# NeuraCore-Final.net
KiCad netlist of a schematic drawn in EasyEDA Pro
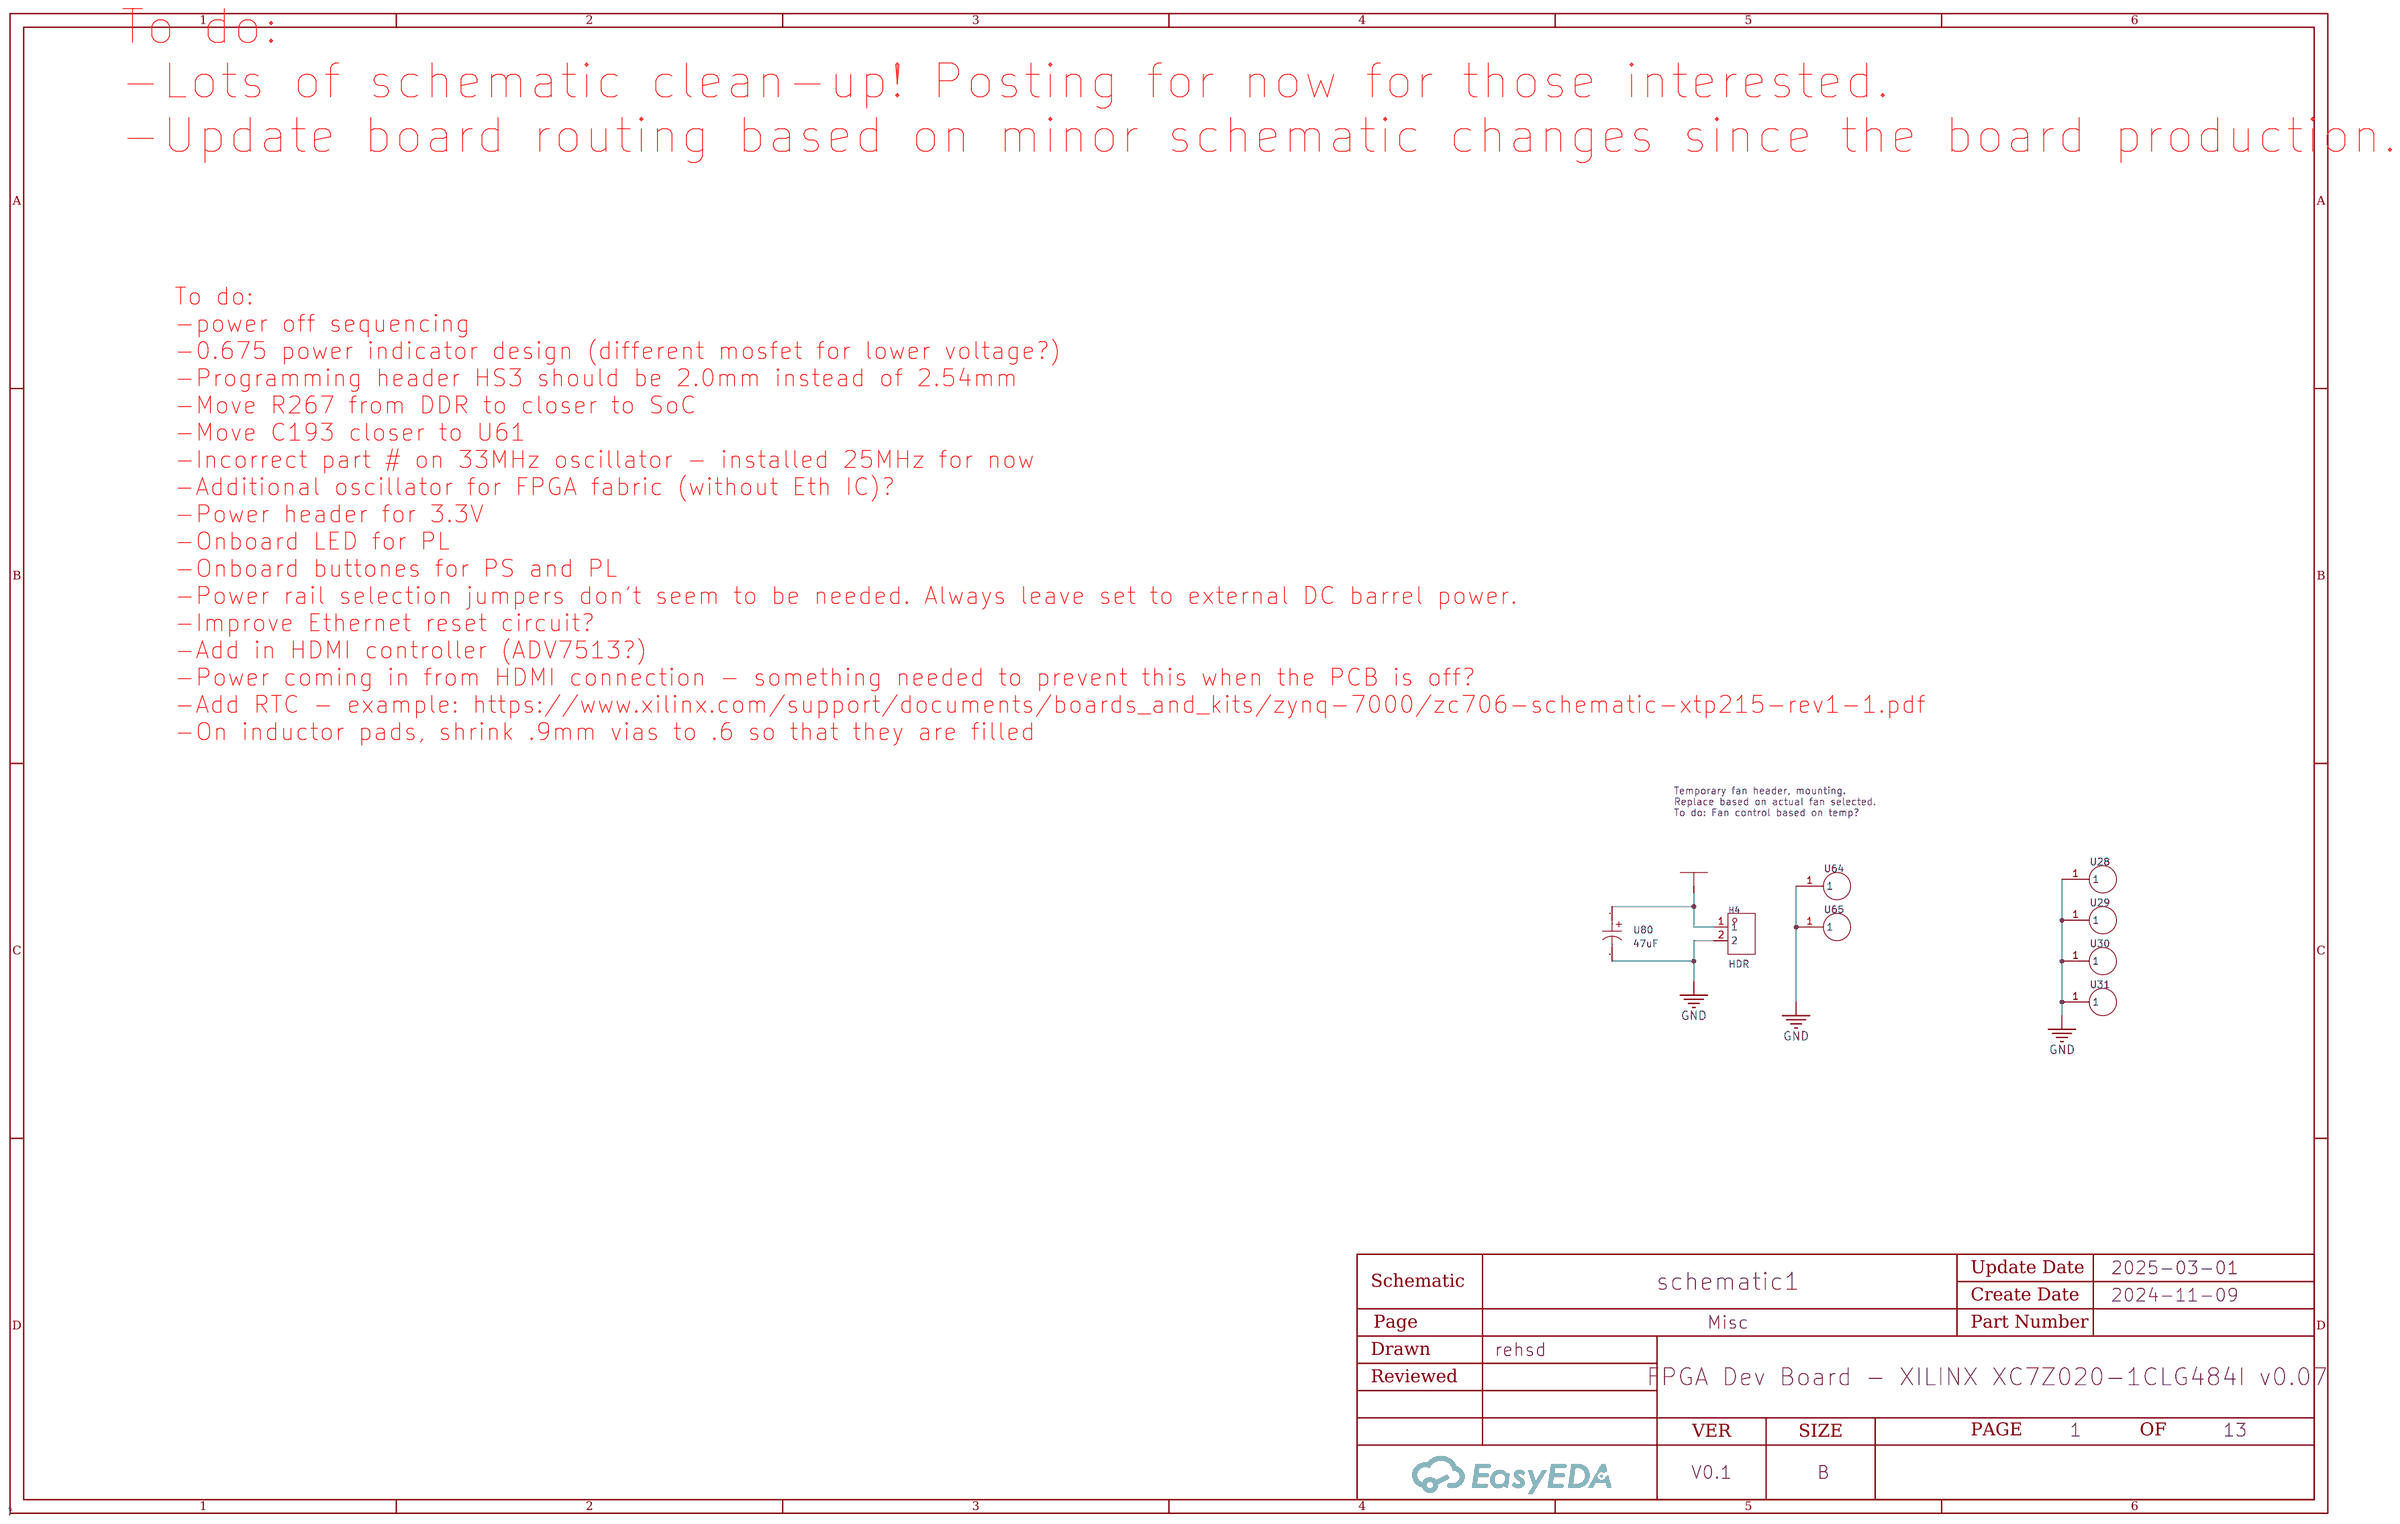
[diagram p0: Misc]
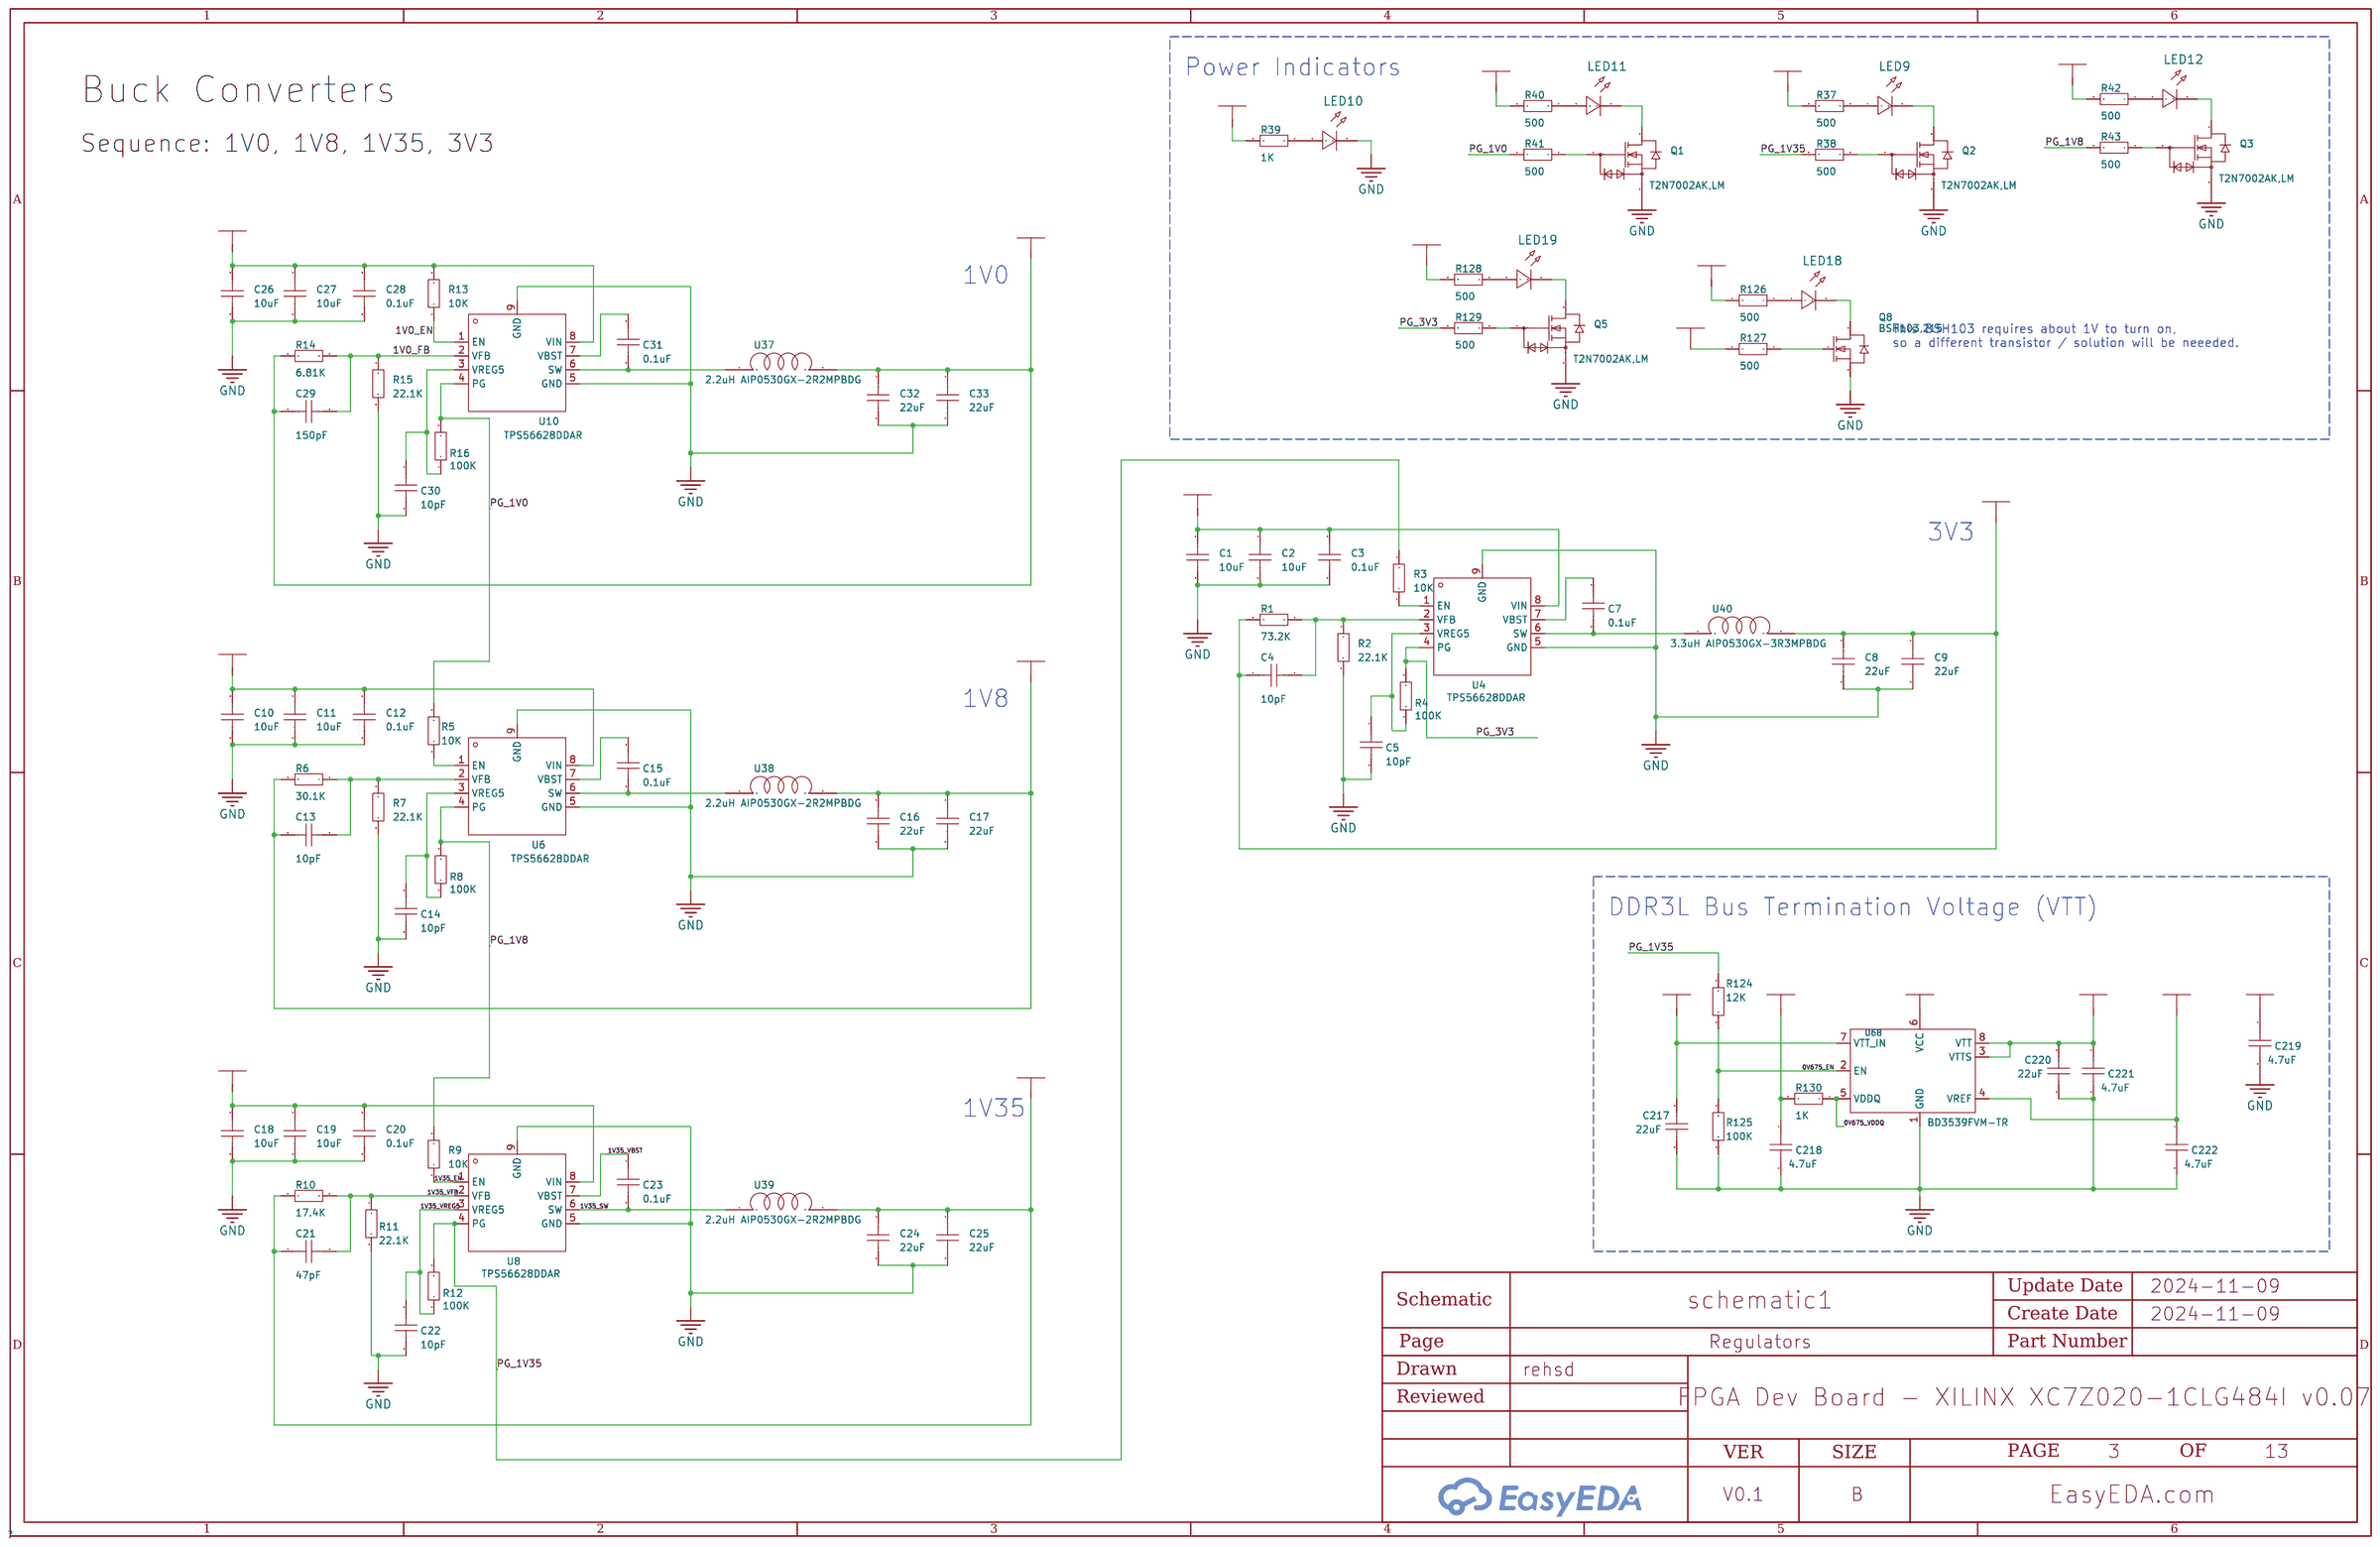
[diagram p1: Regulators]
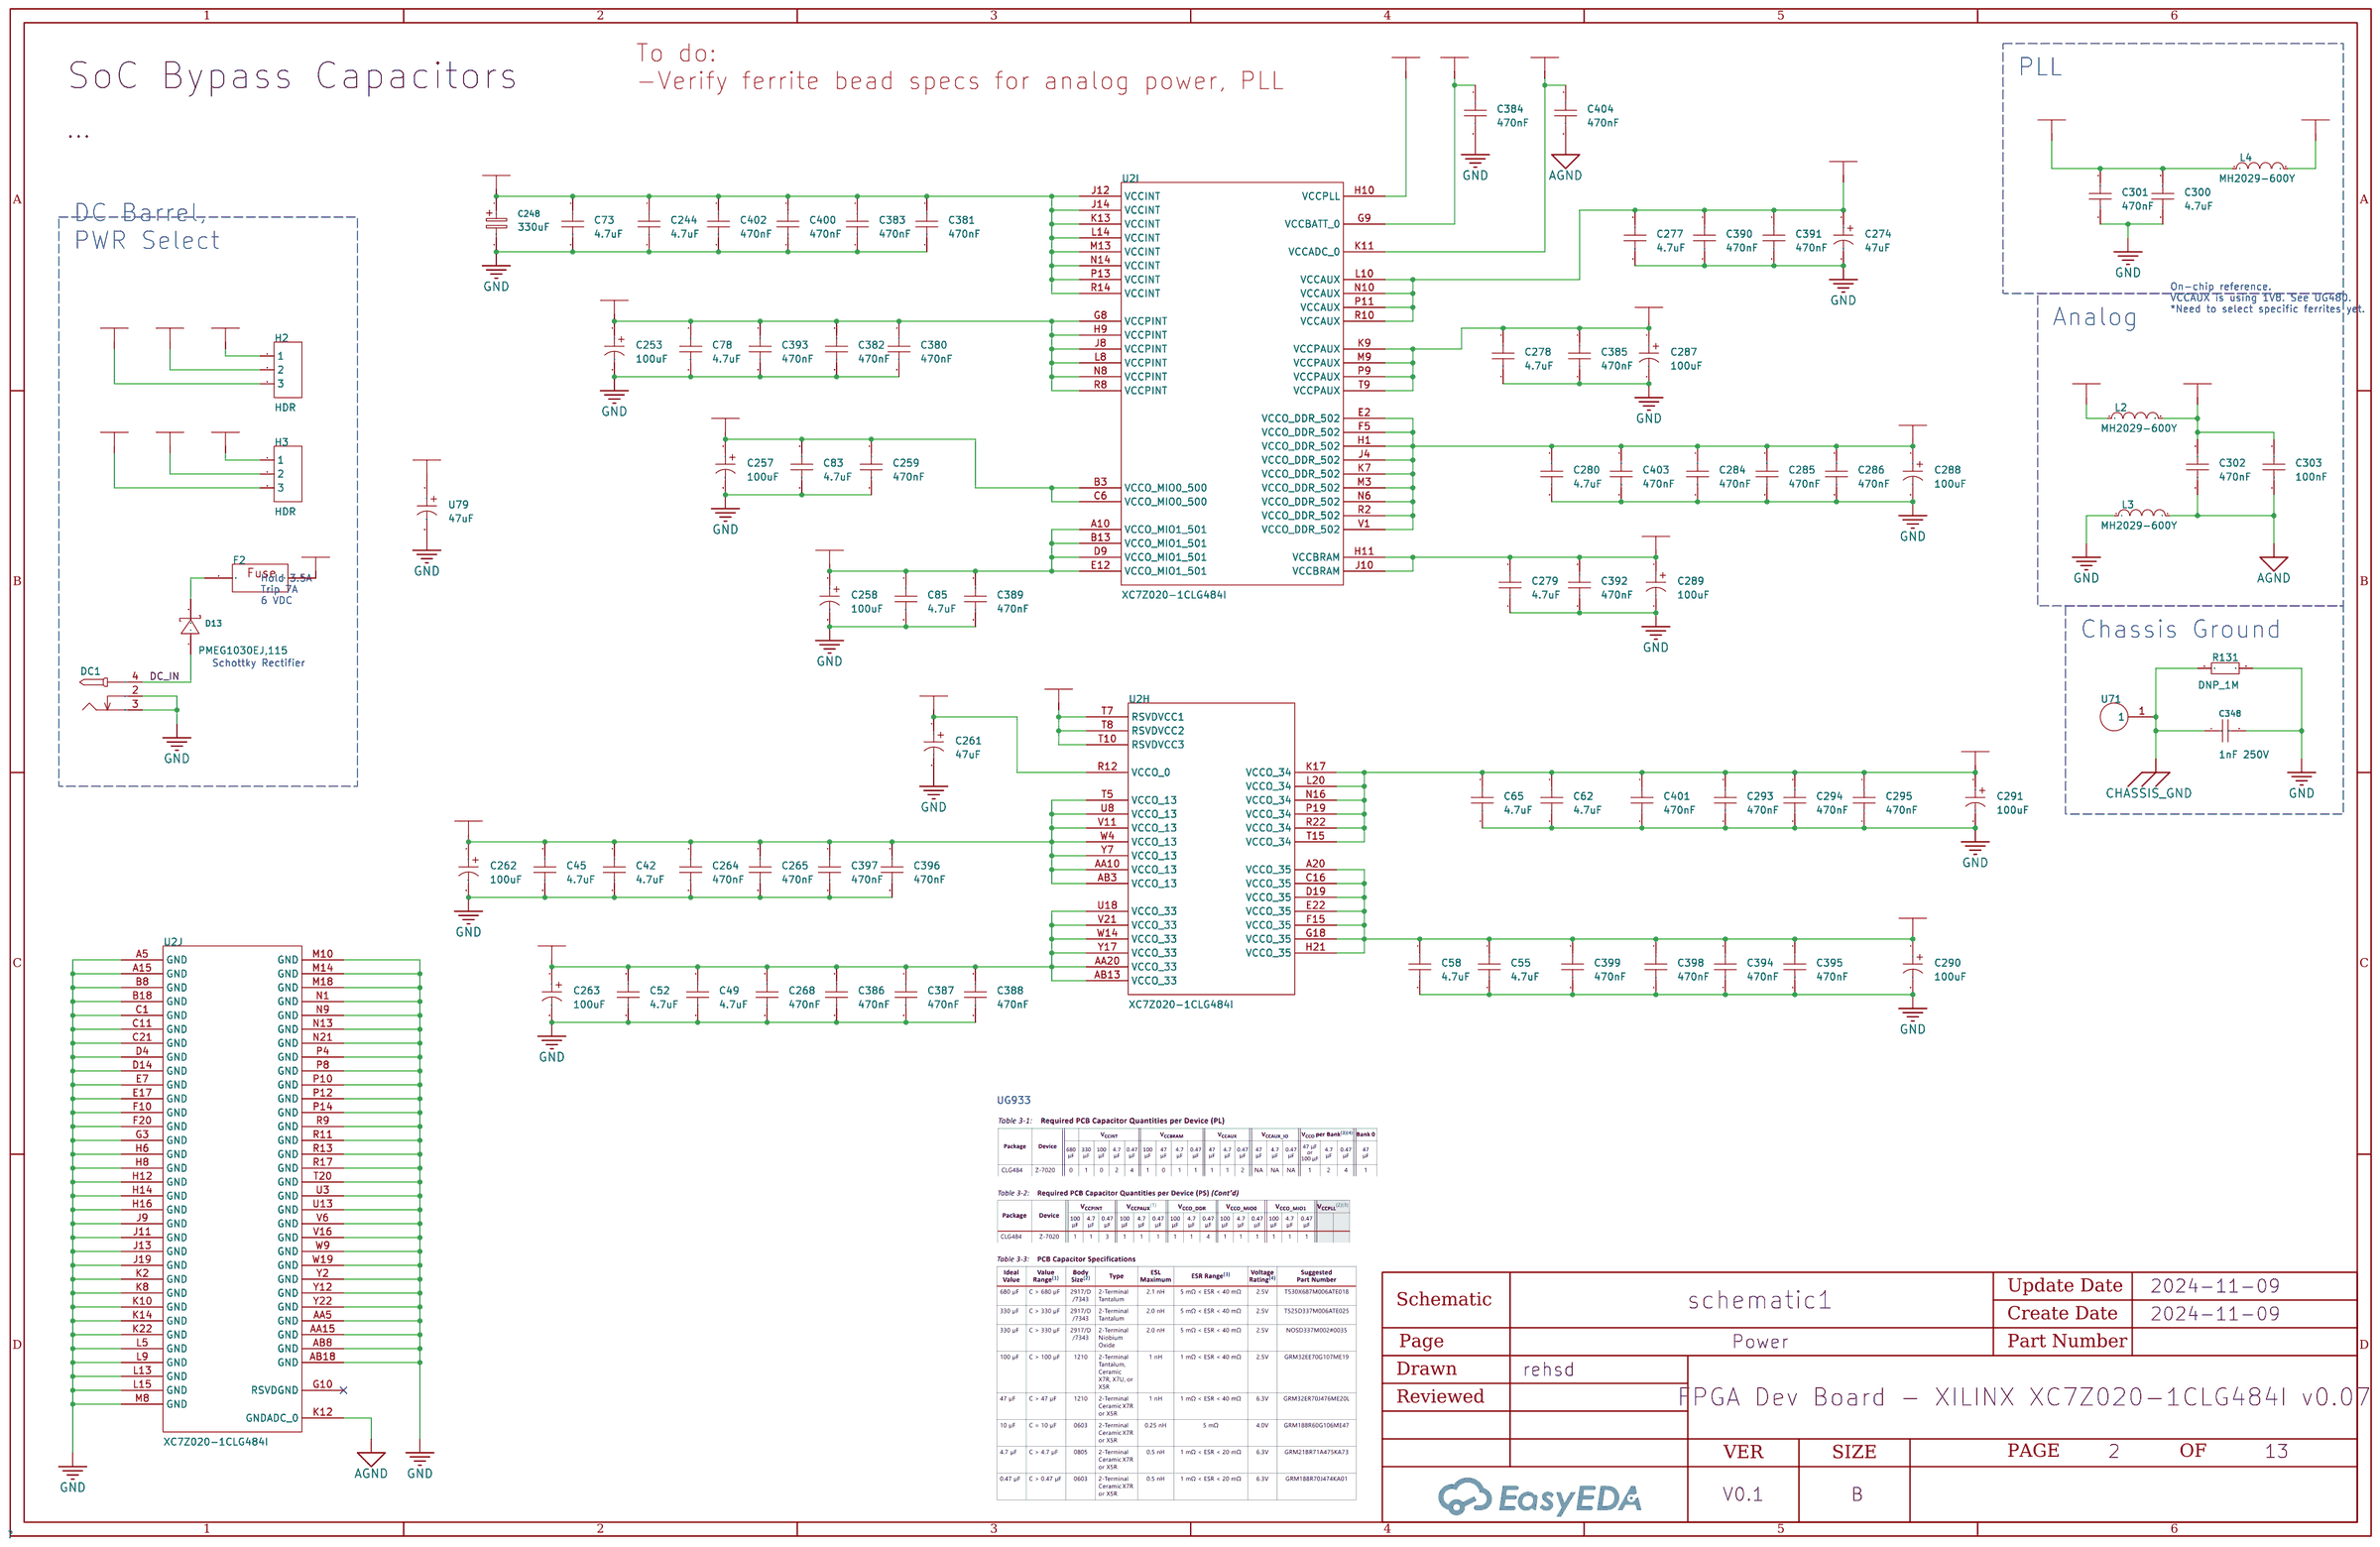
[diagram p2: Power]
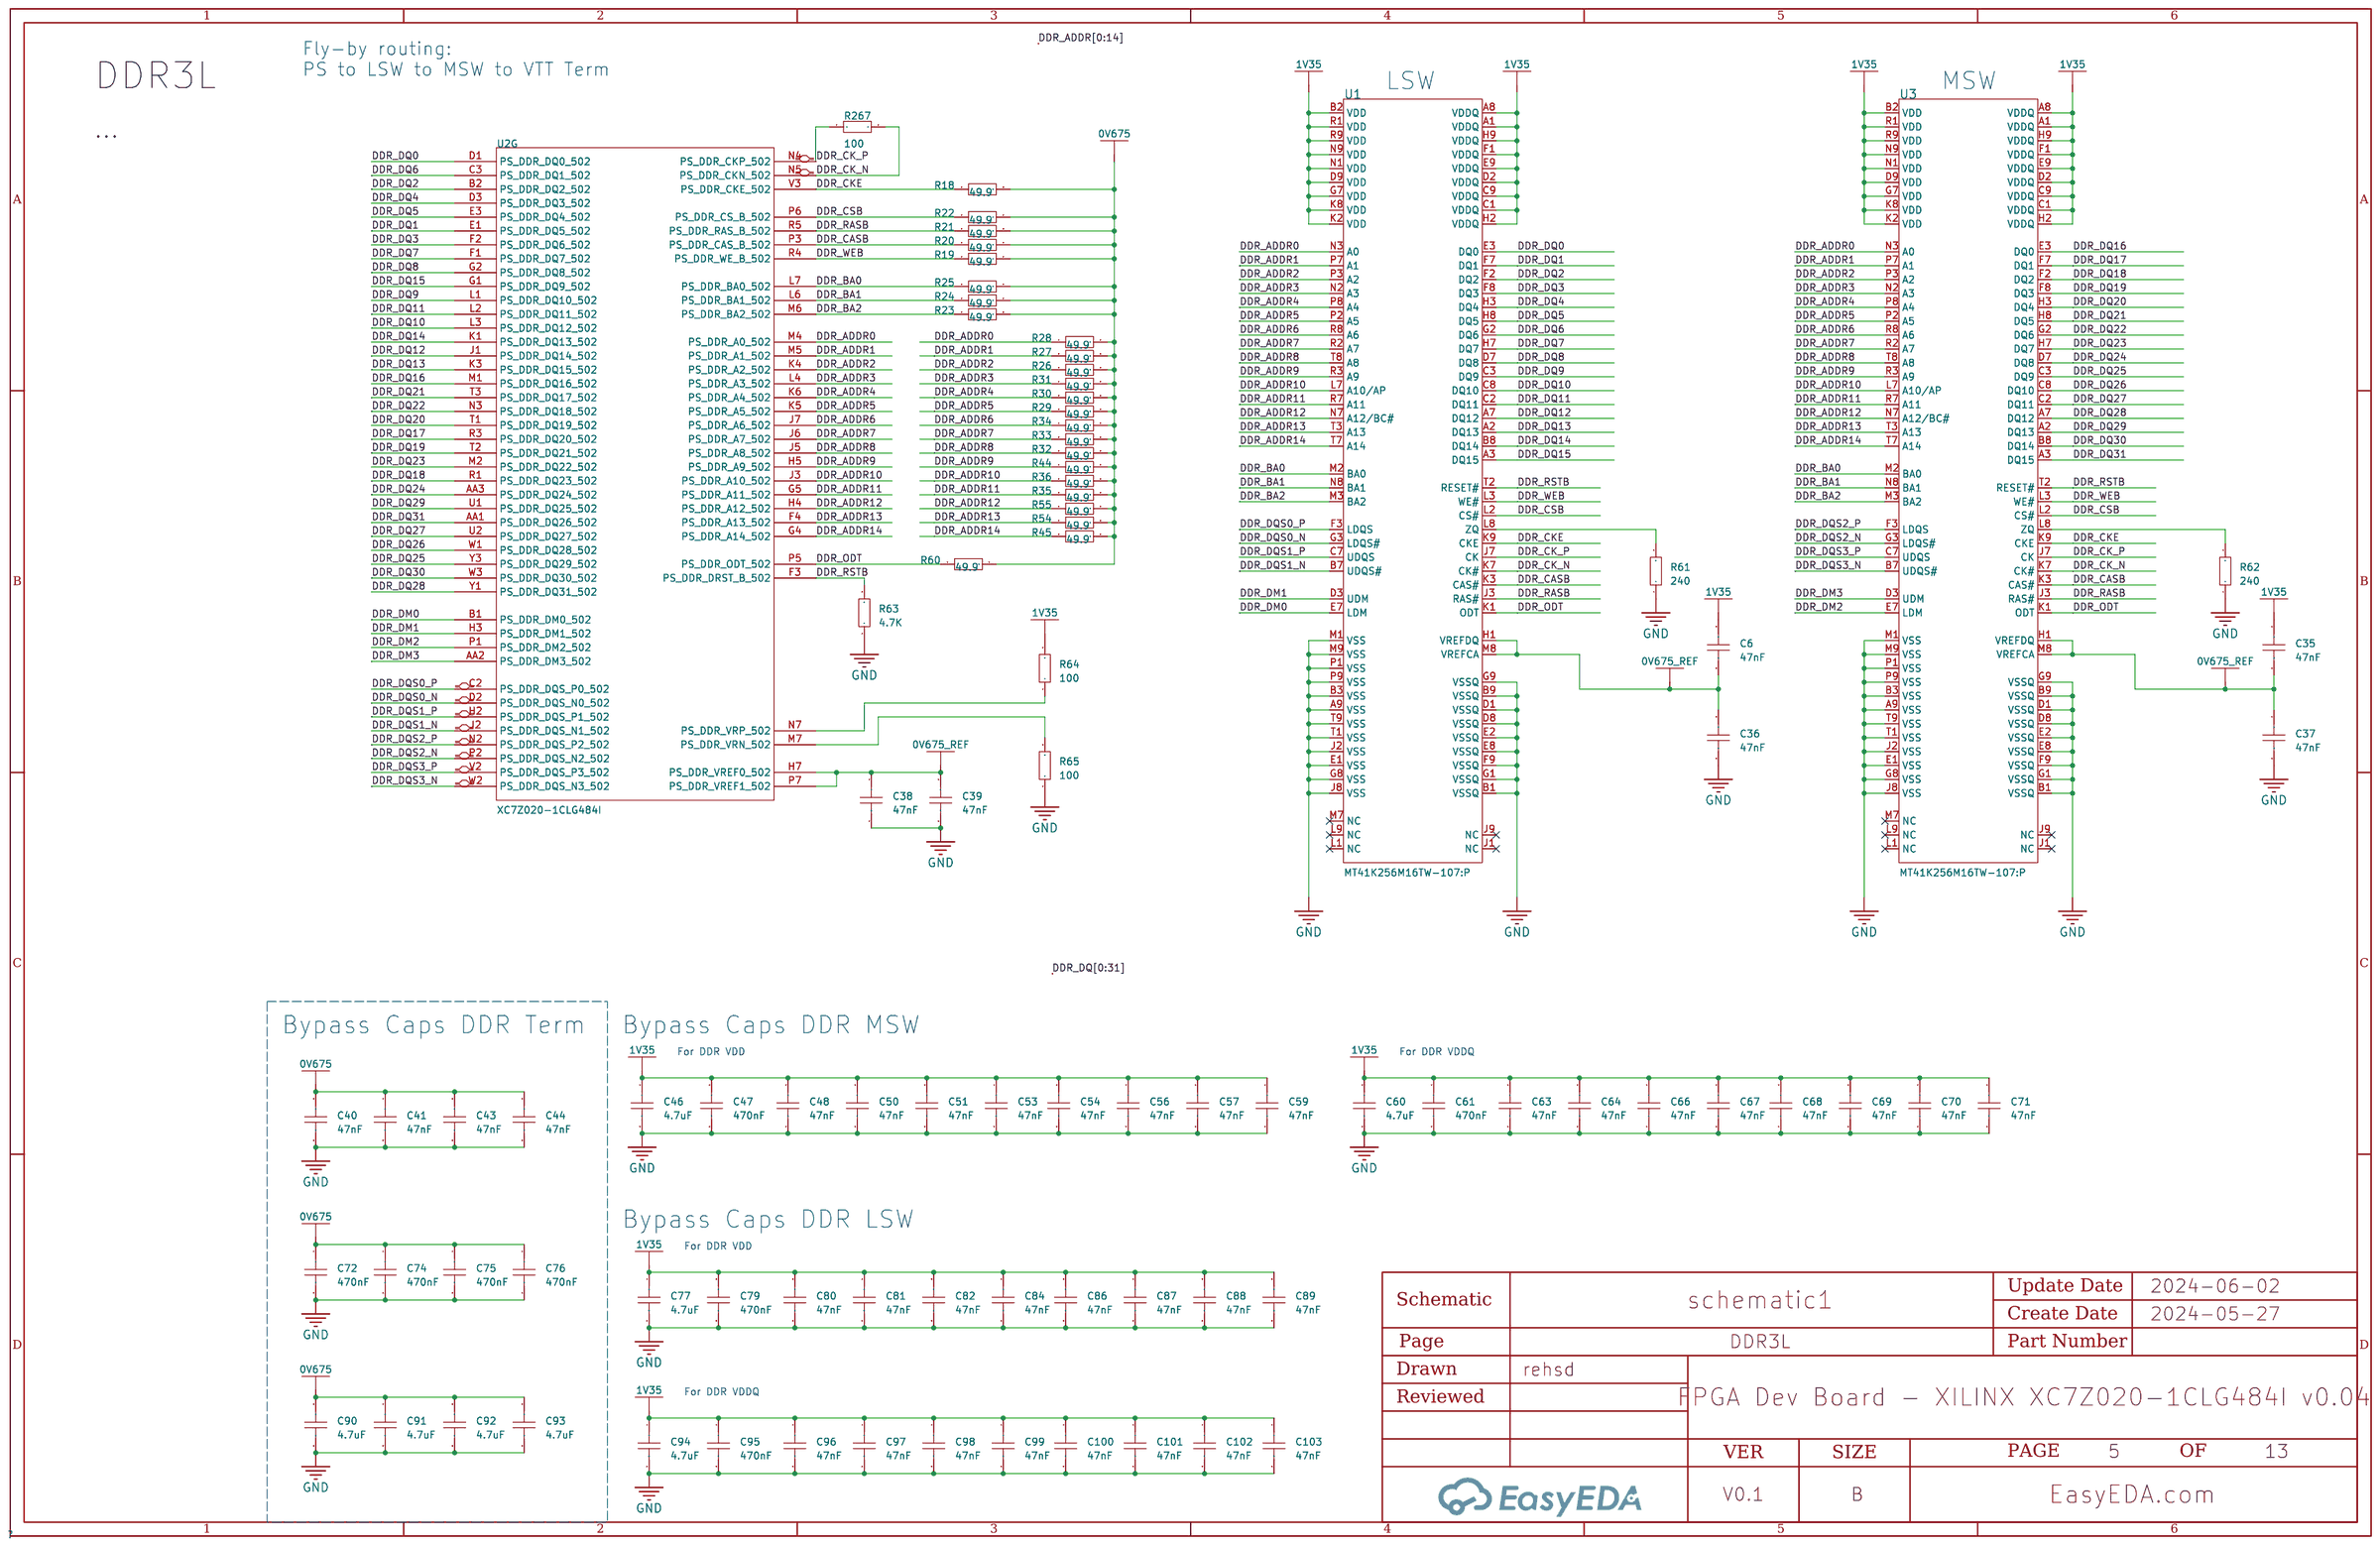
[diagram p3: DDR3L]
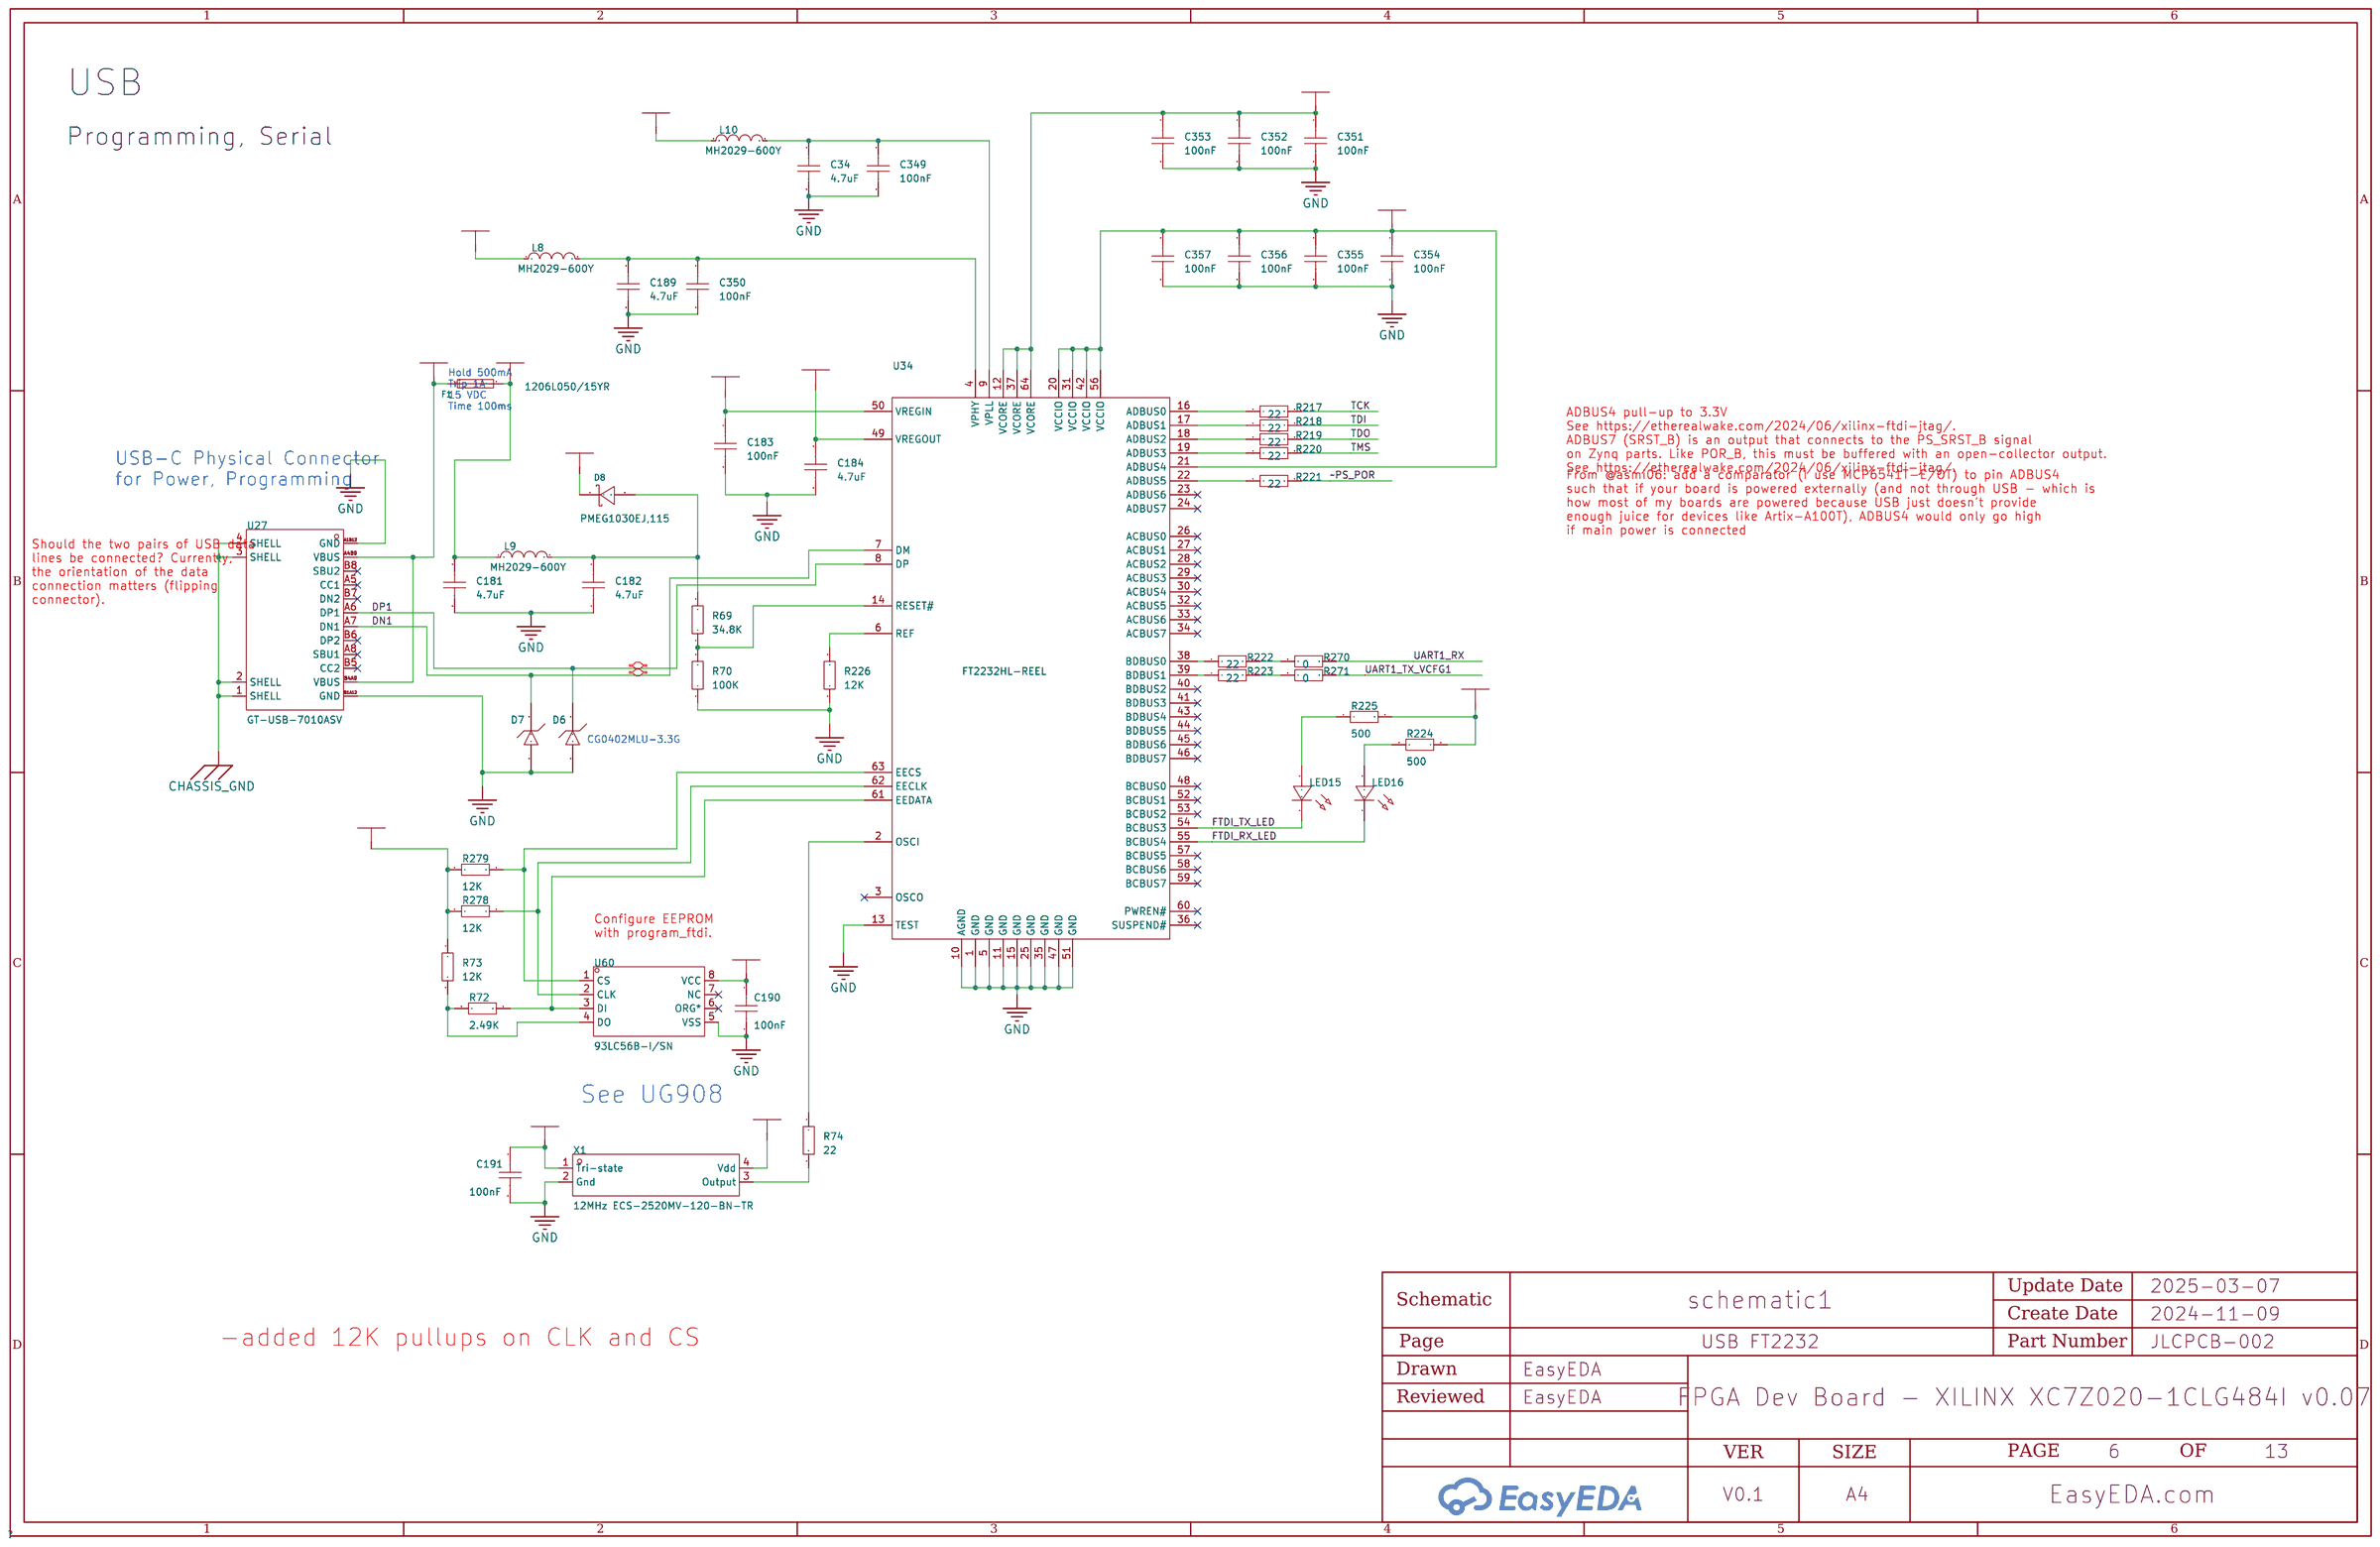
[diagram p4: USB FT2232]
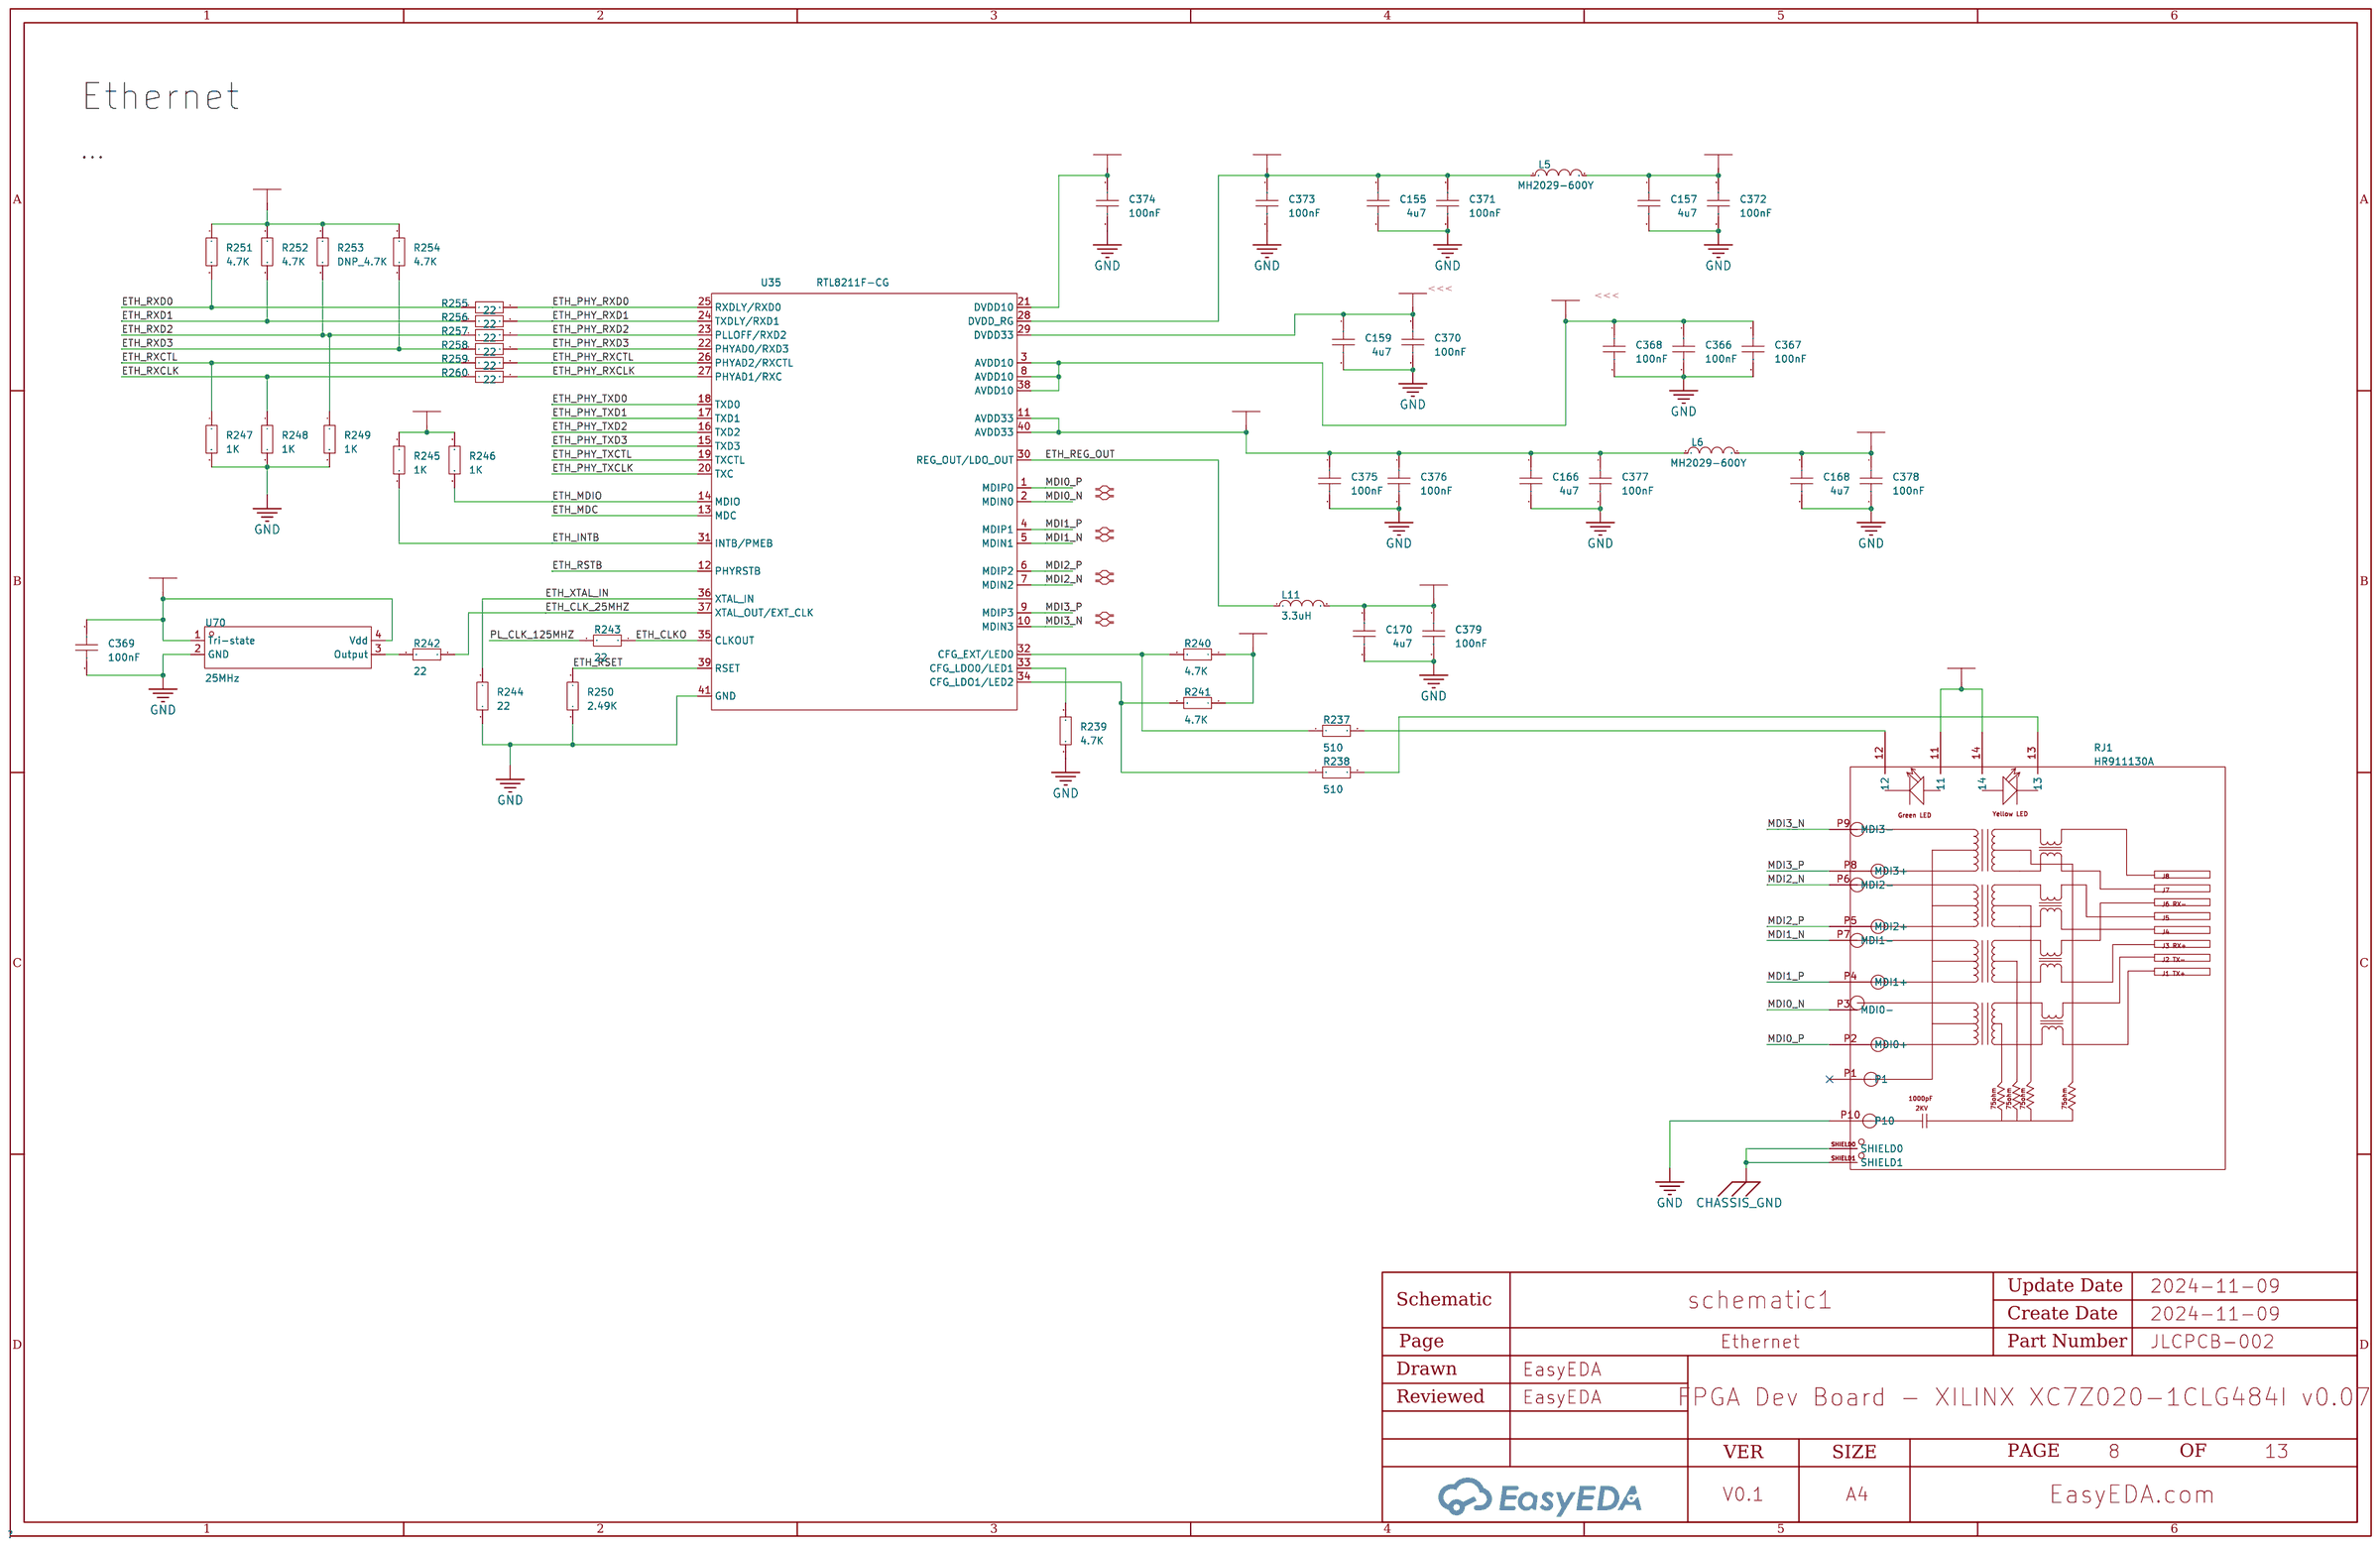
[diagram p5: Ethernet]
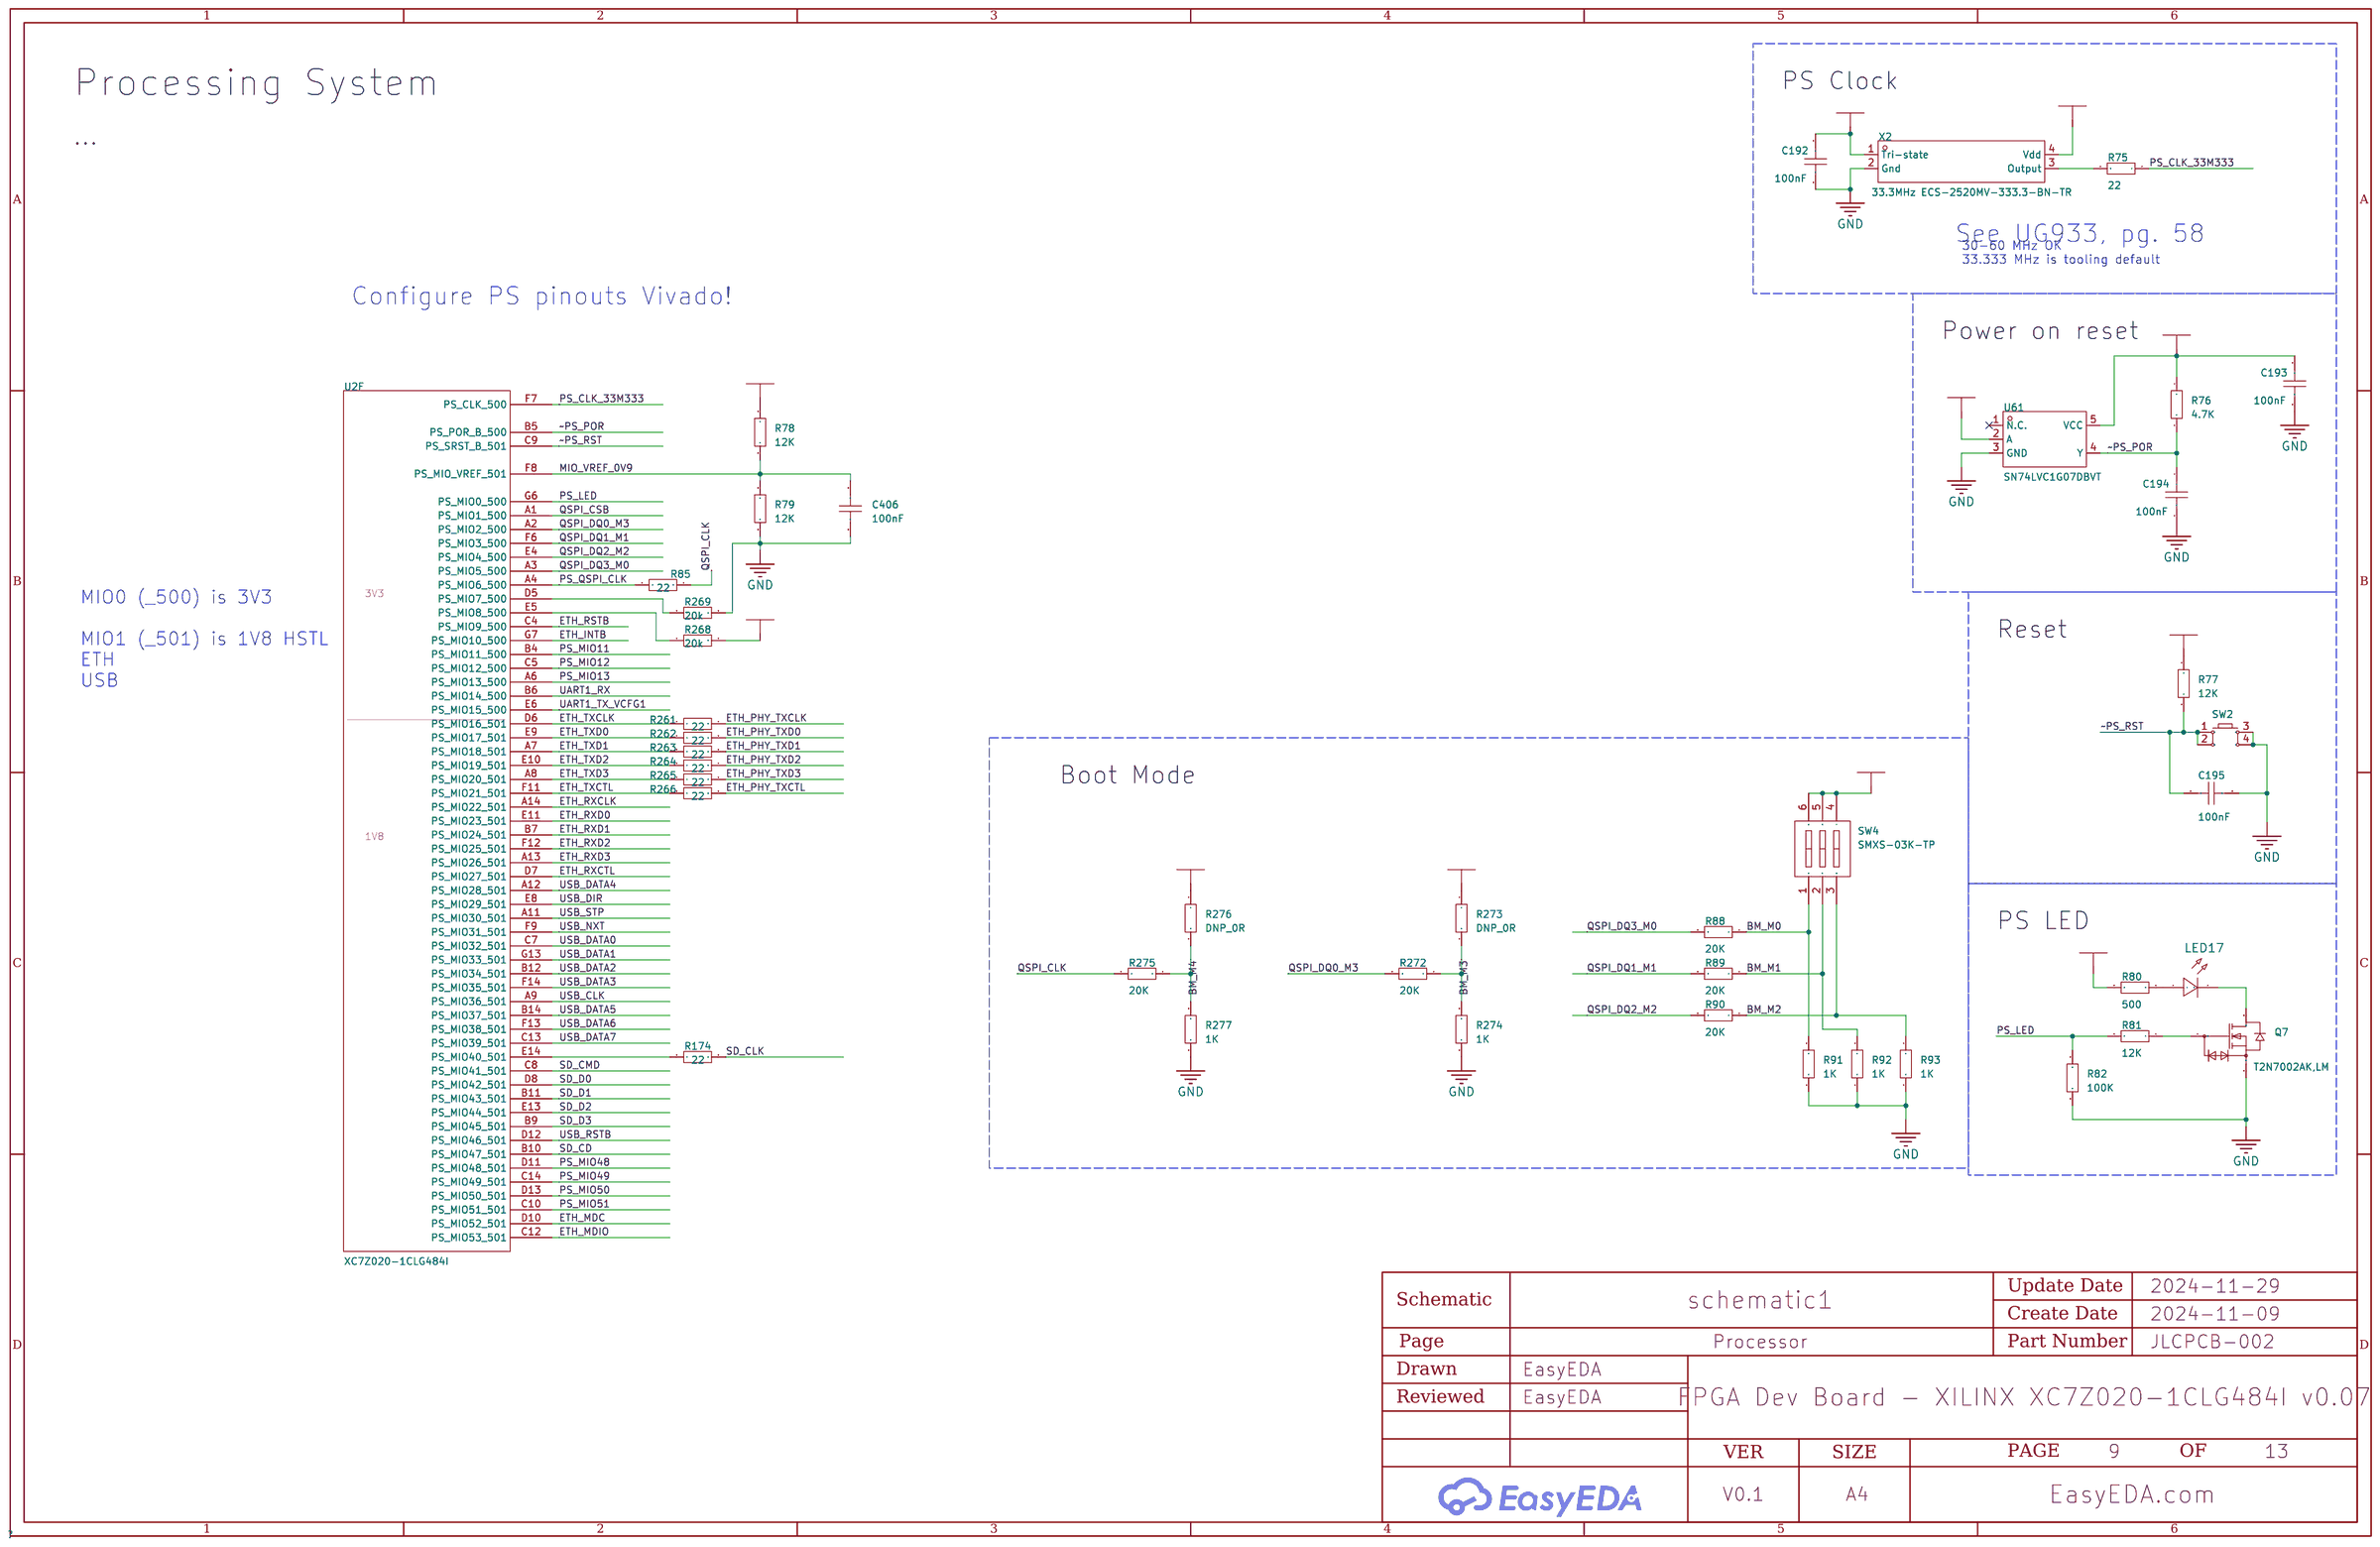
[diagram p6: Processor]
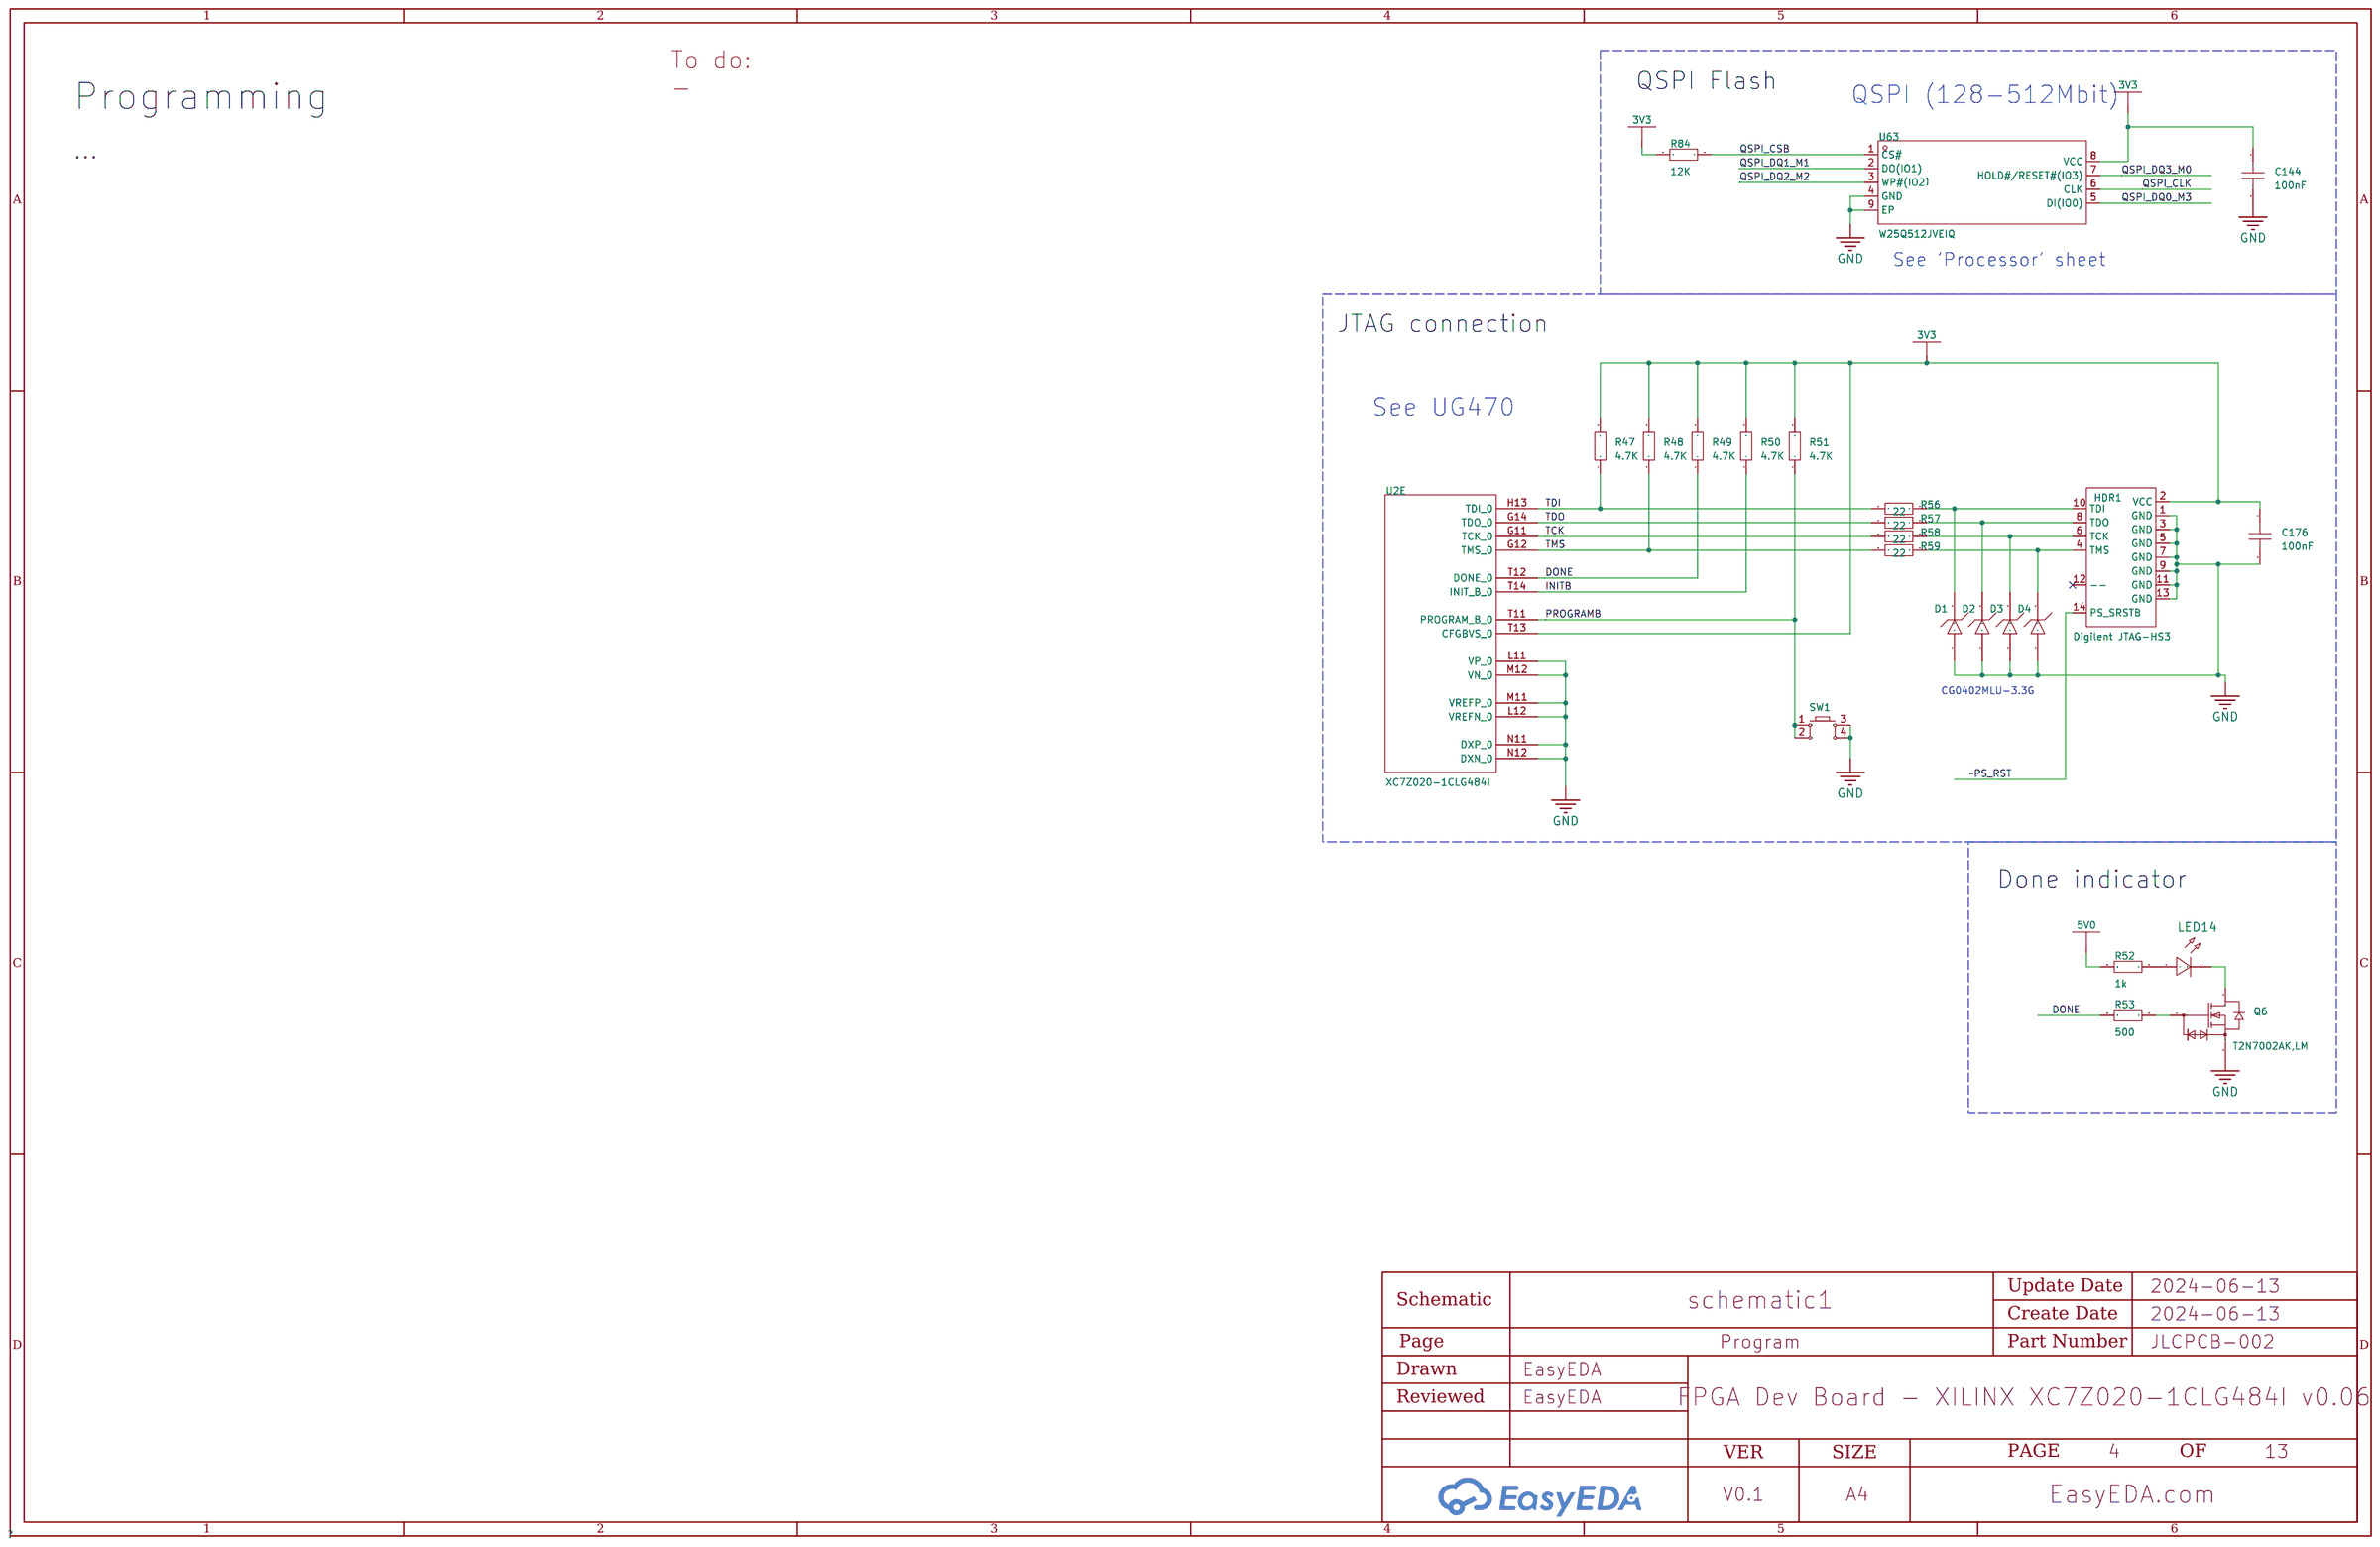
[diagram p7: Program]
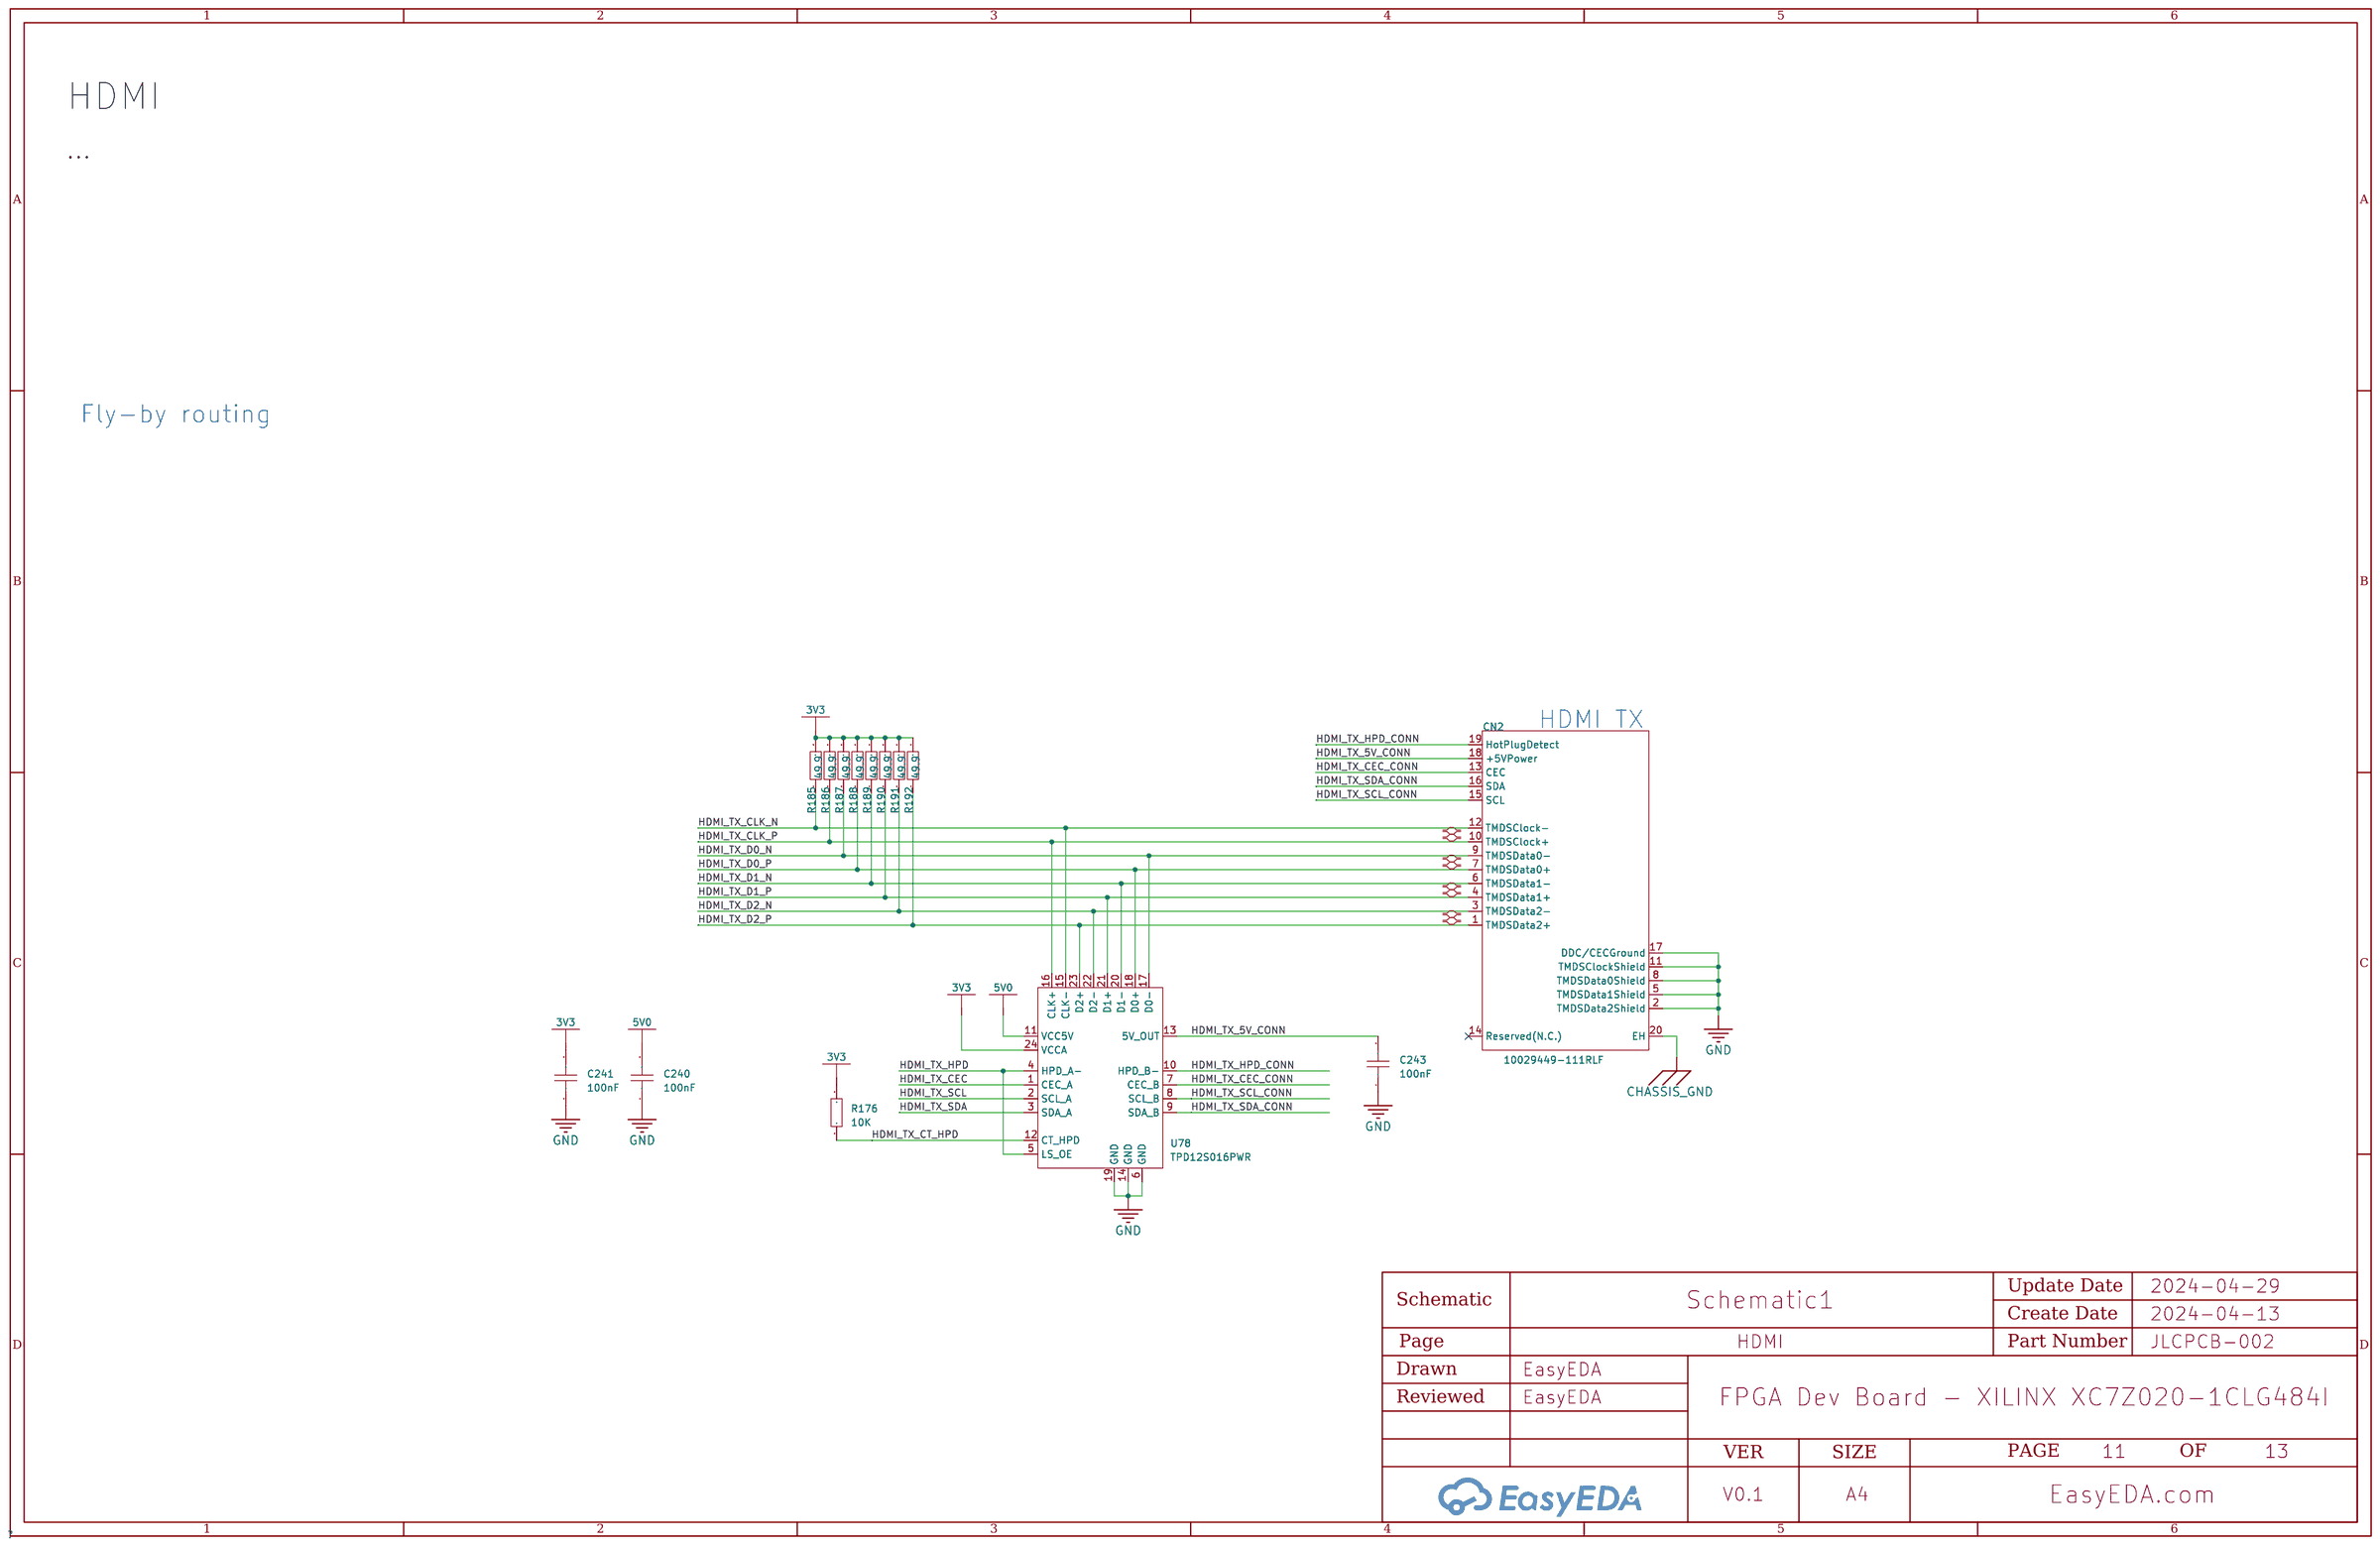
[diagram p8: HDMI]
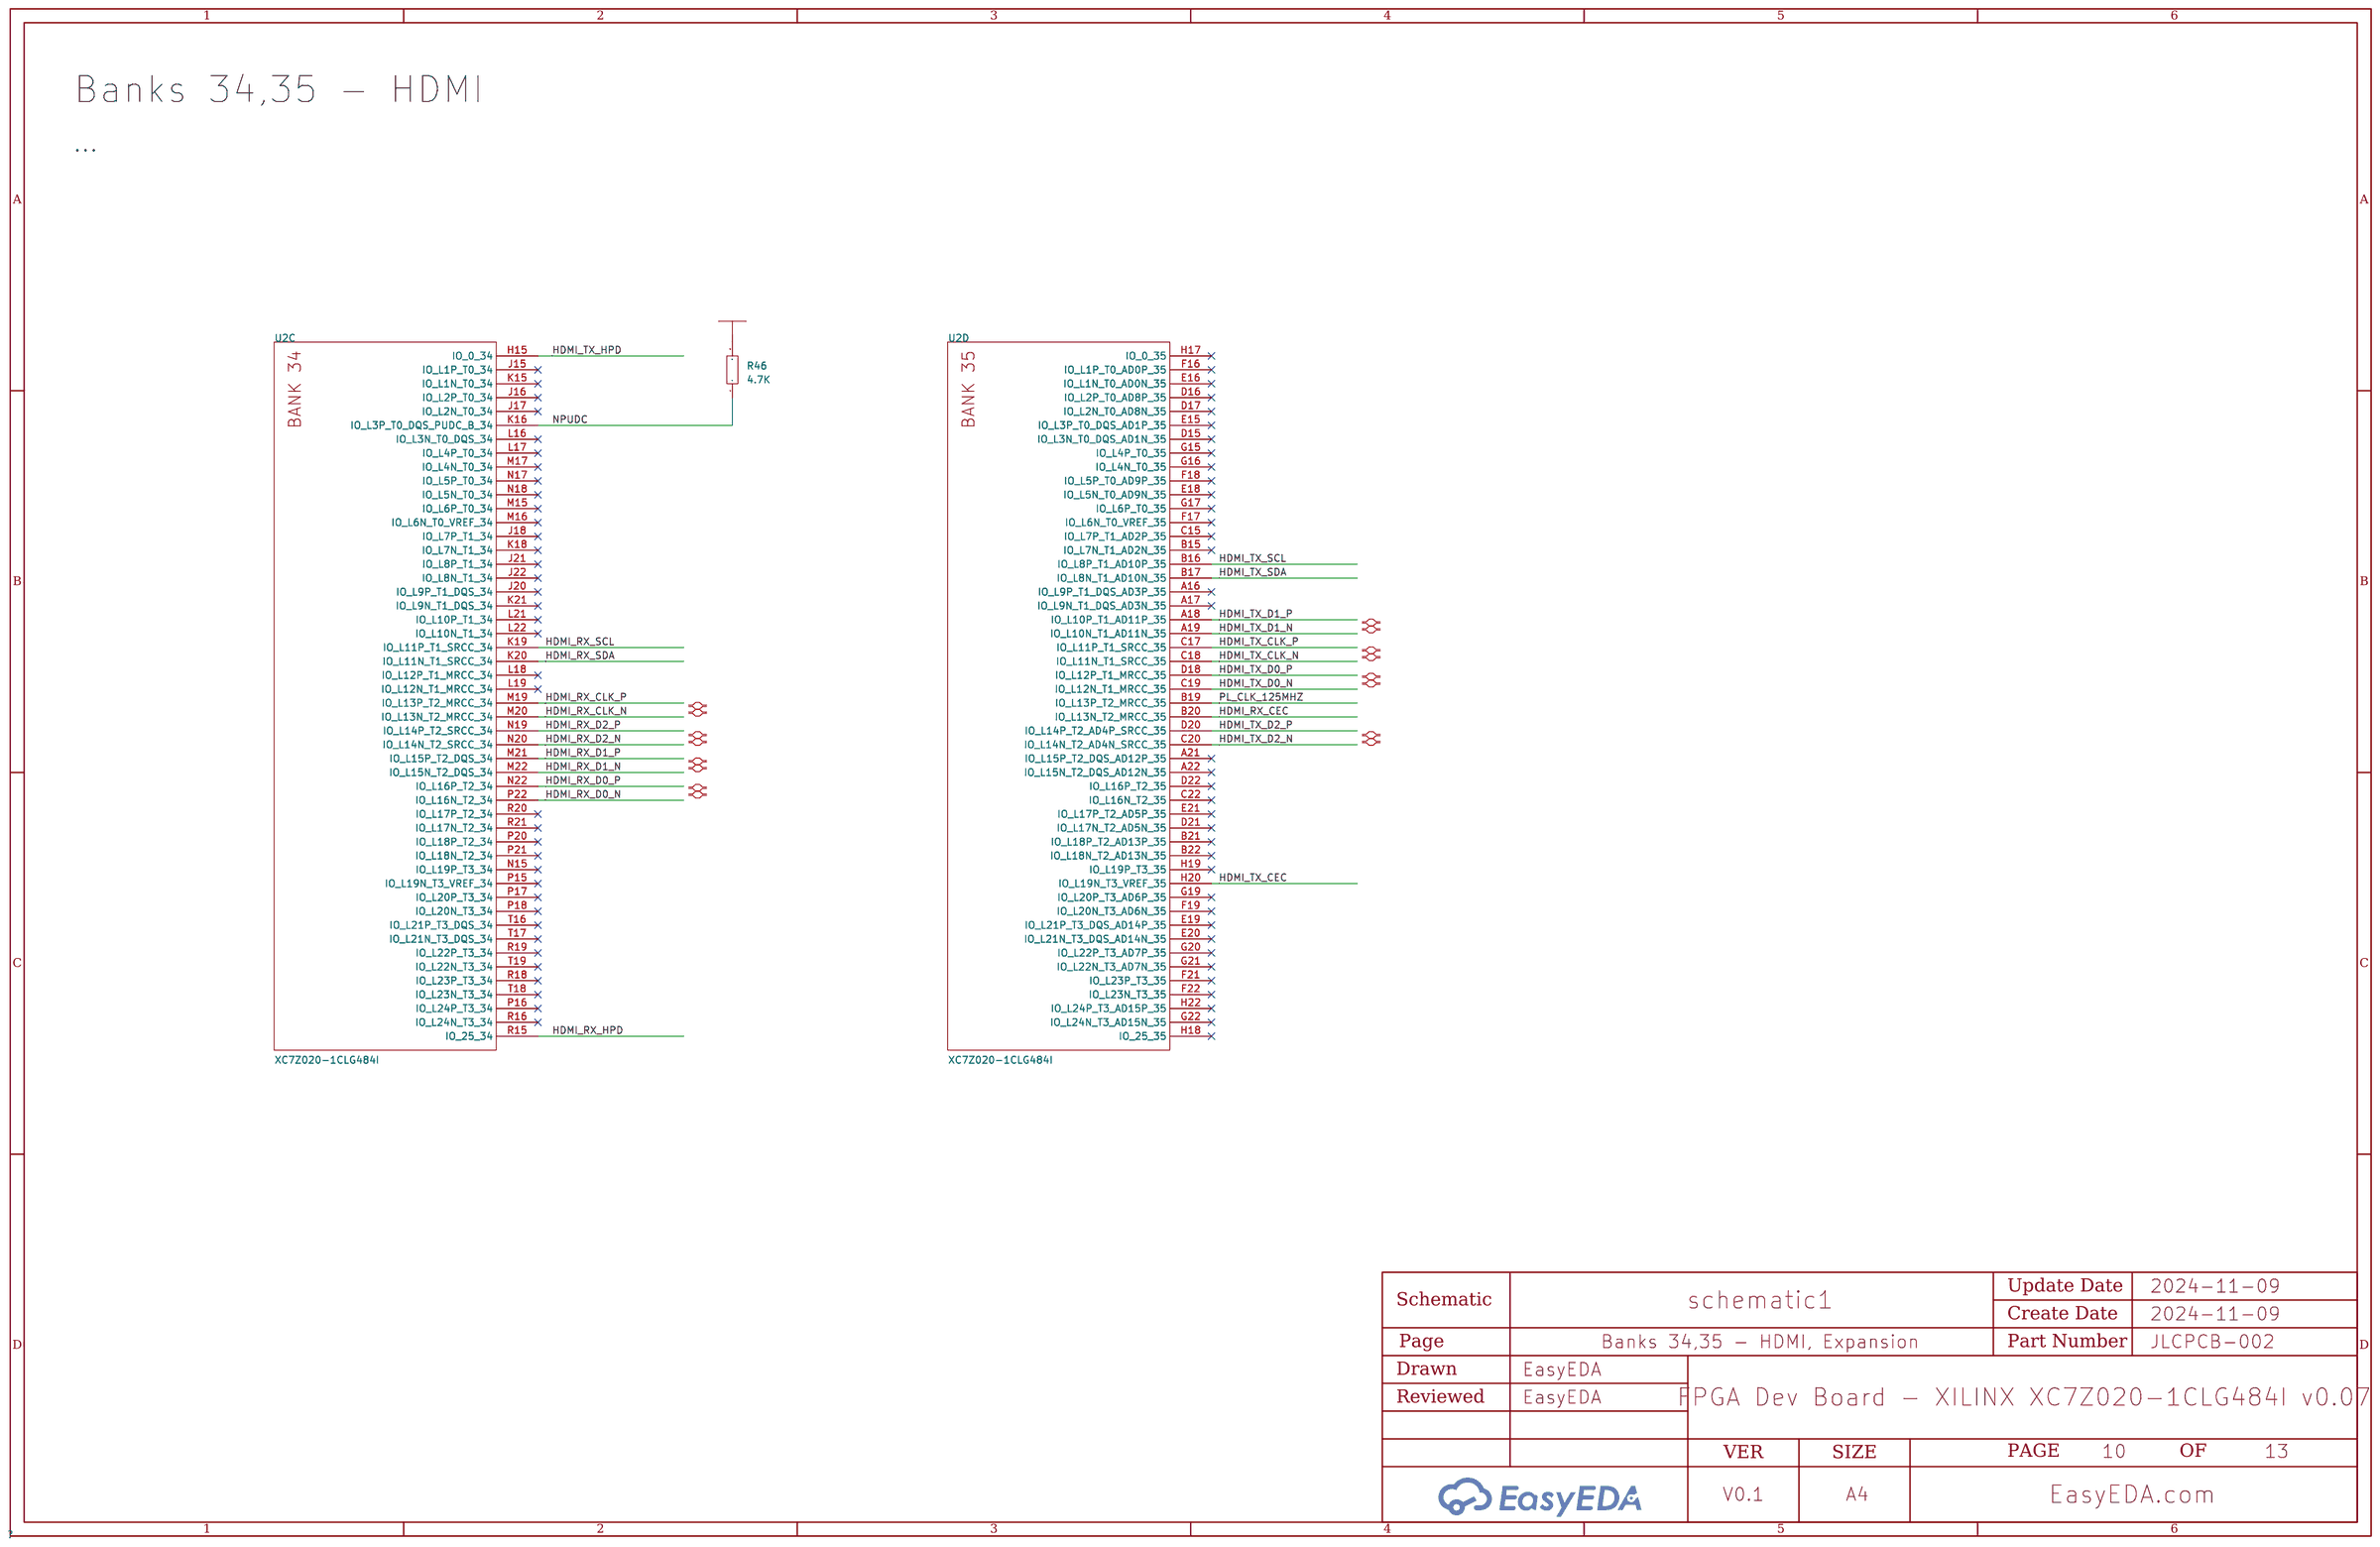
[diagram p9: Banks 34,35 - HDMI, unused]
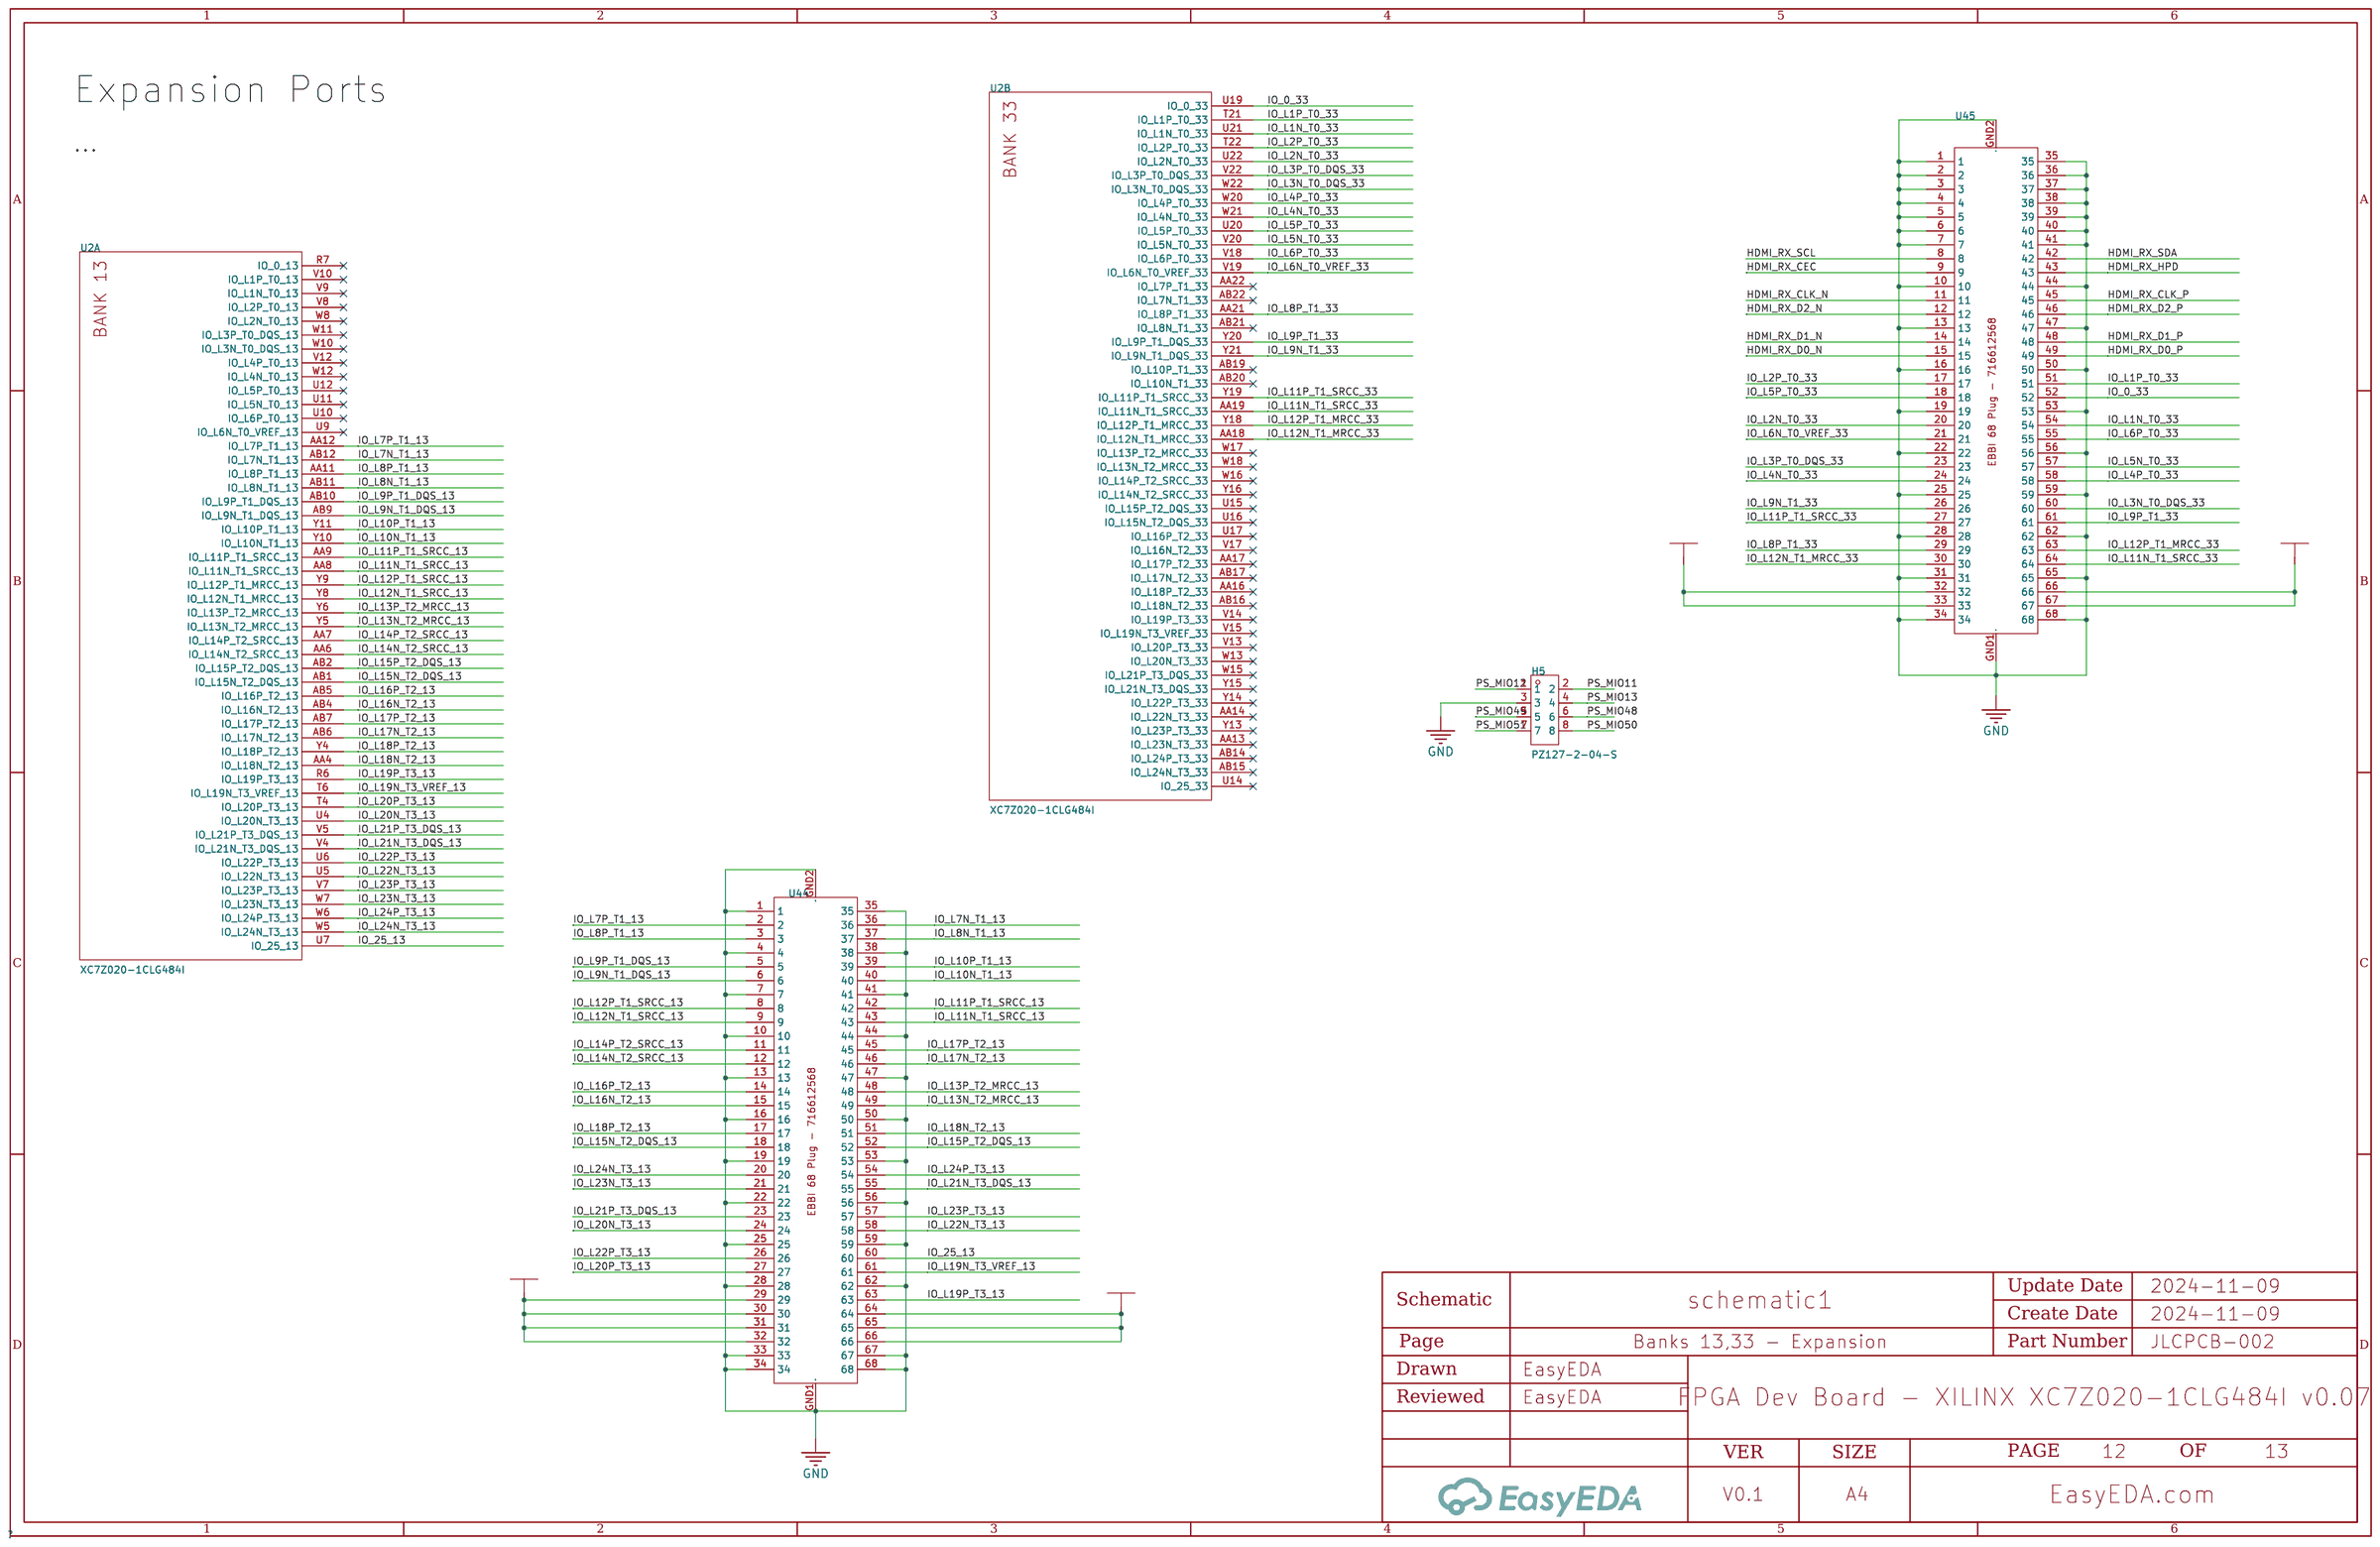
[diagram p10: Banks 13,33 - Expansion]
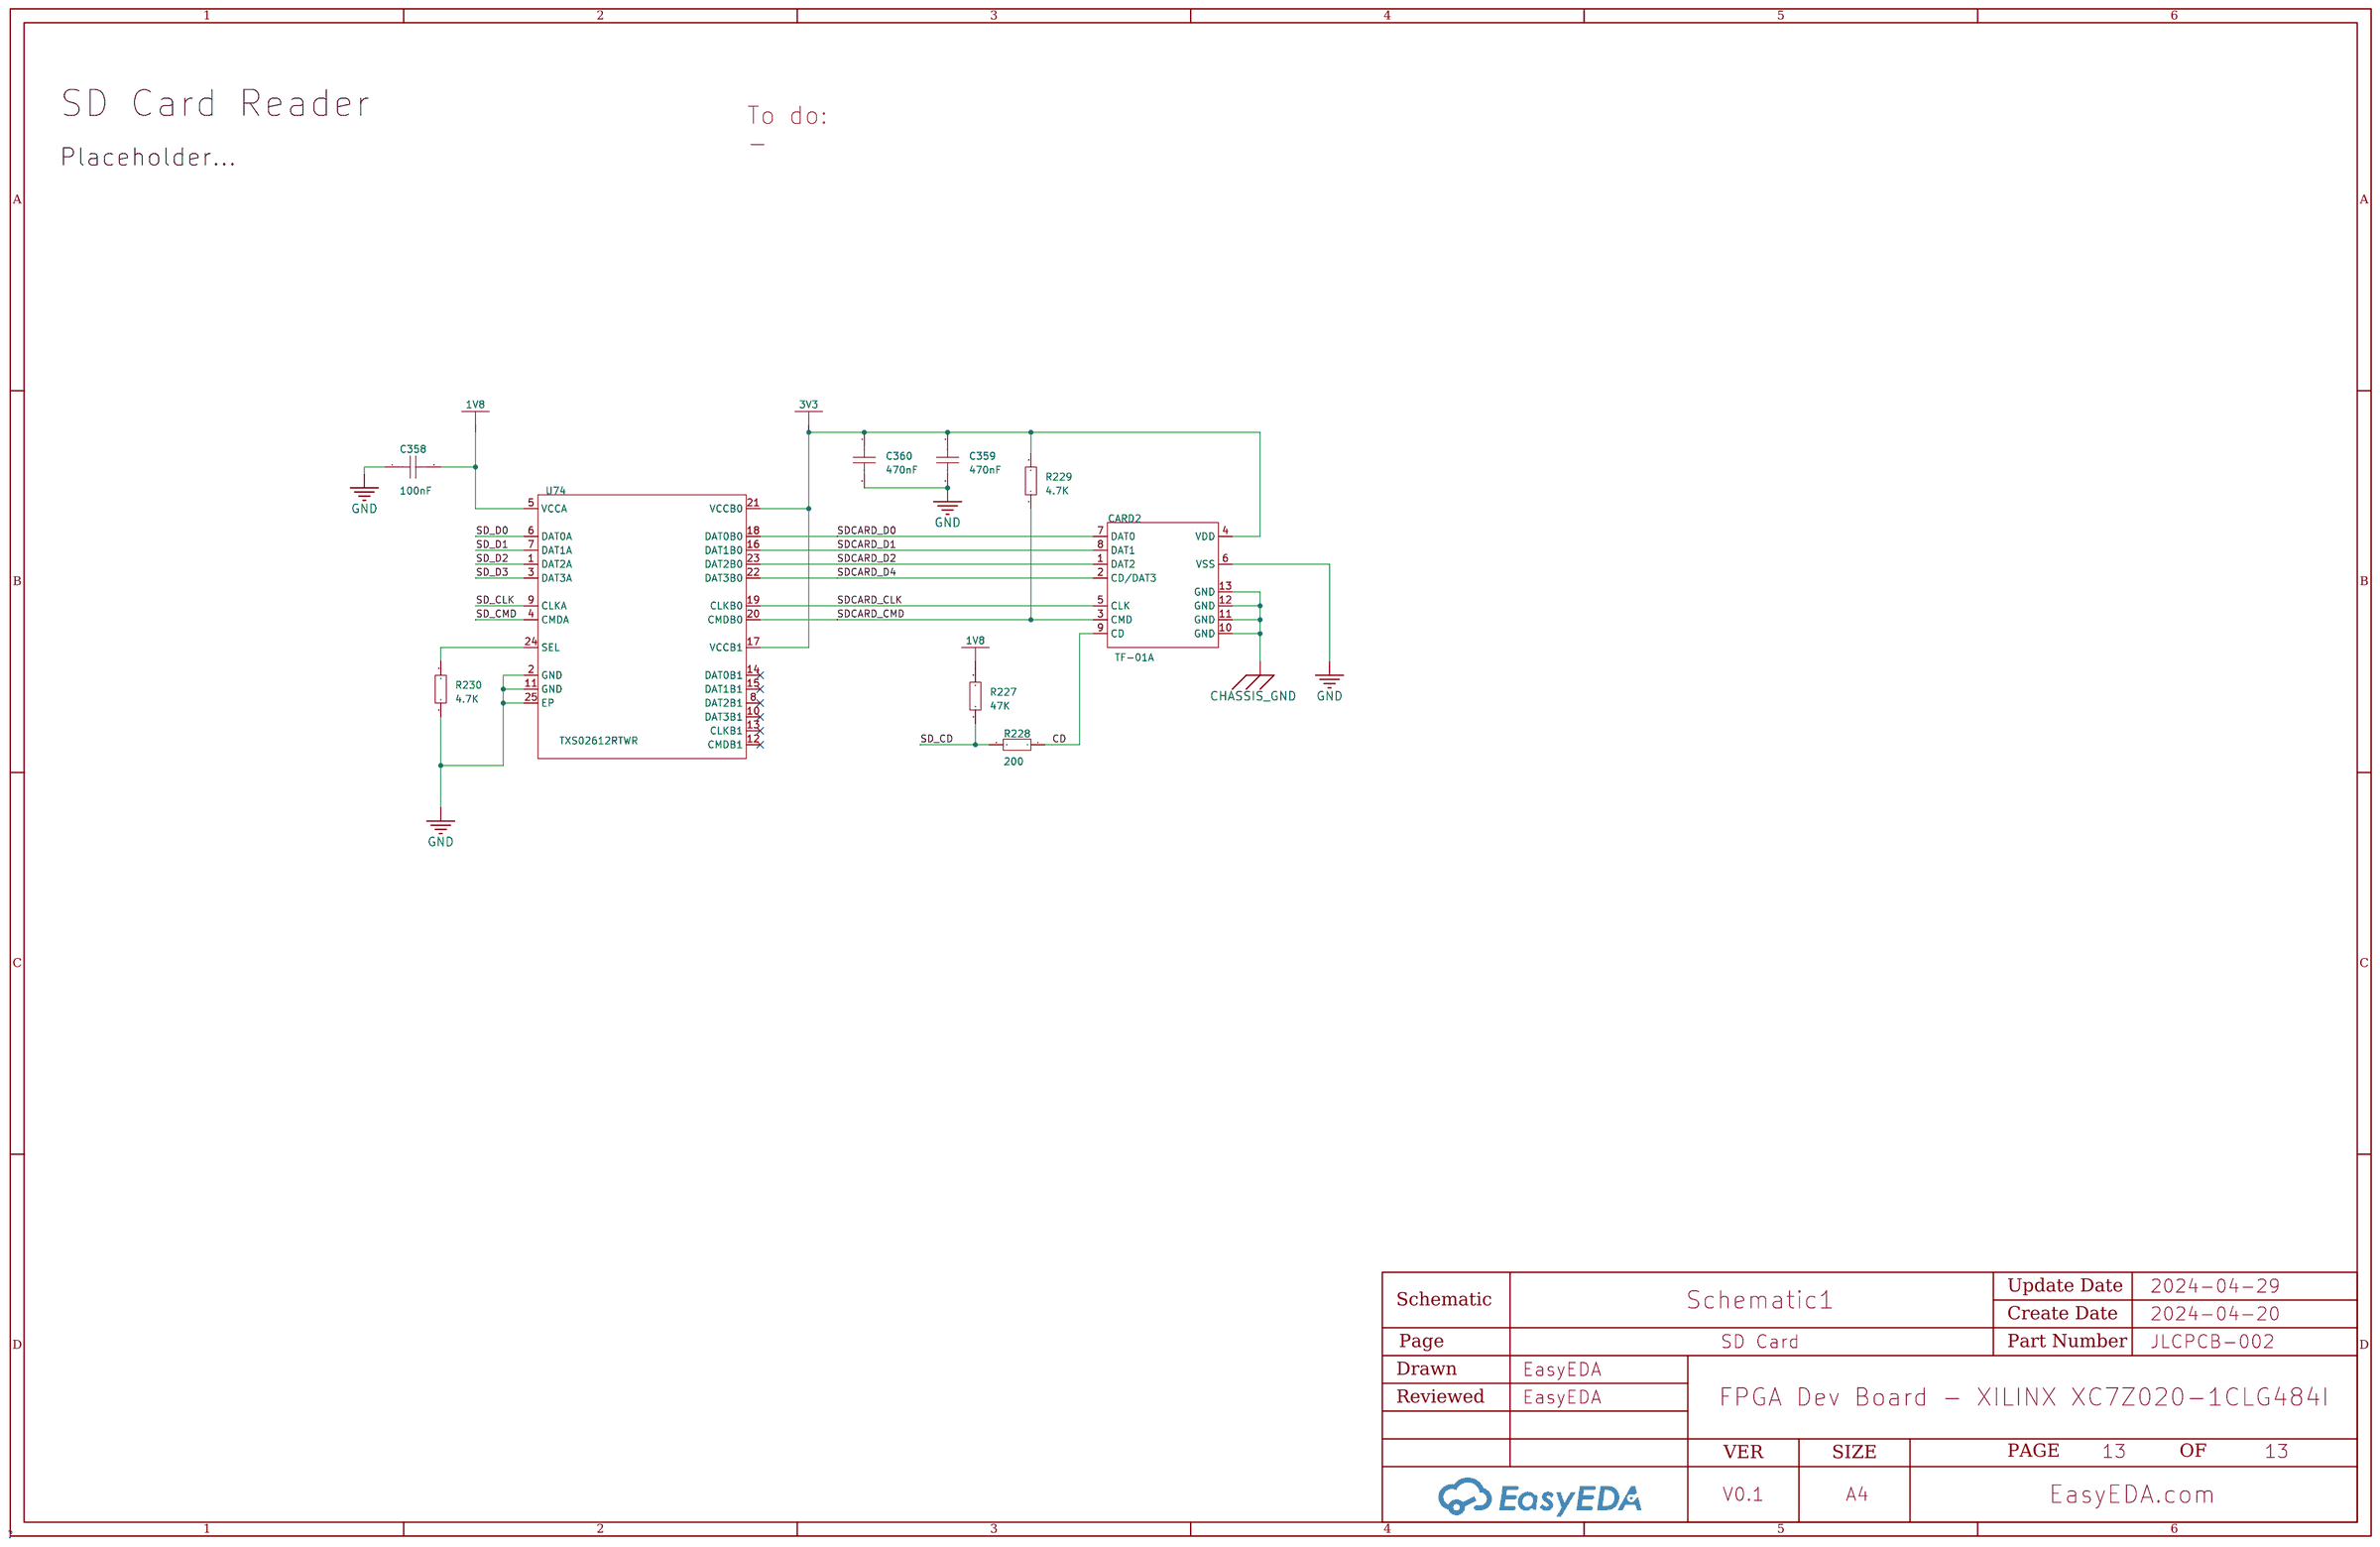
[diagram p11: SD Card]
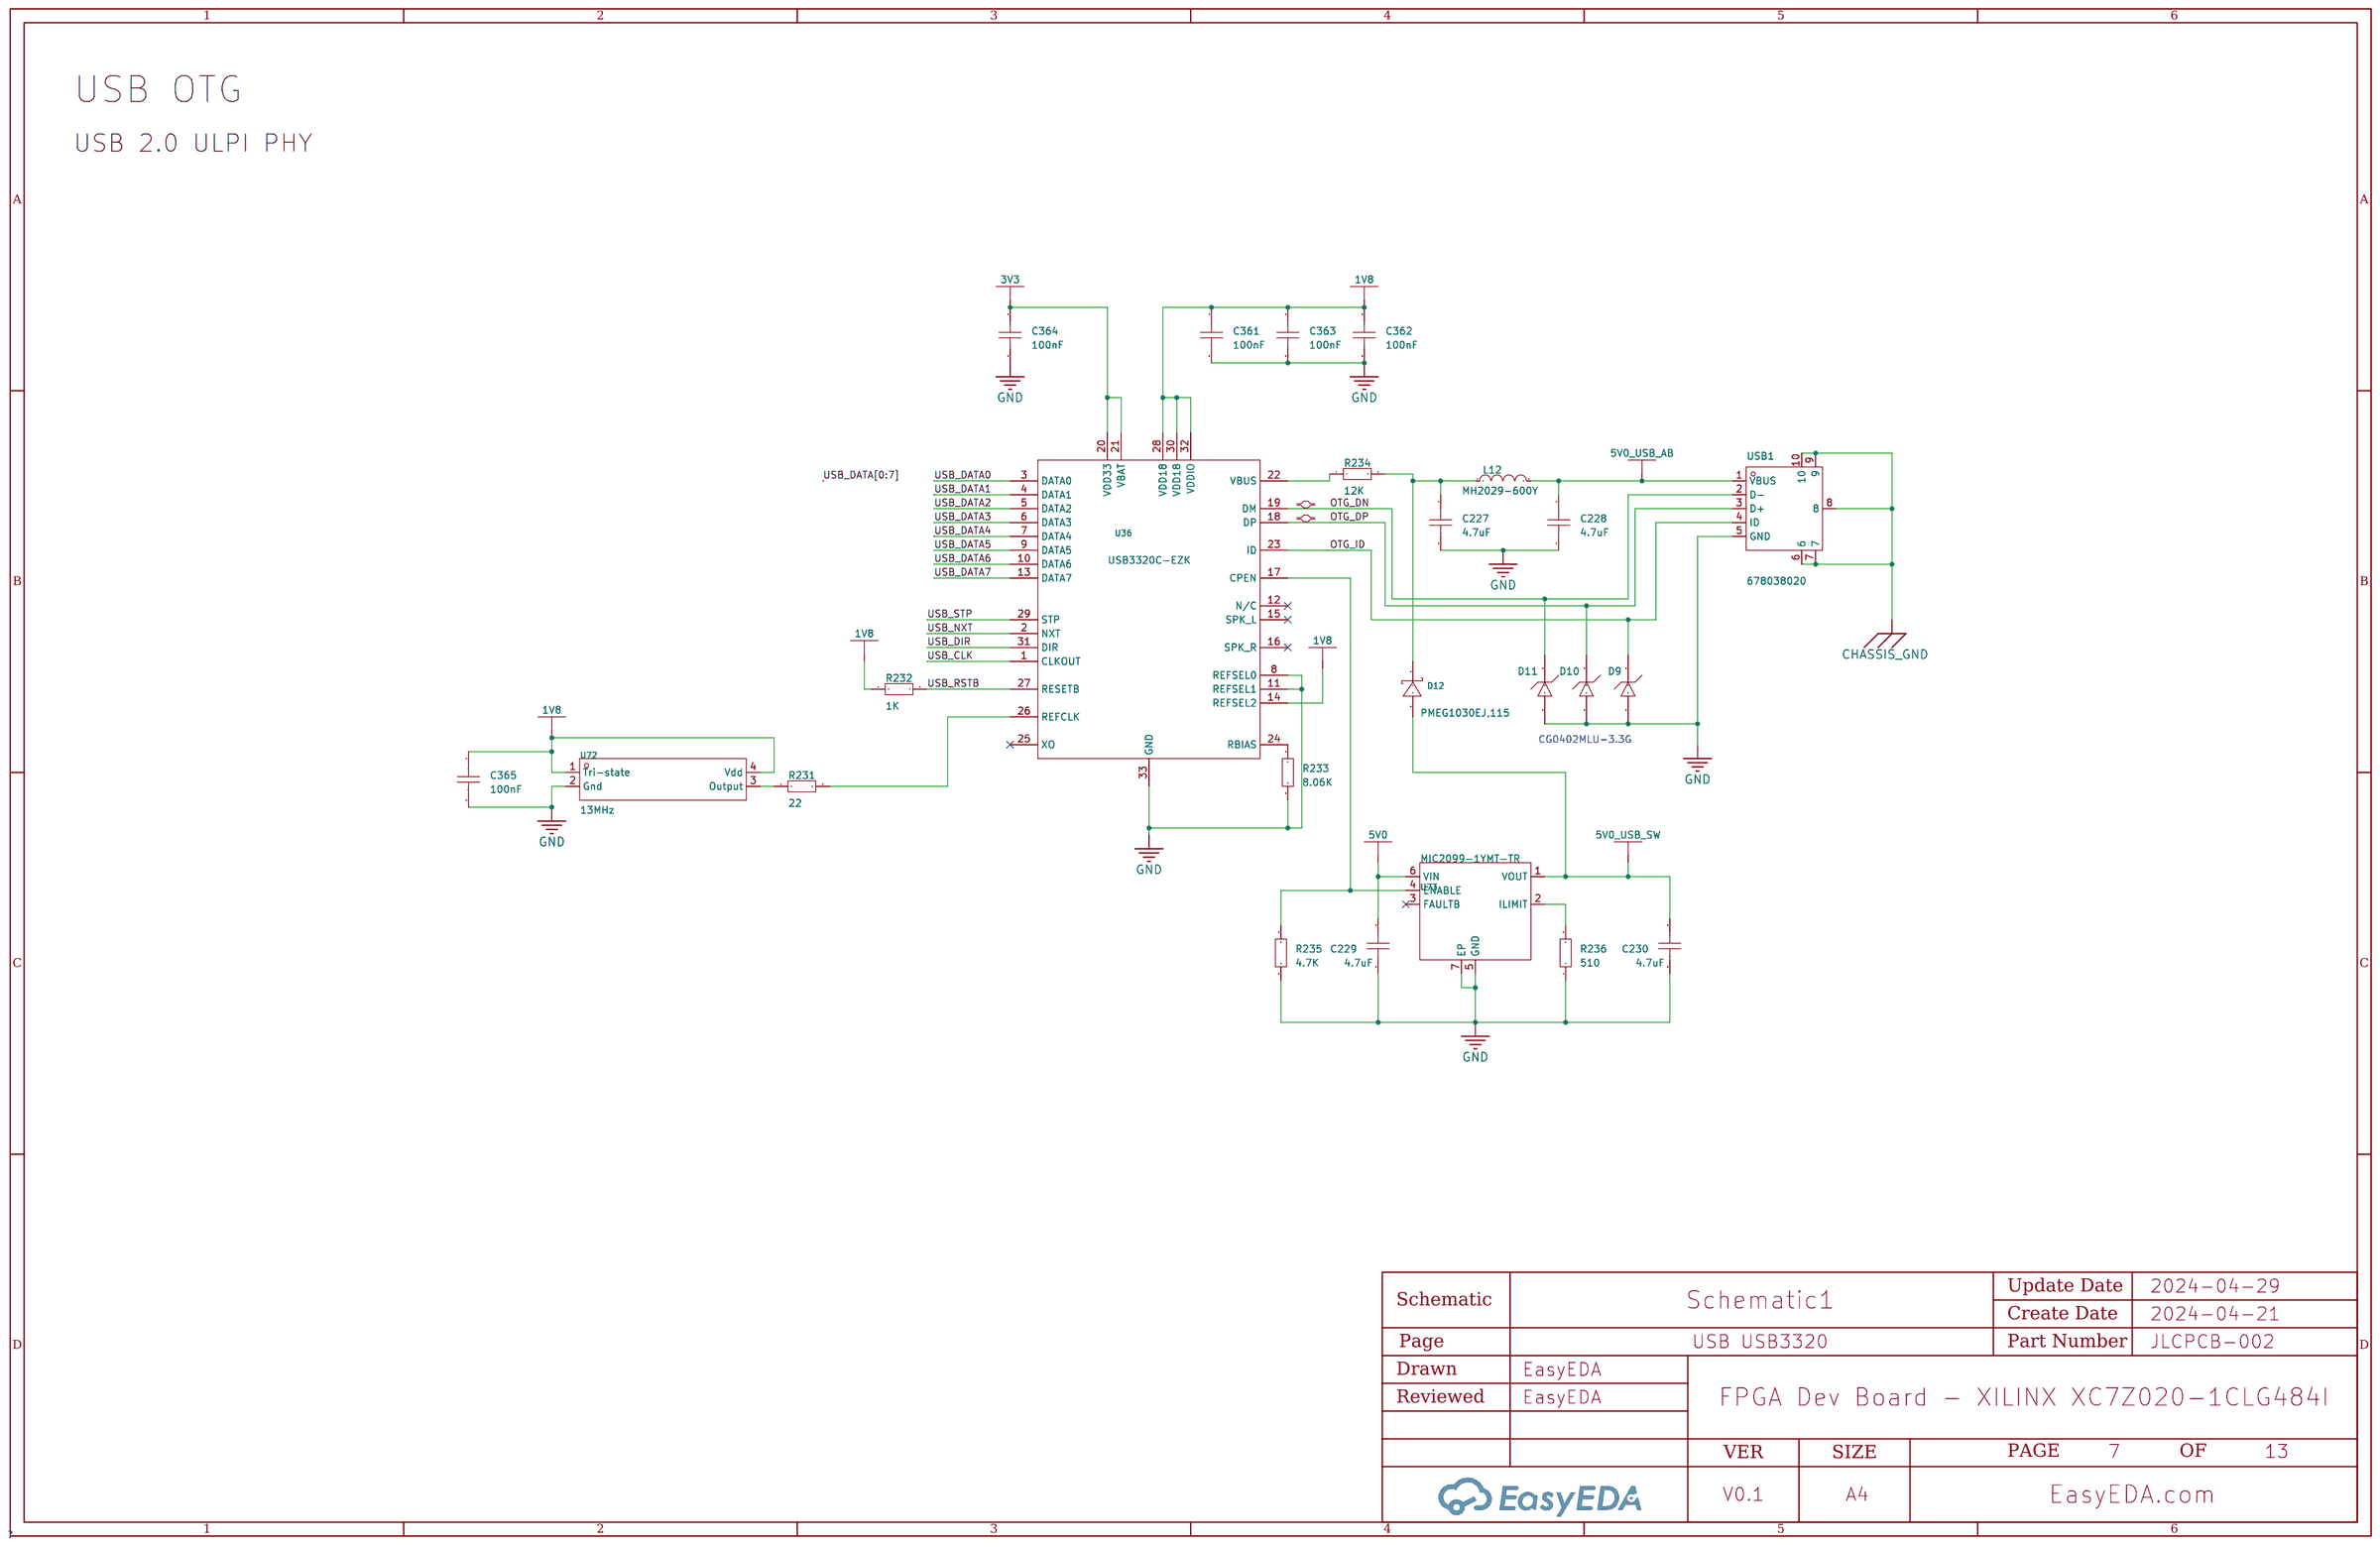
[diagram p12: USB USB3320]

(export (version "E")
  (design (tool "Eeschema 10.0.6"))
  (components
    (comp (ref "H4")
      (value "HDR")
      (footprint "easyedapro:HDR-TH_2P-P2.54-V-M")
      (fields (field (name "Manufacturer") "XFCN(兴飞)"))
      (libsource (lib "easyedapro") (part "PZ254V-11-02P"))
    )
    (comp (ref "U28")
      (value "~")
      (footprint "easyedapro:Standoff 3.0mm")
      (libsource (lib "easyedapro") (part "Standoff 3.0mm"))
    )
    (comp (ref "U29")
      (value "~")
      (footprint "easyedapro:Standoff 3.0mm")
      (libsource (lib "easyedapro") (part "Standoff 3.0mm"))
    )
    (comp (ref "U30")
      (value "~")
      (footprint "easyedapro:Standoff 3.0mm")
      (libsource (lib "easyedapro") (part "Standoff 3.0mm"))
    )
    (comp (ref "U31")
      (value "~")
      (footprint "easyedapro:Standoff 3.0mm")
      (libsource (lib "easyedapro") (part "Standoff 3.0mm"))
    )
    (comp (ref "U64")
      (value "~")
      (footprint "easyedapro:Standoff 2.0mm")
      (libsource (lib "easyedapro") (part "Standoff 2.0mm"))
    )
    (comp (ref "U65")
      (value "~")
      (footprint "easyedapro:Standoff 2.0mm")
      (libsource (lib "easyedapro") (part "Standoff 2.0mm"))
    )
    (comp (ref "U80")
      (value "47uF")
      (footprint "easyedapro:CAP-SMD_L7.3-W4.3-RD")
      (fields (field (name "Manufacturer Part") "T494D476M025AT") (field (name "Manufacturer") "KEMET(基美)"))
      (libsource (lib "easyedapro") (part "T494D476M025AT"))
    )
    (comp (ref "C1")
      (value "10uF")
      (footprint "easyedapro:C0603")
      (libsource (lib "easyedapro") (part "CAP"))
    )
    (comp (ref "C2")
      (value "10uF")
      (footprint "easyedapro:C0603")
      (libsource (lib "easyedapro") (part "CAP"))
    )
    (comp (ref "C3")
      (value "0.1uF")
      (footprint "easyedapro:C0603")
      (libsource (lib "easyedapro") (part "CAP"))
    )
    (comp (ref "C4")
      (value "10pF")
      (footprint "easyedapro:C0603")
      (libsource (lib "easyedapro") (part "CAP"))
    )
    (comp (ref "C5")
      (value "10pF")
      (footprint "easyedapro:C0603")
      (libsource (lib "easyedapro") (part "CAP"))
    )
    (comp (ref "C7")
      (value "0.1uF")
      (footprint "easyedapro:C0603")
      (libsource (lib "easyedapro") (part "CAP"))
    )
    (comp (ref "C8")
      (value "22uF")
      (footprint "easyedapro:C0603")
      (libsource (lib "easyedapro") (part "CAP"))
    )
    (comp (ref "C9")
      (value "22uF")
      (footprint "easyedapro:C0603")
      (libsource (lib "easyedapro") (part "CAP"))
    )
    (comp (ref "C10")
      (value "10uF")
      (footprint "easyedapro:C0603")
      (libsource (lib "easyedapro") (part "CAP"))
    )
    (comp (ref "C11")
      (value "10uF")
      (footprint "easyedapro:C0603")
      (libsource (lib "easyedapro") (part "CAP"))
    )
    (comp (ref "C12")
      (value "0.1uF")
      (footprint "easyedapro:C0603")
      (libsource (lib "easyedapro") (part "CAP"))
    )
    (comp (ref "C13")
      (value "10pF")
      (footprint "easyedapro:C0603")
      (libsource (lib "easyedapro") (part "CAP"))
    )
    (comp (ref "C14")
      (value "10pF")
      (footprint "easyedapro:C0603")
      (libsource (lib "easyedapro") (part "CAP"))
    )
    (comp (ref "C15")
      (value "0.1uF")
      (footprint "easyedapro:C0603")
      (libsource (lib "easyedapro") (part "CAP"))
    )
    (comp (ref "C16")
      (value "22uF")
      (footprint "easyedapro:C0603")
      (libsource (lib "easyedapro") (part "CAP"))
    )
    (comp (ref "C17")
      (value "22uF")
      (footprint "easyedapro:C0603")
      (libsource (lib "easyedapro") (part "CAP"))
    )
    (comp (ref "C18")
      (value "10uF")
      (footprint "easyedapro:C0603")
      (libsource (lib "easyedapro") (part "CAP"))
    )
    (comp (ref "C19")
      (value "10uF")
      (footprint "easyedapro:C0603")
      (libsource (lib "easyedapro") (part "CAP"))
    )
    (comp (ref "C20")
      (value "0.1uF")
      (footprint "easyedapro:C0603")
      (libsource (lib "easyedapro") (part "CAP"))
    )
    (comp (ref "C21")
      (value "47pF")
      (footprint "easyedapro:C0603")
      (libsource (lib "easyedapro") (part "CAP"))
    )
    (comp (ref "C22")
      (value "10pF")
      (footprint "easyedapro:C0603")
      (libsource (lib "easyedapro") (part "CAP"))
    )
    (comp (ref "C23")
      (value "0.1uF")
      (footprint "easyedapro:C0603")
      (libsource (lib "easyedapro") (part "CAP"))
    )
    (comp (ref "C24")
      (value "22uF")
      (footprint "easyedapro:C0603")
      (libsource (lib "easyedapro") (part "CAP"))
    )
    (comp (ref "C25")
      (value "22uF")
      (footprint "easyedapro:C0603")
      (libsource (lib "easyedapro") (part "CAP"))
    )
    (comp (ref "C26")
      (value "10uF")
      (footprint "easyedapro:C0603")
      (libsource (lib "easyedapro") (part "CAP"))
    )
    (comp (ref "C27")
      (value "10uF")
      (footprint "easyedapro:C0603")
      (libsource (lib "easyedapro") (part "CAP"))
    )
    (comp (ref "C28")
      (value "0.1uF")
      (footprint "easyedapro:C0603")
      (libsource (lib "easyedapro") (part "CAP"))
    )
    (comp (ref "C29")
      (value "150pF")
      (footprint "easyedapro:C0603")
      (libsource (lib "easyedapro") (part "CAP"))
    )
    (comp (ref "C30")
      (value "10pF")
      (footprint "easyedapro:C0603")
      (libsource (lib "easyedapro") (part "CAP"))
    )
    (comp (ref "C31")
      (value "0.1uF")
      (footprint "easyedapro:C0603")
      (libsource (lib "easyedapro") (part "CAP"))
    )
    (comp (ref "C32")
      (value "22uF")
      (footprint "easyedapro:C0603")
      (libsource (lib "easyedapro") (part "CAP"))
    )
    (comp (ref "C33")
      (value "22uF")
      (footprint "easyedapro:C0603")
      (libsource (lib "easyedapro") (part "CAP"))
    )
    (comp (ref "C217")
      (value "22uF")
      (footprint "easyedapro:C0603")
      (libsource (lib "easyedapro") (part "CAP"))
    )
    (comp (ref "C218")
      (value "4.7uF")
      (footprint "easyedapro:C0603")
      (libsource (lib "easyedapro") (part "CAP"))
    )
    (comp (ref "C219")
      (value "4.7uF")
      (footprint "easyedapro:C0603")
      (libsource (lib "easyedapro") (part "CAP"))
    )
    (comp (ref "C220")
      (value "22uF")
      (footprint "easyedapro:C0603")
      (libsource (lib "easyedapro") (part "CAP"))
    )
    (comp (ref "C221")
      (value "4.7uF")
      (footprint "easyedapro:C0603")
      (libsource (lib "easyedapro") (part "CAP"))
    )
    (comp (ref "C222")
      (value "4.7uF")
      (footprint "easyedapro:C0603")
      (libsource (lib "easyedapro") (part "CAP"))
    )
    (comp (ref "LED9")
      (value "~")
      (footprint "easyedapro:LED0603-R-RD")
      (libsource (lib "easyedapro") (part "LED_R"))
    )
    (comp (ref "LED10")
      (value "~")
      (footprint "easyedapro:LED0603-R-RD")
      (libsource (lib "easyedapro") (part "LED_R"))
    )
    (comp (ref "LED11")
      (value "~")
      (footprint "easyedapro:LED0603-R-RD")
      (libsource (lib "easyedapro") (part "LED_R"))
    )
    (comp (ref "LED12")
      (value "~")
      (footprint "easyedapro:LED0603-R-RD")
      (libsource (lib "easyedapro") (part "LED_R"))
    )
    (comp (ref "LED18")
      (value "~")
      (footprint "easyedapro:LED0603-R-RD")
      (libsource (lib "easyedapro") (part "LED_R"))
    )
    (comp (ref "LED19")
      (value "~")
      (footprint "easyedapro:LED0603-R-RD")
      (libsource (lib "easyedapro") (part "LED_R"))
    )
    (comp (ref "Q1")
      (value "T2N7002AK,LM")
      (footprint "easyedapro:SOT-23-3_L2.9-W1.3-P1.90-LS2.4-BR")
      (fields (field (name "Manufacturer") "TOSHIBA(东芝)"))
      (libsource (lib "easyedapro") (part "T2N7002AK,LM"))
    )
    (comp (ref "Q2")
      (value "T2N7002AK,LM")
      (footprint "easyedapro:SOT-23-3_L2.9-W1.3-P1.90-LS2.4-BR")
      (fields (field (name "Manufacturer") "TOSHIBA(东芝)"))
      (libsource (lib "easyedapro") (part "T2N7002AK,LM"))
    )
    (comp (ref "Q3")
      (value "T2N7002AK,LM")
      (footprint "easyedapro:SOT-23-3_L2.9-W1.3-P1.90-LS2.4-BR")
      (fields (field (name "Manufacturer") "TOSHIBA(东芝)"))
      (libsource (lib "easyedapro") (part "T2N7002AK,LM"))
    )
    (comp (ref "Q5")
      (value "T2N7002AK,LM")
      (footprint "easyedapro:SOT-23-3_L2.9-W1.3-P1.90-LS2.4-BR")
      (fields (field (name "Manufacturer") "TOSHIBA(东芝)"))
      (libsource (lib "easyedapro") (part "T2N7002AK,LM"))
    )
    (comp (ref "Q8")
      (value "BSH103,215")
      (footprint "easyedapro:TO-236AB_L2.9-W1.3-P0.95-LS2.3-BR")
      (fields (field (name "Manufacturer") "Nexperia(安世)"))
      (libsource (lib "easyedapro") (part "BSH103,215"))
    )
    (comp (ref "R1")
      (value "73.2K")
      (footprint "easyedapro:R0603")
      (libsource (lib "easyedapro") (part "Res"))
    )
    (comp (ref "R2")
      (value "22.1K")
      (footprint "easyedapro:R0603")
      (libsource (lib "easyedapro") (part "Res"))
    )
    (comp (ref "R3") (value "10K") (footprint "easyedapro:R0603") (libsource (lib "easyedapro") (part "Res")))
    (comp (ref "R4")
      (value "100K")
      (footprint "easyedapro:R0603")
      (libsource (lib "easyedapro") (part "Res"))
    )
    (comp (ref "R5") (value "10K") (footprint "easyedapro:R0603") (libsource (lib "easyedapro") (part "Res")))
    (comp (ref "R6")
      (value "30.1K")
      (footprint "easyedapro:R0603")
      (libsource (lib "easyedapro") (part "Res"))
    )
    (comp (ref "R7")
      (value "22.1K")
      (footprint "easyedapro:R0603")
      (libsource (lib "easyedapro") (part "Res"))
    )
    (comp (ref "R8")
      (value "100K")
      (footprint "easyedapro:R0603")
      (libsource (lib "easyedapro") (part "Res"))
    )
    (comp (ref "R9") (value "10K") (footprint "easyedapro:R0603") (libsource (lib "easyedapro") (part "Res")))
    (comp (ref "R10")
      (value "17.4K")
      (footprint "easyedapro:R0603")
      (libsource (lib "easyedapro") (part "Res"))
    )
    (comp (ref "R11")
      (value "22.1K")
      (footprint "easyedapro:R0603")
      (libsource (lib "easyedapro") (part "Res"))
    )
    (comp (ref "R12")
      (value "100K")
      (footprint "easyedapro:R0603")
      (libsource (lib "easyedapro") (part "Res"))
    )
    (comp (ref "R13")
      (value "10K")
      (footprint "easyedapro:R0603")
      (libsource (lib "easyedapro") (part "Res"))
    )
    (comp (ref "R14")
      (value "6.81K")
      (footprint "easyedapro:R0603")
      (libsource (lib "easyedapro") (part "Res"))
    )
    (comp (ref "R15")
      (value "22.1K")
      (footprint "easyedapro:R0603")
      (libsource (lib "easyedapro") (part "Res"))
    )
    (comp (ref "R16")
      (value "100K")
      (footprint "easyedapro:R0603")
      (libsource (lib "easyedapro") (part "Res"))
    )
    (comp (ref "R37")
      (value "500")
      (footprint "easyedapro:R0603")
      (libsource (lib "easyedapro") (part "Res"))
    )
    (comp (ref "R38")
      (value "500")
      (footprint "easyedapro:R0603")
      (libsource (lib "easyedapro") (part "Res"))
    )
    (comp (ref "R39") (value "1K") (footprint "easyedapro:R0603") (libsource (lib "easyedapro") (part "Res")))
    (comp (ref "R40")
      (value "500")
      (footprint "easyedapro:R0603")
      (libsource (lib "easyedapro") (part "Res"))
    )
    (comp (ref "R41")
      (value "500")
      (footprint "easyedapro:R0603")
      (libsource (lib "easyedapro") (part "Res"))
    )
    (comp (ref "R42")
      (value "500")
      (footprint "easyedapro:R0603")
      (libsource (lib "easyedapro") (part "Res"))
    )
    (comp (ref "R43")
      (value "500")
      (footprint "easyedapro:R0603")
      (libsource (lib "easyedapro") (part "Res"))
    )
    (comp (ref "R124")
      (value "12K")
      (footprint "easyedapro:R0603")
      (libsource (lib "easyedapro") (part "Res"))
    )
    (comp (ref "R125")
      (value "100K")
      (footprint "easyedapro:R0603")
      (libsource (lib "easyedapro") (part "Res"))
    )
    (comp (ref "R126")
      (value "500")
      (footprint "easyedapro:R0603")
      (libsource (lib "easyedapro") (part "Res"))
    )
    (comp (ref "R127")
      (value "500")
      (footprint "easyedapro:R0603")
      (libsource (lib "easyedapro") (part "Res"))
    )
    (comp (ref "R128")
      (value "500")
      (footprint "easyedapro:R0603")
      (libsource (lib "easyedapro") (part "Res"))
    )
    (comp (ref "R129")
      (value "500")
      (footprint "easyedapro:R0603")
      (libsource (lib "easyedapro") (part "Res"))
    )
    (comp (ref "R130")
      (value "1K")
      (footprint "easyedapro:R0603")
      (libsource (lib "easyedapro") (part "Res"))
    )
    (comp (ref "U4")
      (value "TPS56628DDAR")
      (footprint "easyedapro:SOIC-8_L4.9-W3.9-P1.27-LS6.0-BL-EP")
      (fields (field (name "Manufacturer") "TI(德州仪器)"))
      (libsource (lib "easyedapro") (part "TPS56628DDAR"))
    )
    (comp (ref "U6")
      (value "TPS56628DDAR")
      (footprint "easyedapro:SOIC-8_L4.9-W3.9-P1.27-LS6.0-BL-EP")
      (fields (field (name "Manufacturer") "TI(德州仪器)"))
      (libsource (lib "easyedapro") (part "TPS56628DDAR"))
    )
    (comp (ref "U8")
      (value "TPS56628DDAR")
      (footprint "easyedapro:SOIC-8_L4.9-W3.9-P1.27-LS6.0-BL-EP")
      (fields (field (name "Manufacturer") "TI(德州仪器)"))
      (libsource (lib "easyedapro") (part "TPS56628DDAR"))
    )
    (comp (ref "U10")
      (value "TPS56628DDAR")
      (footprint "easyedapro:SOIC-8_L4.9-W3.9-P1.27-LS6.0-BL-EP")
      (fields (field (name "Manufacturer") "TI(德州仪器)"))
      (libsource (lib "easyedapro") (part "TPS56628DDAR"))
    )
    (comp (ref "U37")
      (value "2.2uH AIP0530GX-2R2MPBDG")
      (footprint "easyedapro:Inductor 5.7mm X 5.4mm")
      (libsource (lib "easyedapro") (part "INPAQ AIP0530GX Series"))
    )
    (comp (ref "U38")
      (value "2.2uH AIP0530GX-2R2MPBDG")
      (footprint "easyedapro:Inductor 5.7mm X 5.4mm")
      (libsource (lib "easyedapro") (part "INPAQ AIP0530GX Series"))
    )
    (comp (ref "U39")
      (value "2.2uH AIP0530GX-2R2MPBDG")
      (footprint "easyedapro:Inductor 5.7mm X 5.4mm")
      (libsource (lib "easyedapro") (part "INPAQ AIP0530GX Series"))
    )
    (comp (ref "U40")
      (value "3.3uH AIP0530GX-3R3MPBDG")
      (footprint "easyedapro:Inductor 5.7mm X 5.4mm")
      (libsource (lib "easyedapro") (part "INPAQ AIP0530GX Series"))
    )
    (comp (ref "U68")
      (value "BD3539FVM-TR")
      (footprint "easyedapro:MSOP-8_L2.9-W2.8-P0.65-LS4.0-BL")
      (fields (field (name "Manufacturer") "ROHM(罗姆)"))
      (libsource (lib "easyedapro") (part "BD3539FVM-TR"))
    )
    (comp (ref "C42")
      (value "4.7uF")
      (footprint "easyedapro:C0603")
      (libsource (lib "easyedapro") (part "CAP"))
    )
    (comp (ref "C45")
      (value "4.7uF")
      (footprint "easyedapro:C0603")
      (libsource (lib "easyedapro") (part "CAP"))
    )
    (comp (ref "C49")
      (value "4.7uF")
      (footprint "easyedapro:C0603")
      (libsource (lib "easyedapro") (part "CAP"))
    )
    (comp (ref "C52")
      (value "4.7uF")
      (footprint "easyedapro:C0603")
      (libsource (lib "easyedapro") (part "CAP"))
    )
    (comp (ref "C55")
      (value "4.7uF")
      (footprint "easyedapro:C0603")
      (libsource (lib "easyedapro") (part "CAP"))
    )
    (comp (ref "C58")
      (value "4.7uF")
      (footprint "easyedapro:C0603")
      (libsource (lib "easyedapro") (part "CAP"))
    )
    (comp (ref "C62")
      (value "4.7uF")
      (footprint "easyedapro:C0603")
      (libsource (lib "easyedapro") (part "CAP"))
    )
    (comp (ref "C65")
      (value "4.7uF")
      (footprint "easyedapro:C0603")
      (libsource (lib "easyedapro") (part "CAP"))
    )
    (comp (ref "C73")
      (value "4.7uF")
      (footprint "easyedapro:C0603")
      (libsource (lib "easyedapro") (part "CAP"))
    )
    (comp (ref "C78")
      (value "4.7uF")
      (footprint "easyedapro:C0603")
      (libsource (lib "easyedapro") (part "CAP"))
    )
    (comp (ref "C83")
      (value "4.7uF")
      (footprint "easyedapro:C0603")
      (libsource (lib "easyedapro") (part "CAP"))
    )
    (comp (ref "C85")
      (value "4.7uF")
      (footprint "easyedapro:C0603")
      (libsource (lib "easyedapro") (part "CAP"))
    )
    (comp (ref "C244")
      (value "4.7uF")
      (footprint "easyedapro:C0603")
      (libsource (lib "easyedapro") (part "CAP"))
    )
    (comp (ref "C248")
      (value "330uF")
      (footprint "easyedapro:CAP-SMD_L7.3-W4.3-L-FD")
      (fields (field (name "Manufacturer Part") "10TPB330M") (field (name "Manufacturer") "PANASONIC(松下)"))
      (libsource (lib "easyedapro") (part "10TPB330M"))
    )
    (comp (ref "C253")
      (value "100uF")
      (footprint "easyedapro:CAP-SMD_L3.5-W2.8-FD")
      (fields (field (name "Manufacturer") "湘怡中元/湘江"))
      (libsource (lib "easyedapro") (part "CA45-B016K156T"))
    )
    (comp (ref "C257")
      (value "100uF")
      (footprint "easyedapro:CAP-SMD_L3.5-W2.8-FD")
      (fields (field (name "Manufacturer") "湘怡中元/湘江"))
      (libsource (lib "easyedapro") (part "CA45-B016K156T"))
    )
    (comp (ref "C258")
      (value "100uF")
      (footprint "easyedapro:CAP-SMD_L3.5-W2.8-FD")
      (fields (field (name "Manufacturer") "湘怡中元/湘江"))
      (libsource (lib "easyedapro") (part "CA45-B016K156T"))
    )
    (comp (ref "C259")
      (value "470nF")
      (footprint "easyedapro:C0603")
      (libsource (lib "easyedapro") (part "CAP"))
    )
    (comp (ref "C261")
      (value "47uF")
      (footprint "easyedapro:CAP-SMD_L3.5-W2.8-FD")
      (fields (field (name "Manufacturer") "湘怡中元/湘江"))
      (libsource (lib "easyedapro") (part "CA45-B016K156T"))
    )
    (comp (ref "C262")
      (value "100uF")
      (footprint "easyedapro:CAP-SMD_L3.5-W2.8-FD")
      (fields (field (name "Manufacturer") "湘怡中元/湘江"))
      (libsource (lib "easyedapro") (part "CA45-B016K156T"))
    )
    (comp (ref "C263")
      (value "100uF")
      (footprint "easyedapro:CAP-SMD_L3.5-W2.8-FD")
      (fields (field (name "Manufacturer") "湘怡中元/湘江"))
      (libsource (lib "easyedapro") (part "CA45-B016K156T"))
    )
    (comp (ref "C264")
      (value "470nF")
      (footprint "easyedapro:C0603")
      (libsource (lib "easyedapro") (part "CAP"))
    )
    (comp (ref "C265")
      (value "470nF")
      (footprint "easyedapro:C0603")
      (libsource (lib "easyedapro") (part "CAP"))
    )
    (comp (ref "C268")
      (value "470nF")
      (footprint "easyedapro:C0603")
      (libsource (lib "easyedapro") (part "CAP"))
    )
    (comp (ref "C274")
      (value "47uF")
      (footprint "easyedapro:CAP-SMD_L3.5-W2.8-FD")
      (fields (field (name "Manufacturer") "湘怡中元/湘江"))
      (libsource (lib "easyedapro") (part "CA45-B016K156T"))
    )
    (comp (ref "C277")
      (value "4.7uF")
      (footprint "easyedapro:C0603")
      (libsource (lib "easyedapro") (part "CAP"))
    )
    (comp (ref "C278")
      (value "4.7uF")
      (footprint "easyedapro:C0603")
      (libsource (lib "easyedapro") (part "CAP"))
    )
    (comp (ref "C279")
      (value "4.7uF")
      (footprint "easyedapro:C0603")
      (libsource (lib "easyedapro") (part "CAP"))
    )
    (comp (ref "C280")
      (value "4.7uF")
      (footprint "easyedapro:C0603")
      (libsource (lib "easyedapro") (part "CAP"))
    )
    (comp (ref "C284")
      (value "470nF")
      (footprint "easyedapro:C0603")
      (libsource (lib "easyedapro") (part "CAP"))
    )
    (comp (ref "C285")
      (value "470nF")
      (footprint "easyedapro:C0603")
      (libsource (lib "easyedapro") (part "CAP"))
    )
    (comp (ref "C286")
      (value "470nF")
      (footprint "easyedapro:C0603")
      (libsource (lib "easyedapro") (part "CAP"))
    )
    (comp (ref "C287")
      (value "100uF")
      (footprint "easyedapro:CAP-SMD_L3.5-W2.8-FD")
      (fields (field (name "Manufacturer") "湘怡中元/湘江"))
      (libsource (lib "easyedapro") (part "CA45-B016K156T"))
    )
    (comp (ref "C288")
      (value "100uF")
      (footprint "easyedapro:CAP-SMD_L3.5-W2.8-FD")
      (fields (field (name "Manufacturer") "湘怡中元/湘江"))
      (libsource (lib "easyedapro") (part "CA45-B016K156T"))
    )
    (comp (ref "C289")
      (value "100uF")
      (footprint "easyedapro:CAP-SMD_L3.5-W2.8-FD")
      (fields (field (name "Manufacturer") "湘怡中元/湘江"))
      (libsource (lib "easyedapro") (part "CA45-B016K156T"))
    )
    (comp (ref "C290")
      (value "100uF")
      (footprint "easyedapro:CAP-SMD_L3.5-W2.8-FD")
      (fields (field (name "Manufacturer") "湘怡中元/湘江"))
      (libsource (lib "easyedapro") (part "CA45-B016K156T"))
    )
    (comp (ref "C291")
      (value "100uF")
      (footprint "easyedapro:CAP-SMD_L3.5-W2.8-FD")
      (fields (field (name "Manufacturer") "湘怡中元/湘江"))
      (libsource (lib "easyedapro") (part "CA45-B016K156T"))
    )
    (comp (ref "C293")
      (value "470nF")
      (footprint "easyedapro:C0603")
      (libsource (lib "easyedapro") (part "CAP"))
    )
    (comp (ref "C294")
      (value "470nF")
      (footprint "easyedapro:C0603")
      (libsource (lib "easyedapro") (part "CAP"))
    )
    (comp (ref "C295")
      (value "470nF")
      (footprint "easyedapro:C0603")
      (libsource (lib "easyedapro") (part "CAP"))
    )
    (comp (ref "C300")
      (value "4.7uF")
      (footprint "easyedapro:C0603")
      (libsource (lib "easyedapro") (part "CAP"))
    )
    (comp (ref "C301")
      (value "470nF")
      (footprint "easyedapro:C0603")
      (libsource (lib "easyedapro") (part "CAP"))
    )
    (comp (ref "C302")
      (value "470nF")
      (footprint "easyedapro:C0603")
      (libsource (lib "easyedapro") (part "CAP"))
    )
    (comp (ref "C303")
      (value "100nF")
      (footprint "easyedapro:C0603")
      (libsource (lib "easyedapro") (part "CAP"))
    )
    (comp (ref "C348")
      (value "1nF 250V")
      (footprint "easyedapro:C1206")
      (fields
        (field (name "Manufacturer Part") "CC1206KRX7RYBB102")
        (field (name "Manufacturer") "YAGEO(国巨)")
      )
      (libsource (lib "easyedapro") (part "CC1206KRX7RYBB102"))
    )
    (comp (ref "C380")
      (value "470nF")
      (footprint "easyedapro:C0603")
      (libsource (lib "easyedapro") (part "CAP"))
    )
    (comp (ref "C381")
      (value "470nF")
      (footprint "easyedapro:C0603")
      (libsource (lib "easyedapro") (part "CAP"))
    )
    (comp (ref "C382")
      (value "470nF")
      (footprint "easyedapro:C0603")
      (libsource (lib "easyedapro") (part "CAP"))
    )
    (comp (ref "C383")
      (value "470nF")
      (footprint "easyedapro:C0603")
      (libsource (lib "easyedapro") (part "CAP"))
    )
    (comp (ref "C384")
      (value "470nF")
      (footprint "easyedapro:C0603")
      (libsource (lib "easyedapro") (part "CAP"))
    )
    (comp (ref "C385")
      (value "470nF")
      (footprint "easyedapro:C0603")
      (libsource (lib "easyedapro") (part "CAP"))
    )
    (comp (ref "C386")
      (value "470nF")
      (footprint "easyedapro:C0603")
      (libsource (lib "easyedapro") (part "CAP"))
    )
    (comp (ref "C387")
      (value "470nF")
      (footprint "easyedapro:C0603")
      (libsource (lib "easyedapro") (part "CAP"))
    )
    (comp (ref "C388")
      (value "470nF")
      (footprint "easyedapro:C0603")
      (libsource (lib "easyedapro") (part "CAP"))
    )
    (comp (ref "C389")
      (value "470nF")
      (footprint "easyedapro:C0603")
      (libsource (lib "easyedapro") (part "CAP"))
    )
    (comp (ref "C390")
      (value "470nF")
      (footprint "easyedapro:C0603")
      (libsource (lib "easyedapro") (part "CAP"))
    )
    (comp (ref "C391")
      (value "470nF")
      (footprint "easyedapro:C0603")
      (libsource (lib "easyedapro") (part "CAP"))
    )
    (comp (ref "C392")
      (value "470nF")
      (footprint "easyedapro:C0603")
      (libsource (lib "easyedapro") (part "CAP"))
    )
    (comp (ref "C393")
      (value "470nF")
      (footprint "easyedapro:C0603")
      (libsource (lib "easyedapro") (part "CAP"))
    )
    (comp (ref "C394")
      (value "470nF")
      (footprint "easyedapro:C0603")
      (libsource (lib "easyedapro") (part "CAP"))
    )
    (comp (ref "C395")
      (value "470nF")
      (footprint "easyedapro:C0603")
      (libsource (lib "easyedapro") (part "CAP"))
    )
    (comp (ref "C396")
      (value "470nF")
      (footprint "easyedapro:C0603")
      (libsource (lib "easyedapro") (part "CAP"))
    )
    (comp (ref "C397")
      (value "470nF")
      (footprint "easyedapro:C0603")
      (libsource (lib "easyedapro") (part "CAP"))
    )
    (comp (ref "C398")
      (value "470nF")
      (footprint "easyedapro:C0603")
      (libsource (lib "easyedapro") (part "CAP"))
    )
    (comp (ref "C399")
      (value "470nF")
      (footprint "easyedapro:C0603")
      (libsource (lib "easyedapro") (part "CAP"))
    )
    (comp (ref "C400")
      (value "470nF")
      (footprint "easyedapro:C0603")
      (libsource (lib "easyedapro") (part "CAP"))
    )
    (comp (ref "C401")
      (value "470nF")
      (footprint "easyedapro:C0603")
      (libsource (lib "easyedapro") (part "CAP"))
    )
    (comp (ref "C402")
      (value "470nF")
      (footprint "easyedapro:C0603")
      (libsource (lib "easyedapro") (part "CAP"))
    )
    (comp (ref "C403")
      (value "470nF")
      (footprint "easyedapro:C0603")
      (libsource (lib "easyedapro") (part "CAP"))
    )
    (comp (ref "C404")
      (value "470nF")
      (footprint "easyedapro:C0603")
      (libsource (lib "easyedapro") (part "CAP"))
    )
    (comp (ref "D13")
      (value "PMEG1030EJ,115")
      (footprint "easyedapro:SOD-323_L1.8-W1.3-LS2.5-RD")
      (fields (field (name "Manufacturer") "Nexperia(安世)"))
      (libsource (lib "easyedapro") (part "PMEG1030EJ,115"))
    )
    (comp (ref "DC1")
      (value "~")
      (footprint "easyedapro:DC-IN-TH_DC-5520-1")
      (libsource (lib "easyedapro") (part "DC电源接口"))
    )
    (comp (ref "F2")
      (value "~")
      (footprint "easyedapro:F1210")
      (libsource (lib "easyedapro") (part "PTSLR12106V350"))
    )
    (comp (ref "H2")
      (value "HDR")
      (footprint "easyedapro:HDR-TH_3P-P2.54-V-M-1")
      (fields (field (name "Manufacturer") "BOOMELE(博穆精密)"))
      (libsource (lib "easyedapro") (part "Header-Male-2.54_1x3"))
    )
    (comp (ref "H3")
      (value "HDR")
      (footprint "easyedapro:HDR-TH_3P-P2.54-V-M-1")
      (fields (field (name "Manufacturer") "BOOMELE(博穆精密)"))
      (libsource (lib "easyedapro") (part "Header-Male-2.54_1x3"))
    )
    (comp (ref "L2")
      (value "MH2029-600Y")
      (footprint "easyedapro:L0805")
      (fields (field (name "Manufacturer") "BOURNS"))
      (libsource (lib "easyedapro") (part "MH2029-600Y"))
    )
    (comp (ref "L3")
      (value "MH2029-600Y")
      (footprint "easyedapro:L0805")
      (fields (field (name "Manufacturer") "BOURNS"))
      (libsource (lib "easyedapro") (part "MH2029-600Y"))
    )
    (comp (ref "L4")
      (value "MH2029-600Y")
      (footprint "easyedapro:L0805")
      (fields (field (name "Manufacturer") "BOURNS"))
      (libsource (lib "easyedapro") (part "MH2029-600Y"))
    )
    (comp (ref "R131")
      (value "DNP_1M")
      (footprint "easyedapro:R0603")
      (libsource (lib "easyedapro") (part "Res"))
    )
    (comp (ref "U2")
      (value "XC7Z020-1CLG484I")
      (footprint "easyedapro:FBGA-484_L19.0-W19.0-R22-C22-P0.80-TL")
      (fields (field (name "Manufacturer") "XILINX(赛灵思)"))
      (libsource (lib "easyedapro") (part "XC7Z020-1CLG484I"))
    )
    (comp (ref "U71")
      (value "~")
      (footprint "easyedapro:Standoff 3.0mm")
      (libsource (lib "easyedapro") (part "Standoff 3.0mm"))
    )
    (comp (ref "U79")
      (value "47uF")
      (footprint "easyedapro:CAP-SMD_L7.3-W4.3-RD")
      (fields (field (name "Manufacturer Part") "T494D476M025AT") (field (name "Manufacturer") "KEMET(基美)"))
      (libsource (lib "easyedapro") (part "T494D476M025AT"))
    )
    (comp (ref "C6")
      (value "47nF")
      (footprint "easyedapro:C0603")
      (libsource (lib "easyedapro") (part "CAP"))
    )
    (comp (ref "C35")
      (value "47nF")
      (footprint "easyedapro:C0603")
      (libsource (lib "easyedapro") (part "CAP"))
    )
    (comp (ref "C36")
      (value "47nF")
      (footprint "easyedapro:C0603")
      (libsource (lib "easyedapro") (part "CAP"))
    )
    (comp (ref "C37")
      (value "47nF")
      (footprint "easyedapro:C0603")
      (libsource (lib "easyedapro") (part "CAP"))
    )
    (comp (ref "C38")
      (value "47nF")
      (footprint "easyedapro:C0603")
      (libsource (lib "easyedapro") (part "CAP"))
    )
    (comp (ref "C39")
      (value "47nF")
      (footprint "easyedapro:C0603")
      (libsource (lib "easyedapro") (part "CAP"))
    )
    (comp (ref "C40")
      (value "47nF")
      (footprint "easyedapro:C0603")
      (libsource (lib "easyedapro") (part "CAP"))
    )
    (comp (ref "C41")
      (value "47nF")
      (footprint "easyedapro:C0603")
      (libsource (lib "easyedapro") (part "CAP"))
    )
    (comp (ref "C43")
      (value "47nF")
      (footprint "easyedapro:C0603")
      (libsource (lib "easyedapro") (part "CAP"))
    )
    (comp (ref "C44")
      (value "47nF")
      (footprint "easyedapro:C0603")
      (libsource (lib "easyedapro") (part "CAP"))
    )
    (comp (ref "C46")
      (value "4.7uF")
      (footprint "easyedapro:C0603")
      (libsource (lib "easyedapro") (part "CAP"))
    )
    (comp (ref "C47")
      (value "470nF")
      (footprint "easyedapro:C0603")
      (libsource (lib "easyedapro") (part "CAP"))
    )
    (comp (ref "C48")
      (value "47nF")
      (footprint "easyedapro:C0603")
      (libsource (lib "easyedapro") (part "CAP"))
    )
    (comp (ref "C50")
      (value "47nF")
      (footprint "easyedapro:C0603")
      (libsource (lib "easyedapro") (part "CAP"))
    )
    (comp (ref "C51")
      (value "47nF")
      (footprint "easyedapro:C0603")
      (libsource (lib "easyedapro") (part "CAP"))
    )
    (comp (ref "C53")
      (value "47nF")
      (footprint "easyedapro:C0603")
      (libsource (lib "easyedapro") (part "CAP"))
    )
    (comp (ref "C54")
      (value "47nF")
      (footprint "easyedapro:C0603")
      (libsource (lib "easyedapro") (part "CAP"))
    )
    (comp (ref "C56")
      (value "47nF")
      (footprint "easyedapro:C0603")
      (libsource (lib "easyedapro") (part "CAP"))
    )
    (comp (ref "C57")
      (value "47nF")
      (footprint "easyedapro:C0603")
      (libsource (lib "easyedapro") (part "CAP"))
    )
    (comp (ref "C59")
      (value "47nF")
      (footprint "easyedapro:C0603")
      (libsource (lib "easyedapro") (part "CAP"))
    )
    (comp (ref "C60")
      (value "4.7uF")
      (footprint "easyedapro:C0603")
      (libsource (lib "easyedapro") (part "CAP"))
    )
    (comp (ref "C61")
      (value "470nF")
      (footprint "easyedapro:C0603")
      (libsource (lib "easyedapro") (part "CAP"))
    )
    (comp (ref "C63")
      (value "47nF")
      (footprint "easyedapro:C0603")
      (libsource (lib "easyedapro") (part "CAP"))
    )
    (comp (ref "C64")
      (value "47nF")
      (footprint "easyedapro:C0603")
      (libsource (lib "easyedapro") (part "CAP"))
    )
    (comp (ref "C66")
      (value "47nF")
      (footprint "easyedapro:C0603")
      (libsource (lib "easyedapro") (part "CAP"))
    )
    (comp (ref "C67")
      (value "47nF")
      (footprint "easyedapro:C0603")
      (libsource (lib "easyedapro") (part "CAP"))
    )
    (comp (ref "C68")
      (value "47nF")
      (footprint "easyedapro:C0603")
      (libsource (lib "easyedapro") (part "CAP"))
    )
    (comp (ref "C69")
      (value "47nF")
      (footprint "easyedapro:C0603")
      (libsource (lib "easyedapro") (part "CAP"))
    )
    (comp (ref "C70")
      (value "47nF")
      (footprint "easyedapro:C0603")
      (libsource (lib "easyedapro") (part "CAP"))
    )
    (comp (ref "C71")
      (value "47nF")
      (footprint "easyedapro:C0603")
      (libsource (lib "easyedapro") (part "CAP"))
    )
    (comp (ref "C72")
      (value "470nF")
      (footprint "easyedapro:C0603")
      (libsource (lib "easyedapro") (part "CAP"))
    )
    (comp (ref "C74")
      (value "470nF")
      (footprint "easyedapro:C0603")
      (libsource (lib "easyedapro") (part "CAP"))
    )
    (comp (ref "C75")
      (value "470nF")
      (footprint "easyedapro:C0603")
      (libsource (lib "easyedapro") (part "CAP"))
    )
    (comp (ref "C76")
      (value "470nF")
      (footprint "easyedapro:C0603")
      (libsource (lib "easyedapro") (part "CAP"))
    )
    (comp (ref "C77")
      (value "4.7uF")
      (footprint "easyedapro:C0603")
      (libsource (lib "easyedapro") (part "CAP"))
    )
    (comp (ref "C79")
      (value "470nF")
      (footprint "easyedapro:C0603")
      (libsource (lib "easyedapro") (part "CAP"))
    )
    (comp (ref "C80")
      (value "47nF")
      (footprint "easyedapro:C0603")
      (libsource (lib "easyedapro") (part "CAP"))
    )
    (comp (ref "C81")
      (value "47nF")
      (footprint "easyedapro:C0603")
      (libsource (lib "easyedapro") (part "CAP"))
    )
    (comp (ref "C82")
      (value "47nF")
      (footprint "easyedapro:C0603")
      (libsource (lib "easyedapro") (part "CAP"))
    )
    (comp (ref "C84")
      (value "47nF")
      (footprint "easyedapro:C0603")
      (libsource (lib "easyedapro") (part "CAP"))
    )
    (comp (ref "C86")
      (value "47nF")
      (footprint "easyedapro:C0603")
      (libsource (lib "easyedapro") (part "CAP"))
    )
    (comp (ref "C87")
      (value "47nF")
      (footprint "easyedapro:C0603")
      (libsource (lib "easyedapro") (part "CAP"))
    )
    (comp (ref "C88")
      (value "47nF")
      (footprint "easyedapro:C0603")
      (libsource (lib "easyedapro") (part "CAP"))
    )
    (comp (ref "C89")
      (value "47nF")
      (footprint "easyedapro:C0603")
      (libsource (lib "easyedapro") (part "CAP"))
    )
    (comp (ref "C90")
      (value "4.7uF")
      (footprint "easyedapro:C0603")
      (libsource (lib "easyedapro") (part "CAP"))
    )
    (comp (ref "C91")
      (value "4.7uF")
      (footprint "easyedapro:C0603")
      (libsource (lib "easyedapro") (part "CAP"))
    )
    (comp (ref "C92")
      (value "4.7uF")
      (footprint "easyedapro:C0603")
      (libsource (lib "easyedapro") (part "CAP"))
    )
    (comp (ref "C93")
      (value "4.7uF")
      (footprint "easyedapro:C0603")
      (libsource (lib "easyedapro") (part "CAP"))
    )
    (comp (ref "C94")
      (value "4.7uF")
      (footprint "easyedapro:C0603")
      (libsource (lib "easyedapro") (part "CAP"))
    )
    (comp (ref "C95")
      (value "470nF")
      (footprint "easyedapro:C0603")
      (libsource (lib "easyedapro") (part "CAP"))
    )
    (comp (ref "C96")
      (value "47nF")
      (footprint "easyedapro:C0603")
      (libsource (lib "easyedapro") (part "CAP"))
    )
    (comp (ref "C97")
      (value "47nF")
      (footprint "easyedapro:C0603")
      (libsource (lib "easyedapro") (part "CAP"))
    )
    (comp (ref "C98")
      (value "47nF")
      (footprint "easyedapro:C0603")
      (libsource (lib "easyedapro") (part "CAP"))
    )
    (comp (ref "C99")
      (value "47nF")
      (footprint "easyedapro:C0603")
      (libsource (lib "easyedapro") (part "CAP"))
    )
    (comp (ref "C100")
      (value "47nF")
      (footprint "easyedapro:C0603")
      (libsource (lib "easyedapro") (part "CAP"))
    )
    (comp (ref "C101")
      (value "47nF")
      (footprint "easyedapro:C0603")
      (libsource (lib "easyedapro") (part "CAP"))
    )
    (comp (ref "C102")
      (value "47nF")
      (footprint "easyedapro:C0603")
      (libsource (lib "easyedapro") (part "CAP"))
    )
    (comp (ref "C103")
      (value "47nF")
      (footprint "easyedapro:C0603")
      (libsource (lib "easyedapro") (part "CAP"))
    )
    (comp (ref "R18")
      (value "49.9")
      (footprint "easyedapro:R0603")
      (libsource (lib "easyedapro") (part "Res"))
    )
    (comp (ref "R19")
      (value "49.9")
      (footprint "easyedapro:R0603")
      (libsource (lib "easyedapro") (part "Res"))
    )
    (comp (ref "R20")
      (value "49.9")
      (footprint "easyedapro:R0603")
      (libsource (lib "easyedapro") (part "Res"))
    )
    (comp (ref "R21")
      (value "49.9")
      (footprint "easyedapro:R0603")
      (libsource (lib "easyedapro") (part "Res"))
    )
    (comp (ref "R22")
      (value "49.9")
      (footprint "easyedapro:R0603")
      (libsource (lib "easyedapro") (part "Res"))
    )
    (comp (ref "R23")
      (value "49.9")
      (footprint "easyedapro:R0603")
      (libsource (lib "easyedapro") (part "Res"))
    )
    (comp (ref "R24")
      (value "49.9")
      (footprint "easyedapro:R0603")
      (libsource (lib "easyedapro") (part "Res"))
    )
    (comp (ref "R25")
      (value "49.9")
      (footprint "easyedapro:R0603")
      (libsource (lib "easyedapro") (part "Res"))
    )
    (comp (ref "R26")
      (value "49.9")
      (footprint "easyedapro:R0603")
      (libsource (lib "easyedapro") (part "Res"))
    )
    (comp (ref "R27")
      (value "49.9")
      (footprint "easyedapro:R0603")
      (libsource (lib "easyedapro") (part "Res"))
    )
    (comp (ref "R28")
      (value "49.9")
      (footprint "easyedapro:R0603")
      (libsource (lib "easyedapro") (part "Res"))
    )
    (comp (ref "R29")
      (value "49.9")
      (footprint "easyedapro:R0603")
      (libsource (lib "easyedapro") (part "Res"))
    )
    (comp (ref "R30")
      (value "49.9")
      (footprint "easyedapro:R0603")
      (libsource (lib "easyedapro") (part "Res"))
    )
    (comp (ref "R31")
      (value "49.9")
      (footprint "easyedapro:R0603")
      (libsource (lib "easyedapro") (part "Res"))
    )
    (comp (ref "R32")
      (value "49.9")
      (footprint "easyedapro:R0603")
      (libsource (lib "easyedapro") (part "Res"))
    )
    (comp (ref "R33")
      (value "49.9")
      (footprint "easyedapro:R0603")
      (libsource (lib "easyedapro") (part "Res"))
    )
    (comp (ref "R34")
      (value "49.9")
      (footprint "easyedapro:R0603")
      (libsource (lib "easyedapro") (part "Res"))
    )
    (comp (ref "R35")
      (value "49.9")
      (footprint "easyedapro:R0603")
      (libsource (lib "easyedapro") (part "Res"))
    )
    (comp (ref "R36")
      (value "49.9")
      (footprint "easyedapro:R0603")
      (libsource (lib "easyedapro") (part "Res"))
    )
    (comp (ref "R44")
      (value "49.9")
      (footprint "easyedapro:R0603")
      (libsource (lib "easyedapro") (part "Res"))
    )
    (comp (ref "R45")
      (value "49.9")
      (footprint "easyedapro:R0603")
      (libsource (lib "easyedapro") (part "Res"))
    )
    (comp (ref "R54")
      (value "49.9")
      (footprint "easyedapro:R0603")
      (libsource (lib "easyedapro") (part "Res"))
    )
    (comp (ref "R55")
      (value "49.9")
      (footprint "easyedapro:R0603")
      (libsource (lib "easyedapro") (part "Res"))
    )
    (comp (ref "R60")
      (value "49.9")
      (footprint "easyedapro:R0603")
      (libsource (lib "easyedapro") (part "Res"))
    )
    (comp (ref "R61")
      (value "240")
      (footprint "easyedapro:R0603")
      (libsource (lib "easyedapro") (part "Res"))
    )
    (comp (ref "R62")
      (value "240")
      (footprint "easyedapro:R0603")
      (libsource (lib "easyedapro") (part "Res"))
    )
    (comp (ref "R63")
      (value "4.7K")
      (footprint "easyedapro:R0603")
      (libsource (lib "easyedapro") (part "Res"))
    )
    (comp (ref "R64")
      (value "100")
      (footprint "easyedapro:R0603")
      (libsource (lib "easyedapro") (part "Res"))
    )
    (comp (ref "R65")
      (value "100")
      (footprint "easyedapro:R0603")
      (libsource (lib "easyedapro") (part "Res"))
    )
    (comp (ref "R267")
      (value "100")
      (footprint "easyedapro:R0603")
      (libsource (lib "easyedapro") (part "Res"))
    )
    (comp (ref "U1")
      (value "MT41K256M16TW-107:P")
      (footprint "easyedapro:FBGA-96_L14.0-W8.0-R16-C6-P0.80-TL")
      (fields (field (name "Manufacturer") "micron(镁光)"))
      (libsource (lib "easyedapro") (part "MT41K256M16TW-107{colon}P"))
    )
    (comp (ref "U3")
      (value "MT41K256M16TW-107:P")
      (footprint "easyedapro:FBGA-96_L14.0-W8.0-R16-C6-P0.80-TL")
      (fields (field (name "Manufacturer") "micron(镁光)"))
      (libsource (lib "easyedapro") (part "MT41K256M16TW-107{colon}P"))
    )
    (comp (ref "C34")
      (value "4.7uF")
      (footprint "easyedapro:C0603")
      (libsource (lib "easyedapro") (part "CAP"))
    )
    (comp (ref "C181")
      (value "4.7uF")
      (footprint "easyedapro:C0603")
      (libsource (lib "easyedapro") (part "CAP"))
    )
    (comp (ref "C182")
      (value "4.7uF")
      (footprint "easyedapro:C0603")
      (libsource (lib "easyedapro") (part "CAP"))
    )
    (comp (ref "C183")
      (value "100nF")
      (footprint "easyedapro:C0603")
      (libsource (lib "easyedapro") (part "CAP"))
    )
    (comp (ref "C184")
      (value "4.7uF")
      (footprint "easyedapro:C0603")
      (libsource (lib "easyedapro") (part "CAP"))
    )
    (comp (ref "C189")
      (value "4.7uF")
      (footprint "easyedapro:C0603")
      (libsource (lib "easyedapro") (part "CAP"))
    )
    (comp (ref "C190")
      (value "100nF")
      (footprint "easyedapro:C0603")
      (libsource (lib "easyedapro") (part "CAP"))
    )
    (comp (ref "C191")
      (value "100nF")
      (footprint "easyedapro:C0603")
      (libsource (lib "easyedapro") (part "CAP"))
    )
    (comp (ref "C349")
      (value "100nF")
      (footprint "easyedapro:C0603")
      (libsource (lib "easyedapro") (part "CAP"))
    )
    (comp (ref "C350")
      (value "100nF")
      (footprint "easyedapro:C0603")
      (libsource (lib "easyedapro") (part "CAP"))
    )
    (comp (ref "C351")
      (value "100nF")
      (footprint "easyedapro:C0603")
      (libsource (lib "easyedapro") (part "CAP"))
    )
    (comp (ref "C352")
      (value "100nF")
      (footprint "easyedapro:C0603")
      (libsource (lib "easyedapro") (part "CAP"))
    )
    (comp (ref "C353")
      (value "100nF")
      (footprint "easyedapro:C0603")
      (libsource (lib "easyedapro") (part "CAP"))
    )
    (comp (ref "C354")
      (value "100nF")
      (footprint "easyedapro:C0603")
      (libsource (lib "easyedapro") (part "CAP"))
    )
    (comp (ref "C355")
      (value "100nF")
      (footprint "easyedapro:C0603")
      (libsource (lib "easyedapro") (part "CAP"))
    )
    (comp (ref "C356")
      (value "100nF")
      (footprint "easyedapro:C0603")
      (libsource (lib "easyedapro") (part "CAP"))
    )
    (comp (ref "C357")
      (value "100nF")
      (footprint "easyedapro:C0603")
      (libsource (lib "easyedapro") (part "CAP"))
    )
    (comp (ref "D6")
      (value "~")
      (footprint "easyedapro:D0402")
      (libsource (lib "easyedapro") (part "Zener Diode"))
    )
    (comp (ref "D7")
      (value "~")
      (footprint "easyedapro:D0402")
      (libsource (lib "easyedapro") (part "Zener Diode"))
    )
    (comp (ref "D8")
      (value "PMEG1030EJ,115")
      (footprint "easyedapro:SOD-323_L1.8-W1.3-LS2.5-RD")
      (fields (field (name "Manufacturer") "Nexperia(安世)"))
      (libsource (lib "easyedapro") (part "PMEG1030EJ,115"))
    )
    (comp (ref "F1")
      (value "1206L050/15YR")
      (footprint "easyedapro:F1206")
      (fields (field (name "Manufacturer") "Littelfuse(美国力特)"))
      (libsource (lib "easyedapro") (part "1206L050/15YR"))
    )
    (comp (ref "L8")
      (value "MH2029-600Y")
      (footprint "easyedapro:L0805")
      (fields (field (name "Manufacturer") "BOURNS"))
      (libsource (lib "easyedapro") (part "MH2029-600Y"))
    )
    (comp (ref "L9")
      (value "MH2029-600Y")
      (footprint "easyedapro:L0805")
      (fields (field (name "Manufacturer") "BOURNS"))
      (libsource (lib "easyedapro") (part "MH2029-600Y"))
    )
    (comp (ref "L10")
      (value "MH2029-600Y")
      (footprint "easyedapro:L0805")
      (fields (field (name "Manufacturer") "BOURNS"))
      (libsource (lib "easyedapro") (part "MH2029-600Y"))
    )
    (comp (ref "LED15")
      (value "~")
      (footprint "easyedapro:LED0603-RD_GREEN")
      (libsource (lib "easyedapro") (part "LED_G"))
    )
    (comp (ref "LED16")
      (value "~")
      (footprint "easyedapro:LED0603-RD_GREEN")
      (libsource (lib "easyedapro") (part "LED_G"))
    )
    (comp (ref "R69")
      (value "34.8K")
      (footprint "easyedapro:R0603")
      (libsource (lib "easyedapro") (part "Res"))
    )
    (comp (ref "R70")
      (value "100K")
      (footprint "easyedapro:R0603")
      (libsource (lib "easyedapro") (part "Res"))
    )
    (comp (ref "R72")
      (value "2.49K")
      (footprint "easyedapro:R0603")
      (libsource (lib "easyedapro") (part "Res"))
    )
    (comp (ref "R73")
      (value "12K")
      (footprint "easyedapro:R0603")
      (libsource (lib "easyedapro") (part "Res"))
    )
    (comp (ref "R74") (value "22") (footprint "easyedapro:R0603") (libsource (lib "easyedapro") (part "Res")))
    (comp (ref "R217")
      (value "22")
      (footprint "easyedapro:R0603")
      (libsource (lib "easyedapro") (part "Res"))
    )
    (comp (ref "R218")
      (value "22")
      (footprint "easyedapro:R0603")
      (libsource (lib "easyedapro") (part "Res"))
    )
    (comp (ref "R219")
      (value "22")
      (footprint "easyedapro:R0603")
      (libsource (lib "easyedapro") (part "Res"))
    )
    (comp (ref "R220")
      (value "22")
      (footprint "easyedapro:R0603")
      (libsource (lib "easyedapro") (part "Res"))
    )
    (comp (ref "R221")
      (value "22")
      (footprint "easyedapro:R0603")
      (libsource (lib "easyedapro") (part "Res"))
    )
    (comp (ref "R222")
      (value "22")
      (footprint "easyedapro:R0603")
      (libsource (lib "easyedapro") (part "Res"))
    )
    (comp (ref "R223")
      (value "22")
      (footprint "easyedapro:R0603")
      (libsource (lib "easyedapro") (part "Res"))
    )
    (comp (ref "R224")
      (value "500")
      (footprint "easyedapro:R0603")
      (libsource (lib "easyedapro") (part "Res"))
    )
    (comp (ref "R225")
      (value "500")
      (footprint "easyedapro:R0603")
      (libsource (lib "easyedapro") (part "Res"))
    )
    (comp (ref "R226")
      (value "12K")
      (footprint "easyedapro:R0603")
      (libsource (lib "easyedapro") (part "Res"))
    )
    (comp (ref "R270") (value "0") (footprint "easyedapro:R0603") (libsource (lib "easyedapro") (part "Res")))
    (comp (ref "R271") (value "0") (footprint "easyedapro:R0603") (libsource (lib "easyedapro") (part "Res")))
    (comp (ref "R278")
      (value "12K")
      (footprint "easyedapro:R0603")
      (libsource (lib "easyedapro") (part "Res"))
    )
    (comp (ref "R279")
      (value "12K")
      (footprint "easyedapro:R0603")
      (libsource (lib "easyedapro") (part "Res"))
    )
    (comp (ref "U27")
      (value "GT-USB-7010ASV")
      (footprint "easyedapro:USB-C-SMD_G-SWITCH_GT-USB-7010ASV")
      (fields (field (name "Manufacturer") "G-Switch(品赞)"))
      (libsource (lib "easyedapro") (part "GT-USB-7010ASV"))
    )
    (comp (ref "U34")
      (value "FT2232HL-REEL")
      (footprint "easyedapro:LQFP-64_L10.0-W10.0-P0.50-LS12.0-TL")
      (fields (field (name "Manufacturer") "FTDI(飞特帝亚)"))
      (libsource (lib "easyedapro") (part "FT2232HL"))
    )
    (comp (ref "U60")
      (value "93LC56B-I/SN")
      (footprint "easyedapro:SOIC-8_L5.0-W4.0-P1.27-LS6.0-BL")
      (fields (field (name "Manufacturer") "MICROCHIP(美国微芯)"))
      (libsource (lib "easyedapro") (part "93LC56B-I/SN"))
    )
    (comp (ref "X1")
      (value "12MHz ECS-2520MV-120-BN-TR")
      (footprint "easyedapro:OSC-SMD_4P-L2.5-W2.0-BL")
      (fields (field (name "Manufacturer Part") "ECS-2520MV-120-BN-TR") (field (name "Manufacturer") "ECS"))
      (libsource (lib "easyedapro") (part "ECS-2520MV-120-BN-TR"))
    )
    (comp (ref "C155")
      (value "4u7")
      (footprint "easyedapro:C0603")
      (libsource (lib "easyedapro") (part "CAP"))
    )
    (comp (ref "C157")
      (value "4u7")
      (footprint "easyedapro:C0603")
      (libsource (lib "easyedapro") (part "CAP"))
    )
    (comp (ref "C159")
      (value "4u7")
      (footprint "easyedapro:C0603")
      (libsource (lib "easyedapro") (part "CAP"))
    )
    (comp (ref "C166")
      (value "4u7")
      (footprint "easyedapro:C0603")
      (libsource (lib "easyedapro") (part "CAP"))
    )
    (comp (ref "C168")
      (value "4u7")
      (footprint "easyedapro:C0603")
      (libsource (lib "easyedapro") (part "CAP"))
    )
    (comp (ref "C170")
      (value "4u7")
      (footprint "easyedapro:C0603")
      (libsource (lib "easyedapro") (part "CAP"))
    )
    (comp (ref "C366")
      (value "100nF")
      (footprint "easyedapro:C0603")
      (libsource (lib "easyedapro") (part "CAP"))
    )
    (comp (ref "C367")
      (value "100nF")
      (footprint "easyedapro:C0603")
      (libsource (lib "easyedapro") (part "CAP"))
    )
    (comp (ref "C368")
      (value "100nF")
      (footprint "easyedapro:C0603")
      (libsource (lib "easyedapro") (part "CAP"))
    )
    (comp (ref "C369")
      (value "100nF")
      (footprint "easyedapro:C0603")
      (libsource (lib "easyedapro") (part "CAP"))
    )
    (comp (ref "C370")
      (value "100nF")
      (footprint "easyedapro:C0603")
      (libsource (lib "easyedapro") (part "CAP"))
    )
    (comp (ref "C371")
      (value "100nF")
      (footprint "easyedapro:C0603")
      (libsource (lib "easyedapro") (part "CAP"))
    )
    (comp (ref "C372")
      (value "100nF")
      (footprint "easyedapro:C0603")
      (libsource (lib "easyedapro") (part "CAP"))
    )
    (comp (ref "C373")
      (value "100nF")
      (footprint "easyedapro:C0603")
      (libsource (lib "easyedapro") (part "CAP"))
    )
    (comp (ref "C374")
      (value "100nF")
      (footprint "easyedapro:C0603")
      (libsource (lib "easyedapro") (part "CAP"))
    )
    (comp (ref "C375")
      (value "100nF")
      (footprint "easyedapro:C0603")
      (libsource (lib "easyedapro") (part "CAP"))
    )
    (comp (ref "C376")
      (value "100nF")
      (footprint "easyedapro:C0603")
      (libsource (lib "easyedapro") (part "CAP"))
    )
    (comp (ref "C377")
      (value "100nF")
      (footprint "easyedapro:C0603")
      (libsource (lib "easyedapro") (part "CAP"))
    )
    (comp (ref "C378")
      (value "100nF")
      (footprint "easyedapro:C0603")
      (libsource (lib "easyedapro") (part "CAP"))
    )
    (comp (ref "C379")
      (value "100nF")
      (footprint "easyedapro:C0603")
      (libsource (lib "easyedapro") (part "CAP"))
    )
    (comp (ref "L5")
      (value "MH2029-600Y")
      (footprint "easyedapro:L0805")
      (fields (field (name "Manufacturer") "BOURNS"))
      (libsource (lib "easyedapro") (part "MH2029-600Y"))
    )
    (comp (ref "L6")
      (value "MH2029-600Y")
      (footprint "easyedapro:L0805")
      (fields (field (name "Manufacturer") "BOURNS"))
      (libsource (lib "easyedapro") (part "MH2029-600Y"))
    )
    (comp (ref "L11")
      (value "3.3uH")
      (footprint "easyedapro:L0603")
      (fields (field (name "Manufacturer Part") "LQM18PN3R3MGHD") (field (name "Manufacturer") "muRata(村田)"))
      (libsource (lib "easyedapro") (part "LQM18PN3R3MGHD"))
    )
    (comp (ref "R237")
      (value "510")
      (footprint "easyedapro:R0603")
      (libsource (lib "easyedapro") (part "Res"))
    )
    (comp (ref "R238")
      (value "510")
      (footprint "easyedapro:R0603")
      (libsource (lib "easyedapro") (part "Res"))
    )
    (comp (ref "R239")
      (value "4.7K")
      (footprint "easyedapro:R0603")
      (libsource (lib "easyedapro") (part "Res"))
    )
    (comp (ref "R240")
      (value "4.7K")
      (footprint "easyedapro:R0603")
      (libsource (lib "easyedapro") (part "Res"))
    )
    (comp (ref "R241")
      (value "4.7K")
      (footprint "easyedapro:R0603")
      (libsource (lib "easyedapro") (part "Res"))
    )
    (comp (ref "R242")
      (value "22")
      (footprint "easyedapro:R0603")
      (libsource (lib "easyedapro") (part "Res"))
    )
    (comp (ref "R243")
      (value "22")
      (footprint "easyedapro:R0603")
      (libsource (lib "easyedapro") (part "Res"))
    )
    (comp (ref "R244")
      (value "22")
      (footprint "easyedapro:R0603")
      (libsource (lib "easyedapro") (part "Res"))
    )
    (comp (ref "R245")
      (value "1K")
      (footprint "easyedapro:R0603")
      (libsource (lib "easyedapro") (part "Res"))
    )
    (comp (ref "R246")
      (value "1K")
      (footprint "easyedapro:R0603")
      (libsource (lib "easyedapro") (part "Res"))
    )
    (comp (ref "R247")
      (value "1K")
      (footprint "easyedapro:R0603")
      (libsource (lib "easyedapro") (part "Res"))
    )
    (comp (ref "R248")
      (value "1K")
      (footprint "easyedapro:R0603")
      (libsource (lib "easyedapro") (part "Res"))
    )
    (comp (ref "R249")
      (value "1K")
      (footprint "easyedapro:R0603")
      (libsource (lib "easyedapro") (part "Res"))
    )
    (comp (ref "R250")
      (value "2.49K")
      (footprint "easyedapro:R0603")
      (libsource (lib "easyedapro") (part "Res"))
    )
    (comp (ref "R251")
      (value "4.7K")
      (footprint "easyedapro:R0603")
      (libsource (lib "easyedapro") (part "Res"))
    )
    (comp (ref "R252")
      (value "4.7K")
      (footprint "easyedapro:R0603")
      (libsource (lib "easyedapro") (part "Res"))
    )
    (comp (ref "R253")
      (value "DNP_4.7K")
      (footprint "easyedapro:R0603")
      (libsource (lib "easyedapro") (part "Res"))
    )
    (comp (ref "R254")
      (value "4.7K")
      (footprint "easyedapro:R0603")
      (libsource (lib "easyedapro") (part "Res"))
    )
    (comp (ref "R255")
      (value "22")
      (footprint "easyedapro:R0603")
      (libsource (lib "easyedapro") (part "Res"))
    )
    (comp (ref "R256")
      (value "22")
      (footprint "easyedapro:R0603")
      (libsource (lib "easyedapro") (part "Res"))
    )
    (comp (ref "R257")
      (value "22")
      (footprint "easyedapro:R0603")
      (libsource (lib "easyedapro") (part "Res"))
    )
    (comp (ref "R258")
      (value "22")
      (footprint "easyedapro:R0603")
      (libsource (lib "easyedapro") (part "Res"))
    )
    (comp (ref "R259")
      (value "22")
      (footprint "easyedapro:R0603")
      (libsource (lib "easyedapro") (part "Res"))
    )
    (comp (ref "R260")
      (value "22")
      (footprint "easyedapro:R0603")
      (libsource (lib "easyedapro") (part "Res"))
    )
    (comp (ref "RJ1")
      (value "HR911130A")
      (footprint "easyedapro:RJ45-TH_HR911130A")
      (description "Connector Type:RJ45Receptacle Number of Ports:1 Shielding:- LED:WithLED Ratings:-")
      (fields (field (name "Manufacturer") "HANRUN(汉仁)"))
      (libsource (lib "easyedapro") (part "HR911130A"))
    )
    (comp (ref "U35")
      (value "RTL8211F-CG")
      (footprint "easyedapro:WQFN-40_L5.0-W5.0-P0.4-BL-EP")
      (fields (field (name "Manufacturer") "REALTEK(瑞昱)"))
      (libsource (lib "easyedapro") (part "RTL8211F-CG"))
    )
    (comp (ref "U70")
      (value "25MHz")
      (footprint "easyedapro:OSC-SMD_4P-L2.5-W2.0-BL-1")
      (fields (field (name "Manufacturer Part") "ECS-2520MVQ-250-CN-TR") (field (name "Manufacturer") "ECS"))
      (libsource (lib "easyedapro") (part "ECS-2520MVQ-250-CN-TR"))
    )
    (comp (ref "C192")
      (value "100nF")
      (footprint "easyedapro:C0603")
      (libsource (lib "easyedapro") (part "CAP"))
    )
    (comp (ref "C193")
      (value "100nF")
      (footprint "easyedapro:C0603")
      (libsource (lib "easyedapro") (part "CAP"))
    )
    (comp (ref "C194")
      (value "100nF")
      (footprint "easyedapro:C0603")
      (libsource (lib "easyedapro") (part "CAP"))
    )
    (comp (ref "C195")
      (value "100nF")
      (footprint "easyedapro:C0603")
      (libsource (lib "easyedapro") (part "CAP"))
    )
    (comp (ref "C406")
      (value "100nF")
      (footprint "easyedapro:C0603")
      (libsource (lib "easyedapro") (part "CAP"))
    )
    (comp (ref "LED17")
      (value "~")
      (footprint "easyedapro:LED0603-R-RD")
      (libsource (lib "easyedapro") (part "LED_R"))
    )
    (comp (ref "Q7")
      (value "T2N7002AK,LM")
      (footprint "easyedapro:SOT-23-3_L2.9-W1.3-P1.90-LS2.4-BR")
      (fields (field (name "Manufacturer") "TOSHIBA(东芝)"))
      (libsource (lib "easyedapro") (part "T2N7002AK,LM"))
    )
    (comp (ref "R75") (value "22") (footprint "easyedapro:R0603") (libsource (lib "easyedapro") (part "Res")))
    (comp (ref "R76")
      (value "4.7K")
      (footprint "easyedapro:R0603")
      (libsource (lib "easyedapro") (part "Res"))
    )
    (comp (ref "R77")
      (value "12K")
      (footprint "easyedapro:R0603")
      (libsource (lib "easyedapro") (part "Res"))
    )
    (comp (ref "R78")
      (value "12K")
      (footprint "easyedapro:R0603")
      (libsource (lib "easyedapro") (part "Res"))
    )
    (comp (ref "R79")
      (value "12K")
      (footprint "easyedapro:R0603")
      (libsource (lib "easyedapro") (part "Res"))
    )
    (comp (ref "R80")
      (value "500")
      (footprint "easyedapro:R0603")
      (libsource (lib "easyedapro") (part "Res"))
    )
    (comp (ref "R81")
      (value "12K")
      (footprint "easyedapro:R0603")
      (libsource (lib "easyedapro") (part "Res"))
    )
    (comp (ref "R82")
      (value "100K")
      (footprint "easyedapro:R0603")
      (libsource (lib "easyedapro") (part "Res"))
    )
    (comp (ref "R85") (value "22") (footprint "easyedapro:R0603") (libsource (lib "easyedapro") (part "Res")))
    (comp (ref "R88")
      (value "20K")
      (footprint "easyedapro:R0603")
      (libsource (lib "easyedapro") (part "Res"))
    )
    (comp (ref "R89")
      (value "20K")
      (footprint "easyedapro:R0603")
      (libsource (lib "easyedapro") (part "Res"))
    )
    (comp (ref "R90")
      (value "20K")
      (footprint "easyedapro:R0603")
      (libsource (lib "easyedapro") (part "Res"))
    )
    (comp (ref "R91") (value "1K") (footprint "easyedapro:R0603") (libsource (lib "easyedapro") (part "Res")))
    (comp (ref "R92") (value "1K") (footprint "easyedapro:R0603") (libsource (lib "easyedapro") (part "Res")))
    (comp (ref "R93") (value "1K") (footprint "easyedapro:R0603") (libsource (lib "easyedapro") (part "Res")))
    (comp (ref "R174")
      (value "22")
      (footprint "easyedapro:R0603")
      (libsource (lib "easyedapro") (part "Res"))
    )
    (comp (ref "R261")
      (value "22")
      (footprint "easyedapro:R0603")
      (libsource (lib "easyedapro") (part "Res"))
    )
    (comp (ref "R262")
      (value "22")
      (footprint "easyedapro:R0603")
      (libsource (lib "easyedapro") (part "Res"))
    )
    (comp (ref "R263")
      (value "22")
      (footprint "easyedapro:R0603")
      (libsource (lib "easyedapro") (part "Res"))
    )
    (comp (ref "R264")
      (value "22")
      (footprint "easyedapro:R0603")
      (libsource (lib "easyedapro") (part "Res"))
    )
    (comp (ref "R265")
      (value "22")
      (footprint "easyedapro:R0603")
      (libsource (lib "easyedapro") (part "Res"))
    )
    (comp (ref "R266")
      (value "22")
      (footprint "easyedapro:R0603")
      (libsource (lib "easyedapro") (part "Res"))
    )
    (comp (ref "R268")
      (value "20k")
      (footprint "easyedapro:R0603")
      (libsource (lib "easyedapro") (part "Res"))
    )
    (comp (ref "R269")
      (value "20k")
      (footprint "easyedapro:R0603")
      (libsource (lib "easyedapro") (part "Res"))
    )
    (comp (ref "R272")
      (value "20K")
      (footprint "easyedapro:R0603")
      (libsource (lib "easyedapro") (part "Res"))
    )
    (comp (ref "R273")
      (value "DNP_0R")
      (footprint "easyedapro:R0603")
      (libsource (lib "easyedapro") (part "Res"))
    )
    (comp (ref "R274")
      (value "1K")
      (footprint "easyedapro:R0603")
      (libsource (lib "easyedapro") (part "Res"))
    )
    (comp (ref "R275")
      (value "20K")
      (footprint "easyedapro:R0603")
      (libsource (lib "easyedapro") (part "Res"))
    )
    (comp (ref "R276")
      (value "DNP_0R")
      (footprint "easyedapro:R0603")
      (libsource (lib "easyedapro") (part "Res"))
    )
    (comp (ref "R277")
      (value "1K")
      (footprint "easyedapro:R0603")
      (libsource (lib "easyedapro") (part "Res"))
    )
    (comp (ref "SW2")
      (value "~")
      (footprint "easyedapro:SW-SMD_4P-L6.0-W6.0-P4.50-LS9.0-2")
      (libsource (lib "easyedapro") (part "轻触按键"))
    )
    (comp (ref "SW4")
      (value "SMXS-03K-TP")
      (footprint "easyedapro:SW-SMD_SMXS-03K-TP")
      (fields (field (name "Manufacturer") "SM Switch"))
      (libsource (lib "easyedapro") (part "SMXS-03K-TP"))
    )
    (comp (ref "U61")
      (value "SN74LVC1G07DBVT")
      (footprint "easyedapro:SOT-23-5_L2.9-W1.6-P0.95-LS2.8-BR")
      (fields (field (name "Manufacturer") "TI(德州仪器)"))
      (libsource (lib "easyedapro") (part "SN74LVC1G07DBVT"))
    )
    (comp (ref "X2")
      (value "33.3MHz ECS-2520MV-333.3-BN-TR")
      (footprint "easyedapro:OSC-SMD_4P-L2.5-W2.0-BL")
      (fields (field (name "Manufacturer Part") "ECS-2520MV-120-BN-TR") (field (name "Manufacturer") "ECS"))
      (libsource (lib "easyedapro") (part "ECS-2520MV-120-BN-TR"))
    )
    (comp (ref "C144")
      (value "100nF")
      (footprint "easyedapro:C0603")
      (libsource (lib "easyedapro") (part "CAP"))
    )
    (comp (ref "C176")
      (value "100nF")
      (footprint "easyedapro:C0603")
      (libsource (lib "easyedapro") (part "CAP"))
    )
    (comp (ref "D1")
      (value "~")
      (footprint "easyedapro:D0402")
      (libsource (lib "easyedapro") (part "Zener Diode"))
    )
    (comp (ref "D2")
      (value "~")
      (footprint "easyedapro:D0402")
      (libsource (lib "easyedapro") (part "Zener Diode"))
    )
    (comp (ref "D3")
      (value "~")
      (footprint "easyedapro:D0402")
      (libsource (lib "easyedapro") (part "Zener Diode"))
    )
    (comp (ref "D4")
      (value "~")
      (footprint "easyedapro:D0402")
      (libsource (lib "easyedapro") (part "Zener Diode"))
    )
    (comp (ref "HDR1")
      (value "Digilent JTAG-HS3")
      (footprint "easyedapro:HDR-SMD_14P-P2.54-V-M-R2-C7-LS7.4")
      (fields (field (name "Manufacturer") "HCTL(华灿天禄)"))
      (libsource (lib "easyedapro") (part "PZ254-2-07-S"))
    )
    (comp (ref "LED14")
      (value "~")
      (footprint "easyedapro:LED0603-R-RD")
      (libsource (lib "easyedapro") (part "LED_R"))
    )
    (comp (ref "Q6")
      (value "T2N7002AK,LM")
      (footprint "easyedapro:SOT-23-3_L2.9-W1.3-P1.90-LS2.4-BR")
      (fields (field (name "Manufacturer") "TOSHIBA(东芝)"))
      (libsource (lib "easyedapro") (part "T2N7002AK,LM"))
    )
    (comp (ref "R47")
      (value "4.7K")
      (footprint "easyedapro:R0603")
      (libsource (lib "easyedapro") (part "Res"))
    )
    (comp (ref "R48")
      (value "4.7K")
      (footprint "easyedapro:R0603")
      (libsource (lib "easyedapro") (part "Res"))
    )
    (comp (ref "R49")
      (value "4.7K")
      (footprint "easyedapro:R0603")
      (libsource (lib "easyedapro") (part "Res"))
    )
    (comp (ref "R50")
      (value "4.7K")
      (footprint "easyedapro:R0603")
      (libsource (lib "easyedapro") (part "Res"))
    )
    (comp (ref "R51")
      (value "4.7K")
      (footprint "easyedapro:R0603")
      (libsource (lib "easyedapro") (part "Res"))
    )
    (comp (ref "R52") (value "1k") (footprint "easyedapro:R0603") (libsource (lib "easyedapro") (part "Res")))
    (comp (ref "R53")
      (value "500")
      (footprint "easyedapro:R0603")
      (libsource (lib "easyedapro") (part "Res"))
    )
    (comp (ref "R56") (value "22") (footprint "easyedapro:R0603") (libsource (lib "easyedapro") (part "Res")))
    (comp (ref "R57") (value "22") (footprint "easyedapro:R0603") (libsource (lib "easyedapro") (part "Res")))
    (comp (ref "R58") (value "22") (footprint "easyedapro:R0603") (libsource (lib "easyedapro") (part "Res")))
    (comp (ref "R59") (value "22") (footprint "easyedapro:R0603") (libsource (lib "easyedapro") (part "Res")))
    (comp (ref "R84")
      (value "12K")
      (footprint "easyedapro:R0603")
      (libsource (lib "easyedapro") (part "Res"))
    )
    (comp (ref "SW1")
      (value "~")
      (footprint "easyedapro:SW-SMD_4P-L6.0-W6.0-P4.50-LS9.0-2")
      (libsource (lib "easyedapro") (part "轻触按键"))
    )
    (comp (ref "U63")
      (value "W25Q512JVEIQ")
      (footprint "easyedapro:WSON-8_L8.0-W6.0-P1.27-TL-EP")
      (fields (field (name "Manufacturer") "WINBOND(华邦)"))
      (libsource (lib "easyedapro") (part "W25Q512JVEIQ_C3034691"))
    )
    (comp (ref "C240")
      (value "100nF")
      (footprint "easyedapro:C0603")
      (libsource (lib "easyedapro") (part "CAP"))
    )
    (comp (ref "C241")
      (value "100nF")
      (footprint "easyedapro:C0603")
      (libsource (lib "easyedapro") (part "CAP"))
    )
    (comp (ref "C243")
      (value "100nF")
      (footprint "easyedapro:C0603")
      (libsource (lib "easyedapro") (part "CAP"))
    )
    (comp (ref "CN2")
      (value "10029449-111RLF")
      (footprint "easyedapro:HDMI-SMD_10029449-001RLF")
      (fields (field (name "Manufacturer") "Amphenol"))
      (libsource (lib "easyedapro") (part "10029449-111RLF"))
    )
    (comp (ref "R176")
      (value "10K")
      (footprint "easyedapro:R0603")
      (libsource (lib "easyedapro") (part "Res"))
    )
    (comp (ref "R185")
      (value "49.9")
      (footprint "easyedapro:R0603")
      (libsource (lib "easyedapro") (part "Res"))
    )
    (comp (ref "R186")
      (value "49.9")
      (footprint "easyedapro:R0603")
      (libsource (lib "easyedapro") (part "Res"))
    )
    (comp (ref "R187")
      (value "49.9")
      (footprint "easyedapro:R0603")
      (libsource (lib "easyedapro") (part "Res"))
    )
    (comp (ref "R188")
      (value "49.9")
      (footprint "easyedapro:R0603")
      (libsource (lib "easyedapro") (part "Res"))
    )
    (comp (ref "R189")
      (value "49.9")
      (footprint "easyedapro:R0603")
      (libsource (lib "easyedapro") (part "Res"))
    )
    (comp (ref "R190")
      (value "49.9")
      (footprint "easyedapro:R0603")
      (libsource (lib "easyedapro") (part "Res"))
    )
    (comp (ref "R191")
      (value "49.9")
      (footprint "easyedapro:R0603")
      (libsource (lib "easyedapro") (part "Res"))
    )
    (comp (ref "R192")
      (value "49.9")
      (footprint "easyedapro:R0603")
      (libsource (lib "easyedapro") (part "Res"))
    )
    (comp (ref "U78")
      (value "TPD12S016PWR")
      (footprint "easyedapro:TSSOP-24_L7.8-W4.4-P0.65-LS6.4-BL")
      (description "Supply Voltage:4.5V~5.5V Supply Voltage:4.5V~5.5V")
      (fields (field (name "Manufacturer") "TI(德州仪器)"))
      (libsource (lib "easyedapro") (part "TPD12S016PWR"))
    )
    (comp (ref "R46")
      (value "4.7K")
      (footprint "easyedapro:R0603")
      (libsource (lib "easyedapro") (part "Res"))
    )
    (comp (ref "H5")
      (value "PZ127-2-04-S")
      (footprint "easyedapro:HDR-SMD_8P-P1.27-V-M-C2-C4-LS5.3")
      (fields (field (name "Manufacturer") "HCTL(华灿天禄)"))
      (libsource (lib "easyedapro") (part "PZ127-2-04-S"))
    )
    (comp (ref "U44")
      (value "~")
      (footprint "easyedapro:EBBI 68 Plug - 716612568")
      (libsource (lib "easyedapro") (part "EBBI 68 Plug - 716612568"))
    )
    (comp (ref "U45")
      (value "~")
      (footprint "easyedapro:EBBI 68 Plug - 716612568")
      (libsource (lib "easyedapro") (part "EBBI 68 Plug - 716612568"))
    )
    (comp (ref "C358")
      (value "100nF")
      (footprint "easyedapro:C0603")
      (libsource (lib "easyedapro") (part "CAP"))
    )
    (comp (ref "C359")
      (value "470nF")
      (footprint "easyedapro:C0603")
      (libsource (lib "easyedapro") (part "CAP"))
    )
    (comp (ref "C360")
      (value "470nF")
      (footprint "easyedapro:C0603")
      (libsource (lib "easyedapro") (part "CAP"))
    )
    (comp (ref "CARD2")
      (value "TF-01A")
      (footprint "easyedapro:TF-SMD_TF-02")
      (fields (field (name "Manufacturer") "Yuandi(元迪)"))
      (libsource (lib "easyedapro") (part "TF-01A_C2889258"))
    )
    (comp (ref "R227")
      (value "47K")
      (footprint "easyedapro:R0603")
      (libsource (lib "easyedapro") (part "Res"))
    )
    (comp (ref "R228")
      (value "200")
      (footprint "easyedapro:R0603")
      (libsource (lib "easyedapro") (part "Res"))
    )
    (comp (ref "R229")
      (value "4.7K")
      (footprint "easyedapro:R0603")
      (libsource (lib "easyedapro") (part "Res"))
    )
    (comp (ref "R230")
      (value "4.7K")
      (footprint "easyedapro:R0603")
      (libsource (lib "easyedapro") (part "Res"))
    )
    (comp (ref "U74")
      (value "TXS02612RTWR")
      (footprint "easyedapro:WQFN-24_L4.0-W4.0-P0.50-TL-EP2.5")
      (fields (field (name "Manufacturer") "TI(德州仪器)"))
      (libsource (lib "easyedapro") (part "TXS02612RTWR"))
    )
    (comp (ref "C227")
      (value "4.7uF")
      (footprint "easyedapro:C0603")
      (libsource (lib "easyedapro") (part "CAP"))
    )
    (comp (ref "C228")
      (value "4.7uF")
      (footprint "easyedapro:C0603")
      (libsource (lib "easyedapro") (part "CAP"))
    )
    (comp (ref "C229")
      (value "4.7uF")
      (footprint "easyedapro:C0603")
      (libsource (lib "easyedapro") (part "CAP"))
    )
    (comp (ref "C230")
      (value "4.7uF")
      (footprint "easyedapro:C0603")
      (libsource (lib "easyedapro") (part "CAP"))
    )
    (comp (ref "C361")
      (value "100nF")
      (footprint "easyedapro:C0603")
      (libsource (lib "easyedapro") (part "CAP"))
    )
    (comp (ref "C362")
      (value "100nF")
      (footprint "easyedapro:C0603")
      (libsource (lib "easyedapro") (part "CAP"))
    )
    (comp (ref "C363")
      (value "100nF")
      (footprint "easyedapro:C0603")
      (libsource (lib "easyedapro") (part "CAP"))
    )
    (comp (ref "C364")
      (value "100nF")
      (footprint "easyedapro:C0603")
      (libsource (lib "easyedapro") (part "CAP"))
    )
    (comp (ref "C365")
      (value "100nF")
      (footprint "easyedapro:C0603")
      (libsource (lib "easyedapro") (part "CAP"))
    )
    (comp (ref "D9")
      (value "~")
      (footprint "easyedapro:D0402")
      (libsource (lib "easyedapro") (part "Zener Diode"))
    )
    (comp (ref "D10")
      (value "~")
      (footprint "easyedapro:D0402")
      (libsource (lib "easyedapro") (part "Zener Diode"))
    )
    (comp (ref "D11")
      (value "~")
      (footprint "easyedapro:D0402")
      (libsource (lib "easyedapro") (part "Zener Diode"))
    )
    (comp (ref "D12")
      (value "PMEG1030EJ,115")
      (footprint "easyedapro:SOD-323_L1.8-W1.3-LS2.5-RD")
      (fields (field (name "Manufacturer") "Nexperia(安世)"))
      (libsource (lib "easyedapro") (part "PMEG1030EJ,115"))
    )
    (comp (ref "L12")
      (value "MH2029-600Y")
      (footprint "easyedapro:L0805")
      (fields (field (name "Manufacturer") "BOURNS"))
      (libsource (lib "easyedapro") (part "MH2029-600Y"))
    )
    (comp (ref "R231")
      (value "22")
      (footprint "easyedapro:R0603")
      (libsource (lib "easyedapro") (part "Res"))
    )
    (comp (ref "R232")
      (value "1K")
      (footprint "easyedapro:R0603")
      (libsource (lib "easyedapro") (part "Res"))
    )
    (comp (ref "R233")
      (value "8.06K")
      (footprint "easyedapro:R0603")
      (libsource (lib "easyedapro") (part "Res"))
    )
    (comp (ref "R234")
      (value "12K")
      (footprint "easyedapro:R0603")
      (libsource (lib "easyedapro") (part "Res"))
    )
    (comp (ref "R235")
      (value "4.7K")
      (footprint "easyedapro:R0603")
      (libsource (lib "easyedapro") (part "Res"))
    )
    (comp (ref "R236")
      (value "510")
      (footprint "easyedapro:R0603")
      (libsource (lib "easyedapro") (part "Res"))
    )
    (comp (ref "U36")
      (value "USB3320C-EZK")
      (footprint "easyedapro:QFN-32_L5.0-W5.0-P0.50-BL-EP3.4")
      (fields (field (name "Manufacturer") "MICROCHIP(美国微芯)"))
      (libsource (lib "easyedapro") (part "USB3320C-EZK"))
    )
    (comp (ref "U72")
      (value "13MHz")
      (footprint "easyedapro:OSC-SMD_4P-L2.5-W2.0-BL")
      (fields (field (name "Manufacturer Part") "ECS-2520MV-130-BN-TR") (field (name "Manufacturer") "ECS"))
      (libsource (lib "easyedapro") (part "ECS-2520MV-130-BN-TR"))
    )
    (comp (ref "U73")
      (value "MIC2099-1YMT-TR")
      (footprint "easyedapro:UDFN-6_L1.6-W1.6-P0.50-BL-EP1.2")
      (fields (field (name "Manufacturer") "MICROCHIP(美国微芯)"))
      (libsource (lib "easyedapro") (part "MIC2099-1YMT-TR"))
    )
    (comp (ref "USB1")
      (value "678038020")
      (footprint "easyedapro:MICRO-USB-SMD_MOLEX_678038020")
      (fields (field (name "Manufacturer") "MOLEX"))
      (libsource (lib "easyedapro") (part "678038020"))
    )
  )
  (nets
    (net (code "1") (name "0V675") (class "Default")
      (node (ref "C220") (pin "1") (pinfunction "1_1") (pintype "input"))
      (node (ref "C221") (pin "1") (pinfunction "1_1") (pintype "input"))
      (node (ref "C40") (pin "1") (pinfunction "1_1") (pintype "input"))
      (node (ref "C41") (pin "1") (pinfunction "1_1") (pintype "input"))
      (node (ref "C43") (pin "1") (pinfunction "1_1") (pintype "input"))
      (node (ref "C44") (pin "1") (pinfunction "1_1") (pintype "input"))
      (node (ref "C72") (pin "1") (pinfunction "1_1") (pintype "input"))
      (node (ref "C74") (pin "1") (pinfunction "1_1") (pintype "input"))
      (node (ref "C75") (pin "1") (pinfunction "1_1") (pintype "input"))
      (node (ref "C76") (pin "1") (pinfunction "1_1") (pintype "input"))
      (node (ref "C90") (pin "1") (pinfunction "1_1") (pintype "input"))
      (node (ref "C91") (pin "1") (pinfunction "1_1") (pintype "input"))
      (node (ref "C92") (pin "1") (pinfunction "1_1") (pintype "input"))
      (node (ref "C93") (pin "1") (pinfunction "1_1") (pintype "input"))
      (node (ref "R127") (pin "2") (pinfunction "2_2") (pintype "input"))
      (node (ref "R18") (pin "2") (pinfunction "2_2") (pintype "input"))
      (node (ref "R19") (pin "2") (pinfunction "2_2") (pintype "input"))
      (node (ref "R20") (pin "2") (pinfunction "2_2") (pintype "input"))
      (node (ref "R21") (pin "2") (pinfunction "2_2") (pintype "input"))
      (node (ref "R22") (pin "2") (pinfunction "2_2") (pintype "input"))
      (node (ref "R23") (pin "2") (pinfunction "2_2") (pintype "input"))
      (node (ref "R24") (pin "2") (pinfunction "2_2") (pintype "input"))
      (node (ref "R25") (pin "2") (pinfunction "2_2") (pintype "input"))
      (node (ref "R26") (pin "2") (pinfunction "2_2") (pintype "input"))
      (node (ref "R27") (pin "2") (pinfunction "2_2") (pintype "input"))
      (node (ref "R28") (pin "2") (pinfunction "2_2") (pintype "input"))
      (node (ref "R29") (pin "2") (pinfunction "2_2") (pintype "input"))
      (node (ref "R30") (pin "2") (pinfunction "2_2") (pintype "input"))
      (node (ref "R31") (pin "2") (pinfunction "2_2") (pintype "input"))
      (node (ref "R32") (pin "2") (pinfunction "2_2") (pintype "input"))
      (node (ref "R33") (pin "2") (pinfunction "2_2") (pintype "input"))
      (node (ref "R34") (pin "2") (pinfunction "2_2") (pintype "input"))
      (node (ref "R35") (pin "2") (pinfunction "2_2") (pintype "input"))
      (node (ref "R36") (pin "2") (pinfunction "2_2") (pintype "input"))
      (node (ref "R44") (pin "2") (pinfunction "2_2") (pintype "input"))
      (node (ref "R45") (pin "2") (pinfunction "2_2") (pintype "input"))
      (node (ref "R54") (pin "2") (pinfunction "2_2") (pintype "input"))
      (node (ref "R55") (pin "2") (pinfunction "2_2") (pintype "input"))
      (node (ref "R60") (pin "2") (pinfunction "2_2") (pintype "input"))
      (node (ref "U68") (pin "3") (pinfunction "VTTS_3") (pintype "input"))
      (node (ref "U68") (pin "8") (pinfunction "VTT_8") (pintype "input"))
    )
    (net (code "2") (name "0V675_EN") (class "Default")
      (node (ref "R124") (pin "1") (pinfunction "1_1") (pintype "input"))
      (node (ref "R125") (pin "2") (pinfunction "2_2") (pintype "input"))
      (node (ref "U68") (pin "2") (pinfunction "EN_2") (pintype "input"))
    )
    (net (code "3") (name "0V675_REF") (class "Default")
      (node (ref "C222") (pin "1") (pinfunction "1_1") (pintype "input"))
      (node (ref "C35") (pin "2") (pinfunction "2_2") (pintype "input"))
      (node (ref "C36") (pin "1") (pinfunction "1_1") (pintype "input"))
      (node (ref "C37") (pin "1") (pinfunction "1_1") (pintype "input"))
      (node (ref "C38") (pin "1") (pinfunction "1_1") (pintype "input"))
      (node (ref "C39") (pin "1") (pinfunction "1_1") (pintype "input"))
      (node (ref "C6") (pin "2") (pinfunction "2_2") (pintype "input"))
      (node (ref "U1") (pin "H1") (pinfunction "VREFDQ_H1") (pintype "input"))
      (node (ref "U1") (pin "M8") (pinfunction "VREFCA_M8") (pintype "input"))
      (node (ref "U2") (pin "H7") (pinfunction "PS_DDR_VREF0_502_H7") (pintype "input"))
      (node (ref "U2") (pin "P7") (pinfunction "PS_DDR_VREF1_502_P7") (pintype "input"))
      (node (ref "U3") (pin "H1") (pinfunction "VREFDQ_H1") (pintype "input"))
      (node (ref "U3") (pin "M8") (pinfunction "VREFCA_M8") (pintype "input"))
      (node (ref "U68") (pin "4") (pinfunction "VREF_4") (pintype "input"))
    )
    (net (code "4") (name "0V675_VDDQ") (class "Default")
      (node (ref "R130") (pin "1") (pinfunction "1_1") (pintype "input"))
      (node (ref "U68") (pin "5") (pinfunction "VDDQ_5") (pintype "input"))
    )
    (net (code "5") (name "1V0") (class "Default")
      (node (ref "C244") (pin "1") (pinfunction "1_1") (pintype "input"))
      (node (ref "C248") (pin "1") (pinfunction "1_1") (pintype "input"))
      (node (ref "C253") (pin "1") (pinfunction "1_1") (pintype "input"))
      (node (ref "C279") (pin "1") (pinfunction "1_1") (pintype "input"))
      (node (ref "C289") (pin "1") (pinfunction "1_1") (pintype "input"))
      (node (ref "C29") (pin "2") (pinfunction "2_2") (pintype "input"))
      (node (ref "C32") (pin "1") (pinfunction "1_1") (pintype "input"))
      (node (ref "C33") (pin "1") (pinfunction "1_1") (pintype "input"))
      (node (ref "C380") (pin "1") (pinfunction "1_1") (pintype "input"))
      (node (ref "C381") (pin "1") (pinfunction "1_1") (pintype "input"))
      (node (ref "C382") (pin "1") (pinfunction "1_1") (pintype "input"))
      (node (ref "C383") (pin "1") (pinfunction "1_1") (pintype "input"))
      (node (ref "C392") (pin "1") (pinfunction "1_1") (pintype "input"))
      (node (ref "C393") (pin "1") (pinfunction "1_1") (pintype "input"))
      (node (ref "C400") (pin "1") (pinfunction "1_1") (pintype "input"))
      (node (ref "C402") (pin "1") (pinfunction "1_1") (pintype "input"))
      (node (ref "C73") (pin "1") (pinfunction "1_1") (pintype "input"))
      (node (ref "C78") (pin "1") (pinfunction "1_1") (pintype "input"))
      (node (ref "R14") (pin "2") (pinfunction "2_2") (pintype "input"))
      (node (ref "U2") (pin "G8") (pinfunction "VCCPINT_G8") (pintype "unspecified"))
      (node (ref "U2") (pin "H11") (pinfunction "VCCBRAM_H11") (pintype "unspecified"))
      (node (ref "U2") (pin "H9") (pinfunction "VCCPINT_H9") (pintype "unspecified"))
      (node (ref "U2") (pin "J10") (pinfunction "VCCBRAM_J10") (pintype "unspecified"))
      (node (ref "U2") (pin "J12") (pinfunction "VCCINT_J12") (pintype "unspecified"))
      (node (ref "U2") (pin "J14") (pinfunction "VCCINT_J14") (pintype "unspecified"))
      (node (ref "U2") (pin "J8") (pinfunction "VCCPINT_J8") (pintype "unspecified"))
      (node (ref "U2") (pin "K13") (pinfunction "VCCINT_K13") (pintype "unspecified"))
      (node (ref "U2") (pin "L14") (pinfunction "VCCINT_L14") (pintype "unspecified"))
      (node (ref "U2") (pin "L8") (pinfunction "VCCPINT_L8") (pintype "unspecified"))
      (node (ref "U2") (pin "M13") (pinfunction "VCCINT_M13") (pintype "unspecified"))
      (node (ref "U2") (pin "N14") (pinfunction "VCCINT_N14") (pintype "unspecified"))
      (node (ref "U2") (pin "N8") (pinfunction "VCCPINT_N8") (pintype "unspecified"))
      (node (ref "U2") (pin "P13") (pinfunction "VCCINT_P13") (pintype "unspecified"))
      (node (ref "U2") (pin "R14") (pinfunction "VCCINT_R14") (pintype "unspecified"))
      (node (ref "U2") (pin "R8") (pinfunction "VCCPINT_R8") (pintype "unspecified"))
      (node (ref "U37") (pin "2") (pinfunction "2_2") (pintype "input"))
    )
    (net (code "6") (name "1V0_EN") (class "Default")
      (node (ref "R13") (pin "1") (pinfunction "1_1") (pintype "input"))
      (node (ref "U10") (pin "1") (pinfunction "EN_1") (pintype "input"))
    )
    (net (code "7") (name "1V0_ETH") (class "Default")
      (node (ref "C170") (pin "1") (pinfunction "1_1") (pintype "input"))
      (node (ref "C366") (pin "1") (pinfunction "1_1") (pintype "input"))
      (node (ref "C367") (pin "1") (pinfunction "1_1") (pintype "input"))
      (node (ref "C368") (pin "1") (pinfunction "1_1") (pintype "input"))
      (node (ref "C374") (pin "1") (pinfunction "1_1") (pintype "input"))
      (node (ref "C379") (pin "1") (pinfunction "1_1") (pintype "input"))
      (node (ref "L11") (pin "2") (pinfunction "2_2") (pintype "input"))
      (node (ref "U35") (pin "21") (pinfunction "DVDD10_21") (pintype "unspecified"))
      (node (ref "U35") (pin "3") (pinfunction "AVDD10_3") (pintype "unspecified"))
      (node (ref "U35") (pin "38") (pinfunction "AVDD10_38") (pintype "unspecified"))
      (node (ref "U35") (pin "8") (pinfunction "AVDD10_8") (pintype "unspecified"))
    )
    (net (code "8") (name "1V0_FB") (class "Default")
      (node (ref "C29") (pin "1") (pinfunction "1_1") (pintype "input"))
      (node (ref "R14") (pin "1") (pinfunction "1_1") (pintype "input"))
      (node (ref "R15") (pin "1") (pinfunction "1_1") (pintype "input"))
      (node (ref "U10") (pin "2") (pinfunction "VFB_2") (pintype "input"))
    )
    (net (code "9") (name "1V8") (class "Default")
      (node (ref "C13") (pin "2") (pinfunction "2_2") (pintype "input"))
      (node (ref "C157") (pin "1") (pinfunction "1_1") (pintype "input"))
      (node (ref "C16") (pin "1") (pinfunction "1_1") (pintype "input"))
      (node (ref "C17") (pin "1") (pinfunction "1_1") (pintype "input"))
      (node (ref "C258") (pin "1") (pinfunction "1_1") (pintype "input"))
      (node (ref "C274") (pin "1") (pinfunction "1_1") (pintype "input"))
      (node (ref "C277") (pin "1") (pinfunction "1_1") (pintype "input"))
      (node (ref "C278") (pin "1") (pinfunction "1_1") (pintype "input"))
      (node (ref "C287") (pin "1") (pinfunction "1_1") (pintype "input"))
      (node (ref "C358") (pin "2") (pinfunction "2_2") (pintype "input"))
      (node (ref "C361") (pin "1") (pinfunction "1_1") (pintype "input"))
      (node (ref "C362") (pin "1") (pinfunction "1_1") (pintype "input"))
      (node (ref "C363") (pin "1") (pinfunction "1_1") (pintype "input"))
      (node (ref "C365") (pin "1") (pinfunction "1_1") (pintype "input"))
      (node (ref "C372") (pin "1") (pinfunction "1_1") (pintype "input"))
      (node (ref "C384") (pin "1") (pinfunction "1_1") (pintype "input"))
      (node (ref "C385") (pin "1") (pinfunction "1_1") (pintype "input"))
      (node (ref "C389") (pin "1") (pinfunction "1_1") (pintype "input"))
      (node (ref "C390") (pin "1") (pinfunction "1_1") (pintype "input"))
      (node (ref "C391") (pin "1") (pinfunction "1_1") (pintype "input"))
      (node (ref "C85") (pin "1") (pinfunction "1_1") (pintype "input"))
      (node (ref "L2") (pin "1") (pinfunction "1_1") (pintype "input"))
      (node (ref "L4") (pin "2") (pinfunction "2_2") (pintype "input"))
      (node (ref "L5") (pin "2") (pinfunction "2_2") (pintype "input"))
      (node (ref "R227") (pin "2") (pinfunction "2_2") (pintype "input"))
      (node (ref "R232") (pin "1") (pinfunction "1_1") (pintype "input"))
      (node (ref "R6") (pin "2") (pinfunction "2_2") (pintype "input"))
      (node (ref "R77") (pin "1") (pinfunction "1_1") (pintype "input"))
      (node (ref "R78") (pin "1") (pinfunction "1_1") (pintype "input"))
      (node (ref "U2") (pin "A10") (pinfunction "VCCO_MIO1_501_A10") (pintype "unspecified"))
      (node (ref "U2") (pin "B13") (pinfunction "VCCO_MIO1_501_B13") (pintype "unspecified"))
      (node (ref "U2") (pin "D9") (pinfunction "VCCO_MIO1_501_D9") (pintype "unspecified"))
      (node (ref "U2") (pin "E12") (pinfunction "VCCO_MIO1_501_E12") (pintype "unspecified"))
      (node (ref "U2") (pin "G9") (pinfunction "VCCBATT_0_G9") (pintype "unspecified"))
      (node (ref "U2") (pin "K9") (pinfunction "VCCPAUX_K9") (pintype "unspecified"))
      (node (ref "U2") (pin "L10") (pinfunction "VCCAUX_L10") (pintype "unspecified"))
      (node (ref "U2") (pin "M9") (pinfunction "VCCPAUX_M9") (pintype "unspecified"))
      (node (ref "U2") (pin "N10") (pinfunction "VCCAUX_N10") (pintype "unspecified"))
      (node (ref "U2") (pin "P11") (pinfunction "VCCAUX_P11") (pintype "unspecified"))
      (node (ref "U2") (pin "P9") (pinfunction "VCCPAUX_P9") (pintype "unspecified"))
      (node (ref "U2") (pin "R10") (pinfunction "VCCAUX_R10") (pintype "unspecified"))
      (node (ref "U2") (pin "T9") (pinfunction "VCCPAUX_T9") (pintype "unspecified"))
      (node (ref "U36") (pin "14") (pinfunction "REFSEL2_14") (pintype "input"))
      (node (ref "U36") (pin "28") (pinfunction "VDD18_28") (pintype "input"))
      (node (ref "U36") (pin "30") (pinfunction "VDD18_30") (pintype "input"))
      (node (ref "U36") (pin "32") (pinfunction "VDDIO_32") (pintype "input"))
      (node (ref "U38") (pin "2") (pinfunction "2_2") (pintype "input"))
      (node (ref "U72") (pin "1") (pinfunction "Tri-state_1") (pintype "input"))
      (node (ref "U72") (pin "4") (pinfunction "Vdd_4") (pintype "input"))
      (node (ref "U74") (pin "5") (pinfunction "VCCA_5") (pintype "unspecified"))
    )
    (net (code "10") (name "1V8ADC") (class "Default")
      (node (ref "C302") (pin "1") (pinfunction "1_1") (pintype "input"))
      (node (ref "C303") (pin "1") (pinfunction "1_1") (pintype "input"))
      (node (ref "C404") (pin "1") (pinfunction "1_1") (pintype "input"))
      (node (ref "L2") (pin "2") (pinfunction "2_2") (pintype "input"))
      (node (ref "U2") (pin "K11") (pinfunction "VCCADC_0_K11") (pintype "unspecified"))
    )
    (net (code "11") (name "1V8_ETH") (class "Default")
      (node (ref "C155") (pin "1") (pinfunction "1_1") (pintype "input"))
      (node (ref "C369") (pin "1") (pinfunction "1_1") (pintype "input"))
      (node (ref "C371") (pin "1") (pinfunction "1_1") (pintype "input"))
      (node (ref "C373") (pin "1") (pinfunction "1_1") (pintype "input"))
      (node (ref "L5") (pin "1") (pinfunction "1_1") (pintype "input"))
      (node (ref "R245") (pin "1") (pinfunction "1_1") (pintype "input"))
      (node (ref "R246") (pin "1") (pinfunction "1_1") (pintype "input"))
      (node (ref "R251") (pin "1") (pinfunction "1_1") (pintype "input"))
      (node (ref "R252") (pin "1") (pinfunction "1_1") (pintype "input"))
      (node (ref "R253") (pin "1") (pinfunction "1_1") (pintype "input"))
      (node (ref "R254") (pin "1") (pinfunction "1_1") (pintype "input"))
      (node (ref "U35") (pin "28") (pinfunction "DVDD_RG_28") (pintype "unspecified"))
      (node (ref "U70") (pin "1") (pinfunction "Tri-state_1") (pintype "unspecified"))
      (node (ref "U70") (pin "4") (pinfunction "Vdd_4") (pintype "unspecified"))
    )
    (net (code "12") (name "1V8_FTDI") (class "Default")
      (node (ref "C184") (pin "1") (pinfunction "1_1") (pintype "input"))
      (node (ref "C351") (pin "1") (pinfunction "1_1") (pintype "input"))
      (node (ref "C352") (pin "1") (pinfunction "1_1") (pintype "input"))
      (node (ref "C353") (pin "1") (pinfunction "1_1") (pintype "input"))
      (node (ref "U34") (pin "12") (pinfunction "VCORE_12") (pintype "input"))
      (node (ref "U34") (pin "37") (pinfunction "VCORE_37") (pintype "input"))
      (node (ref "U34") (pin "49") (pinfunction "VREGOUT_49") (pintype "input"))
      (node (ref "U34") (pin "64") (pinfunction "VCORE_64") (pintype "input"))
    )
    (net (code "13") (name "1V35") (class "Default")
      (node (ref "C100") (pin "1") (pinfunction "1_1") (pintype "input"))
      (node (ref "C101") (pin "1") (pinfunction "1_1") (pintype "input"))
      (node (ref "C102") (pin "1") (pinfunction "1_1") (pintype "input"))
      (node (ref "C103") (pin "1") (pinfunction "1_1") (pintype "input"))
      (node (ref "C21") (pin "2") (pinfunction "2_2") (pintype "input"))
      (node (ref "C218") (pin "1") (pinfunction "1_1") (pintype "input"))
      (node (ref "C24") (pin "1") (pinfunction "1_1") (pintype "input"))
      (node (ref "C25") (pin "1") (pinfunction "1_1") (pintype "input"))
      (node (ref "C280") (pin "1") (pinfunction "1_1") (pintype "input"))
      (node (ref "C284") (pin "1") (pinfunction "1_1") (pintype "input"))
      (node (ref "C285") (pin "1") (pinfunction "1_1") (pintype "input"))
      (node (ref "C286") (pin "1") (pinfunction "1_1") (pintype "input"))
      (node (ref "C288") (pin "1") (pinfunction "1_1") (pintype "input"))
      (node (ref "C35") (pin "1") (pinfunction "1_1") (pintype "input"))
      (node (ref "C403") (pin "1") (pinfunction "1_1") (pintype "input"))
      (node (ref "C46") (pin "1") (pinfunction "1_1") (pintype "input"))
      (node (ref "C47") (pin "1") (pinfunction "1_1") (pintype "input"))
      (node (ref "C48") (pin "1") (pinfunction "1_1") (pintype "input"))
      (node (ref "C50") (pin "1") (pinfunction "1_1") (pintype "input"))
      (node (ref "C51") (pin "1") (pinfunction "1_1") (pintype "input"))
      (node (ref "C53") (pin "1") (pinfunction "1_1") (pintype "input"))
      (node (ref "C54") (pin "1") (pinfunction "1_1") (pintype "input"))
      (node (ref "C56") (pin "1") (pinfunction "1_1") (pintype "input"))
      (node (ref "C57") (pin "1") (pinfunction "1_1") (pintype "input"))
      (node (ref "C59") (pin "1") (pinfunction "1_1") (pintype "input"))
      (node (ref "C6") (pin "1") (pinfunction "1_1") (pintype "input"))
      (node (ref "C60") (pin "1") (pinfunction "1_1") (pintype "input"))
      (node (ref "C61") (pin "1") (pinfunction "1_1") (pintype "input"))
      (node (ref "C63") (pin "1") (pinfunction "1_1") (pintype "input"))
      (node (ref "C64") (pin "1") (pinfunction "1_1") (pintype "input"))
      (node (ref "C66") (pin "1") (pinfunction "1_1") (pintype "input"))
      (node (ref "C67") (pin "1") (pinfunction "1_1") (pintype "input"))
      (node (ref "C68") (pin "1") (pinfunction "1_1") (pintype "input"))
      (node (ref "C69") (pin "1") (pinfunction "1_1") (pintype "input"))
      (node (ref "C70") (pin "1") (pinfunction "1_1") (pintype "input"))
      (node (ref "C71") (pin "1") (pinfunction "1_1") (pintype "input"))
      (node (ref "C77") (pin "1") (pinfunction "1_1") (pintype "input"))
      (node (ref "C79") (pin "1") (pinfunction "1_1") (pintype "input"))
      (node (ref "C80") (pin "1") (pinfunction "1_1") (pintype "input"))
      (node (ref "C81") (pin "1") (pinfunction "1_1") (pintype "input"))
      (node (ref "C82") (pin "1") (pinfunction "1_1") (pintype "input"))
      (node (ref "C84") (pin "1") (pinfunction "1_1") (pintype "input"))
      (node (ref "C86") (pin "1") (pinfunction "1_1") (pintype "input"))
      (node (ref "C87") (pin "1") (pinfunction "1_1") (pintype "input"))
      (node (ref "C88") (pin "1") (pinfunction "1_1") (pintype "input"))
      (node (ref "C89") (pin "1") (pinfunction "1_1") (pintype "input"))
      (node (ref "C94") (pin "1") (pinfunction "1_1") (pintype "input"))
      (node (ref "C95") (pin "1") (pinfunction "1_1") (pintype "input"))
      (node (ref "C96") (pin "1") (pinfunction "1_1") (pintype "input"))
      (node (ref "C97") (pin "1") (pinfunction "1_1") (pintype "input"))
      (node (ref "C98") (pin "1") (pinfunction "1_1") (pintype "input"))
      (node (ref "C99") (pin "1") (pinfunction "1_1") (pintype "input"))
      (node (ref "R10") (pin "2") (pinfunction "2_2") (pintype "input"))
      (node (ref "R130") (pin "2") (pinfunction "2_2") (pintype "input"))
      (node (ref "R64") (pin "2") (pinfunction "2_2") (pintype "input"))
      (node (ref "U1") (pin "A1") (pinfunction "VDDQ_A1") (pintype "input"))
      (node (ref "U1") (pin "A8") (pinfunction "VDDQ_A8") (pintype "input"))
      (node (ref "U1") (pin "B2") (pinfunction "VDD_B2") (pintype "input"))
      (node (ref "U1") (pin "C1") (pinfunction "VDDQ_C1") (pintype "input"))
      (node (ref "U1") (pin "C9") (pinfunction "VDDQ_C9") (pintype "input"))
      (node (ref "U1") (pin "D2") (pinfunction "VDDQ_D2") (pintype "input"))
      (node (ref "U1") (pin "D9") (pinfunction "VDD_D9") (pintype "input"))
      (node (ref "U1") (pin "E9") (pinfunction "VDDQ_E9") (pintype "input"))
      (node (ref "U1") (pin "F1") (pinfunction "VDDQ_F1") (pintype "input"))
      (node (ref "U1") (pin "G7") (pinfunction "VDD_G7") (pintype "input"))
      (node (ref "U1") (pin "H2") (pinfunction "VDDQ_H2") (pintype "input"))
      (node (ref "U1") (pin "H9") (pinfunction "VDDQ_H9") (pintype "input"))
      (node (ref "U1") (pin "K2") (pinfunction "VDD_K2") (pintype "input"))
      (node (ref "U1") (pin "K8") (pinfunction "VDD_K8") (pintype "input"))
      (node (ref "U1") (pin "N1") (pinfunction "VDD_N1") (pintype "input"))
      (node (ref "U1") (pin "N9") (pinfunction "VDD_N9") (pintype "input"))
      (node (ref "U1") (pin "R1") (pinfunction "VDD_R1") (pintype "input"))
      (node (ref "U1") (pin "R9") (pinfunction "VDD_R9") (pintype "input"))
      (node (ref "U2") (pin "E2") (pinfunction "VCCO_DDR_502_E2") (pintype "unspecified"))
      (node (ref "U2") (pin "F5") (pinfunction "VCCO_DDR_502_F5") (pintype "unspecified"))
      (node (ref "U2") (pin "H1") (pinfunction "VCCO_DDR_502_H1") (pintype "unspecified"))
      (node (ref "U2") (pin "J4") (pinfunction "VCCO_DDR_502_J4") (pintype "unspecified"))
      (node (ref "U2") (pin "K7") (pinfunction "VCCO_DDR_502_K7") (pintype "unspecified"))
      (node (ref "U2") (pin "M3") (pinfunction "VCCO_DDR_502_M3") (pintype "unspecified"))
      (node (ref "U2") (pin "N6") (pinfunction "VCCO_DDR_502_N6") (pintype "unspecified"))
      (node (ref "U2") (pin "R2") (pinfunction "VCCO_DDR_502_R2") (pintype "unspecified"))
      (node (ref "U2") (pin "V1") (pinfunction "VCCO_DDR_502_V1") (pintype "unspecified"))
      (node (ref "U3") (pin "A1") (pinfunction "VDDQ_A1") (pintype "input"))
      (node (ref "U3") (pin "A8") (pinfunction "VDDQ_A8") (pintype "input"))
      (node (ref "U3") (pin "B2") (pinfunction "VDD_B2") (pintype "input"))
      (node (ref "U3") (pin "C1") (pinfunction "VDDQ_C1") (pintype "input"))
      (node (ref "U3") (pin "C9") (pinfunction "VDDQ_C9") (pintype "input"))
      (node (ref "U3") (pin "D2") (pinfunction "VDDQ_D2") (pintype "input"))
      (node (ref "U3") (pin "D9") (pinfunction "VDD_D9") (pintype "input"))
      (node (ref "U3") (pin "E9") (pinfunction "VDDQ_E9") (pintype "input"))
      (node (ref "U3") (pin "F1") (pinfunction "VDDQ_F1") (pintype "input"))
      (node (ref "U3") (pin "G7") (pinfunction "VDD_G7") (pintype "input"))
      (node (ref "U3") (pin "H2") (pinfunction "VDDQ_H2") (pintype "input"))
      (node (ref "U3") (pin "H9") (pinfunction "VDDQ_H9") (pintype "input"))
      (node (ref "U3") (pin "K2") (pinfunction "VDD_K2") (pintype "input"))
      (node (ref "U3") (pin "K8") (pinfunction "VDD_K8") (pintype "input"))
      (node (ref "U3") (pin "N1") (pinfunction "VDD_N1") (pintype "input"))
      (node (ref "U3") (pin "N9") (pinfunction "VDD_N9") (pintype "input"))
      (node (ref "U3") (pin "R1") (pinfunction "VDD_R1") (pintype "input"))
      (node (ref "U3") (pin "R9") (pinfunction "VDD_R9") (pintype "input"))
      (node (ref "U39") (pin "2") (pinfunction "2_2") (pintype "input"))
    )
    (net (code "14") (name "1V35_EN") (class "Default")
      (node (ref "R9") (pin "1") (pinfunction "1_1") (pintype "input"))
      (node (ref "U8") (pin "1") (pinfunction "EN_1") (pintype "input"))
    )
    (net (code "15") (name "1V35_SW") (class "Default")
      (node (ref "C23") (pin "2") (pinfunction "2_2") (pintype "input"))
      (node (ref "U39") (pin "1") (pinfunction "1_1") (pintype "input"))
      (node (ref "U8") (pin "6") (pinfunction "SW_6") (pintype "input"))
    )
    (net (code "16") (name "1V35_VBST") (class "Default")
      (node (ref "C23") (pin "1") (pinfunction "1_1") (pintype "input"))
      (node (ref "U8") (pin "7") (pinfunction "VBST_7") (pintype "input"))
    )
    (net (code "17") (name "1V35_VFB") (class "Default")
      (node (ref "C21") (pin "1") (pinfunction "1_1") (pintype "input"))
      (node (ref "R10") (pin "1") (pinfunction "1_1") (pintype "input"))
      (node (ref "R11") (pin "1") (pinfunction "1_1") (pintype "input"))
      (node (ref "U8") (pin "2") (pinfunction "VFB_2") (pintype "input"))
    )
    (net (code "18") (name "1V35_VREG5") (class "Default")
      (node (ref "C22") (pin "1") (pinfunction "1_1") (pintype "input"))
      (node (ref "R12") (pin "1") (pinfunction "1_1") (pintype "input"))
      (node (ref "U8") (pin "3") (pinfunction "VREG5_3") (pintype "input"))
    )
    (net (code "19") (name "3V3") (class "Default")
      (node (ref "C144") (pin "1") (pinfunction "1_1") (pintype "input"))
      (node (ref "C159") (pin "1") (pinfunction "1_1") (pintype "input"))
      (node (ref "C168") (pin "1") (pinfunction "1_1") (pintype "input"))
      (node (ref "C176") (pin "1") (pinfunction "1_1") (pintype "input"))
      (node (ref "C183") (pin "1") (pinfunction "1_1") (pintype "input"))
      (node (ref "C190") (pin "1") (pinfunction "1_1") (pintype "input"))
      (node (ref "C191") (pin "1") (pinfunction "1_1") (pintype "input"))
      (node (ref "C192") (pin "1") (pinfunction "1_1") (pintype "input"))
      (node (ref "C193") (pin "1") (pinfunction "1_1") (pintype "input"))
      (node (ref "C241") (pin "2") (pinfunction "2_2") (pintype "input"))
      (node (ref "C257") (pin "1") (pinfunction "1_1") (pintype "input"))
      (node (ref "C259") (pin "1") (pinfunction "1_1") (pintype "input"))
      (node (ref "C261") (pin "1") (pinfunction "1_1") (pintype "input"))
      (node (ref "C262") (pin "1") (pinfunction "1_1") (pintype "input"))
      (node (ref "C263") (pin "1") (pinfunction "1_1") (pintype "input"))
      (node (ref "C264") (pin "1") (pinfunction "1_1") (pintype "input"))
      (node (ref "C265") (pin "1") (pinfunction "1_1") (pintype "input"))
      (node (ref "C268") (pin "1") (pinfunction "1_1") (pintype "input"))
      (node (ref "C290") (pin "1") (pinfunction "1_1") (pintype "input"))
      (node (ref "C291") (pin "1") (pinfunction "1_1") (pintype "input"))
      (node (ref "C293") (pin "1") (pinfunction "1_1") (pintype "input"))
      (node (ref "C294") (pin "1") (pinfunction "1_1") (pintype "input"))
      (node (ref "C295") (pin "1") (pinfunction "1_1") (pintype "input"))
      (node (ref "C354") (pin "1") (pinfunction "1_1") (pintype "input"))
      (node (ref "C355") (pin "1") (pinfunction "1_1") (pintype "input"))
      (node (ref "C356") (pin "1") (pinfunction "1_1") (pintype "input"))
      (node (ref "C357") (pin "1") (pinfunction "1_1") (pintype "input"))
      (node (ref "C359") (pin "1") (pinfunction "1_1") (pintype "input"))
      (node (ref "C360") (pin "1") (pinfunction "1_1") (pintype "input"))
      (node (ref "C364") (pin "1") (pinfunction "1_1") (pintype "input"))
      (node (ref "C370") (pin "1") (pinfunction "1_1") (pintype "input"))
      (node (ref "C378") (pin "1") (pinfunction "1_1") (pintype "input"))
      (node (ref "C386") (pin "1") (pinfunction "1_1") (pintype "input"))
      (node (ref "C387") (pin "1") (pinfunction "1_1") (pintype "input"))
      (node (ref "C388") (pin "1") (pinfunction "1_1") (pintype "input"))
      (node (ref "C394") (pin "1") (pinfunction "1_1") (pintype "input"))
      (node (ref "C395") (pin "1") (pinfunction "1_1") (pintype "input"))
      (node (ref "C396") (pin "1") (pinfunction "1_1") (pintype "input"))
      (node (ref "C397") (pin "1") (pinfunction "1_1") (pintype "input"))
      (node (ref "C398") (pin "1") (pinfunction "1_1") (pintype "input"))
      (node (ref "C399") (pin "1") (pinfunction "1_1") (pintype "input"))
      (node (ref "C4") (pin "2") (pinfunction "2_2") (pintype "input"))
      (node (ref "C401") (pin "1") (pinfunction "1_1") (pintype "input"))
      (node (ref "C42") (pin "1") (pinfunction "1_1") (pintype "input"))
      (node (ref "C45") (pin "1") (pinfunction "1_1") (pintype "input"))
      (node (ref "C49") (pin "1") (pinfunction "1_1") (pintype "input"))
      (node (ref "C52") (pin "1") (pinfunction "1_1") (pintype "input"))
      (node (ref "C55") (pin "1") (pinfunction "1_1") (pintype "input"))
      (node (ref "C58") (pin "1") (pinfunction "1_1") (pintype "input"))
      (node (ref "C62") (pin "1") (pinfunction "1_1") (pintype "input"))
      (node (ref "C65") (pin "1") (pinfunction "1_1") (pintype "input"))
      (node (ref "C8") (pin "1") (pinfunction "1_1") (pintype "input"))
      (node (ref "C83") (pin "1") (pinfunction "1_1") (pintype "input"))
      (node (ref "C9") (pin "1") (pinfunction "1_1") (pintype "input"))
      (node (ref "CARD2") (pin "4") (pinfunction "VDD_4") (pintype "unspecified"))
      (node (ref "HDR1") (pin "2") (pinfunction "VCC_2") (pintype "input"))
      (node (ref "L10") (pin "1") (pinfunction "1_1") (pintype "input"))
      (node (ref "L6") (pin "2") (pinfunction "2_2") (pintype "input"))
      (node (ref "L8") (pin "1") (pinfunction "1_1") (pintype "input"))
      (node (ref "R1") (pin "2") (pinfunction "2_2") (pintype "input"))
      (node (ref "R176") (pin "2") (pinfunction "2_2") (pintype "input"))
      (node (ref "R185") (pin "2") (pinfunction "2_2") (pintype "input"))
      (node (ref "R186") (pin "2") (pinfunction "2_2") (pintype "input"))
      (node (ref "R187") (pin "2") (pinfunction "2_2") (pintype "input"))
      (node (ref "R188") (pin "2") (pinfunction "2_2") (pintype "input"))
      (node (ref "R189") (pin "2") (pinfunction "2_2") (pintype "input"))
      (node (ref "R190") (pin "2") (pinfunction "2_2") (pintype "input"))
      (node (ref "R191") (pin "2") (pinfunction "2_2") (pintype "input"))
      (node (ref "R192") (pin "2") (pinfunction "2_2") (pintype "input"))
      (node (ref "R224") (pin "2") (pinfunction "2_2") (pintype "input"))
      (node (ref "R225") (pin "2") (pinfunction "2_2") (pintype "input"))
      (node (ref "R229") (pin "2") (pinfunction "2_2") (pintype "input"))
      (node (ref "R240") (pin "1") (pinfunction "1_1") (pintype "input"))
      (node (ref "R241") (pin "1") (pinfunction "1_1") (pintype "input"))
      (node (ref "R268") (pin "2") (pinfunction "2_2") (pintype "input"))
      (node (ref "R273") (pin "1") (pinfunction "1_1") (pintype "input"))
      (node (ref "R276") (pin "1") (pinfunction "1_1") (pintype "input"))
      (node (ref "R278") (pin "1") (pinfunction "1_1") (pintype "input"))
      (node (ref "R279") (pin "1") (pinfunction "1_1") (pintype "input"))
      (node (ref "R46") (pin "2") (pinfunction "2_2") (pintype "input"))
      (node (ref "R47") (pin "2") (pinfunction "2_2") (pintype "input"))
      (node (ref "R48") (pin "2") (pinfunction "2_2") (pintype "input"))
      (node (ref "R49") (pin "2") (pinfunction "2_2") (pintype "input"))
      (node (ref "R50") (pin "2") (pinfunction "2_2") (pintype "input"))
      (node (ref "R51") (pin "2") (pinfunction "2_2") (pintype "input"))
      (node (ref "R73") (pin "1") (pinfunction "1_1") (pintype "input"))
      (node (ref "R76") (pin "1") (pinfunction "1_1") (pintype "input"))
      (node (ref "R84") (pin "1") (pinfunction "1_1") (pintype "input"))
      (node (ref "RJ1") (pin "11") (pinfunction "11_11") (pintype "unspecified"))
      (node (ref "RJ1") (pin "14") (pinfunction "14_14") (pintype "unspecified"))
      (node (ref "SW4") (pin "4") (pinfunction "4_4") (pintype "input"))
      (node (ref "SW4") (pin "5") (pinfunction "5_5") (pintype "input"))
      (node (ref "SW4") (pin "6") (pinfunction "6_6") (pintype "input"))
      (node (ref "U2") (pin "A20") (pinfunction "VCCO_35_A20") (pintype "unspecified"))
      (node (ref "U2") (pin "AA10") (pinfunction "VCCO_13_AA10") (pintype "unspecified"))
      (node (ref "U2") (pin "AA20") (pinfunction "VCCO_33_AA20") (pintype "unspecified"))
      (node (ref "U2") (pin "AB13") (pinfunction "VCCO_33_AB13") (pintype "unspecified"))
      (node (ref "U2") (pin "AB3") (pinfunction "VCCO_13_AB3") (pintype "unspecified"))
      (node (ref "U2") (pin "B3") (pinfunction "VCCO_MIO0_500_B3") (pintype "unspecified"))
      (node (ref "U2") (pin "C16") (pinfunction "VCCO_35_C16") (pintype "unspecified"))
      (node (ref "U2") (pin "C6") (pinfunction "VCCO_MIO0_500_C6") (pintype "unspecified"))
      (node (ref "U2") (pin "D19") (pinfunction "VCCO_35_D19") (pintype "unspecified"))
      (node (ref "U2") (pin "E22") (pinfunction "VCCO_35_E22") (pintype "unspecified"))
      (node (ref "U2") (pin "F15") (pinfunction "VCCO_35_F15") (pintype "unspecified"))
      (node (ref "U2") (pin "G18") (pinfunction "VCCO_35_G18") (pintype "unspecified"))
      (node (ref "U2") (pin "H21") (pinfunction "VCCO_35_H21") (pintype "unspecified"))
      (node (ref "U2") (pin "K17") (pinfunction "VCCO_34_K17") (pintype "unspecified"))
      (node (ref "U2") (pin "L20") (pinfunction "VCCO_34_L20") (pintype "unspecified"))
      (node (ref "U2") (pin "N16") (pinfunction "VCCO_34_N16") (pintype "unspecified"))
      (node (ref "U2") (pin "P19") (pinfunction "VCCO_34_P19") (pintype "unspecified"))
      (node (ref "U2") (pin "R12") (pinfunction "VCCO_0_R12") (pintype "unspecified"))
      (node (ref "U2") (pin "R22") (pinfunction "VCCO_34_R22") (pintype "unspecified"))
      (node (ref "U2") (pin "T10") (pinfunction "RSVDVCC3_T10") (pintype "unspecified"))
      (node (ref "U2") (pin "T13") (pinfunction "CFGBVS_0_T13") (pintype "input"))
      (node (ref "U2") (pin "T15") (pinfunction "VCCO_34_T15") (pintype "unspecified"))
      (node (ref "U2") (pin "T5") (pinfunction "VCCO_13_T5") (pintype "unspecified"))
      (node (ref "U2") (pin "T7") (pinfunction "RSVDVCC1_T7") (pintype "unspecified"))
      (node (ref "U2") (pin "T8") (pinfunction "RSVDVCC2_T8") (pintype "unspecified"))
      (node (ref "U2") (pin "U18") (pinfunction "VCCO_33_U18") (pintype "unspecified"))
      (node (ref "U2") (pin "U8") (pinfunction "VCCO_13_U8") (pintype "unspecified"))
      (node (ref "U2") (pin "V11") (pinfunction "VCCO_13_V11") (pintype "unspecified"))
      (node (ref "U2") (pin "V21") (pinfunction "VCCO_33_V21") (pintype "unspecified"))
      (node (ref "U2") (pin "W14") (pinfunction "VCCO_33_W14") (pintype "unspecified"))
      (node (ref "U2") (pin "W4") (pinfunction "VCCO_13_W4") (pintype "unspecified"))
      (node (ref "U2") (pin "Y17") (pinfunction "VCCO_33_Y17") (pintype "unspecified"))
      (node (ref "U2") (pin "Y7") (pinfunction "VCCO_13_Y7") (pintype "unspecified"))
      (node (ref "U34") (pin "20") (pinfunction "VCCIO_20") (pintype "input"))
      (node (ref "U34") (pin "21") (pinfunction "ADBUS4_21") (pintype "bidirectional"))
      (node (ref "U34") (pin "31") (pinfunction "VCCIO_31") (pintype "input"))
      (node (ref "U34") (pin "42") (pinfunction "VCCIO_42") (pintype "input"))
      (node (ref "U34") (pin "50") (pinfunction "VREGIN_50") (pintype "input"))
      (node (ref "U34") (pin "56") (pinfunction "VCCIO_56") (pintype "input"))
      (node (ref "U35") (pin "29") (pinfunction "DVDD33_29") (pintype "unspecified"))
      (node (ref "U36") (pin "20") (pinfunction "VDD33_20") (pintype "input"))
      (node (ref "U36") (pin "21") (pinfunction "VBAT_21") (pintype "input"))
      (node (ref "U40") (pin "2") (pinfunction "2_2") (pintype "input"))
      (node (ref "U44") (pin "29") (pinfunction "29_29") (pintype "input"))
      (node (ref "U44") (pin "30") (pinfunction "30_30") (pintype "input"))
      (node (ref "U44") (pin "31") (pinfunction "31_31") (pintype "input"))
      (node (ref "U44") (pin "32") (pinfunction "32_32") (pintype "input"))
      (node (ref "U44") (pin "64") (pinfunction "64_64") (pintype "input"))
      (node (ref "U44") (pin "65") (pinfunction "65_65") (pintype "input"))
      (node (ref "U44") (pin "66") (pinfunction "66_66") (pintype "input"))
      (node (ref "U45") (pin "32") (pinfunction "32_32") (pintype "input"))
      (node (ref "U45") (pin "33") (pinfunction "33_33") (pintype "input"))
      (node (ref "U45") (pin "66") (pinfunction "66_66") (pintype "input"))
      (node (ref "U45") (pin "67") (pinfunction "67_67") (pintype "input"))
      (node (ref "U60") (pin "8") (pinfunction "VCC_8") (pintype "input"))
      (node (ref "U61") (pin "5") (pinfunction "VCC_5") (pintype "input"))
      (node (ref "U63") (pin "8") (pinfunction "VCC_8") (pintype "unspecified"))
      (node (ref "U74") (pin "17") (pinfunction "VCCB1_17") (pintype "unspecified"))
      (node (ref "U74") (pin "21") (pinfunction "VCCB0_21") (pintype "unspecified"))
      (node (ref "U78") (pin "24") (pinfunction "VCCA_24") (pintype "unspecified"))
      (node (ref "X1") (pin "1") (pinfunction "Tri-state_1") (pintype "input"))
      (node (ref "X1") (pin "4") (pinfunction "Vdd_4") (pintype "input"))
      (node (ref "X2") (pin "1") (pinfunction "Tri-state_1") (pintype "input"))
      (node (ref "X2") (pin "4") (pinfunction "Vdd_4") (pintype "input"))
    )
    (net (code "20") (name "3V3_ETH") (class "Default")
      (node (ref "C166") (pin "1") (pinfunction "1_1") (pintype "input"))
      (node (ref "C375") (pin "1") (pinfunction "1_1") (pintype "input"))
      (node (ref "C376") (pin "1") (pinfunction "1_1") (pintype "input"))
      (node (ref "C377") (pin "1") (pinfunction "1_1") (pintype "input"))
      (node (ref "L6") (pin "1") (pinfunction "1_1") (pintype "input"))
      (node (ref "U35") (pin "11") (pinfunction "AVDD33_11") (pintype "unspecified"))
      (node (ref "U35") (pin "40") (pinfunction "AVDD33_40") (pintype "unspecified"))
    )
    (net (code "21") (name "5V0") (class "Default")
      (node (ref "C1") (pin "1") (pinfunction "1_1") (pintype "input"))
      (node (ref "C10") (pin "1") (pinfunction "1_1") (pintype "input"))
      (node (ref "C11") (pin "1") (pinfunction "1_1") (pintype "input"))
      (node (ref "C12") (pin "1") (pinfunction "1_1") (pintype "input"))
      (node (ref "C18") (pin "1") (pinfunction "1_1") (pintype "input"))
      (node (ref "C19") (pin "1") (pinfunction "1_1") (pintype "input"))
      (node (ref "C2") (pin "1") (pinfunction "1_1") (pintype "input"))
      (node (ref "C20") (pin "1") (pinfunction "1_1") (pintype "input"))
      (node (ref "C217") (pin "1") (pinfunction "1_1") (pintype "input"))
      (node (ref "C219") (pin "1") (pinfunction "1_1") (pintype "input"))
      (node (ref "C229") (pin "1") (pinfunction "1_1") (pintype "input"))
      (node (ref "C240") (pin "2") (pinfunction "2_2") (pintype "input"))
      (node (ref "C26") (pin "1") (pinfunction "1_1") (pintype "input"))
      (node (ref "C27") (pin "1") (pinfunction "1_1") (pintype "input"))
      (node (ref "C28") (pin "1") (pinfunction "1_1") (pintype "input"))
      (node (ref "C3") (pin "1") (pinfunction "1_1") (pintype "input"))
      (node (ref "D8") (pin "1") (pinfunction "K_1") (pintype "input"))
      (node (ref "H2") (pin "2") (pinfunction "2_2") (pintype "input"))
      (node (ref "H3") (pin "2") (pinfunction "2_2") (pintype "input"))
      (node (ref "H4") (pin "1") (pinfunction "1_1") (pintype "input"))
      (node (ref "R126") (pin "2") (pinfunction "2_2") (pintype "input"))
      (node (ref "R128") (pin "2") (pinfunction "2_2") (pintype "input"))
      (node (ref "R13") (pin "2") (pinfunction "2_2") (pintype "input"))
      (node (ref "R37") (pin "2") (pinfunction "2_2") (pintype "input"))
      (node (ref "R39") (pin "2") (pinfunction "2_2") (pintype "input"))
      (node (ref "R40") (pin "2") (pinfunction "2_2") (pintype "input"))
      (node (ref "R42") (pin "2") (pinfunction "2_2") (pintype "input"))
      (node (ref "R52") (pin "2") (pinfunction "2_2") (pintype "input"))
      (node (ref "R80") (pin "2") (pinfunction "2_2") (pintype "input"))
      (node (ref "U10") (pin "8") (pinfunction "VIN_8") (pintype "input"))
      (node (ref "U4") (pin "8") (pinfunction "VIN_8") (pintype "input"))
      (node (ref "U6") (pin "8") (pinfunction "VIN_8") (pintype "input"))
      (node (ref "U68") (pin "6") (pinfunction "VCC_6") (pintype "input"))
      (node (ref "U68") (pin "7") (pinfunction "VTT_IN_7") (pintype "input"))
      (node (ref "U73") (pin "6") (pinfunction "VIN_6") (pintype "input"))
      (node (ref "U78") (pin "11") (pinfunction "VCC5V_11") (pintype "unspecified"))
      (node (ref "U79") (pin "1") (pinfunction "1_1") (pintype "input"))
      (node (ref "U8") (pin "8") (pinfunction "VIN_8") (pintype "input"))
      (node (ref "U80") (pin "1") (pinfunction "1_1") (pintype "input"))
    )
    (net (code "22") (name "5V0EXT") (class "Default")
      (node (ref "F2") (pin "2") (pinfunction "2_2") (pintype "input"))
      (node (ref "H2") (pin "1") (pinfunction "1_1") (pintype "input"))
      (node (ref "H3") (pin "1") (pinfunction "1_1") (pintype "input"))
    )
    (net (code "23") (name "5V0_USB_AB") (class "Default")
      (node (ref "C228") (pin "1") (pinfunction "1_1") (pintype "input"))
      (node (ref "L12") (pin "2") (pinfunction "2_2") (pintype "input"))
      (node (ref "USB1") (pin "1") (pinfunction "VBUS_1") (pintype "unspecified"))
    )
    (net (code "24") (name "5V0_USB_SW") (class "Default")
      (node (ref "C230") (pin "1") (pinfunction "1_1") (pintype "input"))
      (node (ref "D12") (pin "2") (pinfunction "A_2") (pintype "input"))
      (node (ref "U73") (pin "1") (pinfunction "VOUT_1") (pintype "input"))
    )
    (net (code "25") (name "AGND") (class "Default")
      (node (ref "C302") (pin "2") (pinfunction "2_2") (pintype "input"))
      (node (ref "C303") (pin "2") (pinfunction "2_2") (pintype "input"))
      (node (ref "C404") (pin "2") (pinfunction "2_2") (pintype "input"))
      (node (ref "L3") (pin "2") (pinfunction "2_2") (pintype "input"))
      (node (ref "U2") (pin "K12") (pinfunction "GNDADC_0_K12") (pintype "unspecified"))
    )
    (net (code "26") (name "BM_M0") (class "Default")
      (node (ref "R88") (pin "1") (pinfunction "1_1") (pintype "input"))
      (node (ref "R91") (pin "1") (pinfunction "1_1") (pintype "input"))
      (node (ref "SW4") (pin "1") (pinfunction "1_1") (pintype "input"))
    )
    (net (code "27") (name "BM_M1") (class "Default")
      (node (ref "R89") (pin "1") (pinfunction "1_1") (pintype "input"))
      (node (ref "R92") (pin "1") (pinfunction "1_1") (pintype "input"))
      (node (ref "SW4") (pin "2") (pinfunction "2_2") (pintype "input"))
    )
    (net (code "28") (name "BM_M2") (class "Default")
      (node (ref "R90") (pin "1") (pinfunction "1_1") (pintype "input"))
      (node (ref "R93") (pin "1") (pinfunction "1_1") (pintype "input"))
      (node (ref "SW4") (pin "3") (pinfunction "3_3") (pintype "input"))
    )
    (net (code "29") (name "BM_M3") (class "Default")
      (node (ref "R272") (pin "1") (pinfunction "1_1") (pintype "input"))
      (node (ref "R273") (pin "2") (pinfunction "2_2") (pintype "input"))
      (node (ref "R274") (pin "1") (pinfunction "1_1") (pintype "input"))
    )
    (net (code "30") (name "BM_M4") (class "Default")
      (node (ref "R275") (pin "1") (pinfunction "1_1") (pintype "input"))
      (node (ref "R276") (pin "2") (pinfunction "2_2") (pintype "input"))
      (node (ref "R277") (pin "1") (pinfunction "1_1") (pintype "input"))
    )
    (net (code "31") (name "CD") (class "Default")
      (node (ref "CARD2") (pin "9") (pinfunction "CD_9") (pintype "unspecified"))
      (node (ref "R228") (pin "1") (pinfunction "1_1") (pintype "input"))
    )
    (net (code "32") (name "CHASSIS_GND") (class "Default")
      (node (ref "C348") (pin "1") (pinfunction "1_1") (pintype "input"))
      (node (ref "CARD2") (pin "10") (pinfunction "GND_10") (pintype "unspecified"))
      (node (ref "CARD2") (pin "11") (pinfunction "GND_11") (pintype "unspecified"))
      (node (ref "CARD2") (pin "12") (pinfunction "GND_12") (pintype "unspecified"))
      (node (ref "CARD2") (pin "13") (pinfunction "GND_13") (pintype "unspecified"))
      (node (ref "CN2") (pin "20") (pinfunction "EH_20") (pintype "unspecified"))
      (node (ref "R131") (pin "1") (pinfunction "1_1") (pintype "input"))
      (node (ref "RJ1") (pin "SHIELD0") (pinfunction "SHIELD0_SHIELD0") (pintype "unspecified"))
      (node (ref "RJ1") (pin "SHIELD1") (pinfunction "SHIELD1_SHIELD1") (pintype "unspecified"))
      (node (ref "U27") (pin "1") (pinfunction "SHELL_1") (pintype "unspecified"))
      (node (ref "U27") (pin "2") (pinfunction "SHELL_2") (pintype "unspecified"))
      (node (ref "U27") (pin "3") (pinfunction "SHELL_3") (pintype "unspecified"))
      (node (ref "U27") (pin "4") (pinfunction "SHELL_4") (pintype "unspecified"))
      (node (ref "U71") (pin "1") (pinfunction "1_1") (pintype "input"))
      (node (ref "USB1") (pin "10") (pinfunction "10_10") (pintype "unspecified"))
      (node (ref "USB1") (pin "6") (pinfunction "6_6") (pintype "unspecified"))
      (node (ref "USB1") (pin "7") (pinfunction "7_7") (pintype "unspecified"))
      (node (ref "USB1") (pin "8") (pinfunction "8_8") (pintype "unspecified"))
      (node (ref "USB1") (pin "9") (pinfunction "9_9") (pintype "unspecified"))
    )
    (net (code "33") (name "DC_IN") (class "Default")
      (node (ref "D13") (pin "2") (pinfunction "A_2") (pintype "input"))
      (node (ref "DC1") (pin "4") (pinfunction "4_4") (pintype "input"))
    )
    (net (code "34") (name "DDR_ADDR0") (class "Default")
      (node (ref "R28") (pin "1") (pinfunction "1_1") (pintype "input"))
      (node (ref "U1") (pin "N3") (pinfunction "A0_N3") (pintype "input"))
      (node (ref "U2") (pin "M4") (pinfunction "PS_DDR_A0_502_M4") (pintype "output"))
      (node (ref "U3") (pin "N3") (pinfunction "A0_N3") (pintype "input"))
    )
    (net (code "35") (name "DDR_ADDR1") (class "Default")
      (node (ref "R27") (pin "1") (pinfunction "1_1") (pintype "input"))
      (node (ref "U1") (pin "P7") (pinfunction "A1_P7") (pintype "input"))
      (node (ref "U2") (pin "M5") (pinfunction "PS_DDR_A1_502_M5") (pintype "output"))
      (node (ref "U3") (pin "P7") (pinfunction "A1_P7") (pintype "input"))
    )
    (net (code "36") (name "DDR_ADDR2") (class "Default")
      (node (ref "R26") (pin "1") (pinfunction "1_1") (pintype "input"))
      (node (ref "U1") (pin "P3") (pinfunction "A2_P3") (pintype "input"))
      (node (ref "U2") (pin "K4") (pinfunction "PS_DDR_A2_502_K4") (pintype "output"))
      (node (ref "U3") (pin "P3") (pinfunction "A2_P3") (pintype "input"))
    )
    (net (code "37") (name "DDR_ADDR3") (class "Default")
      (node (ref "R31") (pin "1") (pinfunction "1_1") (pintype "input"))
      (node (ref "U1") (pin "N2") (pinfunction "A3_N2") (pintype "input"))
      (node (ref "U2") (pin "L4") (pinfunction "PS_DDR_A3_502_L4") (pintype "output"))
      (node (ref "U3") (pin "N2") (pinfunction "A3_N2") (pintype "input"))
    )
    (net (code "38") (name "DDR_ADDR4") (class "Default")
      (node (ref "R30") (pin "1") (pinfunction "1_1") (pintype "input"))
      (node (ref "U1") (pin "P8") (pinfunction "A4_P8") (pintype "input"))
      (node (ref "U2") (pin "K6") (pinfunction "PS_DDR_A4_502_K6") (pintype "output"))
      (node (ref "U3") (pin "P8") (pinfunction "A4_P8") (pintype "input"))
    )
    (net (code "39") (name "DDR_ADDR5") (class "Default")
      (node (ref "R29") (pin "1") (pinfunction "1_1") (pintype "input"))
      (node (ref "U1") (pin "P2") (pinfunction "A5_P2") (pintype "input"))
      (node (ref "U2") (pin "K5") (pinfunction "PS_DDR_A5_502_K5") (pintype "output"))
      (node (ref "U3") (pin "P2") (pinfunction "A5_P2") (pintype "input"))
    )
    (net (code "40") (name "DDR_ADDR6") (class "Default")
      (node (ref "R34") (pin "1") (pinfunction "1_1") (pintype "input"))
      (node (ref "U1") (pin "R8") (pinfunction "A6_R8") (pintype "input"))
      (node (ref "U2") (pin "J7") (pinfunction "PS_DDR_A6_502_J7") (pintype "output"))
      (node (ref "U3") (pin "R8") (pinfunction "A6_R8") (pintype "input"))
    )
    (net (code "41") (name "DDR_ADDR7") (class "Default")
      (node (ref "R33") (pin "1") (pinfunction "1_1") (pintype "input"))
      (node (ref "U1") (pin "R2") (pinfunction "A7_R2") (pintype "input"))
      (node (ref "U2") (pin "J6") (pinfunction "PS_DDR_A7_502_J6") (pintype "output"))
      (node (ref "U3") (pin "R2") (pinfunction "A7_R2") (pintype "input"))
    )
    (net (code "42") (name "DDR_ADDR8") (class "Default")
      (node (ref "R32") (pin "1") (pinfunction "1_1") (pintype "input"))
      (node (ref "U1") (pin "T8") (pinfunction "A8_T8") (pintype "input"))
      (node (ref "U2") (pin "J5") (pinfunction "PS_DDR_A8_502_J5") (pintype "output"))
      (node (ref "U3") (pin "T8") (pinfunction "A8_T8") (pintype "input"))
    )
    (net (code "43") (name "DDR_ADDR9") (class "Default")
      (node (ref "R44") (pin "1") (pinfunction "1_1") (pintype "input"))
      (node (ref "U1") (pin "R3") (pinfunction "A9_R3") (pintype "input"))
      (node (ref "U2") (pin "H5") (pinfunction "PS_DDR_A9_502_H5") (pintype "output"))
      (node (ref "U3") (pin "R3") (pinfunction "A9_R3") (pintype "input"))
    )
    (net (code "44") (name "DDR_ADDR10") (class "Default")
      (node (ref "R36") (pin "1") (pinfunction "1_1") (pintype "input"))
      (node (ref "U1") (pin "L7") (pinfunction "A10/AP_L7") (pintype "input"))
      (node (ref "U2") (pin "J3") (pinfunction "PS_DDR_A10_502_J3") (pintype "output"))
      (node (ref "U3") (pin "L7") (pinfunction "A10/AP_L7") (pintype "input"))
    )
    (net (code "45") (name "DDR_ADDR11") (class "Default")
      (node (ref "R35") (pin "1") (pinfunction "1_1") (pintype "input"))
      (node (ref "U1") (pin "R7") (pinfunction "A11_R7") (pintype "input"))
      (node (ref "U2") (pin "G5") (pinfunction "PS_DDR_A11_502_G5") (pintype "output"))
      (node (ref "U3") (pin "R7") (pinfunction "A11_R7") (pintype "input"))
    )
    (net (code "46") (name "DDR_ADDR12") (class "Default")
      (node (ref "R55") (pin "1") (pinfunction "1_1") (pintype "input"))
      (node (ref "U1") (pin "N7") (pinfunction "A12/BC#_N7") (pintype "input"))
      (node (ref "U2") (pin "H4") (pinfunction "PS_DDR_A12_502_H4") (pintype "output"))
      (node (ref "U3") (pin "N7") (pinfunction "A12/BC#_N7") (pintype "input"))
    )
    (net (code "47") (name "DDR_ADDR13") (class "Default")
      (node (ref "R54") (pin "1") (pinfunction "1_1") (pintype "input"))
      (node (ref "U1") (pin "T3") (pinfunction "A13_T3") (pintype "input"))
      (node (ref "U2") (pin "F4") (pinfunction "PS_DDR_A13_502_F4") (pintype "output"))
      (node (ref "U3") (pin "T3") (pinfunction "A13_T3") (pintype "input"))
    )
    (net (code "48") (name "DDR_ADDR14") (class "Default")
      (node (ref "R45") (pin "1") (pinfunction "1_1") (pintype "input"))
      (node (ref "U1") (pin "T7") (pinfunction "A14_T7") (pintype "input"))
      (node (ref "U2") (pin "G4") (pinfunction "PS_DDR_A14_502_G4") (pintype "output"))
      (node (ref "U3") (pin "T7") (pinfunction "A14_T7") (pintype "input"))
    )
    (net (code "50") (name "DDR_BA0") (class "Default")
      (node (ref "R25") (pin "1") (pinfunction "1_1") (pintype "input"))
      (node (ref "U1") (pin "M2") (pinfunction "BA0_M2") (pintype "input"))
      (node (ref "U2") (pin "L7") (pinfunction "PS_DDR_BA0_502_L7") (pintype "output"))
      (node (ref "U3") (pin "M2") (pinfunction "BA0_M2") (pintype "input"))
    )
    (net (code "51") (name "DDR_BA1") (class "Default")
      (node (ref "R24") (pin "1") (pinfunction "1_1") (pintype "input"))
      (node (ref "U1") (pin "N8") (pinfunction "BA1_N8") (pintype "input"))
      (node (ref "U2") (pin "L6") (pinfunction "PS_DDR_BA1_502_L6") (pintype "output"))
      (node (ref "U3") (pin "N8") (pinfunction "BA1_N8") (pintype "input"))
    )
    (net (code "52") (name "DDR_BA2") (class "Default")
      (node (ref "R23") (pin "1") (pinfunction "1_1") (pintype "input"))
      (node (ref "U1") (pin "M3") (pinfunction "BA2_M3") (pintype "input"))
      (node (ref "U2") (pin "M6") (pinfunction "PS_DDR_BA2_502_M6") (pintype "output"))
      (node (ref "U3") (pin "M3") (pinfunction "BA2_M3") (pintype "input"))
    )
    (net (code "53") (name "DDR_CASB") (class "Default")
      (node (ref "R20") (pin "1") (pinfunction "1_1") (pintype "input"))
      (node (ref "U1") (pin "K3") (pinfunction "CAS#_K3") (pintype "input"))
      (node (ref "U2") (pin "P3") (pinfunction "PS_DDR_CAS_B_502_P3") (pintype "output"))
      (node (ref "U3") (pin "K3") (pinfunction "CAS#_K3") (pintype "input"))
    )
    (net (code "54") (name "DDR_CKE") (class "Default")
      (node (ref "R18") (pin "1") (pinfunction "1_1") (pintype "input"))
      (node (ref "U1") (pin "K9") (pinfunction "CKE_K9") (pintype "input"))
      (node (ref "U2") (pin "V3") (pinfunction "PS_DDR_CKE_502_V3") (pintype "output"))
      (node (ref "U3") (pin "K9") (pinfunction "CKE_K9") (pintype "input"))
    )
    (net (code "55") (name "DDR_CK_N") (class "Default")
      (node (ref "R267") (pin "2") (pinfunction "2_2") (pintype "input"))
      (node (ref "U1") (pin "K7") (pinfunction "CK#_K7") (pintype "input"))
      (node (ref "U2") (pin "N5") (pinfunction "PS_DDR_CKN_502_N5") (pintype "output"))
      (node (ref "U3") (pin "K7") (pinfunction "CK#_K7") (pintype "input"))
    )
    (net (code "56") (name "DDR_CK_P") (class "Default")
      (node (ref "R267") (pin "1") (pinfunction "1_1") (pintype "input"))
      (node (ref "U1") (pin "J7") (pinfunction "CK_J7") (pintype "input"))
      (node (ref "U2") (pin "N4") (pinfunction "PS_DDR_CKP_502_N4") (pintype "output"))
      (node (ref "U3") (pin "J7") (pinfunction "CK_J7") (pintype "input"))
    )
    (net (code "57") (name "DDR_CSB") (class "Default")
      (node (ref "R22") (pin "1") (pinfunction "1_1") (pintype "input"))
      (node (ref "U1") (pin "L2") (pinfunction "CS#_L2") (pintype "input"))
      (node (ref "U2") (pin "P6") (pinfunction "PS_DDR_CS_B_502_P6") (pintype "output"))
      (node (ref "U3") (pin "L2") (pinfunction "CS#_L2") (pintype "input"))
    )
    (net (code "58") (name "DDR_DM0") (class "Default")
      (node (ref "U1") (pin "E7") (pinfunction "LDM_E7") (pintype "input"))
      (node (ref "U2") (pin "B1") (pinfunction "PS_DDR_DM0_502_B1") (pintype "output"))
    )
    (net (code "59") (name "DDR_DM1") (class "Default")
      (node (ref "U1") (pin "D3") (pinfunction "UDM_D3") (pintype "input"))
      (node (ref "U2") (pin "H3") (pinfunction "PS_DDR_DM1_502_H3") (pintype "output"))
    )
    (net (code "60") (name "DDR_DM2") (class "Default")
      (node (ref "U2") (pin "P1") (pinfunction "PS_DDR_DM2_502_P1") (pintype "output"))
      (node (ref "U3") (pin "E7") (pinfunction "LDM_E7") (pintype "input"))
    )
    (net (code "61") (name "DDR_DM3") (class "Default")
      (node (ref "U2") (pin "AA2") (pinfunction "PS_DDR_DM3_502_AA2") (pintype "output"))
      (node (ref "U3") (pin "D3") (pinfunction "UDM_D3") (pintype "input"))
    )
    (net (code "62") (name "DDR_DQ0") (class "Default")
      (node (ref "U1") (pin "E3") (pinfunction "DQ0_E3") (pintype "input"))
      (node (ref "U2") (pin "D1") (pinfunction "PS_DDR_DQ0_502_D1") (pintype "bidirectional"))
    )
    (net (code "63") (name "DDR_DQ1") (class "Default")
      (node (ref "U1") (pin "F7") (pinfunction "DQ1_F7") (pintype "input"))
      (node (ref "U2") (pin "E1") (pinfunction "PS_DDR_DQ5_502_E1") (pintype "bidirectional"))
    )
    (net (code "64") (name "DDR_DQ2") (class "Default")
      (node (ref "U1") (pin "F2") (pinfunction "DQ2_F2") (pintype "input"))
      (node (ref "U2") (pin "B2") (pinfunction "PS_DDR_DQ2_502_B2") (pintype "bidirectional"))
    )
    (net (code "65") (name "DDR_DQ3") (class "Default")
      (node (ref "U1") (pin "F8") (pinfunction "DQ3_F8") (pintype "input"))
      (node (ref "U2") (pin "F2") (pinfunction "PS_DDR_DQ6_502_F2") (pintype "bidirectional"))
    )
    (net (code "66") (name "DDR_DQ4") (class "Default")
      (node (ref "U1") (pin "H3") (pinfunction "DQ4_H3") (pintype "input"))
      (node (ref "U2") (pin "D3") (pinfunction "PS_DDR_DQ3_502_D3") (pintype "bidirectional"))
    )
    (net (code "67") (name "DDR_DQ5") (class "Default")
      (node (ref "U1") (pin "H8") (pinfunction "DQ5_H8") (pintype "input"))
      (node (ref "U2") (pin "E3") (pinfunction "PS_DDR_DQ4_502_E3") (pintype "bidirectional"))
    )
    (net (code "68") (name "DDR_DQ6") (class "Default")
      (node (ref "U1") (pin "G2") (pinfunction "DQ6_G2") (pintype "input"))
      (node (ref "U2") (pin "C3") (pinfunction "PS_DDR_DQ1_502_C3") (pintype "bidirectional"))
    )
    (net (code "69") (name "DDR_DQ7") (class "Default")
      (node (ref "U1") (pin "H7") (pinfunction "DQ7_H7") (pintype "input"))
      (node (ref "U2") (pin "F1") (pinfunction "PS_DDR_DQ7_502_F1") (pintype "bidirectional"))
    )
    (net (code "70") (name "DDR_DQ8") (class "Default")
      (node (ref "U1") (pin "D7") (pinfunction "DQ8_D7") (pintype "input"))
      (node (ref "U2") (pin "G2") (pinfunction "PS_DDR_DQ8_502_G2") (pintype "bidirectional"))
    )
    (net (code "71") (name "DDR_DQ9") (class "Default")
      (node (ref "U1") (pin "C3") (pinfunction "DQ9_C3") (pintype "input"))
      (node (ref "U2") (pin "L1") (pinfunction "PS_DDR_DQ10_502_L1") (pintype "bidirectional"))
    )
    (net (code "72") (name "DDR_DQ10") (class "Default")
      (node (ref "U1") (pin "C8") (pinfunction "DQ10_C8") (pintype "input"))
      (node (ref "U2") (pin "L3") (pinfunction "PS_DDR_DQ12_502_L3") (pintype "bidirectional"))
    )
    (net (code "73") (name "DDR_DQ11") (class "Default")
      (node (ref "U1") (pin "C2") (pinfunction "DQ11_C2") (pintype "input"))
      (node (ref "U2") (pin "L2") (pinfunction "PS_DDR_DQ11_502_L2") (pintype "bidirectional"))
    )
    (net (code "74") (name "DDR_DQ12") (class "Default")
      (node (ref "U1") (pin "A7") (pinfunction "DQ12_A7") (pintype "input"))
      (node (ref "U2") (pin "J1") (pinfunction "PS_DDR_DQ14_502_J1") (pintype "bidirectional"))
    )
    (net (code "75") (name "DDR_DQ13") (class "Default")
      (node (ref "U1") (pin "A2") (pinfunction "DQ13_A2") (pintype "input"))
      (node (ref "U2") (pin "K3") (pinfunction "PS_DDR_DQ15_502_K3") (pintype "bidirectional"))
    )
    (net (code "76") (name "DDR_DQ14") (class "Default")
      (node (ref "U1") (pin "B8") (pinfunction "DQ14_B8") (pintype "input"))
      (node (ref "U2") (pin "K1") (pinfunction "PS_DDR_DQ13_502_K1") (pintype "bidirectional"))
    )
    (net (code "77") (name "DDR_DQ15") (class "Default")
      (node (ref "U1") (pin "A3") (pinfunction "DQ15_A3") (pintype "input"))
      (node (ref "U2") (pin "G1") (pinfunction "PS_DDR_DQ9_502_G1") (pintype "bidirectional"))
    )
    (net (code "78") (name "DDR_DQ16") (class "Default")
      (node (ref "U2") (pin "M1") (pinfunction "PS_DDR_DQ16_502_M1") (pintype "bidirectional"))
      (node (ref "U3") (pin "E3") (pinfunction "DQ0_E3") (pintype "input"))
    )
    (net (code "79") (name "DDR_DQ17") (class "Default")
      (node (ref "U2") (pin "R3") (pinfunction "PS_DDR_DQ20_502_R3") (pintype "bidirectional"))
      (node (ref "U3") (pin "F7") (pinfunction "DQ1_F7") (pintype "input"))
    )
    (net (code "80") (name "DDR_DQ18") (class "Default")
      (node (ref "U2") (pin "R1") (pinfunction "PS_DDR_DQ23_502_R1") (pintype "bidirectional"))
      (node (ref "U3") (pin "F2") (pinfunction "DQ2_F2") (pintype "input"))
    )
    (net (code "81") (name "DDR_DQ19") (class "Default")
      (node (ref "U2") (pin "T2") (pinfunction "PS_DDR_DQ21_502_T2") (pintype "bidirectional"))
      (node (ref "U3") (pin "F8") (pinfunction "DQ3_F8") (pintype "input"))
    )
    (net (code "82") (name "DDR_DQ20") (class "Default")
      (node (ref "U2") (pin "T1") (pinfunction "PS_DDR_DQ19_502_T1") (pintype "bidirectional"))
      (node (ref "U3") (pin "H3") (pinfunction "DQ4_H3") (pintype "input"))
    )
    (net (code "83") (name "DDR_DQ21") (class "Default")
      (node (ref "U2") (pin "T3") (pinfunction "PS_DDR_DQ17_502_T3") (pintype "bidirectional"))
      (node (ref "U3") (pin "H8") (pinfunction "DQ5_H8") (pintype "input"))
    )
    (net (code "84") (name "DDR_DQ22") (class "Default")
      (node (ref "U2") (pin "N3") (pinfunction "PS_DDR_DQ18_502_N3") (pintype "bidirectional"))
      (node (ref "U3") (pin "G2") (pinfunction "DQ6_G2") (pintype "input"))
    )
    (net (code "85") (name "DDR_DQ23") (class "Default")
      (node (ref "U2") (pin "M2") (pinfunction "PS_DDR_DQ22_502_M2") (pintype "bidirectional"))
      (node (ref "U3") (pin "H7") (pinfunction "DQ7_H7") (pintype "input"))
    )
    (net (code "86") (name "DDR_DQ24") (class "Default")
      (node (ref "U2") (pin "AA3") (pinfunction "PS_DDR_DQ24_502_AA3") (pintype "bidirectional"))
      (node (ref "U3") (pin "D7") (pinfunction "DQ8_D7") (pintype "input"))
    )
    (net (code "87") (name "DDR_DQ25") (class "Default")
      (node (ref "U2") (pin "Y3") (pinfunction "PS_DDR_DQ29_502_Y3") (pintype "bidirectional"))
      (node (ref "U3") (pin "C3") (pinfunction "DQ9_C3") (pintype "input"))
    )
    (net (code "88") (name "DDR_DQ26") (class "Default")
      (node (ref "U2") (pin "W1") (pinfunction "PS_DDR_DQ28_502_W1") (pintype "bidirectional"))
      (node (ref "U3") (pin "C8") (pinfunction "DQ10_C8") (pintype "input"))
    )
    (net (code "89") (name "DDR_DQ27") (class "Default")
      (node (ref "U2") (pin "U2") (pinfunction "PS_DDR_DQ27_502_U2") (pintype "bidirectional"))
      (node (ref "U3") (pin "C2") (pinfunction "DQ11_C2") (pintype "input"))
    )
    (net (code "90") (name "DDR_DQ28") (class "Default")
      (node (ref "U2") (pin "Y1") (pinfunction "PS_DDR_DQ31_502_Y1") (pintype "bidirectional"))
      (node (ref "U3") (pin "A7") (pinfunction "DQ12_A7") (pintype "input"))
    )
    (net (code "91") (name "DDR_DQ29") (class "Default")
      (node (ref "U2") (pin "U1") (pinfunction "PS_DDR_DQ25_502_U1") (pintype "bidirectional"))
      (node (ref "U3") (pin "A2") (pinfunction "DQ13_A2") (pintype "input"))
    )
    (net (code "92") (name "DDR_DQ30") (class "Default")
      (node (ref "U2") (pin "W3") (pinfunction "PS_DDR_DQ30_502_W3") (pintype "bidirectional"))
      (node (ref "U3") (pin "B8") (pinfunction "DQ14_B8") (pintype "input"))
    )
    (net (code "93") (name "DDR_DQ31") (class "Default")
      (node (ref "U2") (pin "AA1") (pinfunction "PS_DDR_DQ26_502_AA1") (pintype "bidirectional"))
      (node (ref "U3") (pin "A3") (pinfunction "DQ15_A3") (pintype "input"))
    )
    (net (code "94") (name "DDR_DQS0_N") (class "Default")
      (node (ref "U1") (pin "G3") (pinfunction "LDQS#_G3") (pintype "input"))
      (node (ref "U2") (pin "D2") (pinfunction "PS_DDR_DQS_N0_502_D2") (pintype "bidirectional"))
    )
    (net (code "95") (name "DDR_DQS0_P") (class "Default")
      (node (ref "U1") (pin "F3") (pinfunction "LDQS_F3") (pintype "input"))
      (node (ref "U2") (pin "C2") (pinfunction "PS_DDR_DQS_P0_502_C2") (pintype "bidirectional"))
    )
    (net (code "96") (name "DDR_DQS1_N") (class "Default")
      (node (ref "U1") (pin "B7") (pinfunction "UDQS#_B7") (pintype "input"))
      (node (ref "U2") (pin "J2") (pinfunction "PS_DDR_DQS_N1_502_J2") (pintype "bidirectional"))
    )
    (net (code "97") (name "DDR_DQS1_P") (class "Default")
      (node (ref "U1") (pin "C7") (pinfunction "UDQS_C7") (pintype "input"))
      (node (ref "U2") (pin "H2") (pinfunction "PS_DDR_DQS_P1_502_H2") (pintype "bidirectional"))
    )
    (net (code "98") (name "DDR_DQS2_N") (class "Default")
      (node (ref "U2") (pin "P2") (pinfunction "PS_DDR_DQS_N2_502_P2") (pintype "bidirectional"))
      (node (ref "U3") (pin "G3") (pinfunction "LDQS#_G3") (pintype "input"))
    )
    (net (code "99") (name "DDR_DQS2_P") (class "Default")
      (node (ref "U2") (pin "N2") (pinfunction "PS_DDR_DQS_P2_502_N2") (pintype "bidirectional"))
      (node (ref "U3") (pin "F3") (pinfunction "LDQS_F3") (pintype "input"))
    )
    (net (code "100") (name "DDR_DQS3_N") (class "Default")
      (node (ref "U2") (pin "W2") (pinfunction "PS_DDR_DQS_N3_502_W2") (pintype "bidirectional"))
      (node (ref "U3") (pin "B7") (pinfunction "UDQS#_B7") (pintype "input"))
    )
    (net (code "101") (name "DDR_DQS3_P") (class "Default")
      (node (ref "U2") (pin "V2") (pinfunction "PS_DDR_DQS_P3_502_V2") (pintype "bidirectional"))
      (node (ref "U3") (pin "C7") (pinfunction "UDQS_C7") (pintype "input"))
    )
    (net (code "103") (name "DDR_ODT") (class "Default")
      (node (ref "R60") (pin "1") (pinfunction "1_1") (pintype "input"))
      (node (ref "U1") (pin "K1") (pinfunction "ODT_K1") (pintype "input"))
      (node (ref "U2") (pin "P5") (pinfunction "PS_DDR_ODT_502_P5") (pintype "output"))
      (node (ref "U3") (pin "K1") (pinfunction "ODT_K1") (pintype "input"))
    )
    (net (code "104") (name "DDR_RASB") (class "Default")
      (node (ref "R21") (pin "1") (pinfunction "1_1") (pintype "input"))
      (node (ref "U1") (pin "J3") (pinfunction "RAS#_J3") (pintype "input"))
      (node (ref "U2") (pin "R5") (pinfunction "PS_DDR_RAS_B_502_R5") (pintype "output"))
      (node (ref "U3") (pin "J3") (pinfunction "RAS#_J3") (pintype "input"))
    )
    (net (code "105") (name "DDR_RSTB") (class "Default")
      (node (ref "R63") (pin "2") (pinfunction "2_2") (pintype "input"))
      (node (ref "U1") (pin "T2") (pinfunction "RESET#_T2") (pintype "input"))
      (node (ref "U2") (pin "F3") (pinfunction "PS_DDR_DRST_B_502_F3") (pintype "output"))
      (node (ref "U3") (pin "T2") (pinfunction "RESET#_T2") (pintype "input"))
    )
    (net (code "106") (name "DDR_WEB") (class "Default")
      (node (ref "R19") (pin "1") (pinfunction "1_1") (pintype "input"))
      (node (ref "U1") (pin "L3") (pinfunction "WE#_L3") (pintype "input"))
      (node (ref "U2") (pin "R4") (pinfunction "PS_DDR_WE_B_502_R4") (pintype "output"))
      (node (ref "U3") (pin "L3") (pinfunction "WE#_L3") (pintype "input"))
    )
    (net (code "107") (name "DN1") (class "Default")
      (node (ref "D7") (pin "2") (pinfunction "2_2") (pintype "input"))
      (node (ref "U27") (pin "A7") (pinfunction "DN1_A7") (pintype "unspecified"))
      (node (ref "U34") (pin "7") (pinfunction "DM_7") (pintype "input"))
    )
    (net (code "108") (name "DONE") (class "Default")
      (node (ref "R49") (pin "1") (pinfunction "1_1") (pintype "input"))
      (node (ref "R53") (pin "2") (pinfunction "2_2") (pintype "input"))
      (node (ref "U2") (pin "T12") (pinfunction "DONE_0_T12") (pintype "bidirectional"))
    )
    (net (code "109") (name "DP1") (class "Default")
      (node (ref "D6") (pin "2") (pinfunction "2_2") (pintype "input"))
      (node (ref "U27") (pin "A6") (pinfunction "DP1_A6") (pintype "unspecified"))
      (node (ref "U34") (pin "8") (pinfunction "DP_8") (pintype "input"))
    )
    (net (code "110") (name "ETH_CLKO") (class "Default")
      (node (ref "R243") (pin "1") (pinfunction "1_1") (pintype "input"))
      (node (ref "U35") (pin "35") (pinfunction "CLKOUT_35") (pintype "unspecified"))
    )
    (net (code "111") (name "ETH_CLK_25MHZ") (class "Default")
      (node (ref "R242") (pin "1") (pinfunction "1_1") (pintype "input"))
      (node (ref "U35") (pin "37") (pinfunction "XTAL_OUT/EXT_CLK_37") (pintype "unspecified"))
    )
    (net (code "112") (name "ETH_INTB") (class "Default")
      (node (ref "R245") (pin "2") (pinfunction "2_2") (pintype "input"))
      (node (ref "U2") (pin "G7") (pinfunction "PS_MIO10_500_G7") (pintype "bidirectional"))
      (node (ref "U35") (pin "31") (pinfunction "INTB/PMEB_31") (pintype "unspecified"))
    )
    (net (code "113") (name "ETH_MDC") (class "Default")
      (node (ref "U2") (pin "D10") (pinfunction "PS_MIO52_501_D10") (pintype "bidirectional"))
      (node (ref "U35") (pin "13") (pinfunction "MDC_13") (pintype "unspecified"))
    )
    (net (code "114") (name "ETH_MDIO") (class "Default")
      (node (ref "R246") (pin "2") (pinfunction "2_2") (pintype "input"))
      (node (ref "U2") (pin "C12") (pinfunction "PS_MIO53_501_C12") (pintype "bidirectional"))
      (node (ref "U35") (pin "14") (pinfunction "MDIO_14") (pintype "unspecified"))
    )
    (net (code "115") (name "ETH_PHY_RXCLK") (class "Default")
      (node (ref "R260") (pin "2") (pinfunction "2_2") (pintype "input"))
      (node (ref "U35") (pin "27") (pinfunction "PHYAD1/RXC_27") (pintype "unspecified"))
    )
    (net (code "116") (name "ETH_PHY_RXCTL") (class "Default")
      (node (ref "R259") (pin "2") (pinfunction "2_2") (pintype "input"))
      (node (ref "U35") (pin "26") (pinfunction "PHYAD2/RXCTL_26") (pintype "unspecified"))
    )
    (net (code "117") (name "ETH_PHY_RXD0") (class "Default")
      (node (ref "R255") (pin "2") (pinfunction "2_2") (pintype "input"))
      (node (ref "U35") (pin "25") (pinfunction "RXDLY/RXD0_25") (pintype "unspecified"))
    )
    (net (code "118") (name "ETH_PHY_RXD1") (class "Default")
      (node (ref "R256") (pin "2") (pinfunction "2_2") (pintype "input"))
      (node (ref "U35") (pin "24") (pinfunction "TXDLY/RXD1_24") (pintype "unspecified"))
    )
    (net (code "119") (name "ETH_PHY_RXD2") (class "Default")
      (node (ref "R257") (pin "2") (pinfunction "2_2") (pintype "input"))
      (node (ref "U35") (pin "23") (pinfunction "PLLOFF/RXD2_23") (pintype "unspecified"))
    )
    (net (code "120") (name "ETH_PHY_RXD3") (class "Default")
      (node (ref "R258") (pin "2") (pinfunction "2_2") (pintype "input"))
      (node (ref "U35") (pin "22") (pinfunction "PHYAD0/RXD3_22") (pintype "unspecified"))
    )
    (net (code "121") (name "ETH_PHY_TXCLK") (class "Default")
      (node (ref "R261") (pin "2") (pinfunction "2_2") (pintype "input"))
      (node (ref "U35") (pin "20") (pinfunction "TXC_20") (pintype "unspecified"))
    )
    (net (code "122") (name "ETH_PHY_TXCTL") (class "Default")
      (node (ref "R266") (pin "2") (pinfunction "2_2") (pintype "input"))
      (node (ref "U35") (pin "19") (pinfunction "TXCTL_19") (pintype "unspecified"))
    )
    (net (code "123") (name "ETH_PHY_TXD0") (class "Default")
      (node (ref "R262") (pin "2") (pinfunction "2_2") (pintype "input"))
      (node (ref "U35") (pin "18") (pinfunction "TXD0_18") (pintype "unspecified"))
    )
    (net (code "124") (name "ETH_PHY_TXD1") (class "Default")
      (node (ref "R263") (pin "2") (pinfunction "2_2") (pintype "input"))
      (node (ref "U35") (pin "17") (pinfunction "TXD1_17") (pintype "unspecified"))
    )
    (net (code "125") (name "ETH_PHY_TXD2") (class "Default")
      (node (ref "R264") (pin "2") (pinfunction "2_2") (pintype "input"))
      (node (ref "U35") (pin "16") (pinfunction "TXD2_16") (pintype "unspecified"))
    )
    (net (code "126") (name "ETH_PHY_TXD3") (class "Default")
      (node (ref "R265") (pin "2") (pinfunction "2_2") (pintype "input"))
      (node (ref "U35") (pin "15") (pinfunction "TXD3_15") (pintype "unspecified"))
    )
    (net (code "127") (name "ETH_REG_OUT") (class "Default")
      (node (ref "L11") (pin "1") (pinfunction "1_1") (pintype "input"))
      (node (ref "U35") (pin "30") (pinfunction "REG_OUT/LDO_OUT_30") (pintype "unspecified"))
    )
    (net (code "128") (name "ETH_RSET") (class "Default")
      (node (ref "R250") (pin "1") (pinfunction "1_1") (pintype "input"))
      (node (ref "U35") (pin "39") (pinfunction "RSET_39") (pintype "unspecified"))
    )
    (net (code "129") (name "ETH_RSTB") (class "Default")
      (node (ref "U2") (pin "C4") (pinfunction "PS_MIO9_500_C4") (pintype "bidirectional"))
      (node (ref "U35") (pin "12") (pinfunction "PHYRSTB_12") (pintype "unspecified"))
    )
    (net (code "130") (name "ETH_RXCLK") (class "Default")
      (node (ref "R248") (pin "1") (pinfunction "1_1") (pintype "input"))
      (node (ref "R260") (pin "1") (pinfunction "1_1") (pintype "input"))
      (node (ref "U2") (pin "A14") (pinfunction "PS_MIO22_501_A14") (pintype "bidirectional"))
    )
    (net (code "131") (name "ETH_RXCTL") (class "Default")
      (node (ref "R247") (pin "1") (pinfunction "1_1") (pintype "input"))
      (node (ref "R259") (pin "1") (pinfunction "1_1") (pintype "input"))
      (node (ref "U2") (pin "D7") (pinfunction "PS_MIO27_501_D7") (pintype "bidirectional"))
    )
    (net (code "132") (name "ETH_RXD0") (class "Default")
      (node (ref "R251") (pin "2") (pinfunction "2_2") (pintype "input"))
      (node (ref "R255") (pin "1") (pinfunction "1_1") (pintype "input"))
      (node (ref "U2") (pin "E11") (pinfunction "PS_MIO23_501_E11") (pintype "bidirectional"))
    )
    (net (code "133") (name "ETH_RXD1") (class "Default")
      (node (ref "R252") (pin "2") (pinfunction "2_2") (pintype "input"))
      (node (ref "R256") (pin "1") (pinfunction "1_1") (pintype "input"))
      (node (ref "U2") (pin "B7") (pinfunction "PS_MIO24_501_B7") (pintype "bidirectional"))
    )
    (net (code "134") (name "ETH_RXD2") (class "Default")
      (node (ref "R249") (pin "1") (pinfunction "1_1") (pintype "input"))
      (node (ref "R253") (pin "2") (pinfunction "2_2") (pintype "input"))
      (node (ref "R257") (pin "1") (pinfunction "1_1") (pintype "input"))
      (node (ref "U2") (pin "F12") (pinfunction "PS_MIO25_501_F12") (pintype "bidirectional"))
    )
    (net (code "135") (name "ETH_RXD3") (class "Default")
      (node (ref "R254") (pin "2") (pinfunction "2_2") (pintype "input"))
      (node (ref "R258") (pin "1") (pinfunction "1_1") (pintype "input"))
      (node (ref "U2") (pin "A13") (pinfunction "PS_MIO26_501_A13") (pintype "bidirectional"))
    )
    (net (code "136") (name "ETH_TXCLK") (class "Default")
      (node (ref "R261") (pin "1") (pinfunction "1_1") (pintype "input"))
      (node (ref "U2") (pin "D6") (pinfunction "PS_MIO16_501_D6") (pintype "bidirectional"))
    )
    (net (code "137") (name "ETH_TXCTL") (class "Default")
      (node (ref "R266") (pin "1") (pinfunction "1_1") (pintype "input"))
      (node (ref "U2") (pin "F11") (pinfunction "PS_MIO21_501_F11") (pintype "bidirectional"))
    )
    (net (code "138") (name "ETH_TXD0") (class "Default")
      (node (ref "R262") (pin "1") (pinfunction "1_1") (pintype "input"))
      (node (ref "U2") (pin "E9") (pinfunction "PS_MIO17_501_E9") (pintype "bidirectional"))
    )
    (net (code "139") (name "ETH_TXD1") (class "Default")
      (node (ref "R263") (pin "1") (pinfunction "1_1") (pintype "input"))
      (node (ref "U2") (pin "A7") (pinfunction "PS_MIO18_501_A7") (pintype "bidirectional"))
    )
    (net (code "140") (name "ETH_TXD2") (class "Default")
      (node (ref "R264") (pin "1") (pinfunction "1_1") (pintype "input"))
      (node (ref "U2") (pin "E10") (pinfunction "PS_MIO19_501_E10") (pintype "bidirectional"))
    )
    (net (code "141") (name "ETH_TXD3") (class "Default")
      (node (ref "R265") (pin "1") (pinfunction "1_1") (pintype "input"))
      (node (ref "U2") (pin "A8") (pinfunction "PS_MIO20_501_A8") (pintype "bidirectional"))
    )
    (net (code "142") (name "ETH_XTAL_IN") (class "Default")
      (node (ref "R244") (pin "1") (pinfunction "1_1") (pintype "input"))
      (node (ref "U35") (pin "36") (pinfunction "XTAL_IN_36") (pintype "unspecified"))
    )
    (net (code "143") (name "FTDI_RX_LED") (class "Default")
      (node (ref "LED16") (pin "1") (pinfunction "C_1") (pintype "input"))
      (node (ref "U34") (pin "55") (pinfunction "BCBUS4_55") (pintype "bidirectional"))
    )
    (net (code "144") (name "FTDI_TX_LED") (class "Default")
      (node (ref "LED15") (pin "1") (pinfunction "C_1") (pintype "input"))
      (node (ref "U34") (pin "54") (pinfunction "BCBUS3_54") (pintype "bidirectional"))
    )
    (net (code "145") (name "GND") (class "Default")
      (node (ref "C1") (pin "2") (pinfunction "2_2") (pintype "input"))
      (node (ref "C10") (pin "2") (pinfunction "2_2") (pintype "input"))
      (node (ref "C100") (pin "2") (pinfunction "2_2") (pintype "input"))
      (node (ref "C101") (pin "2") (pinfunction "2_2") (pintype "input"))
      (node (ref "C102") (pin "2") (pinfunction "2_2") (pintype "input"))
      (node (ref "C103") (pin "2") (pinfunction "2_2") (pintype "input"))
      (node (ref "C11") (pin "2") (pinfunction "2_2") (pintype "input"))
      (node (ref "C12") (pin "2") (pinfunction "2_2") (pintype "input"))
      (node (ref "C14") (pin "2") (pinfunction "2_2") (pintype "input"))
      (node (ref "C144") (pin "2") (pinfunction "2_2") (pintype "input"))
      (node (ref "C155") (pin "2") (pinfunction "2_2") (pintype "input"))
      (node (ref "C157") (pin "2") (pinfunction "2_2") (pintype "input"))
      (node (ref "C159") (pin "2") (pinfunction "2_2") (pintype "input"))
      (node (ref "C16") (pin "2") (pinfunction "2_2") (pintype "input"))
      (node (ref "C166") (pin "2") (pinfunction "2_2") (pintype "input"))
      (node (ref "C168") (pin "2") (pinfunction "2_2") (pintype "input"))
      (node (ref "C17") (pin "2") (pinfunction "2_2") (pintype "input"))
      (node (ref "C170") (pin "2") (pinfunction "2_2") (pintype "input"))
      (node (ref "C176") (pin "2") (pinfunction "2_2") (pintype "input"))
      (node (ref "C18") (pin "2") (pinfunction "2_2") (pintype "input"))
      (node (ref "C181") (pin "2") (pinfunction "2_2") (pintype "input"))
      (node (ref "C182") (pin "2") (pinfunction "2_2") (pintype "input"))
      (node (ref "C183") (pin "2") (pinfunction "2_2") (pintype "input"))
      (node (ref "C184") (pin "2") (pinfunction "2_2") (pintype "input"))
      (node (ref "C189") (pin "2") (pinfunction "2_2") (pintype "input"))
      (node (ref "C19") (pin "2") (pinfunction "2_2") (pintype "input"))
      (node (ref "C190") (pin "2") (pinfunction "2_2") (pintype "input"))
      (node (ref "C191") (pin "2") (pinfunction "2_2") (pintype "input"))
      (node (ref "C192") (pin "2") (pinfunction "2_2") (pintype "input"))
      (node (ref "C193") (pin "2") (pinfunction "2_2") (pintype "input"))
      (node (ref "C194") (pin "2") (pinfunction "2_2") (pintype "input"))
      (node (ref "C195") (pin "2") (pinfunction "2_2") (pintype "input"))
      (node (ref "C2") (pin "2") (pinfunction "2_2") (pintype "input"))
      (node (ref "C20") (pin "2") (pinfunction "2_2") (pintype "input"))
      (node (ref "C217") (pin "2") (pinfunction "2_2") (pintype "input"))
      (node (ref "C218") (pin "2") (pinfunction "2_2") (pintype "input"))
      (node (ref "C219") (pin "2") (pinfunction "2_2") (pintype "input"))
      (node (ref "C22") (pin "2") (pinfunction "2_2") (pintype "input"))
      (node (ref "C220") (pin "2") (pinfunction "2_2") (pintype "input"))
      (node (ref "C221") (pin "2") (pinfunction "2_2") (pintype "input"))
      (node (ref "C222") (pin "2") (pinfunction "2_2") (pintype "input"))
      (node (ref "C227") (pin "2") (pinfunction "2_2") (pintype "input"))
      (node (ref "C228") (pin "2") (pinfunction "2_2") (pintype "input"))
      (node (ref "C229") (pin "2") (pinfunction "2_2") (pintype "input"))
      (node (ref "C230") (pin "2") (pinfunction "2_2") (pintype "input"))
      (node (ref "C24") (pin "2") (pinfunction "2_2") (pintype "input"))
      (node (ref "C240") (pin "1") (pinfunction "1_1") (pintype "input"))
      (node (ref "C241") (pin "1") (pinfunction "1_1") (pintype "input"))
      (node (ref "C243") (pin "1") (pinfunction "1_1") (pintype "input"))
      (node (ref "C244") (pin "2") (pinfunction "2_2") (pintype "input"))
      (node (ref "C248") (pin "2") (pinfunction "2_2") (pintype "input"))
      (node (ref "C25") (pin "2") (pinfunction "2_2") (pintype "input"))
      (node (ref "C253") (pin "2") (pinfunction "2_2") (pintype "input"))
      (node (ref "C257") (pin "2") (pinfunction "2_2") (pintype "input"))
      (node (ref "C258") (pin "2") (pinfunction "2_2") (pintype "input"))
      (node (ref "C259") (pin "2") (pinfunction "2_2") (pintype "input"))
      (node (ref "C26") (pin "2") (pinfunction "2_2") (pintype "input"))
      (node (ref "C261") (pin "2") (pinfunction "2_2") (pintype "input"))
      (node (ref "C262") (pin "2") (pinfunction "2_2") (pintype "input"))
      (node (ref "C263") (pin "2") (pinfunction "2_2") (pintype "input"))
      (node (ref "C264") (pin "2") (pinfunction "2_2") (pintype "input"))
      (node (ref "C265") (pin "2") (pinfunction "2_2") (pintype "input"))
      (node (ref "C268") (pin "2") (pinfunction "2_2") (pintype "input"))
      (node (ref "C27") (pin "2") (pinfunction "2_2") (pintype "input"))
      (node (ref "C274") (pin "2") (pinfunction "2_2") (pintype "input"))
      (node (ref "C277") (pin "2") (pinfunction "2_2") (pintype "input"))
      (node (ref "C278") (pin "2") (pinfunction "2_2") (pintype "input"))
      (node (ref "C279") (pin "2") (pinfunction "2_2") (pintype "input"))
      (node (ref "C28") (pin "2") (pinfunction "2_2") (pintype "input"))
      (node (ref "C280") (pin "2") (pinfunction "2_2") (pintype "input"))
      (node (ref "C284") (pin "2") (pinfunction "2_2") (pintype "input"))
      (node (ref "C285") (pin "2") (pinfunction "2_2") (pintype "input"))
      (node (ref "C286") (pin "2") (pinfunction "2_2") (pintype "input"))
      (node (ref "C287") (pin "2") (pinfunction "2_2") (pintype "input"))
      (node (ref "C288") (pin "2") (pinfunction "2_2") (pintype "input"))
      (node (ref "C289") (pin "2") (pinfunction "2_2") (pintype "input"))
      (node (ref "C290") (pin "2") (pinfunction "2_2") (pintype "input"))
      (node (ref "C291") (pin "2") (pinfunction "2_2") (pintype "input"))
      (node (ref "C293") (pin "2") (pinfunction "2_2") (pintype "input"))
      (node (ref "C294") (pin "2") (pinfunction "2_2") (pintype "input"))
      (node (ref "C295") (pin "2") (pinfunction "2_2") (pintype "input"))
      (node (ref "C3") (pin "2") (pinfunction "2_2") (pintype "input"))
      (node (ref "C30") (pin "2") (pinfunction "2_2") (pintype "input"))
      (node (ref "C300") (pin "1") (pinfunction "1_1") (pintype "input"))
      (node (ref "C301") (pin "2") (pinfunction "2_2") (pintype "input"))
      (node (ref "C32") (pin "2") (pinfunction "2_2") (pintype "input"))
      (node (ref "C33") (pin "2") (pinfunction "2_2") (pintype "input"))
      (node (ref "C34") (pin "2") (pinfunction "2_2") (pintype "input"))
      (node (ref "C348") (pin "2") (pinfunction "2_2") (pintype "input"))
      (node (ref "C349") (pin "2") (pinfunction "2_2") (pintype "input"))
      (node (ref "C350") (pin "2") (pinfunction "2_2") (pintype "input"))
      (node (ref "C351") (pin "2") (pinfunction "2_2") (pintype "input"))
      (node (ref "C352") (pin "2") (pinfunction "2_2") (pintype "input"))
      (node (ref "C353") (pin "2") (pinfunction "2_2") (pintype "input"))
      (node (ref "C354") (pin "2") (pinfunction "2_2") (pintype "input"))
      (node (ref "C355") (pin "2") (pinfunction "2_2") (pintype "input"))
      (node (ref "C356") (pin "2") (pinfunction "2_2") (pintype "input"))
      (node (ref "C357") (pin "2") (pinfunction "2_2") (pintype "input"))
      (node (ref "C358") (pin "1") (pinfunction "1_1") (pintype "input"))
      (node (ref "C359") (pin "2") (pinfunction "2_2") (pintype "input"))
      (node (ref "C36") (pin "2") (pinfunction "2_2") (pintype "input"))
      (node (ref "C360") (pin "2") (pinfunction "2_2") (pintype "input"))
      (node (ref "C361") (pin "2") (pinfunction "2_2") (pintype "input"))
      (node (ref "C362") (pin "2") (pinfunction "2_2") (pintype "input"))
      (node (ref "C363") (pin "2") (pinfunction "2_2") (pintype "input"))
      (node (ref "C364") (pin "2") (pinfunction "2_2") (pintype "input"))
      (node (ref "C365") (pin "2") (pinfunction "2_2") (pintype "input"))
      (node (ref "C366") (pin "2") (pinfunction "2_2") (pintype "input"))
      (node (ref "C367") (pin "2") (pinfunction "2_2") (pintype "input"))
      (node (ref "C368") (pin "2") (pinfunction "2_2") (pintype "input"))
      (node (ref "C369") (pin "2") (pinfunction "2_2") (pintype "input"))
      (node (ref "C37") (pin "2") (pinfunction "2_2") (pintype "input"))
      (node (ref "C370") (pin "2") (pinfunction "2_2") (pintype "input"))
      (node (ref "C371") (pin "2") (pinfunction "2_2") (pintype "input"))
      (node (ref "C372") (pin "2") (pinfunction "2_2") (pintype "input"))
      (node (ref "C373") (pin "2") (pinfunction "2_2") (pintype "input"))
      (node (ref "C374") (pin "2") (pinfunction "2_2") (pintype "input"))
      (node (ref "C375") (pin "2") (pinfunction "2_2") (pintype "input"))
      (node (ref "C376") (pin "2") (pinfunction "2_2") (pintype "input"))
      (node (ref "C377") (pin "2") (pinfunction "2_2") (pintype "input"))
      (node (ref "C378") (pin "2") (pinfunction "2_2") (pintype "input"))
      (node (ref "C379") (pin "2") (pinfunction "2_2") (pintype "input"))
      (node (ref "C38") (pin "2") (pinfunction "2_2") (pintype "input"))
      (node (ref "C380") (pin "2") (pinfunction "2_2") (pintype "input"))
      (node (ref "C381") (pin "2") (pinfunction "2_2") (pintype "input"))
      (node (ref "C382") (pin "2") (pinfunction "2_2") (pintype "input"))
      (node (ref "C383") (pin "2") (pinfunction "2_2") (pintype "input"))
      (node (ref "C384") (pin "2") (pinfunction "2_2") (pintype "input"))
      (node (ref "C385") (pin "2") (pinfunction "2_2") (pintype "input"))
      (node (ref "C386") (pin "2") (pinfunction "2_2") (pintype "input"))
      (node (ref "C387") (pin "2") (pinfunction "2_2") (pintype "input"))
      (node (ref "C388") (pin "2") (pinfunction "2_2") (pintype "input"))
      (node (ref "C389") (pin "2") (pinfunction "2_2") (pintype "input"))
      (node (ref "C39") (pin "2") (pinfunction "2_2") (pintype "input"))
      (node (ref "C390") (pin "2") (pinfunction "2_2") (pintype "input"))
      (node (ref "C391") (pin "2") (pinfunction "2_2") (pintype "input"))
      (node (ref "C392") (pin "2") (pinfunction "2_2") (pintype "input"))
      (node (ref "C393") (pin "2") (pinfunction "2_2") (pintype "input"))
      (node (ref "C394") (pin "2") (pinfunction "2_2") (pintype "input"))
      (node (ref "C395") (pin "2") (pinfunction "2_2") (pintype "input"))
      (node (ref "C396") (pin "2") (pinfunction "2_2") (pintype "input"))
      (node (ref "C397") (pin "2") (pinfunction "2_2") (pintype "input"))
      (node (ref "C398") (pin "2") (pinfunction "2_2") (pintype "input"))
      (node (ref "C399") (pin "2") (pinfunction "2_2") (pintype "input"))
      (node (ref "C40") (pin "2") (pinfunction "2_2") (pintype "input"))
      (node (ref "C400") (pin "2") (pinfunction "2_2") (pintype "input"))
      (node (ref "C401") (pin "2") (pinfunction "2_2") (pintype "input"))
      (node (ref "C402") (pin "2") (pinfunction "2_2") (pintype "input"))
      (node (ref "C403") (pin "2") (pinfunction "2_2") (pintype "input"))
      (node (ref "C406") (pin "2") (pinfunction "2_2") (pintype "input"))
      (node (ref "C41") (pin "2") (pinfunction "2_2") (pintype "input"))
      (node (ref "C42") (pin "2") (pinfunction "2_2") (pintype "input"))
      (node (ref "C43") (pin "2") (pinfunction "2_2") (pintype "input"))
      (node (ref "C44") (pin "2") (pinfunction "2_2") (pintype "input"))
      (node (ref "C45") (pin "2") (pinfunction "2_2") (pintype "input"))
      (node (ref "C46") (pin "2") (pinfunction "2_2") (pintype "input"))
      (node (ref "C47") (pin "2") (pinfunction "2_2") (pintype "input"))
      (node (ref "C48") (pin "2") (pinfunction "2_2") (pintype "input"))
      (node (ref "C49") (pin "2") (pinfunction "2_2") (pintype "input"))
      (node (ref "C5") (pin "2") (pinfunction "2_2") (pintype "input"))
      (node (ref "C50") (pin "2") (pinfunction "2_2") (pintype "input"))
      (node (ref "C51") (pin "2") (pinfunction "2_2") (pintype "input"))
      (node (ref "C52") (pin "2") (pinfunction "2_2") (pintype "input"))
      (node (ref "C53") (pin "2") (pinfunction "2_2") (pintype "input"))
      (node (ref "C54") (pin "2") (pinfunction "2_2") (pintype "input"))
      (node (ref "C55") (pin "2") (pinfunction "2_2") (pintype "input"))
      (node (ref "C56") (pin "2") (pinfunction "2_2") (pintype "input"))
      (node (ref "C57") (pin "2") (pinfunction "2_2") (pintype "input"))
      (node (ref "C58") (pin "2") (pinfunction "2_2") (pintype "input"))
      (node (ref "C59") (pin "2") (pinfunction "2_2") (pintype "input"))
      (node (ref "C60") (pin "2") (pinfunction "2_2") (pintype "input"))
      (node (ref "C61") (pin "2") (pinfunction "2_2") (pintype "input"))
      (node (ref "C62") (pin "2") (pinfunction "2_2") (pintype "input"))
      (node (ref "C63") (pin "2") (pinfunction "2_2") (pintype "input"))
      (node (ref "C64") (pin "2") (pinfunction "2_2") (pintype "input"))
      (node (ref "C65") (pin "2") (pinfunction "2_2") (pintype "input"))
      (node (ref "C66") (pin "2") (pinfunction "2_2") (pintype "input"))
      (node (ref "C67") (pin "2") (pinfunction "2_2") (pintype "input"))
      (node (ref "C68") (pin "2") (pinfunction "2_2") (pintype "input"))
      (node (ref "C69") (pin "2") (pinfunction "2_2") (pintype "input"))
      (node (ref "C70") (pin "2") (pinfunction "2_2") (pintype "input"))
      (node (ref "C71") (pin "2") (pinfunction "2_2") (pintype "input"))
      (node (ref "C72") (pin "2") (pinfunction "2_2") (pintype "input"))
      (node (ref "C73") (pin "2") (pinfunction "2_2") (pintype "input"))
      (node (ref "C74") (pin "2") (pinfunction "2_2") (pintype "input"))
      (node (ref "C75") (pin "2") (pinfunction "2_2") (pintype "input"))
      (node (ref "C76") (pin "2") (pinfunction "2_2") (pintype "input"))
      (node (ref "C77") (pin "2") (pinfunction "2_2") (pintype "input"))
      (node (ref "C78") (pin "2") (pinfunction "2_2") (pintype "input"))
      (node (ref "C79") (pin "2") (pinfunction "2_2") (pintype "input"))
      (node (ref "C8") (pin "2") (pinfunction "2_2") (pintype "input"))
      (node (ref "C80") (pin "2") (pinfunction "2_2") (pintype "input"))
      (node (ref "C81") (pin "2") (pinfunction "2_2") (pintype "input"))
      (node (ref "C82") (pin "2") (pinfunction "2_2") (pintype "input"))
      (node (ref "C83") (pin "2") (pinfunction "2_2") (pintype "input"))
      (node (ref "C84") (pin "2") (pinfunction "2_2") (pintype "input"))
      (node (ref "C85") (pin "2") (pinfunction "2_2") (pintype "input"))
      (node (ref "C86") (pin "2") (pinfunction "2_2") (pintype "input"))
      (node (ref "C87") (pin "2") (pinfunction "2_2") (pintype "input"))
      (node (ref "C88") (pin "2") (pinfunction "2_2") (pintype "input"))
      (node (ref "C89") (pin "2") (pinfunction "2_2") (pintype "input"))
      (node (ref "C9") (pin "2") (pinfunction "2_2") (pintype "input"))
      (node (ref "C90") (pin "2") (pinfunction "2_2") (pintype "input"))
      (node (ref "C91") (pin "2") (pinfunction "2_2") (pintype "input"))
      (node (ref "C92") (pin "2") (pinfunction "2_2") (pintype "input"))
      (node (ref "C93") (pin "2") (pinfunction "2_2") (pintype "input"))
      (node (ref "C94") (pin "2") (pinfunction "2_2") (pintype "input"))
      (node (ref "C95") (pin "2") (pinfunction "2_2") (pintype "input"))
      (node (ref "C96") (pin "2") (pinfunction "2_2") (pintype "input"))
      (node (ref "C97") (pin "2") (pinfunction "2_2") (pintype "input"))
      (node (ref "C98") (pin "2") (pinfunction "2_2") (pintype "input"))
      (node (ref "C99") (pin "2") (pinfunction "2_2") (pintype "input"))
      (node (ref "CARD2") (pin "6") (pinfunction "VSS_6") (pintype "unspecified"))
      (node (ref "CN2") (pin "11") (pinfunction "TMDSClockShield_11") (pintype "unspecified"))
      (node (ref "CN2") (pin "17") (pinfunction "DDC/CECGround_17") (pintype "unspecified"))
      (node (ref "CN2") (pin "2") (pinfunction "TMDSData2Shield_2") (pintype "unspecified"))
      (node (ref "CN2") (pin "5") (pinfunction "TMDSData1Shield_5") (pintype "unspecified"))
      (node (ref "CN2") (pin "8") (pinfunction "TMDSData0Shield_8") (pintype "unspecified"))
      (node (ref "D1") (pin "1") (pinfunction "1_1") (pintype "input"))
      (node (ref "D10") (pin "1") (pinfunction "1_1") (pintype "input"))
      (node (ref "D11") (pin "1") (pinfunction "1_1") (pintype "input"))
      (node (ref "D2") (pin "1") (pinfunction "1_1") (pintype "input"))
      (node (ref "D3") (pin "1") (pinfunction "1_1") (pintype "input"))
      (node (ref "D4") (pin "1") (pinfunction "1_1") (pintype "input"))
      (node (ref "D6") (pin "1") (pinfunction "1_1") (pintype "input"))
      (node (ref "D7") (pin "1") (pinfunction "1_1") (pintype "input"))
      (node (ref "D9") (pin "1") (pinfunction "1_1") (pintype "input"))
      (node (ref "DC1") (pin "2") (pinfunction "2_2") (pintype "input"))
      (node (ref "DC1") (pin "3") (pinfunction "3_3") (pintype "input"))
      (node (ref "H4") (pin "2") (pinfunction "2_2") (pintype "input"))
      (node (ref "H5") (pin "3") (pinfunction "3_3") (pintype "unspecified"))
      (node (ref "HDR1") (pin "1") (pinfunction "GND_1") (pintype "input"))
      (node (ref "HDR1") (pin "11") (pinfunction "GND_11") (pintype "input"))
      (node (ref "HDR1") (pin "13") (pinfunction "GND_13") (pintype "input"))
      (node (ref "HDR1") (pin "3") (pinfunction "GND_3") (pintype "input"))
      (node (ref "HDR1") (pin "5") (pinfunction "GND_5") (pintype "input"))
      (node (ref "HDR1") (pin "7") (pinfunction "GND_7") (pintype "input"))
      (node (ref "HDR1") (pin "9") (pinfunction "GND_9") (pintype "input"))
      (node (ref "L3") (pin "1") (pinfunction "1_1") (pintype "input"))
      (node (ref "LED10") (pin "2") (pinfunction "C_2") (pintype "input"))
      (node (ref "Q1") (pin "2") (pinfunction "S_2") (pintype "unspecified"))
      (node (ref "Q2") (pin "2") (pinfunction "S_2") (pintype "unspecified"))
      (node (ref "Q3") (pin "2") (pinfunction "S_2") (pintype "unspecified"))
      (node (ref "Q5") (pin "2") (pinfunction "S_2") (pintype "unspecified"))
      (node (ref "Q6") (pin "2") (pinfunction "S_2") (pintype "unspecified"))
      (node (ref "Q7") (pin "2") (pinfunction "S_2") (pintype "unspecified"))
      (node (ref "Q8") (pin "2") (pinfunction "S_2") (pintype "unspecified"))
      (node (ref "R11") (pin "2") (pinfunction "2_2") (pintype "input"))
      (node (ref "R125") (pin "1") (pinfunction "1_1") (pintype "input"))
      (node (ref "R131") (pin "2") (pinfunction "2_2") (pintype "input"))
      (node (ref "R15") (pin "2") (pinfunction "2_2") (pintype "input"))
      (node (ref "R2") (pin "2") (pinfunction "2_2") (pintype "input"))
      (node (ref "R226") (pin "1") (pinfunction "1_1") (pintype "input"))
      (node (ref "R230") (pin "1") (pinfunction "1_1") (pintype "input"))
      (node (ref "R233") (pin "1") (pinfunction "1_1") (pintype "input"))
      (node (ref "R235") (pin "1") (pinfunction "1_1") (pintype "input"))
      (node (ref "R236") (pin "1") (pinfunction "1_1") (pintype "input"))
      (node (ref "R239") (pin "1") (pinfunction "1_1") (pintype "input"))
      (node (ref "R244") (pin "2") (pinfunction "2_2") (pintype "input"))
      (node (ref "R247") (pin "2") (pinfunction "2_2") (pintype "input"))
      (node (ref "R248") (pin "2") (pinfunction "2_2") (pintype "input"))
      (node (ref "R249") (pin "2") (pinfunction "2_2") (pintype "input"))
      (node (ref "R250") (pin "2") (pinfunction "2_2") (pintype "input"))
      (node (ref "R269") (pin "2") (pinfunction "2_2") (pintype "input"))
      (node (ref "R274") (pin "2") (pinfunction "2_2") (pintype "input"))
      (node (ref "R277") (pin "2") (pinfunction "2_2") (pintype "input"))
      (node (ref "R61") (pin "1") (pinfunction "1_1") (pintype "input"))
      (node (ref "R62") (pin "1") (pinfunction "1_1") (pintype "input"))
      (node (ref "R63") (pin "1") (pinfunction "1_1") (pintype "input"))
      (node (ref "R65") (pin "1") (pinfunction "1_1") (pintype "input"))
      (node (ref "R7") (pin "2") (pinfunction "2_2") (pintype "input"))
      (node (ref "R70") (pin "1") (pinfunction "1_1") (pintype "input"))
      (node (ref "R79") (pin "2") (pinfunction "2_2") (pintype "input"))
      (node (ref "R82") (pin "2") (pinfunction "2_2") (pintype "input"))
      (node (ref "R91") (pin "2") (pinfunction "2_2") (pintype "input"))
      (node (ref "R92") (pin "2") (pinfunction "2_2") (pintype "input"))
      (node (ref "R93") (pin "2") (pinfunction "2_2") (pintype "input"))
      (node (ref "RJ1") (pin "P10") (pinfunction "P10_P10") (pintype "unspecified"))
      (node (ref "SW1") (pin "3") (pinfunction "3_3") (pintype "input"))
      (node (ref "SW1") (pin "4") (pinfunction "4_4") (pintype "input"))
      (node (ref "SW2") (pin "3") (pinfunction "3_3") (pintype "input"))
      (node (ref "SW2") (pin "4") (pinfunction "4_4") (pintype "input"))
      (node (ref "U1") (pin "A9") (pinfunction "VSS_A9") (pintype "input"))
      (node (ref "U1") (pin "B1") (pinfunction "VSSQ_B1") (pintype "input"))
      (node (ref "U1") (pin "B3") (pinfunction "VSS_B3") (pintype "input"))
      (node (ref "U1") (pin "B9") (pinfunction "VSSQ_B9") (pintype "input"))
      (node (ref "U1") (pin "D1") (pinfunction "VSSQ_D1") (pintype "input"))
      (node (ref "U1") (pin "D8") (pinfunction "VSSQ_D8") (pintype "input"))
      (node (ref "U1") (pin "E1") (pinfunction "VSS_E1") (pintype "input"))
      (node (ref "U1") (pin "E2") (pinfunction "VSSQ_E2") (pintype "input"))
      (node (ref "U1") (pin "E8") (pinfunction "VSSQ_E8") (pintype "input"))
      (node (ref "U1") (pin "F9") (pinfunction "VSSQ_F9") (pintype "input"))
      (node (ref "U1") (pin "G1") (pinfunction "VSSQ_G1") (pintype "input"))
      (node (ref "U1") (pin "G8") (pinfunction "VSS_G8") (pintype "input"))
      (node (ref "U1") (pin "G9") (pinfunction "VSSQ_G9") (pintype "input"))
      (node (ref "U1") (pin "J2") (pinfunction "VSS_J2") (pintype "input"))
      (node (ref "U1") (pin "J8") (pinfunction "VSS_J8") (pintype "input"))
      (node (ref "U1") (pin "M1") (pinfunction "VSS_M1") (pintype "input"))
      (node (ref "U1") (pin "M9") (pinfunction "VSS_M9") (pintype "input"))
      (node (ref "U1") (pin "P1") (pinfunction "VSS_P1") (pintype "input"))
      (node (ref "U1") (pin "P9") (pinfunction "VSS_P9") (pintype "input"))
      (node (ref "U1") (pin "T1") (pinfunction "VSS_T1") (pintype "input"))
      (node (ref "U1") (pin "T9") (pinfunction "VSS_T9") (pintype "input"))
      (node (ref "U10") (pin "5") (pinfunction "GND_5") (pintype "input"))
      (node (ref "U10") (pin "9") (pinfunction "GND_9") (pintype "input"))
      (node (ref "U2") (pin "A15") (pinfunction "GND_A15") (pintype "unspecified"))
      (node (ref "U2") (pin "A5") (pinfunction "GND_A5") (pintype "unspecified"))
      (node (ref "U2") (pin "AA15") (pinfunction "GND_AA15") (pintype "unspecified"))
      (node (ref "U2") (pin "AA5") (pinfunction "GND_AA5") (pintype "unspecified"))
      (node (ref "U2") (pin "AB18") (pinfunction "GND_AB18") (pintype "unspecified"))
      (node (ref "U2") (pin "AB8") (pinfunction "GND_AB8") (pintype "unspecified"))
      (node (ref "U2") (pin "B18") (pinfunction "GND_B18") (pintype "unspecified"))
      (node (ref "U2") (pin "B8") (pinfunction "GND_B8") (pintype "unspecified"))
      (node (ref "U2") (pin "C1") (pinfunction "GND_C1") (pintype "unspecified"))
      (node (ref "U2") (pin "C11") (pinfunction "GND_C11") (pintype "unspecified"))
      (node (ref "U2") (pin "C21") (pinfunction "GND_C21") (pintype "unspecified"))
      (node (ref "U2") (pin "D14") (pinfunction "GND_D14") (pintype "unspecified"))
      (node (ref "U2") (pin "D4") (pinfunction "GND_D4") (pintype "unspecified"))
      (node (ref "U2") (pin "E17") (pinfunction "GND_E17") (pintype "unspecified"))
      (node (ref "U2") (pin "E7") (pinfunction "GND_E7") (pintype "unspecified"))
      (node (ref "U2") (pin "F10") (pinfunction "GND_F10") (pintype "unspecified"))
      (node (ref "U2") (pin "F20") (pinfunction "GND_F20") (pintype "unspecified"))
      (node (ref "U2") (pin "G3") (pinfunction "GND_G3") (pintype "unspecified"))
      (node (ref "U2") (pin "H12") (pinfunction "GND_H12") (pintype "unspecified"))
      (node (ref "U2") (pin "H14") (pinfunction "GND_H14") (pintype "unspecified"))
      (node (ref "U2") (pin "H16") (pinfunction "GND_H16") (pintype "unspecified"))
      (node (ref "U2") (pin "H6") (pinfunction "GND_H6") (pintype "unspecified"))
      (node (ref "U2") (pin "H8") (pinfunction "GND_H8") (pintype "unspecified"))
      (node (ref "U2") (pin "J11") (pinfunction "GND_J11") (pintype "unspecified"))
      (node (ref "U2") (pin "J13") (pinfunction "GND_J13") (pintype "unspecified"))
      (node (ref "U2") (pin "J19") (pinfunction "GND_J19") (pintype "unspecified"))
      (node (ref "U2") (pin "J9") (pinfunction "GND_J9") (pintype "unspecified"))
      (node (ref "U2") (pin "K10") (pinfunction "GND_K10") (pintype "unspecified"))
      (node (ref "U2") (pin "K14") (pinfunction "GND_K14") (pintype "unspecified"))
      (node (ref "U2") (pin "K2") (pinfunction "GND_K2") (pintype "unspecified"))
      (node (ref "U2") (pin "K22") (pinfunction "GND_K22") (pintype "unspecified"))
      (node (ref "U2") (pin "K8") (pinfunction "GND_K8") (pintype "unspecified"))
      (node (ref "U2") (pin "L11") (pinfunction "VP_0_L11") (pintype "input"))
      (node (ref "U2") (pin "L12") (pinfunction "VREFN_0_L12") (pintype "input"))
      (node (ref "U2") (pin "L13") (pinfunction "GND_L13") (pintype "unspecified"))
      (node (ref "U2") (pin "L15") (pinfunction "GND_L15") (pintype "unspecified"))
      (node (ref "U2") (pin "L5") (pinfunction "GND_L5") (pintype "unspecified"))
      (node (ref "U2") (pin "L9") (pinfunction "GND_L9") (pintype "unspecified"))
      (node (ref "U2") (pin "M10") (pinfunction "GND_M10") (pintype "unspecified"))
      (node (ref "U2") (pin "M11") (pinfunction "VREFP_0_M11") (pintype "input"))
      (node (ref "U2") (pin "M12") (pinfunction "VN_0_M12") (pintype "input"))
      (node (ref "U2") (pin "M14") (pinfunction "GND_M14") (pintype "unspecified"))
      (node (ref "U2") (pin "M18") (pinfunction "GND_M18") (pintype "unspecified"))
      (node (ref "U2") (pin "M8") (pinfunction "GND_M8") (pintype "unspecified"))
      (node (ref "U2") (pin "N1") (pinfunction "GND_N1") (pintype "unspecified"))
      (node (ref "U2") (pin "N11") (pinfunction "DXP_0_N11") (pintype "input"))
      (node (ref "U2") (pin "N12") (pinfunction "DXN_0_N12") (pintype "input"))
      (node (ref "U2") (pin "N13") (pinfunction "GND_N13") (pintype "unspecified"))
      (node (ref "U2") (pin "N21") (pinfunction "GND_N21") (pintype "unspecified"))
      (node (ref "U2") (pin "N9") (pinfunction "GND_N9") (pintype "unspecified"))
      (node (ref "U2") (pin "P10") (pinfunction "GND_P10") (pintype "unspecified"))
      (node (ref "U2") (pin "P12") (pinfunction "GND_P12") (pintype "unspecified"))
      (node (ref "U2") (pin "P14") (pinfunction "GND_P14") (pintype "unspecified"))
      (node (ref "U2") (pin "P4") (pinfunction "GND_P4") (pintype "unspecified"))
      (node (ref "U2") (pin "P8") (pinfunction "GND_P8") (pintype "unspecified"))
      (node (ref "U2") (pin "R11") (pinfunction "GND_R11") (pintype "unspecified"))
      (node (ref "U2") (pin "R13") (pinfunction "GND_R13") (pintype "unspecified"))
      (node (ref "U2") (pin "R17") (pinfunction "GND_R17") (pintype "unspecified"))
      (node (ref "U2") (pin "R9") (pinfunction "GND_R9") (pintype "unspecified"))
      (node (ref "U2") (pin "T20") (pinfunction "GND_T20") (pintype "unspecified"))
      (node (ref "U2") (pin "U13") (pinfunction "GND_U13") (pintype "unspecified"))
      (node (ref "U2") (pin "U3") (pinfunction "GND_U3") (pintype "unspecified"))
      (node (ref "U2") (pin "V16") (pinfunction "GND_V16") (pintype "unspecified"))
      (node (ref "U2") (pin "V6") (pinfunction "GND_V6") (pintype "unspecified"))
      (node (ref "U2") (pin "W19") (pinfunction "GND_W19") (pintype "unspecified"))
      (node (ref "U2") (pin "W9") (pinfunction "GND_W9") (pintype "unspecified"))
      (node (ref "U2") (pin "Y12") (pinfunction "GND_Y12") (pintype "unspecified"))
      (node (ref "U2") (pin "Y2") (pinfunction "GND_Y2") (pintype "unspecified"))
      (node (ref "U2") (pin "Y22") (pinfunction "GND_Y22") (pintype "unspecified"))
      (node (ref "U27") (pin "A1B12") (pinfunction "GND_A1B12") (pintype "unspecified"))
      (node (ref "U27") (pin "B1A12") (pinfunction "GND_B1A12") (pintype "unspecified"))
      (node (ref "U28") (pin "1") (pinfunction "1_1") (pintype "input"))
      (node (ref "U29") (pin "1") (pinfunction "1_1") (pintype "input"))
      (node (ref "U3") (pin "A9") (pinfunction "VSS_A9") (pintype "input"))
      (node (ref "U3") (pin "B1") (pinfunction "VSSQ_B1") (pintype "input"))
      (node (ref "U3") (pin "B3") (pinfunction "VSS_B3") (pintype "input"))
      (node (ref "U3") (pin "B9") (pinfunction "VSSQ_B9") (pintype "input"))
      (node (ref "U3") (pin "D1") (pinfunction "VSSQ_D1") (pintype "input"))
      (node (ref "U3") (pin "D8") (pinfunction "VSSQ_D8") (pintype "input"))
      (node (ref "U3") (pin "E1") (pinfunction "VSS_E1") (pintype "input"))
      (node (ref "U3") (pin "E2") (pinfunction "VSSQ_E2") (pintype "input"))
      (node (ref "U3") (pin "E8") (pinfunction "VSSQ_E8") (pintype "input"))
      (node (ref "U3") (pin "F9") (pinfunction "VSSQ_F9") (pintype "input"))
      (node (ref "U3") (pin "G1") (pinfunction "VSSQ_G1") (pintype "input"))
      (node (ref "U3") (pin "G8") (pinfunction "VSS_G8") (pintype "input"))
      (node (ref "U3") (pin "G9") (pinfunction "VSSQ_G9") (pintype "input"))
      (node (ref "U3") (pin "J2") (pinfunction "VSS_J2") (pintype "input"))
      (node (ref "U3") (pin "J8") (pinfunction "VSS_J8") (pintype "input"))
      (node (ref "U3") (pin "M1") (pinfunction "VSS_M1") (pintype "input"))
      (node (ref "U3") (pin "M9") (pinfunction "VSS_M9") (pintype "input"))
      (node (ref "U3") (pin "P1") (pinfunction "VSS_P1") (pintype "input"))
      (node (ref "U3") (pin "P9") (pinfunction "VSS_P9") (pintype "input"))
      (node (ref "U3") (pin "T1") (pinfunction "VSS_T1") (pintype "input"))
      (node (ref "U3") (pin "T9") (pinfunction "VSS_T9") (pintype "input"))
      (node (ref "U30") (pin "1") (pinfunction "1_1") (pintype "input"))
      (node (ref "U31") (pin "1") (pinfunction "1_1") (pintype "input"))
      (node (ref "U34") (pin "1") (pinfunction "GND_1") (pintype "input"))
      (node (ref "U34") (pin "10") (pinfunction "AGND_10") (pintype "input"))
      (node (ref "U34") (pin "11") (pinfunction "GND_11") (pintype "input"))
      (node (ref "U34") (pin "13") (pinfunction "TEST_13") (pintype "input"))
      (node (ref "U34") (pin "15") (pinfunction "GND_15") (pintype "input"))
      (node (ref "U34") (pin "25") (pinfunction "GND_25") (pintype "input"))
      (node (ref "U34") (pin "35") (pinfunction "GND_35") (pintype "input"))
      (node (ref "U34") (pin "47") (pinfunction "GND_47") (pintype "input"))
      (node (ref "U34") (pin "5") (pinfunction "GND_5") (pintype "input"))
      (node (ref "U34") (pin "51") (pinfunction "GND_51") (pintype "input"))
      (node (ref "U35") (pin "41") (pinfunction "GND_41") (pintype "unspecified"))
      (node (ref "U36") (pin "11") (pinfunction "REFSEL1_11") (pintype "input"))
      (node (ref "U36") (pin "33") (pinfunction "GND_33") (pintype "input"))
      (node (ref "U36") (pin "8") (pinfunction "REFSEL0_8") (pintype "input"))
      (node (ref "U4") (pin "5") (pinfunction "GND_5") (pintype "input"))
      (node (ref "U4") (pin "9") (pinfunction "GND_9") (pintype "input"))
      (node (ref "U44") (pin "1") (pinfunction "1_1") (pintype "input"))
      (node (ref "U44") (pin "10") (pinfunction "10_10") (pintype "input"))
      (node (ref "U44") (pin "13") (pinfunction "13_13") (pintype "input"))
      (node (ref "U44") (pin "16") (pinfunction "16_16") (pintype "input"))
      (node (ref "U44") (pin "19") (pinfunction "19_19") (pintype "input"))
      (node (ref "U44") (pin "22") (pinfunction "22_22") (pintype "input"))
      (node (ref "U44") (pin "25") (pinfunction "25_25") (pintype "input"))
      (node (ref "U44") (pin "28") (pinfunction "28_28") (pintype "input"))
      (node (ref "U44") (pin "33") (pinfunction "33_33") (pintype "input"))
      (node (ref "U44") (pin "34") (pinfunction "34_34") (pintype "input"))
      (node (ref "U44") (pin "35") (pinfunction "35_35") (pintype "input"))
      (node (ref "U44") (pin "38") (pinfunction "38_38") (pintype "input"))
      (node (ref "U44") (pin "4") (pinfunction "4_4") (pintype "input"))
      (node (ref "U44") (pin "41") (pinfunction "41_41") (pintype "input"))
      (node (ref "U44") (pin "44") (pinfunction "44_44") (pintype "input"))
      (node (ref "U44") (pin "47") (pinfunction "47_47") (pintype "input"))
      (node (ref "U44") (pin "50") (pinfunction "50_50") (pintype "input"))
      (node (ref "U44") (pin "53") (pinfunction "53_53") (pintype "input"))
      (node (ref "U44") (pin "56") (pinfunction "56_56") (pintype "input"))
      (node (ref "U44") (pin "59") (pinfunction "59_59") (pintype "input"))
      (node (ref "U44") (pin "62") (pinfunction "62_62") (pintype "input"))
      (node (ref "U44") (pin "67") (pinfunction "67_67") (pintype "input"))
      (node (ref "U44") (pin "68") (pinfunction "68_68") (pintype "input"))
      (node (ref "U44") (pin "7") (pinfunction "7_7") (pintype "input"))
      (node (ref "U44") (pin "GND1") (pinfunction "GND_GND1") (pintype "input"))
      (node (ref "U44") (pin "GND2") (pinfunction "69_GND2") (pintype "input"))
      (node (ref "U45") (pin "1") (pinfunction "1_1") (pintype "input"))
      (node (ref "U45") (pin "10") (pinfunction "10_10") (pintype "input"))
      (node (ref "U45") (pin "13") (pinfunction "13_13") (pintype "input"))
      (node (ref "U45") (pin "16") (pinfunction "16_16") (pintype "input"))
      (node (ref "U45") (pin "19") (pinfunction "19_19") (pintype "input"))
      (node (ref "U45") (pin "2") (pinfunction "2_2") (pintype "input"))
      (node (ref "U45") (pin "22") (pinfunction "22_22") (pintype "input"))
      (node (ref "U45") (pin "25") (pinfunction "25_25") (pintype "input"))
      (node (ref "U45") (pin "28") (pinfunction "28_28") (pintype "input"))
      (node (ref "U45") (pin "3") (pinfunction "3_3") (pintype "input"))
      (node (ref "U45") (pin "31") (pinfunction "31_31") (pintype "input"))
      (node (ref "U45") (pin "34") (pinfunction "34_34") (pintype "input"))
      (node (ref "U45") (pin "35") (pinfunction "35_35") (pintype "input"))
      (node (ref "U45") (pin "36") (pinfunction "36_36") (pintype "input"))
      (node (ref "U45") (pin "37") (pinfunction "37_37") (pintype "input"))
      (node (ref "U45") (pin "38") (pinfunction "38_38") (pintype "input"))
      (node (ref "U45") (pin "39") (pinfunction "39_39") (pintype "input"))
      (node (ref "U45") (pin "4") (pinfunction "4_4") (pintype "input"))
      (node (ref "U45") (pin "40") (pinfunction "40_40") (pintype "input"))
      (node (ref "U45") (pin "41") (pinfunction "41_41") (pintype "input"))
      (node (ref "U45") (pin "44") (pinfunction "44_44") (pintype "input"))
      (node (ref "U45") (pin "47") (pinfunction "47_47") (pintype "input"))
      (node (ref "U45") (pin "5") (pinfunction "5_5") (pintype "input"))
      (node (ref "U45") (pin "50") (pinfunction "50_50") (pintype "input"))
      (node (ref "U45") (pin "53") (pinfunction "53_53") (pintype "input"))
      (node (ref "U45") (pin "56") (pinfunction "56_56") (pintype "input"))
      (node (ref "U45") (pin "59") (pinfunction "59_59") (pintype "input"))
      (node (ref "U45") (pin "6") (pinfunction "6_6") (pintype "input"))
      (node (ref "U45") (pin "62") (pinfunction "62_62") (pintype "input"))
      (node (ref "U45") (pin "65") (pinfunction "65_65") (pintype "input"))
      (node (ref "U45") (pin "68") (pinfunction "68_68") (pintype "input"))
      (node (ref "U45") (pin "7") (pinfunction "7_7") (pintype "input"))
      (node (ref "U45") (pin "GND1") (pinfunction "GND_GND1") (pintype "input"))
      (node (ref "U45") (pin "GND2") (pinfunction "69_GND2") (pintype "input"))
      (node (ref "U6") (pin "5") (pinfunction "GND_5") (pintype "input"))
      (node (ref "U6") (pin "9") (pinfunction "GND_9") (pintype "input"))
      (node (ref "U60") (pin "5") (pinfunction "VSS_5") (pintype "input"))
      (node (ref "U61") (pin "3") (pinfunction "GND_3") (pintype "input"))
      (node (ref "U63") (pin "4") (pinfunction "GND_4") (pintype "unspecified"))
      (node (ref "U63") (pin "9") (pinfunction "EP_9") (pintype "unspecified"))
      (node (ref "U64") (pin "1") (pinfunction "1_1") (pintype "input"))
      (node (ref "U65") (pin "1") (pinfunction "1_1") (pintype "input"))
      (node (ref "U68") (pin "1") (pinfunction "GND_1") (pintype "input"))
      (node (ref "U70") (pin "2") (pinfunction "GND_2") (pintype "unspecified"))
      (node (ref "U72") (pin "2") (pinfunction "Gnd_2") (pintype "input"))
      (node (ref "U73") (pin "5") (pinfunction "GND_5") (pintype "input"))
      (node (ref "U73") (pin "7") (pinfunction "EP_7") (pintype "input"))
      (node (ref "U74") (pin "11") (pinfunction "GND_11") (pintype "unspecified"))
      (node (ref "U74") (pin "2") (pinfunction "GND_2") (pintype "unspecified"))
      (node (ref "U74") (pin "25") (pinfunction "EP_25") (pintype "unspecified"))
      (node (ref "U78") (pin "14") (pinfunction "GND_14") (pintype "unspecified"))
      (node (ref "U78") (pin "19") (pinfunction "GND_19") (pintype "unspecified"))
      (node (ref "U78") (pin "6") (pinfunction "GND_6") (pintype "unspecified"))
      (node (ref "U79") (pin "2") (pinfunction "2_2") (pintype "input"))
      (node (ref "U8") (pin "5") (pinfunction "GND_5") (pintype "input"))
      (node (ref "U8") (pin "9") (pinfunction "GND_9") (pintype "input"))
      (node (ref "U80") (pin "2") (pinfunction "2_2") (pintype "input"))
      (node (ref "USB1") (pin "5") (pinfunction "GND_5") (pintype "unspecified"))
      (node (ref "X1") (pin "2") (pinfunction "Gnd_2") (pintype "input"))
      (node (ref "X2") (pin "2") (pinfunction "Gnd_2") (pintype "input"))
    )
    (net (code "146") (name "HDMI_RX_CEC") (class "Default")
      (node (ref "U2") (pin "B20") (pinfunction "IO_L13N_T2_MRCC_35_B20") (pintype "bidirectional"))
      (node (ref "U45") (pin "9") (pinfunction "9_9") (pintype "input"))
    )
    (net (code "147") (name "HDMI_RX_CLK_N") (class "Default")
      (node (ref "U2") (pin "M20") (pinfunction "IO_L13N_T2_MRCC_34_M20") (pintype "bidirectional"))
      (node (ref "U45") (pin "11") (pinfunction "11_11") (pintype "input"))
    )
    (net (code "148") (name "HDMI_RX_CLK_P") (class "Default")
      (node (ref "U2") (pin "M19") (pinfunction "IO_L13P_T2_MRCC_34_M19") (pintype "bidirectional"))
      (node (ref "U45") (pin "45") (pinfunction "45_45") (pintype "input"))
    )
    (net (code "149") (name "HDMI_RX_D0_N") (class "Default")
      (node (ref "U2") (pin "P22") (pinfunction "IO_L16N_T2_34_P22") (pintype "bidirectional"))
      (node (ref "U45") (pin "15") (pinfunction "15_15") (pintype "input"))
    )
    (net (code "150") (name "HDMI_RX_D0_P") (class "Default")
      (node (ref "U2") (pin "N22") (pinfunction "IO_L16P_T2_34_N22") (pintype "bidirectional"))
      (node (ref "U45") (pin "49") (pinfunction "49_49") (pintype "input"))
    )
    (net (code "151") (name "HDMI_RX_D1_N") (class "Default")
      (node (ref "U2") (pin "M22") (pinfunction "IO_L15N_T2_DQS_34_M22") (pintype "bidirectional"))
      (node (ref "U45") (pin "14") (pinfunction "14_14") (pintype "input"))
    )
    (net (code "152") (name "HDMI_RX_D1_P") (class "Default")
      (node (ref "U2") (pin "M21") (pinfunction "IO_L15P_T2_DQS_34_M21") (pintype "bidirectional"))
      (node (ref "U45") (pin "48") (pinfunction "48_48") (pintype "input"))
    )
    (net (code "153") (name "HDMI_RX_D2_N") (class "Default")
      (node (ref "U2") (pin "N20") (pinfunction "IO_L14N_T2_SRCC_34_N20") (pintype "bidirectional"))
      (node (ref "U45") (pin "12") (pinfunction "12_12") (pintype "input"))
    )
    (net (code "154") (name "HDMI_RX_D2_P") (class "Default")
      (node (ref "U2") (pin "N19") (pinfunction "IO_L14P_T2_SRCC_34_N19") (pintype "bidirectional"))
      (node (ref "U45") (pin "46") (pinfunction "46_46") (pintype "input"))
    )
    (net (code "155") (name "HDMI_RX_HPD") (class "Default")
      (node (ref "U2") (pin "R15") (pinfunction "IO_25_34_R15") (pintype "bidirectional"))
      (node (ref "U45") (pin "43") (pinfunction "43_43") (pintype "input"))
    )
    (net (code "156") (name "HDMI_RX_SCL") (class "Default")
      (node (ref "U2") (pin "K19") (pinfunction "IO_L11P_T1_SRCC_34_K19") (pintype "bidirectional"))
      (node (ref "U45") (pin "8") (pinfunction "8_8") (pintype "input"))
    )
    (net (code "157") (name "HDMI_RX_SDA") (class "Default")
      (node (ref "U2") (pin "K20") (pinfunction "IO_L11N_T1_SRCC_34_K20") (pintype "bidirectional"))
      (node (ref "U45") (pin "42") (pinfunction "42_42") (pintype "input"))
    )
    (net (code "158") (name "HDMI_TX_5V_CONN") (class "Default")
      (node (ref "C243") (pin "2") (pinfunction "2_2") (pintype "input"))
      (node (ref "CN2") (pin "18") (pinfunction "+5VPower_18") (pintype "unspecified"))
      (node (ref "U78") (pin "13") (pinfunction "5V_OUT_13") (pintype "unspecified"))
    )
    (net (code "159") (name "HDMI_TX_CEC") (class "Default")
      (node (ref "U2") (pin "H20") (pinfunction "IO_L19N_T3_VREF_35_H20") (pintype "bidirectional"))
      (node (ref "U78") (pin "1") (pinfunction "CEC_A_1") (pintype "unspecified"))
    )
    (net (code "160") (name "HDMI_TX_CEC_CONN") (class "Default")
      (node (ref "CN2") (pin "13") (pinfunction "CEC_13") (pintype "unspecified"))
      (node (ref "U78") (pin "7") (pinfunction "CEC_B_7") (pintype "unspecified"))
    )
    (net (code "161") (name "HDMI_TX_CLK_N") (class "Default")
      (node (ref "CN2") (pin "12") (pinfunction "TMDSClock-_12") (pintype "unspecified"))
      (node (ref "R185") (pin "1") (pinfunction "1_1") (pintype "input"))
      (node (ref "U2") (pin "C18") (pinfunction "IO_L11N_T1_SRCC_35_C18") (pintype "bidirectional"))
      (node (ref "U78") (pin "15") (pinfunction "CLK-_15") (pintype "unspecified"))
    )
    (net (code "162") (name "HDMI_TX_CLK_P") (class "Default")
      (node (ref "CN2") (pin "10") (pinfunction "TMDSClock+_10") (pintype "unspecified"))
      (node (ref "R186") (pin "1") (pinfunction "1_1") (pintype "input"))
      (node (ref "U2") (pin "C17") (pinfunction "IO_L11P_T1_SRCC_35_C17") (pintype "bidirectional"))
      (node (ref "U78") (pin "16") (pinfunction "CLK+_16") (pintype "unspecified"))
    )
    (net (code "163") (name "HDMI_TX_CT_HPD") (class "Default")
      (node (ref "R176") (pin "1") (pinfunction "1_1") (pintype "input"))
      (node (ref "U78") (pin "12") (pinfunction "CT_HPD_12") (pintype "unspecified"))
    )
    (net (code "164") (name "HDMI_TX_D0_N") (class "Default")
      (node (ref "CN2") (pin "9") (pinfunction "TMDSData0-_9") (pintype "unspecified"))
      (node (ref "R187") (pin "1") (pinfunction "1_1") (pintype "input"))
      (node (ref "U2") (pin "C19") (pinfunction "IO_L12N_T1_MRCC_35_C19") (pintype "bidirectional"))
      (node (ref "U78") (pin "17") (pinfunction "D0-_17") (pintype "unspecified"))
    )
    (net (code "165") (name "HDMI_TX_D0_P") (class "Default")
      (node (ref "CN2") (pin "7") (pinfunction "TMDSData0+_7") (pintype "unspecified"))
      (node (ref "R188") (pin "1") (pinfunction "1_1") (pintype "input"))
      (node (ref "U2") (pin "D18") (pinfunction "IO_L12P_T1_MRCC_35_D18") (pintype "bidirectional"))
      (node (ref "U78") (pin "18") (pinfunction "D0+_18") (pintype "unspecified"))
    )
    (net (code "166") (name "HDMI_TX_D1_N") (class "Default")
      (node (ref "CN2") (pin "6") (pinfunction "TMDSData1-_6") (pintype "unspecified"))
      (node (ref "R189") (pin "1") (pinfunction "1_1") (pintype "input"))
      (node (ref "U2") (pin "A19") (pinfunction "IO_L10N_T1_AD11N_35_A19") (pintype "bidirectional"))
      (node (ref "U78") (pin "20") (pinfunction "D1-_20") (pintype "unspecified"))
    )
    (net (code "167") (name "HDMI_TX_D1_P") (class "Default")
      (node (ref "CN2") (pin "4") (pinfunction "TMDSData1+_4") (pintype "unspecified"))
      (node (ref "R190") (pin "1") (pinfunction "1_1") (pintype "input"))
      (node (ref "U2") (pin "A18") (pinfunction "IO_L10P_T1_AD11P_35_A18") (pintype "bidirectional"))
      (node (ref "U78") (pin "21") (pinfunction "D1+_21") (pintype "unspecified"))
    )
    (net (code "168") (name "HDMI_TX_D2_N") (class "Default")
      (node (ref "CN2") (pin "3") (pinfunction "TMDSData2-_3") (pintype "unspecified"))
      (node (ref "R191") (pin "1") (pinfunction "1_1") (pintype "input"))
      (node (ref "U2") (pin "C20") (pinfunction "IO_L14N_T2_AD4N_SRCC_35_C20") (pintype "bidirectional"))
      (node (ref "U78") (pin "22") (pinfunction "D2-_22") (pintype "unspecified"))
    )
    (net (code "169") (name "HDMI_TX_D2_P") (class "Default")
      (node (ref "CN2") (pin "1") (pinfunction "TMDSData2+_1") (pintype "unspecified"))
      (node (ref "R192") (pin "1") (pinfunction "1_1") (pintype "input"))
      (node (ref "U2") (pin "D20") (pinfunction "IO_L14P_T2_AD4P_SRCC_35_D20") (pintype "bidirectional"))
      (node (ref "U78") (pin "23") (pinfunction "D2+_23") (pintype "unspecified"))
    )
    (net (code "170") (name "HDMI_TX_HPD") (class "Default")
      (node (ref "U2") (pin "H15") (pinfunction "IO_0_34_H15") (pintype "bidirectional"))
      (node (ref "U78") (pin "4") (pinfunction "HPD_A-_4") (pintype "unspecified"))
      (node (ref "U78") (pin "5") (pinfunction "LS_OE_5") (pintype "unspecified"))
    )
    (net (code "171") (name "HDMI_TX_HPD_CONN") (class "Default")
      (node (ref "CN2") (pin "19") (pinfunction "HotPlugDetect_19") (pintype "unspecified"))
      (node (ref "U78") (pin "10") (pinfunction "HPD_B-_10") (pintype "unspecified"))
    )
    (net (code "172") (name "HDMI_TX_SCL") (class "Default")
      (node (ref "U2") (pin "B16") (pinfunction "IO_L8P_T1_AD10P_35_B16") (pintype "bidirectional"))
      (node (ref "U78") (pin "2") (pinfunction "SCL_A_2") (pintype "unspecified"))
    )
    (net (code "173") (name "HDMI_TX_SCL_CONN") (class "Default")
      (node (ref "CN2") (pin "15") (pinfunction "SCL_15") (pintype "unspecified"))
      (node (ref "U78") (pin "8") (pinfunction "SCL_B_8") (pintype "unspecified"))
    )
    (net (code "174") (name "HDMI_TX_SDA") (class "Default")
      (node (ref "U2") (pin "B17") (pinfunction "IO_L8N_T1_AD10N_35_B17") (pintype "bidirectional"))
      (node (ref "U78") (pin "3") (pinfunction "SDA_A_3") (pintype "unspecified"))
    )
    (net (code "175") (name "HDMI_TX_SDA_CONN") (class "Default")
      (node (ref "CN2") (pin "16") (pinfunction "SDA_16") (pintype "unspecified"))
      (node (ref "U78") (pin "9") (pinfunction "SDA_B_9") (pintype "unspecified"))
    )
    (net (code "176") (name "INITB") (class "Default")
      (node (ref "R50") (pin "1") (pinfunction "1_1") (pintype "input"))
      (node (ref "U2") (pin "T14") (pinfunction "INIT_B_0_T14") (pintype "bidirectional"))
    )
    (net (code "177") (name "IO_0_33") (class "Default")
      (node (ref "U2") (pin "U19") (pinfunction "IO_0_33_U19") (pintype "bidirectional"))
      (node (ref "U45") (pin "52") (pinfunction "52_52") (pintype "input"))
    )
    (net (code "178") (name "IO_25_13") (class "Default")
      (node (ref "U2") (pin "U7") (pinfunction "IO_25_13_U7") (pintype "bidirectional"))
      (node (ref "U44") (pin "60") (pinfunction "60_60") (pintype "input"))
    )
    (net (code "179") (name "IO_L1N_T0_33") (class "Default")
      (node (ref "U2") (pin "U21") (pinfunction "IO_L1N_T0_33_U21") (pintype "bidirectional"))
      (node (ref "U45") (pin "54") (pinfunction "54_54") (pintype "input"))
    )
    (net (code "180") (name "IO_L1P_T0_33") (class "Default")
      (node (ref "U2") (pin "T21") (pinfunction "IO_L1P_T0_33_T21") (pintype "bidirectional"))
      (node (ref "U45") (pin "51") (pinfunction "51_51") (pintype "input"))
    )
    (net (code "181") (name "IO_L2N_T0_33") (class "Default")
      (node (ref "U2") (pin "U22") (pinfunction "IO_L2N_T0_33_U22") (pintype "bidirectional"))
      (node (ref "U45") (pin "20") (pinfunction "20_20") (pintype "input"))
    )
    (net (code "182") (name "IO_L2P_T0_33") (class "Default")
      (node (ref "U2") (pin "T22") (pinfunction "IO_L2P_T0_33_T22") (pintype "bidirectional"))
      (node (ref "U45") (pin "17") (pinfunction "17_17") (pintype "input"))
    )
    (net (code "183") (name "IO_L3N_T0_DQS_33") (class "Default")
      (node (ref "U2") (pin "W22") (pinfunction "IO_L3N_T0_DQS_33_W22") (pintype "bidirectional"))
      (node (ref "U45") (pin "60") (pinfunction "60_60") (pintype "input"))
    )
    (net (code "184") (name "IO_L3P_T0_DQS_33") (class "Default")
      (node (ref "U2") (pin "V22") (pinfunction "IO_L3P_T0_DQS_33_V22") (pintype "bidirectional"))
      (node (ref "U45") (pin "23") (pinfunction "23_23") (pintype "input"))
    )
    (net (code "185") (name "IO_L4N_T0_33") (class "Default")
      (node (ref "U2") (pin "W21") (pinfunction "IO_L4N_T0_33_W21") (pintype "bidirectional"))
      (node (ref "U45") (pin "24") (pinfunction "24_24") (pintype "input"))
    )
    (net (code "186") (name "IO_L4P_T0_33") (class "Default")
      (node (ref "U2") (pin "W20") (pinfunction "IO_L4P_T0_33_W20") (pintype "bidirectional"))
      (node (ref "U45") (pin "58") (pinfunction "58_58") (pintype "input"))
    )
    (net (code "187") (name "IO_L5N_T0_33") (class "Default")
      (node (ref "U2") (pin "V20") (pinfunction "IO_L5N_T0_33_V20") (pintype "bidirectional"))
      (node (ref "U45") (pin "57") (pinfunction "57_57") (pintype "input"))
    )
    (net (code "188") (name "IO_L5P_T0_33") (class "Default")
      (node (ref "U2") (pin "U20") (pinfunction "IO_L5P_T0_33_U20") (pintype "bidirectional"))
      (node (ref "U45") (pin "18") (pinfunction "18_18") (pintype "input"))
    )
    (net (code "189") (name "IO_L6N_T0_VREF_33") (class "Default")
      (node (ref "U2") (pin "V19") (pinfunction "IO_L6N_T0_VREF_33_V19") (pintype "bidirectional"))
      (node (ref "U45") (pin "21") (pinfunction "21_21") (pintype "input"))
    )
    (net (code "190") (name "IO_L6P_T0_33") (class "Default")
      (node (ref "U2") (pin "V18") (pinfunction "IO_L6P_T0_33_V18") (pintype "bidirectional"))
      (node (ref "U45") (pin "55") (pinfunction "55_55") (pintype "input"))
    )
    (net (code "191") (name "IO_L7N_T1_13") (class "Default")
      (node (ref "U2") (pin "AB12") (pinfunction "IO_L7N_T1_13_AB12") (pintype "bidirectional"))
      (node (ref "U44") (pin "36") (pinfunction "36_36") (pintype "input"))
    )
    (net (code "192") (name "IO_L7P_T1_13") (class "Default")
      (node (ref "U2") (pin "AA12") (pinfunction "IO_L7P_T1_13_AA12") (pintype "bidirectional"))
      (node (ref "U44") (pin "2") (pinfunction "2_2") (pintype "input"))
    )
    (net (code "193") (name "IO_L8N_T1_13") (class "Default")
      (node (ref "U2") (pin "AB11") (pinfunction "IO_L8N_T1_13_AB11") (pintype "bidirectional"))
      (node (ref "U44") (pin "37") (pinfunction "37_37") (pintype "input"))
    )
    (net (code "194") (name "IO_L8P_T1_13") (class "Default")
      (node (ref "U2") (pin "AA11") (pinfunction "IO_L8P_T1_13_AA11") (pintype "bidirectional"))
      (node (ref "U44") (pin "3") (pinfunction "3_3") (pintype "input"))
    )
    (net (code "195") (name "IO_L8P_T1_33") (class "Default")
      (node (ref "U2") (pin "AA21") (pinfunction "IO_L8P_T1_33_AA21") (pintype "bidirectional"))
      (node (ref "U45") (pin "29") (pinfunction "29_29") (pintype "input"))
    )
    (net (code "196") (name "IO_L9N_T1_33") (class "Default")
      (node (ref "U2") (pin "Y21") (pinfunction "IO_L9N_T1_DQS_33_Y21") (pintype "bidirectional"))
      (node (ref "U45") (pin "26") (pinfunction "26_26") (pintype "input"))
    )
    (net (code "197") (name "IO_L9N_T1_DQS_13") (class "Default")
      (node (ref "U2") (pin "AB9") (pinfunction "IO_L9N_T1_DQS_13_AB9") (pintype "bidirectional"))
      (node (ref "U44") (pin "6") (pinfunction "6_6") (pintype "input"))
    )
    (net (code "198") (name "IO_L9P_T1_33") (class "Default")
      (node (ref "U2") (pin "Y20") (pinfunction "IO_L9P_T1_DQS_33_Y20") (pintype "bidirectional"))
      (node (ref "U45") (pin "61") (pinfunction "61_61") (pintype "input"))
    )
    (net (code "199") (name "IO_L9P_T1_DQS_13") (class "Default")
      (node (ref "U2") (pin "AB10") (pinfunction "IO_L9P_T1_DQS_13_AB10") (pintype "bidirectional"))
      (node (ref "U44") (pin "5") (pinfunction "5_5") (pintype "input"))
    )
    (net (code "200") (name "IO_L10N_T1_13") (class "Default")
      (node (ref "U2") (pin "Y10") (pinfunction "IO_L10N_T1_13_Y10") (pintype "bidirectional"))
      (node (ref "U44") (pin "40") (pinfunction "40_40") (pintype "input"))
    )
    (net (code "201") (name "IO_L10P_T1_13") (class "Default")
      (node (ref "U2") (pin "Y11") (pinfunction "IO_L10P_T1_13_Y11") (pintype "bidirectional"))
      (node (ref "U44") (pin "39") (pinfunction "39_39") (pintype "input"))
    )
    (net (code "202") (name "IO_L11N_T1_SRCC_13") (class "Default")
      (node (ref "U2") (pin "AA8") (pinfunction "IO_L11N_T1_SRCC_13_AA8") (pintype "bidirectional"))
      (node (ref "U44") (pin "43") (pinfunction "43_43") (pintype "input"))
    )
    (net (code "203") (name "IO_L11N_T1_SRCC_33") (class "Default")
      (node (ref "U2") (pin "AA19") (pinfunction "IO_L11N_T1_SRCC_33_AA19") (pintype "bidirectional"))
      (node (ref "U45") (pin "64") (pinfunction "64_64") (pintype "input"))
    )
    (net (code "204") (name "IO_L11P_T1_SRCC_13") (class "Default")
      (node (ref "U2") (pin "AA9") (pinfunction "IO_L11P_T1_SRCC_13_AA9") (pintype "bidirectional"))
      (node (ref "U44") (pin "42") (pinfunction "42_42") (pintype "input"))
    )
    (net (code "205") (name "IO_L11P_T1_SRCC_33") (class "Default")
      (node (ref "U2") (pin "Y19") (pinfunction "IO_L11P_T1_SRCC_33_Y19") (pintype "bidirectional"))
      (node (ref "U45") (pin "27") (pinfunction "27_27") (pintype "input"))
    )
    (net (code "206") (name "IO_L12N_T1_MRCC_33") (class "Default")
      (node (ref "U2") (pin "AA18") (pinfunction "IO_L12N_T1_MRCC_33_AA18") (pintype "bidirectional"))
      (node (ref "U45") (pin "30") (pinfunction "30_30") (pintype "input"))
    )
    (net (code "207") (name "IO_L12N_T1_SRCC_13") (class "Default")
      (node (ref "U2") (pin "Y8") (pinfunction "IO_L12N_T1_MRCC_13_Y8") (pintype "bidirectional"))
      (node (ref "U44") (pin "9") (pinfunction "9_9") (pintype "input"))
    )
    (net (code "208") (name "IO_L12P_T1_MRCC_33") (class "Default")
      (node (ref "U2") (pin "Y18") (pinfunction "IO_L12P_T1_MRCC_33_Y18") (pintype "bidirectional"))
      (node (ref "U45") (pin "63") (pinfunction "63_63") (pintype "input"))
    )
    (net (code "209") (name "IO_L12P_T1_SRCC_13") (class "Default")
      (node (ref "U2") (pin "Y9") (pinfunction "IO_L12P_T1_MRCC_13_Y9") (pintype "bidirectional"))
      (node (ref "U44") (pin "8") (pinfunction "8_8") (pintype "input"))
    )
    (net (code "210") (name "IO_L13N_T2_MRCC_13") (class "Default")
      (node (ref "U2") (pin "Y5") (pinfunction "IO_L13N_T2_MRCC_13_Y5") (pintype "bidirectional"))
      (node (ref "U44") (pin "49") (pinfunction "49_49") (pintype "input"))
    )
    (net (code "211") (name "IO_L13P_T2_MRCC_13") (class "Default")
      (node (ref "U2") (pin "Y6") (pinfunction "IO_L13P_T2_MRCC_13_Y6") (pintype "bidirectional"))
      (node (ref "U44") (pin "48") (pinfunction "48_48") (pintype "input"))
    )
    (net (code "212") (name "IO_L14N_T2_SRCC_13") (class "Default")
      (node (ref "U2") (pin "AA6") (pinfunction "IO_L14N_T2_SRCC_13_AA6") (pintype "bidirectional"))
      (node (ref "U44") (pin "12") (pinfunction "12_12") (pintype "input"))
    )
    (net (code "213") (name "IO_L14P_T2_SRCC_13") (class "Default")
      (node (ref "U2") (pin "AA7") (pinfunction "IO_L14P_T2_SRCC_13_AA7") (pintype "bidirectional"))
      (node (ref "U44") (pin "11") (pinfunction "11_11") (pintype "input"))
    )
    (net (code "214") (name "IO_L15N_T2_DQS_13") (class "Default")
      (node (ref "U2") (pin "AB1") (pinfunction "IO_L15N_T2_DQS_13_AB1") (pintype "bidirectional"))
      (node (ref "U44") (pin "18") (pinfunction "18_18") (pintype "input"))
    )
    (net (code "215") (name "IO_L15P_T2_DQS_13") (class "Default")
      (node (ref "U2") (pin "AB2") (pinfunction "IO_L15P_T2_DQS_13_AB2") (pintype "bidirectional"))
      (node (ref "U44") (pin "52") (pinfunction "52_52") (pintype "input"))
    )
    (net (code "216") (name "IO_L16N_T2_13") (class "Default")
      (node (ref "U2") (pin "AB4") (pinfunction "IO_L16N_T2_13_AB4") (pintype "bidirectional"))
      (node (ref "U44") (pin "15") (pinfunction "15_15") (pintype "input"))
    )
    (net (code "217") (name "IO_L16P_T2_13") (class "Default")
      (node (ref "U2") (pin "AB5") (pinfunction "IO_L16P_T2_13_AB5") (pintype "bidirectional"))
      (node (ref "U44") (pin "14") (pinfunction "14_14") (pintype "input"))
    )
    (net (code "218") (name "IO_L17N_T2_13") (class "Default")
      (node (ref "U2") (pin "AB6") (pinfunction "IO_L17N_T2_13_AB6") (pintype "bidirectional"))
      (node (ref "U44") (pin "46") (pinfunction "46_46") (pintype "input"))
    )
    (net (code "219") (name "IO_L17P_T2_13") (class "Default")
      (node (ref "U2") (pin "AB7") (pinfunction "IO_L17P_T2_13_AB7") (pintype "bidirectional"))
      (node (ref "U44") (pin "45") (pinfunction "45_45") (pintype "input"))
    )
    (net (code "220") (name "IO_L18N_T2_13") (class "Default")
      (node (ref "U2") (pin "AA4") (pinfunction "IO_L18N_T2_13_AA4") (pintype "bidirectional"))
      (node (ref "U44") (pin "51") (pinfunction "51_51") (pintype "input"))
    )
    (net (code "221") (name "IO_L18P_T2_13") (class "Default")
      (node (ref "U2") (pin "Y4") (pinfunction "IO_L18P_T2_13_Y4") (pintype "bidirectional"))
      (node (ref "U44") (pin "17") (pinfunction "17_17") (pintype "input"))
    )
    (net (code "222") (name "IO_L19N_T3_VREF_13") (class "Default")
      (node (ref "U2") (pin "T6") (pinfunction "IO_L19N_T3_VREF_13_T6") (pintype "bidirectional"))
      (node (ref "U44") (pin "61") (pinfunction "61_61") (pintype "input"))
    )
    (net (code "223") (name "IO_L19P_T3_13") (class "Default")
      (node (ref "U2") (pin "R6") (pinfunction "IO_L19P_T3_13_R6") (pintype "bidirectional"))
      (node (ref "U44") (pin "63") (pinfunction "63_63") (pintype "input"))
    )
    (net (code "224") (name "IO_L20N_T3_13") (class "Default")
      (node (ref "U2") (pin "U4") (pinfunction "IO_L20N_T3_13_U4") (pintype "bidirectional"))
      (node (ref "U44") (pin "24") (pinfunction "24_24") (pintype "input"))
    )
    (net (code "225") (name "IO_L20P_T3_13") (class "Default")
      (node (ref "U2") (pin "T4") (pinfunction "IO_L20P_T3_13_T4") (pintype "bidirectional"))
      (node (ref "U44") (pin "27") (pinfunction "27_27") (pintype "input"))
    )
    (net (code "226") (name "IO_L21N_T3_DQS_13") (class "Default")
      (node (ref "U2") (pin "V4") (pinfunction "IO_L21N_T3_DQS_13_V4") (pintype "bidirectional"))
      (node (ref "U44") (pin "55") (pinfunction "55_55") (pintype "input"))
    )
    (net (code "227") (name "IO_L21P_T3_DQS_13") (class "Default")
      (node (ref "U2") (pin "V5") (pinfunction "IO_L21P_T3_DQS_13_V5") (pintype "bidirectional"))
      (node (ref "U44") (pin "23") (pinfunction "23_23") (pintype "input"))
    )
    (net (code "228") (name "IO_L22N_T3_13") (class "Default")
      (node (ref "U2") (pin "U5") (pinfunction "IO_L22N_T3_13_U5") (pintype "bidirectional"))
      (node (ref "U44") (pin "58") (pinfunction "58_58") (pintype "input"))
    )
    (net (code "229") (name "IO_L22P_T3_13") (class "Default")
      (node (ref "U2") (pin "U6") (pinfunction "IO_L22P_T3_13_U6") (pintype "bidirectional"))
      (node (ref "U44") (pin "26") (pinfunction "26_26") (pintype "input"))
    )
    (net (code "230") (name "IO_L23N_T3_13") (class "Default")
      (node (ref "U2") (pin "W7") (pinfunction "IO_L23N_T3_13_W7") (pintype "bidirectional"))
      (node (ref "U44") (pin "21") (pinfunction "21_21") (pintype "input"))
    )
    (net (code "231") (name "IO_L23P_T3_13") (class "Default")
      (node (ref "U2") (pin "V7") (pinfunction "IO_L23P_T3_13_V7") (pintype "bidirectional"))
      (node (ref "U44") (pin "57") (pinfunction "57_57") (pintype "input"))
    )
    (net (code "232") (name "IO_L24N_T3_13") (class "Default")
      (node (ref "U2") (pin "W5") (pinfunction "IO_L24N_T3_13_W5") (pintype "bidirectional"))
      (node (ref "U44") (pin "20") (pinfunction "20_20") (pintype "input"))
    )
    (net (code "233") (name "IO_L24P_T3_13") (class "Default")
      (node (ref "U2") (pin "W6") (pinfunction "IO_L24P_T3_13_W6") (pintype "bidirectional"))
      (node (ref "U44") (pin "54") (pinfunction "54_54") (pintype "input"))
    )
    (net (code "234") (name "MDI0_N") (class "Default")
      (node (ref "RJ1") (pin "P3") (pinfunction "MDI0-_P3") (pintype "unspecified"))
      (node (ref "U35") (pin "2") (pinfunction "MDIN0_2") (pintype "unspecified"))
    )
    (net (code "235") (name "MDI0_P") (class "Default")
      (node (ref "RJ1") (pin "P2") (pinfunction "MDI0+_P2") (pintype "unspecified"))
      (node (ref "U35") (pin "1") (pinfunction "MDIP0_1") (pintype "unspecified"))
    )
    (net (code "236") (name "MDI1_N") (class "Default")
      (node (ref "RJ1") (pin "P7") (pinfunction "MDI1-_P7") (pintype "unspecified"))
      (node (ref "U35") (pin "5") (pinfunction "MDIN1_5") (pintype "unspecified"))
    )
    (net (code "237") (name "MDI1_P") (class "Default")
      (node (ref "RJ1") (pin "P4") (pinfunction "MDI1+_P4") (pintype "unspecified"))
      (node (ref "U35") (pin "4") (pinfunction "MDIP1_4") (pintype "unspecified"))
    )
    (net (code "238") (name "MDI2_N") (class "Default")
      (node (ref "RJ1") (pin "P6") (pinfunction "MDI2-_P6") (pintype "unspecified"))
      (node (ref "U35") (pin "7") (pinfunction "MDIN2_7") (pintype "unspecified"))
    )
    (net (code "239") (name "MDI2_P") (class "Default")
      (node (ref "RJ1") (pin "P5") (pinfunction "MDI2+_P5") (pintype "unspecified"))
      (node (ref "U35") (pin "6") (pinfunction "MDIP2_6") (pintype "unspecified"))
    )
    (net (code "240") (name "MDI3_N") (class "Default")
      (node (ref "RJ1") (pin "P9") (pinfunction "MDI3-_P9") (pintype "unspecified"))
      (node (ref "U35") (pin "10") (pinfunction "MDIN3_10") (pintype "unspecified"))
    )
    (net (code "241") (name "MDI3_P") (class "Default")
      (node (ref "RJ1") (pin "P8") (pinfunction "MDI3+_P8") (pintype "unspecified"))
      (node (ref "U35") (pin "9") (pinfunction "MDIP3_9") (pintype "unspecified"))
    )
    (net (code "242") (name "MIO_VREF_0V9") (class "Default")
      (node (ref "C406") (pin "1") (pinfunction "1_1") (pintype "input"))
      (node (ref "R78") (pin "2") (pinfunction "2_2") (pintype "input"))
      (node (ref "R79") (pin "1") (pinfunction "1_1") (pintype "input"))
      (node (ref "U2") (pin "F8") (pinfunction "PS_MIO_VREF_501_F8") (pintype "input"))
    )
    (net (code "243") (name "NPUDC") (class "Default")
      (node (ref "R46") (pin "1") (pinfunction "1_1") (pintype "input"))
      (node (ref "U2") (pin "K16") (pinfunction "IO_L3P_T0_DQS_PUDC_B_34_K16") (pintype "bidirectional"))
    )
    (net (code "244") (name "Net-(D8-A)") (class "Default")
      (node (ref "C182") (pin "1") (pinfunction "1_1") (pintype "input"))
      (node (ref "D8") (pin "2") (pinfunction "A_2") (pintype "input"))
      (node (ref "L9") (pin "2") (pinfunction "2_2") (pintype "input"))
      (node (ref "R69") (pin "2") (pinfunction "2_2") (pintype "input"))
    )
    (net (code "245") (name "Net-(D12-K)") (class "Default")
      (node (ref "C227") (pin "1") (pinfunction "1_1") (pintype "input"))
      (node (ref "D12") (pin "1") (pinfunction "K_1") (pintype "input"))
      (node (ref "L12") (pin "1") (pinfunction "1_1") (pintype "input"))
      (node (ref "R234") (pin "2") (pinfunction "2_2") (pintype "input"))
    )
    (net (code "246") (name "Net-(D13-K)") (class "Default")
      (node (ref "D13") (pin "1") (pinfunction "K_1") (pintype "input"))
      (node (ref "F2") (pin "1") (pinfunction "1_1") (pintype "input"))
    )
    (net (code "247") (name "Net-(HDR1-TCK)") (class "Default")
      (node (ref "D3") (pin "2") (pinfunction "2_2") (pintype "input"))
      (node (ref "HDR1") (pin "6") (pinfunction "TCK_6") (pintype "input"))
      (node (ref "R58") (pin "1") (pinfunction "1_1") (pintype "input"))
    )
    (net (code "248") (name "Net-(HDR1-TDI)") (class "Default")
      (node (ref "D1") (pin "2") (pinfunction "2_2") (pintype "input"))
      (node (ref "HDR1") (pin "10") (pinfunction "TDI_10") (pintype "input"))
      (node (ref "R56") (pin "1") (pinfunction "1_1") (pintype "input"))
    )
    (net (code "249") (name "Net-(HDR1-TDO)") (class "Default")
      (node (ref "D2") (pin "2") (pinfunction "2_2") (pintype "input"))
      (node (ref "HDR1") (pin "8") (pinfunction "TDO_8") (pintype "input"))
      (node (ref "R57") (pin "1") (pinfunction "1_1") (pintype "input"))
    )
    (net (code "250") (name "Net-(HDR1-TMS)") (class "Default")
      (node (ref "D4") (pin "2") (pinfunction "2_2") (pintype "input"))
      (node (ref "HDR1") (pin "4") (pinfunction "TMS_4") (pintype "input"))
      (node (ref "R59") (pin "1") (pinfunction "1_1") (pintype "input"))
    )
    (net (code "251") (name "Net-(LED9-A)") (class "Default")
      (node (ref "LED9") (pin "1") (pinfunction "A_1") (pintype "input"))
      (node (ref "R37") (pin "1") (pinfunction "1_1") (pintype "input"))
    )
    (net (code "252") (name "Net-(LED9-C)") (class "Default")
      (node (ref "LED9") (pin "2") (pinfunction "C_2") (pintype "input"))
      (node (ref "Q2") (pin "3") (pinfunction "D_3") (pintype "unspecified"))
    )
    (net (code "253") (name "Net-(LED10-A)") (class "Default")
      (node (ref "LED10") (pin "1") (pinfunction "A_1") (pintype "input"))
      (node (ref "R39") (pin "1") (pinfunction "1_1") (pintype "input"))
    )
    (net (code "254") (name "Net-(LED11-A)") (class "Default")
      (node (ref "LED11") (pin "1") (pinfunction "A_1") (pintype "input"))
      (node (ref "R40") (pin "1") (pinfunction "1_1") (pintype "input"))
    )
    (net (code "255") (name "Net-(LED11-C)") (class "Default")
      (node (ref "LED11") (pin "2") (pinfunction "C_2") (pintype "input"))
      (node (ref "Q1") (pin "3") (pinfunction "D_3") (pintype "unspecified"))
    )
    (net (code "256") (name "Net-(LED12-A)") (class "Default")
      (node (ref "LED12") (pin "1") (pinfunction "A_1") (pintype "input"))
      (node (ref "R42") (pin "1") (pinfunction "1_1") (pintype "input"))
    )
    (net (code "257") (name "Net-(LED12-C)") (class "Default")
      (node (ref "LED12") (pin "2") (pinfunction "C_2") (pintype "input"))
      (node (ref "Q3") (pin "3") (pinfunction "D_3") (pintype "unspecified"))
    )
    (net (code "258") (name "Net-(LED14-A)") (class "Default")
      (node (ref "LED14") (pin "1") (pinfunction "A_1") (pintype "input"))
      (node (ref "R52") (pin "1") (pinfunction "1_1") (pintype "input"))
    )
    (net (code "259") (name "Net-(LED14-C)") (class "Default")
      (node (ref "LED14") (pin "2") (pinfunction "C_2") (pintype "input"))
      (node (ref "Q6") (pin "3") (pinfunction "D_3") (pintype "unspecified"))
    )
    (net (code "260") (name "Net-(LED15-A)") (class "Default")
      (node (ref "LED15") (pin "2") (pinfunction "A_2") (pintype "input"))
      (node (ref "R225") (pin "1") (pinfunction "1_1") (pintype "input"))
    )
    (net (code "261") (name "Net-(LED16-A)") (class "Default")
      (node (ref "LED16") (pin "2") (pinfunction "A_2") (pintype "input"))
      (node (ref "R224") (pin "1") (pinfunction "1_1") (pintype "input"))
    )
    (net (code "262") (name "Net-(LED17-A)") (class "Default")
      (node (ref "LED17") (pin "1") (pinfunction "A_1") (pintype "input"))
      (node (ref "R80") (pin "1") (pinfunction "1_1") (pintype "input"))
    )
    (net (code "263") (name "Net-(LED17-C)") (class "Default")
      (node (ref "LED17") (pin "2") (pinfunction "C_2") (pintype "input"))
      (node (ref "Q7") (pin "3") (pinfunction "D_3") (pintype "unspecified"))
    )
    (net (code "264") (name "Net-(LED18-A)") (class "Default")
      (node (ref "LED18") (pin "1") (pinfunction "A_1") (pintype "input"))
      (node (ref "R126") (pin "1") (pinfunction "1_1") (pintype "input"))
    )
    (net (code "265") (name "Net-(LED18-C)") (class "Default")
      (node (ref "LED18") (pin "2") (pinfunction "C_2") (pintype "input"))
      (node (ref "Q8") (pin "3") (pinfunction "D_3") (pintype "unspecified"))
    )
    (net (code "266") (name "Net-(LED19-A)") (class "Default")
      (node (ref "LED19") (pin "1") (pinfunction "A_1") (pintype "input"))
      (node (ref "R128") (pin "1") (pinfunction "1_1") (pintype "input"))
    )
    (net (code "267") (name "Net-(LED19-C)") (class "Default")
      (node (ref "LED19") (pin "2") (pinfunction "C_2") (pintype "input"))
      (node (ref "Q5") (pin "3") (pinfunction "D_3") (pintype "unspecified"))
    )
    (net (code "268") (name "Net-(Q1-G)") (class "Default")
      (node (ref "Q1") (pin "1") (pinfunction "G_1") (pintype "unspecified"))
      (node (ref "R41") (pin "1") (pinfunction "1_1") (pintype "input"))
    )
    (net (code "269") (name "Net-(Q2-G)") (class "Default")
      (node (ref "Q2") (pin "1") (pinfunction "G_1") (pintype "unspecified"))
      (node (ref "R38") (pin "1") (pinfunction "1_1") (pintype "input"))
    )
    (net (code "270") (name "Net-(Q3-G)") (class "Default")
      (node (ref "Q3") (pin "1") (pinfunction "G_1") (pintype "unspecified"))
      (node (ref "R43") (pin "1") (pinfunction "1_1") (pintype "input"))
    )
    (net (code "271") (name "Net-(Q5-G)") (class "Default")
      (node (ref "Q5") (pin "1") (pinfunction "G_1") (pintype "unspecified"))
      (node (ref "R129") (pin "1") (pinfunction "1_1") (pintype "input"))
    )
    (net (code "272") (name "Net-(Q6-G)") (class "Default")
      (node (ref "Q6") (pin "1") (pinfunction "G_1") (pintype "unspecified"))
      (node (ref "R53") (pin "1") (pinfunction "1_1") (pintype "input"))
    )
    (net (code "273") (name "Net-(Q7-G)") (class "Default")
      (node (ref "Q7") (pin "1") (pinfunction "G_1") (pintype "unspecified"))
      (node (ref "R81") (pin "1") (pinfunction "1_1") (pintype "input"))
    )
    (net (code "274") (name "Net-(Q8-G)") (class "Default")
      (node (ref "Q8") (pin "1") (pinfunction "G_1") (pintype "unspecified"))
      (node (ref "R127") (pin "1") (pinfunction "1_1") (pintype "input"))
    )
    (net (code "275") (name "Net-(R222-Pad2)") (class "Default")
      (node (ref "R222") (pin "2") (pinfunction "2_2") (pintype "input"))
      (node (ref "R270") (pin "1") (pinfunction "1_1") (pintype "input"))
    )
    (net (code "276") (name "Net-(R223-Pad2)") (class "Default")
      (node (ref "R223") (pin "2") (pinfunction "2_2") (pintype "input"))
      (node (ref "R271") (pin "1") (pinfunction "1_1") (pintype "input"))
    )
    (net (code "277") (name "Net-(R237-Pad2)") (class "Default")
      (node (ref "R237") (pin "2") (pinfunction "2_2") (pintype "input"))
      (node (ref "RJ1") (pin "12") (pinfunction "12_12") (pintype "unspecified"))
    )
    (net (code "278") (name "Net-(R238-Pad2)") (class "Default")
      (node (ref "R238") (pin "2") (pinfunction "2_2") (pintype "input"))
      (node (ref "RJ1") (pin "13") (pinfunction "13_13") (pintype "unspecified"))
    )
    (net (code "279") (name "Net-(U1-ZQ)") (class "Default")
      (node (ref "R61") (pin "2") (pinfunction "2_2") (pintype "input"))
      (node (ref "U1") (pin "L8") (pinfunction "ZQ_L8") (pintype "input"))
    )
    (net (code "280") (name "Net-(U2F-PS_MIO7_500)") (class "Default")
      (node (ref "R269") (pin "1") (pinfunction "1_1") (pintype "input"))
      (node (ref "U2") (pin "D5") (pinfunction "PS_MIO7_500_D5") (pintype "bidirectional"))
    )
    (net (code "281") (name "Net-(U2F-PS_MIO8_500)") (class "Default")
      (node (ref "R268") (pin "1") (pinfunction "1_1") (pintype "input"))
      (node (ref "U2") (pin "E5") (pinfunction "PS_MIO8_500_E5") (pintype "bidirectional"))
    )
    (net (code "282") (name "Net-(U2F-PS_MIO40_501)") (class "Default")
      (node (ref "R174") (pin "1") (pinfunction "1_1") (pintype "input"))
      (node (ref "U2") (pin "E14") (pinfunction "PS_MIO40_501_E14") (pintype "bidirectional"))
    )
    (net (code "283") (name "Net-(U2G-PS_DDR_VRN_502)") (class "Default")
      (node (ref "R65") (pin "2") (pinfunction "2_2") (pintype "input"))
      (node (ref "U2") (pin "M7") (pinfunction "PS_DDR_VRN_502_M7") (pintype "output"))
    )
    (net (code "284") (name "Net-(U2G-PS_DDR_VRP_502)") (class "Default")
      (node (ref "R64") (pin "1") (pinfunction "1_1") (pintype "input"))
      (node (ref "U2") (pin "N7") (pinfunction "PS_DDR_VRP_502_N7") (pintype "output"))
    )
    (net (code "285") (name "Net-(U3-ZQ)") (class "Default")
      (node (ref "R62") (pin "2") (pinfunction "2_2") (pintype "input"))
      (node (ref "U3") (pin "L8") (pinfunction "ZQ_L8") (pintype "input"))
    )
    (net (code "286") (name "Net-(U4-EN)") (class "Default")
      (node (ref "R3") (pin "1") (pinfunction "1_1") (pintype "input"))
      (node (ref "U4") (pin "1") (pinfunction "EN_1") (pintype "input"))
    )
    (net (code "287") (name "Net-(U4-SW)") (class "Default")
      (node (ref "C7") (pin "2") (pinfunction "2_2") (pintype "input"))
      (node (ref "U4") (pin "6") (pinfunction "SW_6") (pintype "input"))
      (node (ref "U40") (pin "1") (pinfunction "1_1") (pintype "input"))
    )
    (net (code "288") (name "Net-(U4-VBST)") (class "Default")
      (node (ref "C7") (pin "1") (pinfunction "1_1") (pintype "input"))
      (node (ref "U4") (pin "7") (pinfunction "VBST_7") (pintype "input"))
    )
    (net (code "289") (name "Net-(U4-VFB)") (class "Default")
      (node (ref "C4") (pin "1") (pinfunction "1_1") (pintype "input"))
      (node (ref "R1") (pin "1") (pinfunction "1_1") (pintype "input"))
      (node (ref "R2") (pin "1") (pinfunction "1_1") (pintype "input"))
      (node (ref "U4") (pin "2") (pinfunction "VFB_2") (pintype "input"))
    )
    (net (code "290") (name "Net-(U4-VREG5)") (class "Default")
      (node (ref "C5") (pin "1") (pinfunction "1_1") (pintype "input"))
      (node (ref "R4") (pin "1") (pinfunction "1_1") (pintype "input"))
      (node (ref "U4") (pin "3") (pinfunction "VREG5_3") (pintype "input"))
    )
    (net (code "291") (name "Net-(U6-EN)") (class "Default")
      (node (ref "R5") (pin "1") (pinfunction "1_1") (pintype "input"))
      (node (ref "U6") (pin "1") (pinfunction "EN_1") (pintype "input"))
    )
    (net (code "292") (name "Net-(U6-SW)") (class "Default")
      (node (ref "C15") (pin "2") (pinfunction "2_2") (pintype "input"))
      (node (ref "U38") (pin "1") (pinfunction "1_1") (pintype "input"))
      (node (ref "U6") (pin "6") (pinfunction "SW_6") (pintype "input"))
    )
    (net (code "293") (name "Net-(U6-VBST)") (class "Default")
      (node (ref "C15") (pin "1") (pinfunction "1_1") (pintype "input"))
      (node (ref "U6") (pin "7") (pinfunction "VBST_7") (pintype "input"))
    )
    (net (code "294") (name "Net-(U6-VFB)") (class "Default")
      (node (ref "C13") (pin "1") (pinfunction "1_1") (pintype "input"))
      (node (ref "R6") (pin "1") (pinfunction "1_1") (pintype "input"))
      (node (ref "R7") (pin "1") (pinfunction "1_1") (pintype "input"))
      (node (ref "U6") (pin "2") (pinfunction "VFB_2") (pintype "input"))
    )
    (net (code "295") (name "Net-(U6-VREG5)") (class "Default")
      (node (ref "C14") (pin "1") (pinfunction "1_1") (pintype "input"))
      (node (ref "R8") (pin "1") (pinfunction "1_1") (pintype "input"))
      (node (ref "U6") (pin "3") (pinfunction "VREG5_3") (pintype "input"))
    )
    (net (code "296") (name "Net-(U10-SW)") (class "Default")
      (node (ref "C31") (pin "2") (pinfunction "2_2") (pintype "input"))
      (node (ref "U10") (pin "6") (pinfunction "SW_6") (pintype "input"))
      (node (ref "U37") (pin "1") (pinfunction "1_1") (pintype "input"))
    )
    (net (code "297") (name "Net-(U10-VBST)") (class "Default")
      (node (ref "C31") (pin "1") (pinfunction "1_1") (pintype "input"))
      (node (ref "U10") (pin "7") (pinfunction "VBST_7") (pintype "input"))
    )
    (net (code "298") (name "Net-(U10-VREG5)") (class "Default")
      (node (ref "C30") (pin "1") (pinfunction "1_1") (pintype "input"))
      (node (ref "R16") (pin "1") (pinfunction "1_1") (pintype "input"))
      (node (ref "U10") (pin "3") (pinfunction "VREG5_3") (pintype "input"))
    )
    (net (code "299") (name "Net-(U34-ADBUS0)") (class "Default")
      (node (ref "R217") (pin "1") (pinfunction "1_1") (pintype "input"))
      (node (ref "U34") (pin "16") (pinfunction "ADBUS0_16") (pintype "bidirectional"))
    )
    (net (code "300") (name "Net-(U34-ADBUS1)") (class "Default")
      (node (ref "R218") (pin "1") (pinfunction "1_1") (pintype "input"))
      (node (ref "U34") (pin "17") (pinfunction "ADBUS1_17") (pintype "bidirectional"))
    )
    (net (code "301") (name "Net-(U34-ADBUS2)") (class "Default")
      (node (ref "R219") (pin "1") (pinfunction "1_1") (pintype "input"))
      (node (ref "U34") (pin "18") (pinfunction "ADBUS2_18") (pintype "bidirectional"))
    )
    (net (code "302") (name "Net-(U34-ADBUS3)") (class "Default")
      (node (ref "R220") (pin "1") (pinfunction "1_1") (pintype "input"))
      (node (ref "U34") (pin "19") (pinfunction "ADBUS3_19") (pintype "bidirectional"))
    )
    (net (code "303") (name "Net-(U34-ADBUS5)") (class "Default")
      (node (ref "R221") (pin "1") (pinfunction "1_1") (pintype "input"))
      (node (ref "U34") (pin "22") (pinfunction "ADBUS5_22") (pintype "bidirectional"))
    )
    (net (code "304") (name "Net-(U34-BDBUS0)") (class "Default")
      (node (ref "R222") (pin "1") (pinfunction "1_1") (pintype "input"))
      (node (ref "U34") (pin "38") (pinfunction "BDBUS0_38") (pintype "bidirectional"))
    )
    (net (code "305") (name "Net-(U34-BDBUS1)") (class "Default")
      (node (ref "R223") (pin "1") (pinfunction "1_1") (pintype "input"))
      (node (ref "U34") (pin "39") (pinfunction "BDBUS1_39") (pintype "bidirectional"))
    )
    (net (code "306") (name "Net-(U34-EECLK)") (class "Default")
      (node (ref "R278") (pin "2") (pinfunction "2_2") (pintype "input"))
      (node (ref "U34") (pin "62") (pinfunction "EECLK_62") (pintype "output"))
      (node (ref "U60") (pin "2") (pinfunction "CLK_2") (pintype "input"))
    )
    (net (code "307") (name "Net-(U34-EECS)") (class "Default")
      (node (ref "R279") (pin "2") (pinfunction "2_2") (pintype "input"))
      (node (ref "U34") (pin "63") (pinfunction "EECS_63") (pintype "bidirectional"))
      (node (ref "U60") (pin "1") (pinfunction "CS_1") (pintype "input"))
    )
    (net (code "308") (name "Net-(U34-EEDATA)") (class "Default")
      (node (ref "R72") (pin "1") (pinfunction "1_1") (pintype "input"))
      (node (ref "U34") (pin "61") (pinfunction "EEDATA_61") (pintype "bidirectional"))
      (node (ref "U60") (pin "3") (pinfunction "DI_3") (pintype "input"))
    )
    (net (code "309") (name "Net-(U34-OSCI)") (class "Default")
      (node (ref "R74") (pin "1") (pinfunction "1_1") (pintype "input"))
      (node (ref "U34") (pin "2") (pinfunction "OSCI_2") (pintype "input"))
    )
    (net (code "310") (name "Net-(U34-REF)") (class "Default")
      (node (ref "R226") (pin "2") (pinfunction "2_2") (pintype "input"))
      (node (ref "U34") (pin "6") (pinfunction "REF_6") (pintype "input"))
    )
    (net (code "311") (name "Net-(U34-RESET#)") (class "Default")
      (node (ref "R69") (pin "1") (pinfunction "1_1") (pintype "input"))
      (node (ref "R70") (pin "2") (pinfunction "2_2") (pintype "input"))
      (node (ref "U34") (pin "14") (pinfunction "RESET#_14") (pintype "input"))
    )
    (net (code "312") (name "Net-(U34-VPHY)") (class "Default")
      (node (ref "C189") (pin "1") (pinfunction "1_1") (pintype "input"))
      (node (ref "C350") (pin "1") (pinfunction "1_1") (pintype "input"))
      (node (ref "L8") (pin "2") (pinfunction "2_2") (pintype "input"))
      (node (ref "U34") (pin "4") (pinfunction "VPHY_4") (pintype "input"))
    )
    (net (code "313") (name "Net-(U34-VPLL)") (class "Default")
      (node (ref "C34") (pin "1") (pinfunction "1_1") (pintype "input"))
      (node (ref "C349") (pin "1") (pinfunction "1_1") (pintype "input"))
      (node (ref "L10") (pin "2") (pinfunction "2_2") (pintype "input"))
      (node (ref "U34") (pin "9") (pinfunction "VPLL_9") (pintype "input"))
    )
    (net (code "314") (name "Net-(U35-CFG_EXT{slash}LED0)") (class "Default")
      (node (ref "R237") (pin "1") (pinfunction "1_1") (pintype "input"))
      (node (ref "R240") (pin "2") (pinfunction "2_2") (pintype "input"))
      (node (ref "U35") (pin "32") (pinfunction "CFG_EXT/LED0_32") (pintype "unspecified"))
    )
    (net (code "315") (name "Net-(U35-CFG_LDO0{slash}LED1)") (class "Default")
      (node (ref "R239") (pin "2") (pinfunction "2_2") (pintype "input"))
      (node (ref "U35") (pin "33") (pinfunction "CFG_LDO0/LED1_33") (pintype "unspecified"))
    )
    (net (code "316") (name "Net-(U35-CFG_LDO1{slash}LED2)") (class "Default")
      (node (ref "R238") (pin "1") (pinfunction "1_1") (pintype "input"))
      (node (ref "R241") (pin "2") (pinfunction "2_2") (pintype "input"))
      (node (ref "U35") (pin "34") (pinfunction "CFG_LDO1/LED2_34") (pintype "unspecified"))
    )
    (net (code "317") (name "Net-(U36-CPEN)") (class "Default")
      (node (ref "R235") (pin "2") (pinfunction "2_2") (pintype "input"))
      (node (ref "U36") (pin "17") (pinfunction "CPEN_17") (pintype "input"))
      (node (ref "U73") (pin "4") (pinfunction "ENABLE_4") (pintype "input"))
    )
    (net (code "318") (name "Net-(U36-RBIAS)") (class "Default")
      (node (ref "R233") (pin "2") (pinfunction "2_2") (pintype "input"))
      (node (ref "U36") (pin "24") (pinfunction "RBIAS_24") (pintype "input"))
    )
    (net (code "319") (name "Net-(U36-REFCLK)") (class "Default")
      (node (ref "R231") (pin "2") (pinfunction "2_2") (pintype "input"))
      (node (ref "U36") (pin "26") (pinfunction "REFCLK_26") (pintype "input"))
    )
    (net (code "320") (name "Net-(U36-VBUS)") (class "Default")
      (node (ref "R234") (pin "1") (pinfunction "1_1") (pintype "input"))
      (node (ref "U36") (pin "22") (pinfunction "VBUS_22") (pintype "input"))
    )
    (net (code "321") (name "Net-(U60-DO)") (class "Default")
      (node (ref "R72") (pin "2") (pinfunction "2_2") (pintype "input"))
      (node (ref "R73") (pin "2") (pinfunction "2_2") (pintype "input"))
      (node (ref "U60") (pin "4") (pinfunction "DO_4") (pintype "input"))
    )
    (net (code "322") (name "Net-(U70-Output)") (class "Default")
      (node (ref "R242") (pin "2") (pinfunction "2_2") (pintype "input"))
      (node (ref "U70") (pin "3") (pinfunction "Output_3") (pintype "unspecified"))
    )
    (net (code "323") (name "Net-(U72-Output)") (class "Default")
      (node (ref "R231") (pin "1") (pinfunction "1_1") (pintype "input"))
      (node (ref "U72") (pin "3") (pinfunction "Output_3") (pintype "input"))
    )
    (net (code "324") (name "Net-(U73-ILIMIT)") (class "Default")
      (node (ref "R236") (pin "2") (pinfunction "2_2") (pintype "input"))
      (node (ref "U73") (pin "2") (pinfunction "ILIMIT_2") (pintype "input"))
    )
    (net (code "325") (name "Net-(U74-SEL)") (class "Default")
      (node (ref "R230") (pin "2") (pinfunction "2_2") (pintype "input"))
      (node (ref "U74") (pin "24") (pinfunction "SEL_24") (pintype "unspecified"))
    )
    (net (code "326") (name "Net-(X1-Output)") (class "Default")
      (node (ref "R74") (pin "2") (pinfunction "2_2") (pintype "input"))
      (node (ref "X1") (pin "3") (pinfunction "Output_3") (pintype "input"))
    )
    (net (code "327") (name "Net-(X2-Output)") (class "Default")
      (node (ref "R75") (pin "2") (pinfunction "2_2") (pintype "input"))
      (node (ref "X2") (pin "3") (pinfunction "Output_3") (pintype "input"))
    )
    (net (code "328") (name "OTG_DN") (class "Default")
      (node (ref "D11") (pin "2") (pinfunction "2_2") (pintype "input"))
      (node (ref "U36") (pin "19") (pinfunction "DM_19") (pintype "input"))
      (node (ref "USB1") (pin "2") (pinfunction "D-_2") (pintype "unspecified"))
    )
    (net (code "329") (name "OTG_DP") (class "Default")
      (node (ref "D10") (pin "2") (pinfunction "2_2") (pintype "input"))
      (node (ref "U36") (pin "18") (pinfunction "DP_18") (pintype "input"))
      (node (ref "USB1") (pin "3") (pinfunction "D+_3") (pintype "unspecified"))
    )
    (net (code "330") (name "OTG_ID") (class "Default")
      (node (ref "D9") (pin "2") (pinfunction "2_2") (pintype "input"))
      (node (ref "U36") (pin "23") (pinfunction "ID_23") (pintype "input"))
      (node (ref "USB1") (pin "4") (pinfunction "ID_4") (pintype "unspecified"))
    )
    (net (code "331") (name "PG_1V0") (class "Default")
      (node (ref "R16") (pin "2") (pinfunction "2_2") (pintype "input"))
      (node (ref "R41") (pin "2") (pinfunction "2_2") (pintype "input"))
      (node (ref "R5") (pin "2") (pinfunction "2_2") (pintype "input"))
      (node (ref "U10") (pin "4") (pinfunction "PG_4") (pintype "input"))
    )
    (net (code "332") (name "PG_1V8") (class "Default")
      (node (ref "R43") (pin "2") (pinfunction "2_2") (pintype "input"))
      (node (ref "R8") (pin "2") (pinfunction "2_2") (pintype "input"))
      (node (ref "R9") (pin "2") (pinfunction "2_2") (pintype "input"))
      (node (ref "U6") (pin "4") (pinfunction "PG_4") (pintype "input"))
    )
    (net (code "333") (name "PG_1V35") (class "Default")
      (node (ref "R12") (pin "2") (pinfunction "2_2") (pintype "input"))
      (node (ref "R124") (pin "2") (pinfunction "2_2") (pintype "input"))
      (node (ref "R3") (pin "2") (pinfunction "2_2") (pintype "input"))
      (node (ref "R38") (pin "2") (pinfunction "2_2") (pintype "input"))
      (node (ref "U8") (pin "4") (pinfunction "PG_4") (pintype "input"))
    )
    (net (code "334") (name "PG_3V3") (class "Default")
      (node (ref "R129") (pin "2") (pinfunction "2_2") (pintype "input"))
      (node (ref "R4") (pin "2") (pinfunction "2_2") (pintype "input"))
      (node (ref "U4") (pin "4") (pinfunction "PG_4") (pintype "input"))
      (node (ref "U61") (pin "2") (pinfunction "A_2") (pintype "input"))
    )
    (net (code "335") (name "PL_CLK_125MHZ") (class "Default")
      (node (ref "R243") (pin "2") (pinfunction "2_2") (pintype "input"))
      (node (ref "U2") (pin "B19") (pinfunction "IO_L13P_T2_MRCC_35_B19") (pintype "bidirectional"))
    )
    (net (code "336") (name "PROGRAMB") (class "Default")
      (node (ref "R51") (pin "1") (pinfunction "1_1") (pintype "input"))
      (node (ref "SW1") (pin "1") (pinfunction "1_1") (pintype "input"))
      (node (ref "SW1") (pin "2") (pinfunction "2_2") (pintype "input"))
      (node (ref "U2") (pin "T11") (pinfunction "PROGRAM_B_0_T11") (pintype "input"))
    )
    (net (code "337") (name "PS_CLK_33M333") (class "Default")
      (node (ref "R75") (pin "1") (pinfunction "1_1") (pintype "input"))
      (node (ref "U2") (pin "F7") (pinfunction "PS_CLK_500_F7") (pintype "input"))
    )
    (net (code "338") (name "PS_LED") (class "Default")
      (node (ref "R81") (pin "2") (pinfunction "2_2") (pintype "input"))
      (node (ref "R82") (pin "1") (pinfunction "1_1") (pintype "input"))
      (node (ref "U2") (pin "G6") (pinfunction "PS_MIO0_500_G6") (pintype "bidirectional"))
    )
    (net (code "339") (name "PS_MIO11") (class "Default")
      (node (ref "H5") (pin "2") (pinfunction "2_2") (pintype "unspecified"))
      (node (ref "U2") (pin "B4") (pinfunction "PS_MIO11_500_B4") (pintype "bidirectional"))
    )
    (net (code "340") (name "PS_MIO12") (class "Default")
      (node (ref "H5") (pin "1") (pinfunction "1_1") (pintype "unspecified"))
      (node (ref "U2") (pin "C5") (pinfunction "PS_MIO12_500_C5") (pintype "bidirectional"))
    )
    (net (code "341") (name "PS_MIO13") (class "Default")
      (node (ref "H5") (pin "4") (pinfunction "4_4") (pintype "unspecified"))
      (node (ref "U2") (pin "A6") (pinfunction "PS_MIO13_500_A6") (pintype "bidirectional"))
    )
    (net (code "342") (name "PS_MIO48") (class "Default")
      (node (ref "H5") (pin "6") (pinfunction "6_6") (pintype "unspecified"))
      (node (ref "U2") (pin "D11") (pinfunction "PS_MIO48_501_D11") (pintype "bidirectional"))
    )
    (net (code "343") (name "PS_MIO49") (class "Default")
      (node (ref "H5") (pin "5") (pinfunction "5_5") (pintype "unspecified"))
      (node (ref "U2") (pin "C14") (pinfunction "PS_MIO49_501_C14") (pintype "bidirectional"))
    )
    (net (code "344") (name "PS_MIO50") (class "Default")
      (node (ref "H5") (pin "8") (pinfunction "8_8") (pintype "unspecified"))
      (node (ref "U2") (pin "D13") (pinfunction "PS_MIO50_501_D13") (pintype "bidirectional"))
    )
    (net (code "345") (name "PS_MIO51") (class "Default")
      (node (ref "H5") (pin "7") (pinfunction "7_7") (pintype "unspecified"))
      (node (ref "U2") (pin "C10") (pinfunction "PS_MIO51_501_C10") (pintype "bidirectional"))
    )
    (net (code "346") (name "PS_QSPI_CLK") (class "Default")
      (node (ref "R85") (pin "2") (pinfunction "2_2") (pintype "input"))
      (node (ref "U2") (pin "A4") (pinfunction "PS_MIO6_500_A4") (pintype "bidirectional"))
    )
    (net (code "347") (name "QSPI_CLK") (class "Default")
      (node (ref "R275") (pin "2") (pinfunction "2_2") (pintype "input"))
      (node (ref "R85") (pin "1") (pinfunction "1_1") (pintype "input"))
      (node (ref "U63") (pin "6") (pinfunction "CLK_6") (pintype "unspecified"))
    )
    (net (code "348") (name "QSPI_CSB") (class "Default")
      (node (ref "R84") (pin "2") (pinfunction "2_2") (pintype "input"))
      (node (ref "U2") (pin "A1") (pinfunction "PS_MIO1_500_A1") (pintype "bidirectional"))
      (node (ref "U63") (pin "1") (pinfunction "CS#_1") (pintype "unspecified"))
    )
    (net (code "349") (name "QSPI_DQ0_M3") (class "Default")
      (node (ref "R272") (pin "2") (pinfunction "2_2") (pintype "input"))
      (node (ref "U2") (pin "A2") (pinfunction "PS_MIO2_500_A2") (pintype "bidirectional"))
      (node (ref "U63") (pin "5") (pinfunction "DI(IO0)_5") (pintype "unspecified"))
    )
    (net (code "350") (name "QSPI_DQ1_M1") (class "Default")
      (node (ref "R89") (pin "2") (pinfunction "2_2") (pintype "input"))
      (node (ref "U2") (pin "F6") (pinfunction "PS_MIO3_500_F6") (pintype "bidirectional"))
      (node (ref "U63") (pin "2") (pinfunction "DO(IO1)_2") (pintype "unspecified"))
    )
    (net (code "351") (name "QSPI_DQ2_M2") (class "Default")
      (node (ref "R90") (pin "2") (pinfunction "2_2") (pintype "input"))
      (node (ref "U2") (pin "E4") (pinfunction "PS_MIO4_500_E4") (pintype "bidirectional"))
      (node (ref "U63") (pin "3") (pinfunction "WP#(IO2）_3") (pintype "unspecified"))
    )
    (net (code "352") (name "QSPI_DQ3_M0") (class "Default")
      (node (ref "R88") (pin "2") (pinfunction "2_2") (pintype "input"))
      (node (ref "U2") (pin "A3") (pinfunction "PS_MIO5_500_A3") (pintype "bidirectional"))
      (node (ref "U63") (pin "7") (pinfunction "HOLD#/RESET#(IO3)_7") (pintype "unspecified"))
    )
    (net (code "353") (name "SDCARD_CLK") (class "Default")
      (node (ref "CARD2") (pin "5") (pinfunction "CLK_5") (pintype "unspecified"))
      (node (ref "U74") (pin "19") (pinfunction "CLKB0_19") (pintype "unspecified"))
    )
    (net (code "354") (name "SDCARD_CMD") (class "Default")
      (node (ref "CARD2") (pin "3") (pinfunction "CMD_3") (pintype "unspecified"))
      (node (ref "R229") (pin "1") (pinfunction "1_1") (pintype "input"))
      (node (ref "U74") (pin "20") (pinfunction "CMDB0_20") (pintype "unspecified"))
    )
    (net (code "355") (name "SDCARD_D0") (class "Default")
      (node (ref "CARD2") (pin "7") (pinfunction "DAT0_7") (pintype "unspecified"))
      (node (ref "U74") (pin "18") (pinfunction "DAT0B0_18") (pintype "unspecified"))
    )
    (net (code "356") (name "SDCARD_D1") (class "Default")
      (node (ref "CARD2") (pin "8") (pinfunction "DAT1_8") (pintype "unspecified"))
      (node (ref "U74") (pin "16") (pinfunction "DAT1B0_16") (pintype "unspecified"))
    )
    (net (code "357") (name "SDCARD_D2") (class "Default")
      (node (ref "CARD2") (pin "1") (pinfunction "DAT2_1") (pintype "unspecified"))
      (node (ref "U74") (pin "23") (pinfunction "DAT2B0_23") (pintype "unspecified"))
    )
    (net (code "358") (name "SDCARD_D4") (class "Default")
      (node (ref "CARD2") (pin "2") (pinfunction "CD/DAT3_2") (pintype "unspecified"))
      (node (ref "U74") (pin "22") (pinfunction "DAT3B0_22") (pintype "unspecified"))
    )
    (net (code "359") (name "SD_CD") (class "Default")
      (node (ref "R227") (pin "1") (pinfunction "1_1") (pintype "input"))
      (node (ref "R228") (pin "2") (pinfunction "2_2") (pintype "input"))
      (node (ref "U2") (pin "B10") (pinfunction "PS_MIO47_501_B10") (pintype "bidirectional"))
    )
    (net (code "360") (name "SD_CLK") (class "Default")
      (node (ref "R174") (pin "2") (pinfunction "2_2") (pintype "input"))
      (node (ref "U74") (pin "9") (pinfunction "CLKA_9") (pintype "unspecified"))
    )
    (net (code "361") (name "SD_CMD") (class "Default")
      (node (ref "U2") (pin "C8") (pinfunction "PS_MIO41_501_C8") (pintype "bidirectional"))
      (node (ref "U74") (pin "4") (pinfunction "CMDA_4") (pintype "unspecified"))
    )
    (net (code "362") (name "SD_D0") (class "Default")
      (node (ref "U2") (pin "D8") (pinfunction "PS_MIO42_501_D8") (pintype "bidirectional"))
      (node (ref "U74") (pin "6") (pinfunction "DAT0A_6") (pintype "unspecified"))
    )
    (net (code "363") (name "SD_D1") (class "Default")
      (node (ref "U2") (pin "B11") (pinfunction "PS_MIO43_501_B11") (pintype "bidirectional"))
      (node (ref "U74") (pin "7") (pinfunction "DAT1A_7") (pintype "unspecified"))
    )
    (net (code "364") (name "SD_D2") (class "Default")
      (node (ref "U2") (pin "E13") (pinfunction "PS_MIO44_501_E13") (pintype "bidirectional"))
      (node (ref "U74") (pin "1") (pinfunction "DAT2A_1") (pintype "unspecified"))
    )
    (net (code "365") (name "SD_D3") (class "Default")
      (node (ref "U2") (pin "B9") (pinfunction "PS_MIO45_501_B9") (pintype "bidirectional"))
      (node (ref "U74") (pin "3") (pinfunction "DAT3A_3") (pintype "unspecified"))
    )
    (net (code "366") (name "TCK") (class "Default")
      (node (ref "R217") (pin "2") (pinfunction "2_2") (pintype "input"))
      (node (ref "R58") (pin "2") (pinfunction "2_2") (pintype "input"))
      (node (ref "U2") (pin "G11") (pinfunction "TCK_0_G11") (pintype "input"))
    )
    (net (code "367") (name "TDI") (class "Default")
      (node (ref "R218") (pin "2") (pinfunction "2_2") (pintype "input"))
      (node (ref "R47") (pin "1") (pinfunction "1_1") (pintype "input"))
      (node (ref "R56") (pin "2") (pinfunction "2_2") (pintype "input"))
      (node (ref "U2") (pin "H13") (pinfunction "TDI_0_H13") (pintype "input"))
    )
    (net (code "368") (name "TDO") (class "Default")
      (node (ref "R219") (pin "2") (pinfunction "2_2") (pintype "input"))
      (node (ref "R57") (pin "2") (pinfunction "2_2") (pintype "input"))
      (node (ref "U2") (pin "G14") (pinfunction "TDO_0_G14") (pintype "output"))
    )
    (net (code "369") (name "TMS") (class "Default")
      (node (ref "R220") (pin "2") (pinfunction "2_2") (pintype "input"))
      (node (ref "R48") (pin "1") (pinfunction "1_1") (pintype "input"))
      (node (ref "R59") (pin "2") (pinfunction "2_2") (pintype "input"))
      (node (ref "U2") (pin "G12") (pinfunction "TMS_0_G12") (pintype "input"))
    )
    (net (code "370") (name "UART1_RX") (class "Default")
      (node (ref "R270") (pin "2") (pinfunction "2_2") (pintype "input"))
      (node (ref "U2") (pin "B6") (pinfunction "PS_MIO14_500_B6") (pintype "bidirectional"))
    )
    (net (code "371") (name "UART1_TX_VCFG1") (class "Default")
      (node (ref "R271") (pin "2") (pinfunction "2_2") (pintype "input"))
      (node (ref "U2") (pin "E6") (pinfunction "PS_MIO15_500_E6") (pintype "bidirectional"))
    )
    (net (code "372") (name "USB_CLK") (class "Default")
      (node (ref "U2") (pin "A9") (pinfunction "PS_MIO36_501_A9") (pintype "bidirectional"))
      (node (ref "U36") (pin "1") (pinfunction "CLKOUT_1") (pintype "input"))
    )
    (net (code "373") (name "USB_DATA0") (class "Default")
      (node (ref "U2") (pin "C7") (pinfunction "PS_MIO32_501_C7") (pintype "bidirectional"))
      (node (ref "U36") (pin "3") (pinfunction "DATA0_3") (pintype "input"))
    )
    (net (code "374") (name "USB_DATA1") (class "Default")
      (node (ref "U2") (pin "G13") (pinfunction "PS_MIO33_501_G13") (pintype "bidirectional"))
      (node (ref "U36") (pin "4") (pinfunction "DATA1_4") (pintype "input"))
    )
    (net (code "375") (name "USB_DATA2") (class "Default")
      (node (ref "U2") (pin "B12") (pinfunction "PS_MIO34_501_B12") (pintype "bidirectional"))
      (node (ref "U36") (pin "5") (pinfunction "DATA2_5") (pintype "input"))
    )
    (net (code "376") (name "USB_DATA3") (class "Default")
      (node (ref "U2") (pin "F14") (pinfunction "PS_MIO35_501_F14") (pintype "bidirectional"))
      (node (ref "U36") (pin "6") (pinfunction "DATA3_6") (pintype "input"))
    )
    (net (code "377") (name "USB_DATA4") (class "Default")
      (node (ref "U2") (pin "A12") (pinfunction "PS_MIO28_501_A12") (pintype "bidirectional"))
      (node (ref "U36") (pin "7") (pinfunction "DATA4_7") (pintype "input"))
    )
    (net (code "378") (name "USB_DATA5") (class "Default")
      (node (ref "U2") (pin "B14") (pinfunction "PS_MIO37_501_B14") (pintype "bidirectional"))
      (node (ref "U36") (pin "9") (pinfunction "DATA5_9") (pintype "input"))
    )
    (net (code "379") (name "USB_DATA6") (class "Default")
      (node (ref "U2") (pin "F13") (pinfunction "PS_MIO38_501_F13") (pintype "bidirectional"))
      (node (ref "U36") (pin "10") (pinfunction "DATA6_10") (pintype "input"))
    )
    (net (code "380") (name "USB_DATA7") (class "Default")
      (node (ref "U2") (pin "C13") (pinfunction "PS_MIO39_501_C13") (pintype "bidirectional"))
      (node (ref "U36") (pin "13") (pinfunction "DATA7_13") (pintype "input"))
    )
    (net (code "382") (name "USB_DIR") (class "Default")
      (node (ref "U2") (pin "E8") (pinfunction "PS_MIO29_501_E8") (pintype "bidirectional"))
      (node (ref "U36") (pin "31") (pinfunction "DIR_31") (pintype "input"))
    )
    (net (code "383") (name "USB_NXT") (class "Default")
      (node (ref "U2") (pin "F9") (pinfunction "PS_MIO31_501_F9") (pintype "bidirectional"))
      (node (ref "U36") (pin "2") (pinfunction "NXT_2") (pintype "input"))
    )
    (net (code "384") (name "USB_RSTB") (class "Default")
      (node (ref "R232") (pin "2") (pinfunction "2_2") (pintype "input"))
      (node (ref "U2") (pin "D12") (pinfunction "PS_MIO46_501_D12") (pintype "bidirectional"))
      (node (ref "U36") (pin "27") (pinfunction "RESETB_27") (pintype "input"))
    )
    (net (code "385") (name "USB_STP") (class "Default")
      (node (ref "U2") (pin "A11") (pinfunction "PS_MIO30_501_A11") (pintype "bidirectional"))
      (node (ref "U36") (pin "29") (pinfunction "STP_29") (pintype "input"))
    )
    (net (code "386") (name "VCCPLL") (class "Default")
      (node (ref "C300") (pin "2") (pinfunction "2_2") (pintype "input"))
      (node (ref "C301") (pin "1") (pinfunction "1_1") (pintype "input"))
      (node (ref "L4") (pin "1") (pinfunction "1_1") (pintype "input"))
      (node (ref "U2") (pin "H10") (pinfunction "VCCPLL_H10") (pintype "unspecified"))
    )
    (net (code "387") (name "VUSB") (class "Default")
      (node (ref "C181") (pin "1") (pinfunction "1_1") (pintype "input"))
      (node (ref "F1") (pin "2") (pinfunction "2_2") (pintype "input"))
      (node (ref "H2") (pin "3") (pinfunction "3_3") (pintype "input"))
      (node (ref "H3") (pin "3") (pinfunction "3_3") (pintype "input"))
      (node (ref "L9") (pin "1") (pinfunction "1_1") (pintype "input"))
    )
    (net (code "388") (name "VUSB_IN") (class "Default")
      (node (ref "F1") (pin "1") (pinfunction "1_1") (pintype "input"))
      (node (ref "U27") (pin "A4B9") (pinfunction "VBUS_A4B9") (pintype "unspecified"))
      (node (ref "U27") (pin "B4A9") (pinfunction "VBUS_B4A9") (pintype "unspecified"))
    )
    (net (code "389") (name "unconnected-(CN2-Reserved(N.C.)-Pad14)") (class "Default")
      (node (ref "CN2") (pin "14") (pinfunction "Reserved(N.C.)_14") (pintype "unspecified+no_connect"))
    )
    (net (code "390") (name "unconnected-(HDR1----Pad12)") (class "Default")
      (node (ref "HDR1") (pin "12") (pinfunction "--_12") (pintype "input+no_connect"))
    )
    (net (code "391") (name "unconnected-(RJ1-PadP1)") (class "Default")
      (node (ref "RJ1") (pin "P1") (pinfunction "P1_P1") (pintype "unspecified+no_connect"))
    )
    (net (code "392") (name "unconnected-(U1-NC-PadJ1)") (class "Default")
      (node (ref "U1") (pin "J1") (pinfunction "NC_J1") (pintype "input+no_connect"))
    )
    (net (code "393") (name "unconnected-(U1-NC-PadJ9)") (class "Default")
      (node (ref "U1") (pin "J9") (pinfunction "NC_J9") (pintype "input+no_connect"))
    )
    (net (code "394") (name "unconnected-(U1-NC-PadL1)") (class "Default")
      (node (ref "U1") (pin "L1") (pinfunction "NC_L1") (pintype "input+no_connect"))
    )
    (net (code "395") (name "unconnected-(U1-NC-PadL9)") (class "Default")
      (node (ref "U1") (pin "L9") (pinfunction "NC_L9") (pintype "input+no_connect"))
    )
    (net (code "396") (name "unconnected-(U1-NC-PadM7)") (class "Default")
      (node (ref "U1") (pin "M7") (pinfunction "NC_M7") (pintype "input+no_connect"))
    )
    (net (code "397") (name "unconnected-(U2A-IO_0_13-PadR7)") (class "Default")
      (node (ref "U2") (pin "R7") (pinfunction "IO_0_13_R7") (pintype "bidirectional+no_connect"))
    )
    (net (code "398") (name "unconnected-(U2A-IO_L1N_T0_13-PadV9)") (class "Default")
      (node (ref "U2") (pin "V9") (pinfunction "IO_L1N_T0_13_V9") (pintype "bidirectional+no_connect"))
    )
    (net (code "399") (name "unconnected-(U2A-IO_L1P_T0_13-PadV10)") (class "Default")
      (node (ref "U2") (pin "V10") (pinfunction "IO_L1P_T0_13_V10") (pintype "bidirectional+no_connect"))
    )
    (net (code "400") (name "unconnected-(U2A-IO_L2N_T0_13-PadW8)") (class "Default")
      (node (ref "U2") (pin "W8") (pinfunction "IO_L2N_T0_13_W8") (pintype "bidirectional+no_connect"))
    )
    (net (code "401") (name "unconnected-(U2A-IO_L2P_T0_13-PadV8)") (class "Default")
      (node (ref "U2") (pin "V8") (pinfunction "IO_L2P_T0_13_V8") (pintype "bidirectional+no_connect"))
    )
    (net (code "402") (name "unconnected-(U2A-IO_L3N_T0_DQS_13-PadW10)") (class "Default")
      (node (ref "U2") (pin "W10") (pinfunction "IO_L3N_T0_DQS_13_W10") (pintype "bidirectional+no_connect"))
    )
    (net (code "403") (name "unconnected-(U2A-IO_L3P_T0_DQS_13-PadW11)") (class "Default")
      (node (ref "U2") (pin "W11") (pinfunction "IO_L3P_T0_DQS_13_W11") (pintype "bidirectional+no_connect"))
    )
    (net (code "404") (name "unconnected-(U2A-IO_L4N_T0_13-PadW12)") (class "Default")
      (node (ref "U2") (pin "W12") (pinfunction "IO_L4N_T0_13_W12") (pintype "bidirectional+no_connect"))
    )
    (net (code "405") (name "unconnected-(U2A-IO_L4P_T0_13-PadV12)") (class "Default")
      (node (ref "U2") (pin "V12") (pinfunction "IO_L4P_T0_13_V12") (pintype "bidirectional+no_connect"))
    )
    (net (code "406") (name "unconnected-(U2A-IO_L5N_T0_13-PadU11)") (class "Default")
      (node (ref "U2") (pin "U11") (pinfunction "IO_L5N_T0_13_U11") (pintype "bidirectional+no_connect"))
    )
    (net (code "407") (name "unconnected-(U2A-IO_L5P_T0_13-PadU12)") (class "Default")
      (node (ref "U2") (pin "U12") (pinfunction "IO_L5P_T0_13_U12") (pintype "bidirectional+no_connect"))
    )
    (net (code "408") (name "unconnected-(U2A-IO_L6N_T0_VREF_13-PadU9)") (class "Default")
      (node (ref "U2") (pin "U9") (pinfunction "IO_L6N_T0_VREF_13_U9") (pintype "bidirectional+no_connect"))
    )
    (net (code "409") (name "unconnected-(U2A-IO_L6P_T0_13-PadU10)") (class "Default")
      (node (ref "U2") (pin "U10") (pinfunction "IO_L6P_T0_13_U10") (pintype "bidirectional+no_connect"))
    )
    (net (code "410") (name "unconnected-(U2B-IO_25_33-PadU14)") (class "Default")
      (node (ref "U2") (pin "U14") (pinfunction "IO_25_33_U14") (pintype "bidirectional+no_connect"))
    )
    (net (code "411") (name "unconnected-(U2B-IO_L7N_T1_33-PadAB22)") (class "Default")
      (node (ref "U2") (pin "AB22") (pinfunction "IO_L7N_T1_33_AB22") (pintype "bidirectional+no_connect"))
    )
    (net (code "412") (name "unconnected-(U2B-IO_L7P_T1_33-PadAA22)") (class "Default")
      (node (ref "U2") (pin "AA22") (pinfunction "IO_L7P_T1_33_AA22") (pintype "bidirectional+no_connect"))
    )
    (net (code "413") (name "unconnected-(U2B-IO_L8N_T1_33-PadAB21)") (class "Default")
      (node (ref "U2") (pin "AB21") (pinfunction "IO_L8N_T1_33_AB21") (pintype "bidirectional+no_connect"))
    )
    (net (code "414") (name "unconnected-(U2B-IO_L10N_T1_33-PadAB20)") (class "Default")
      (node (ref "U2") (pin "AB20") (pinfunction "IO_L10N_T1_33_AB20") (pintype "bidirectional+no_connect"))
    )
    (net (code "415") (name "unconnected-(U2B-IO_L10P_T1_33-PadAB19)") (class "Default")
      (node (ref "U2") (pin "AB19") (pinfunction "IO_L10P_T1_33_AB19") (pintype "bidirectional+no_connect"))
    )
    (net (code "416") (name "unconnected-(U2B-IO_L13N_T2_MRCC_33-PadW18)") (class "Default")
      (node (ref "U2") (pin "W18") (pinfunction "IO_L13N_T2_MRCC_33_W18") (pintype "bidirectional+no_connect"))
    )
    (net (code "417") (name "unconnected-(U2B-IO_L13P_T2_MRCC_33-PadW17)") (class "Default")
      (node (ref "U2") (pin "W17") (pinfunction "IO_L13P_T2_MRCC_33_W17") (pintype "bidirectional+no_connect"))
    )
    (net (code "418") (name "unconnected-(U2B-IO_L14N_T2_SRCC_33-PadY16)") (class "Default")
      (node (ref "U2") (pin "Y16") (pinfunction "IO_L14N_T2_SRCC_33_Y16") (pintype "bidirectional+no_connect"))
    )
    (net (code "419") (name "unconnected-(U2B-IO_L14P_T2_SRCC_33-PadW16)") (class "Default")
      (node (ref "U2") (pin "W16") (pinfunction "IO_L14P_T2_SRCC_33_W16") (pintype "bidirectional+no_connect"))
    )
    (net (code "420") (name "unconnected-(U2B-IO_L15N_T2_DQS_33-PadU16)") (class "Default")
      (node (ref "U2") (pin "U16") (pinfunction "IO_L15N_T2_DQS_33_U16") (pintype "bidirectional+no_connect"))
    )
    (net (code "421") (name "unconnected-(U2B-IO_L15P_T2_DQS_33-PadU15)") (class "Default")
      (node (ref "U2") (pin "U15") (pinfunction "IO_L15P_T2_DQS_33_U15") (pintype "bidirectional+no_connect"))
    )
    (net (code "422") (name "unconnected-(U2B-IO_L16N_T2_33-PadV17)") (class "Default")
      (node (ref "U2") (pin "V17") (pinfunction "IO_L16N_T2_33_V17") (pintype "bidirectional+no_connect"))
    )
    (net (code "423") (name "unconnected-(U2B-IO_L16P_T2_33-PadU17)") (class "Default")
      (node (ref "U2") (pin "U17") (pinfunction "IO_L16P_T2_33_U17") (pintype "bidirectional+no_connect"))
    )
    (net (code "424") (name "unconnected-(U2B-IO_L17N_T2_33-PadAB17)") (class "Default")
      (node (ref "U2") (pin "AB17") (pinfunction "IO_L17N_T2_33_AB17") (pintype "bidirectional+no_connect"))
    )
    (net (code "425") (name "unconnected-(U2B-IO_L17P_T2_33-PadAA17)") (class "Default")
      (node (ref "U2") (pin "AA17") (pinfunction "IO_L17P_T2_33_AA17") (pintype "bidirectional+no_connect"))
    )
    (net (code "426") (name "unconnected-(U2B-IO_L18N_T2_33-PadAB16)") (class "Default")
      (node (ref "U2") (pin "AB16") (pinfunction "IO_L18N_T2_33_AB16") (pintype "bidirectional+no_connect"))
    )
    (net (code "427") (name "unconnected-(U2B-IO_L18P_T2_33-PadAA16)") (class "Default")
      (node (ref "U2") (pin "AA16") (pinfunction "IO_L18P_T2_33_AA16") (pintype "bidirectional+no_connect"))
    )
    (net (code "428") (name "unconnected-(U2B-IO_L19N_T3_VREF_33-PadV15)") (class "Default")
      (node (ref "U2") (pin "V15") (pinfunction "IO_L19N_T3_VREF_33_V15") (pintype "bidirectional+no_connect"))
    )
    (net (code "429") (name "unconnected-(U2B-IO_L19P_T3_33-PadV14)") (class "Default")
      (node (ref "U2") (pin "V14") (pinfunction "IO_L19P_T3_33_V14") (pintype "bidirectional+no_connect"))
    )
    (net (code "430") (name "unconnected-(U2B-IO_L20N_T3_33-PadW13)") (class "Default")
      (node (ref "U2") (pin "W13") (pinfunction "IO_L20N_T3_33_W13") (pintype "bidirectional+no_connect"))
    )
    (net (code "431") (name "unconnected-(U2B-IO_L20P_T3_33-PadV13)") (class "Default")
      (node (ref "U2") (pin "V13") (pinfunction "IO_L20P_T3_33_V13") (pintype "bidirectional+no_connect"))
    )
    (net (code "432") (name "unconnected-(U2B-IO_L21N_T3_DQS_33-PadY15)") (class "Default")
      (node (ref "U2") (pin "Y15") (pinfunction "IO_L21N_T3_DQS_33_Y15") (pintype "bidirectional+no_connect"))
    )
    (net (code "433") (name "unconnected-(U2B-IO_L21P_T3_DQS_33-PadW15)") (class "Default")
      (node (ref "U2") (pin "W15") (pinfunction "IO_L21P_T3_DQS_33_W15") (pintype "bidirectional+no_connect"))
    )
    (net (code "434") (name "unconnected-(U2B-IO_L22N_T3_33-PadAA14)") (class "Default")
      (node (ref "U2") (pin "AA14") (pinfunction "IO_L22N_T3_33_AA14") (pintype "bidirectional+no_connect"))
    )
    (net (code "435") (name "unconnected-(U2B-IO_L22P_T3_33-PadY14)") (class "Default")
      (node (ref "U2") (pin "Y14") (pinfunction "IO_L22P_T3_33_Y14") (pintype "bidirectional+no_connect"))
    )
    (net (code "436") (name "unconnected-(U2B-IO_L23N_T3_33-PadAA13)") (class "Default")
      (node (ref "U2") (pin "AA13") (pinfunction "IO_L23N_T3_33_AA13") (pintype "bidirectional+no_connect"))
    )
    (net (code "437") (name "unconnected-(U2B-IO_L23P_T3_33-PadY13)") (class "Default")
      (node (ref "U2") (pin "Y13") (pinfunction "IO_L23P_T3_33_Y13") (pintype "bidirectional+no_connect"))
    )
    (net (code "438") (name "unconnected-(U2B-IO_L24N_T3_33-PadAB15)") (class "Default")
      (node (ref "U2") (pin "AB15") (pinfunction "IO_L24N_T3_33_AB15") (pintype "bidirectional+no_connect"))
    )
    (net (code "439") (name "unconnected-(U2B-IO_L24P_T3_33-PadAB14)") (class "Default")
      (node (ref "U2") (pin "AB14") (pinfunction "IO_L24P_T3_33_AB14") (pintype "bidirectional+no_connect"))
    )
    (net (code "440") (name "unconnected-(U2C-IO_L1N_T0_34-PadK15)") (class "Default")
      (node (ref "U2") (pin "K15") (pinfunction "IO_L1N_T0_34_K15") (pintype "bidirectional+no_connect"))
    )
    (net (code "441") (name "unconnected-(U2C-IO_L1P_T0_34-PadJ15)") (class "Default")
      (node (ref "U2") (pin "J15") (pinfunction "IO_L1P_T0_34_J15") (pintype "bidirectional+no_connect"))
    )
    (net (code "442") (name "unconnected-(U2C-IO_L2N_T0_34-PadJ17)") (class "Default")
      (node (ref "U2") (pin "J17") (pinfunction "IO_L2N_T0_34_J17") (pintype "bidirectional+no_connect"))
    )
    (net (code "443") (name "unconnected-(U2C-IO_L2P_T0_34-PadJ16)") (class "Default")
      (node (ref "U2") (pin "J16") (pinfunction "IO_L2P_T0_34_J16") (pintype "bidirectional+no_connect"))
    )
    (net (code "444") (name "unconnected-(U2C-IO_L3N_T0_DQS_34-PadL16)") (class "Default")
      (node (ref "U2") (pin "L16") (pinfunction "IO_L3N_T0_DQS_34_L16") (pintype "bidirectional+no_connect"))
    )
    (net (code "445") (name "unconnected-(U2C-IO_L4N_T0_34-PadM17)") (class "Default")
      (node (ref "U2") (pin "M17") (pinfunction "IO_L4N_T0_34_M17") (pintype "bidirectional+no_connect"))
    )
    (net (code "446") (name "unconnected-(U2C-IO_L4P_T0_34-PadL17)") (class "Default")
      (node (ref "U2") (pin "L17") (pinfunction "IO_L4P_T0_34_L17") (pintype "bidirectional+no_connect"))
    )
    (net (code "447") (name "unconnected-(U2C-IO_L5N_T0_34-PadN18)") (class "Default")
      (node (ref "U2") (pin "N18") (pinfunction "IO_L5N_T0_34_N18") (pintype "bidirectional+no_connect"))
    )
    (net (code "448") (name "unconnected-(U2C-IO_L5P_T0_34-PadN17)") (class "Default")
      (node (ref "U2") (pin "N17") (pinfunction "IO_L5P_T0_34_N17") (pintype "bidirectional+no_connect"))
    )
    (net (code "449") (name "unconnected-(U2C-IO_L6N_T0_VREF_34-PadM16)") (class "Default")
      (node (ref "U2") (pin "M16") (pinfunction "IO_L6N_T0_VREF_34_M16") (pintype "bidirectional+no_connect"))
    )
    (net (code "450") (name "unconnected-(U2C-IO_L6P_T0_34-PadM15)") (class "Default")
      (node (ref "U2") (pin "M15") (pinfunction "IO_L6P_T0_34_M15") (pintype "bidirectional+no_connect"))
    )
    (net (code "451") (name "unconnected-(U2C-IO_L7N_T1_34-PadK18)") (class "Default")
      (node (ref "U2") (pin "K18") (pinfunction "IO_L7N_T1_34_K18") (pintype "bidirectional+no_connect"))
    )
    (net (code "452") (name "unconnected-(U2C-IO_L7P_T1_34-PadJ18)") (class "Default")
      (node (ref "U2") (pin "J18") (pinfunction "IO_L7P_T1_34_J18") (pintype "bidirectional+no_connect"))
    )
    (net (code "453") (name "unconnected-(U2C-IO_L8N_T1_34-PadJ22)") (class "Default")
      (node (ref "U2") (pin "J22") (pinfunction "IO_L8N_T1_34_J22") (pintype "bidirectional+no_connect"))
    )
    (net (code "454") (name "unconnected-(U2C-IO_L8P_T1_34-PadJ21)") (class "Default")
      (node (ref "U2") (pin "J21") (pinfunction "IO_L8P_T1_34_J21") (pintype "bidirectional+no_connect"))
    )
    (net (code "455") (name "unconnected-(U2C-IO_L9N_T1_DQS_34-PadK21)") (class "Default")
      (node (ref "U2") (pin "K21") (pinfunction "IO_L9N_T1_DQS_34_K21") (pintype "bidirectional+no_connect"))
    )
    (net (code "456") (name "unconnected-(U2C-IO_L9P_T1_DQS_34-PadJ20)") (class "Default")
      (node (ref "U2") (pin "J20") (pinfunction "IO_L9P_T1_DQS_34_J20") (pintype "bidirectional+no_connect"))
    )
    (net (code "457") (name "unconnected-(U2C-IO_L10N_T1_34-PadL22)") (class "Default")
      (node (ref "U2") (pin "L22") (pinfunction "IO_L10N_T1_34_L22") (pintype "bidirectional+no_connect"))
    )
    (net (code "458") (name "unconnected-(U2C-IO_L10P_T1_34-PadL21)") (class "Default")
      (node (ref "U2") (pin "L21") (pinfunction "IO_L10P_T1_34_L21") (pintype "bidirectional+no_connect"))
    )
    (net (code "459") (name "unconnected-(U2C-IO_L12N_T1_MRCC_34-PadL19)") (class "Default")
      (node (ref "U2") (pin "L19") (pinfunction "IO_L12N_T1_MRCC_34_L19") (pintype "bidirectional+no_connect"))
    )
    (net (code "460") (name "unconnected-(U2C-IO_L12P_T1_MRCC_34-PadL18)") (class "Default")
      (node (ref "U2") (pin "L18") (pinfunction "IO_L12P_T1_MRCC_34_L18") (pintype "bidirectional+no_connect"))
    )
    (net (code "461") (name "unconnected-(U2C-IO_L17N_T2_34-PadR21)") (class "Default")
      (node (ref "U2") (pin "R21") (pinfunction "IO_L17N_T2_34_R21") (pintype "bidirectional+no_connect"))
    )
    (net (code "462") (name "unconnected-(U2C-IO_L17P_T2_34-PadR20)") (class "Default")
      (node (ref "U2") (pin "R20") (pinfunction "IO_L17P_T2_34_R20") (pintype "bidirectional+no_connect"))
    )
    (net (code "463") (name "unconnected-(U2C-IO_L18N_T2_34-PadP21)") (class "Default")
      (node (ref "U2") (pin "P21") (pinfunction "IO_L18N_T2_34_P21") (pintype "bidirectional+no_connect"))
    )
    (net (code "464") (name "unconnected-(U2C-IO_L18P_T2_34-PadP20)") (class "Default")
      (node (ref "U2") (pin "P20") (pinfunction "IO_L18P_T2_34_P20") (pintype "bidirectional+no_connect"))
    )
    (net (code "465") (name "unconnected-(U2C-IO_L19N_T3_VREF_34-PadP15)") (class "Default")
      (node (ref "U2") (pin "P15") (pinfunction "IO_L19N_T3_VREF_34_P15") (pintype "bidirectional+no_connect"))
    )
    (net (code "466") (name "unconnected-(U2C-IO_L19P_T3_34-PadN15)") (class "Default")
      (node (ref "U2") (pin "N15") (pinfunction "IO_L19P_T3_34_N15") (pintype "bidirectional+no_connect"))
    )
    (net (code "467") (name "unconnected-(U2C-IO_L20N_T3_34-PadP18)") (class "Default")
      (node (ref "U2") (pin "P18") (pinfunction "IO_L20N_T3_34_P18") (pintype "bidirectional+no_connect"))
    )
    (net (code "468") (name "unconnected-(U2C-IO_L20P_T3_34-PadP17)") (class "Default")
      (node (ref "U2") (pin "P17") (pinfunction "IO_L20P_T3_34_P17") (pintype "bidirectional+no_connect"))
    )
    (net (code "469") (name "unconnected-(U2C-IO_L21N_T3_DQS_34-PadT17)") (class "Default")
      (node (ref "U2") (pin "T17") (pinfunction "IO_L21N_T3_DQS_34_T17") (pintype "bidirectional+no_connect"))
    )
    (net (code "470") (name "unconnected-(U2C-IO_L21P_T3_DQS_34-PadT16)") (class "Default")
      (node (ref "U2") (pin "T16") (pinfunction "IO_L21P_T3_DQS_34_T16") (pintype "bidirectional+no_connect"))
    )
    (net (code "471") (name "unconnected-(U2C-IO_L22N_T3_34-PadT19)") (class "Default")
      (node (ref "U2") (pin "T19") (pinfunction "IO_L22N_T3_34_T19") (pintype "bidirectional+no_connect"))
    )
    (net (code "472") (name "unconnected-(U2C-IO_L22P_T3_34-PadR19)") (class "Default")
      (node (ref "U2") (pin "R19") (pinfunction "IO_L22P_T3_34_R19") (pintype "bidirectional+no_connect"))
    )
    (net (code "473") (name "unconnected-(U2C-IO_L23N_T3_34-PadT18)") (class "Default")
      (node (ref "U2") (pin "T18") (pinfunction "IO_L23N_T3_34_T18") (pintype "bidirectional+no_connect"))
    )
    (net (code "474") (name "unconnected-(U2C-IO_L23P_T3_34-PadR18)") (class "Default")
      (node (ref "U2") (pin "R18") (pinfunction "IO_L23P_T3_34_R18") (pintype "bidirectional+no_connect"))
    )
    (net (code "475") (name "unconnected-(U2C-IO_L24N_T3_34-PadR16)") (class "Default")
      (node (ref "U2") (pin "R16") (pinfunction "IO_L24N_T3_34_R16") (pintype "bidirectional+no_connect"))
    )
    (net (code "476") (name "unconnected-(U2C-IO_L24P_T3_34-PadP16)") (class "Default")
      (node (ref "U2") (pin "P16") (pinfunction "IO_L24P_T3_34_P16") (pintype "bidirectional+no_connect"))
    )
    (net (code "477") (name "unconnected-(U2D-IO_0_35-PadH17)") (class "Default")
      (node (ref "U2") (pin "H17") (pinfunction "IO_0_35_H17") (pintype "bidirectional+no_connect"))
    )
    (net (code "478") (name "unconnected-(U2D-IO_25_35-PadH18)") (class "Default")
      (node (ref "U2") (pin "H18") (pinfunction "IO_25_35_H18") (pintype "bidirectional+no_connect"))
    )
    (net (code "479") (name "unconnected-(U2D-IO_L1N_T0_AD0N_35-PadE16)") (class "Default")
      (node (ref "U2") (pin "E16") (pinfunction "IO_L1N_T0_AD0N_35_E16") (pintype "bidirectional+no_connect"))
    )
    (net (code "480") (name "unconnected-(U2D-IO_L1P_T0_AD0P_35-PadF16)") (class "Default")
      (node (ref "U2") (pin "F16") (pinfunction "IO_L1P_T0_AD0P_35_F16") (pintype "bidirectional+no_connect"))
    )
    (net (code "481") (name "unconnected-(U2D-IO_L2N_T0_AD8N_35-PadD17)") (class "Default")
      (node (ref "U2") (pin "D17") (pinfunction "IO_L2N_T0_AD8N_35_D17") (pintype "bidirectional+no_connect"))
    )
    (net (code "482") (name "unconnected-(U2D-IO_L2P_T0_AD8P_35-PadD16)") (class "Default")
      (node (ref "U2") (pin "D16") (pinfunction "IO_L2P_T0_AD8P_35_D16") (pintype "bidirectional+no_connect"))
    )
    (net (code "483") (name "unconnected-(U2D-IO_L3N_T0_DQS_AD1N_35-PadD15)") (class "Default")
      (node (ref "U2") (pin "D15") (pinfunction "IO_L3N_T0_DQS_AD1N_35_D15") (pintype "bidirectional+no_connect"))
    )
    (net (code "484") (name "unconnected-(U2D-IO_L3P_T0_DQS_AD1P_35-PadE15)") (class "Default")
      (node (ref "U2") (pin "E15") (pinfunction "IO_L3P_T0_DQS_AD1P_35_E15") (pintype "bidirectional+no_connect"))
    )
    (net (code "485") (name "unconnected-(U2D-IO_L4N_T0_35-PadG16)") (class "Default")
      (node (ref "U2") (pin "G16") (pinfunction "IO_L4N_T0_35_G16") (pintype "bidirectional+no_connect"))
    )
    (net (code "486") (name "unconnected-(U2D-IO_L4P_T0_35-PadG15)") (class "Default")
      (node (ref "U2") (pin "G15") (pinfunction "IO_L4P_T0_35_G15") (pintype "bidirectional+no_connect"))
    )
    (net (code "487") (name "unconnected-(U2D-IO_L5N_T0_AD9N_35-PadE18)") (class "Default")
      (node (ref "U2") (pin "E18") (pinfunction "IO_L5N_T0_AD9N_35_E18") (pintype "bidirectional+no_connect"))
    )
    (net (code "488") (name "unconnected-(U2D-IO_L5P_T0_AD9P_35-PadF18)") (class "Default")
      (node (ref "U2") (pin "F18") (pinfunction "IO_L5P_T0_AD9P_35_F18") (pintype "bidirectional+no_connect"))
    )
    (net (code "489") (name "unconnected-(U2D-IO_L6N_T0_VREF_35-PadF17)") (class "Default")
      (node (ref "U2") (pin "F17") (pinfunction "IO_L6N_T0_VREF_35_F17") (pintype "bidirectional+no_connect"))
    )
    (net (code "490") (name "unconnected-(U2D-IO_L6P_T0_35-PadG17)") (class "Default")
      (node (ref "U2") (pin "G17") (pinfunction "IO_L6P_T0_35_G17") (pintype "bidirectional+no_connect"))
    )
    (net (code "491") (name "unconnected-(U2D-IO_L7N_T1_AD2N_35-PadB15)") (class "Default")
      (node (ref "U2") (pin "B15") (pinfunction "IO_L7N_T1_AD2N_35_B15") (pintype "bidirectional+no_connect"))
    )
    (net (code "492") (name "unconnected-(U2D-IO_L7P_T1_AD2P_35-PadC15)") (class "Default")
      (node (ref "U2") (pin "C15") (pinfunction "IO_L7P_T1_AD2P_35_C15") (pintype "bidirectional+no_connect"))
    )
    (net (code "493") (name "unconnected-(U2D-IO_L9N_T1_DQS_AD3N_35-PadA17)") (class "Default")
      (node (ref "U2") (pin "A17") (pinfunction "IO_L9N_T1_DQS_AD3N_35_A17") (pintype "bidirectional+no_connect"))
    )
    (net (code "494") (name "unconnected-(U2D-IO_L9P_T1_DQS_AD3P_35-PadA16)") (class "Default")
      (node (ref "U2") (pin "A16") (pinfunction "IO_L9P_T1_DQS_AD3P_35_A16") (pintype "bidirectional+no_connect"))
    )
    (net (code "495") (name "unconnected-(U2D-IO_L15N_T2_DQS_AD12N_35-PadA22)") (class "Default")
      (node (ref "U2") (pin "A22") (pinfunction "IO_L15N_T2_DQS_AD12N_35_A22") (pintype "bidirectional+no_connect"))
    )
    (net (code "496") (name "unconnected-(U2D-IO_L15P_T2_DQS_AD12P_35-PadA21)") (class "Default")
      (node (ref "U2") (pin "A21") (pinfunction "IO_L15P_T2_DQS_AD12P_35_A21") (pintype "bidirectional+no_connect"))
    )
    (net (code "497") (name "unconnected-(U2D-IO_L16N_T2_35-PadC22)") (class "Default")
      (node (ref "U2") (pin "C22") (pinfunction "IO_L16N_T2_35_C22") (pintype "bidirectional+no_connect"))
    )
    (net (code "498") (name "unconnected-(U2D-IO_L16P_T2_35-PadD22)") (class "Default")
      (node (ref "U2") (pin "D22") (pinfunction "IO_L16P_T2_35_D22") (pintype "bidirectional+no_connect"))
    )
    (net (code "499") (name "unconnected-(U2D-IO_L17N_T2_AD5N_35-PadD21)") (class "Default")
      (node (ref "U2") (pin "D21") (pinfunction "IO_L17N_T2_AD5N_35_D21") (pintype "bidirectional+no_connect"))
    )
    (net (code "500") (name "unconnected-(U2D-IO_L17P_T2_AD5P_35-PadE21)") (class "Default")
      (node (ref "U2") (pin "E21") (pinfunction "IO_L17P_T2_AD5P_35_E21") (pintype "bidirectional+no_connect"))
    )
    (net (code "501") (name "unconnected-(U2D-IO_L18N_T2_AD13N_35-PadB22)") (class "Default")
      (node (ref "U2") (pin "B22") (pinfunction "IO_L18N_T2_AD13N_35_B22") (pintype "bidirectional+no_connect"))
    )
    (net (code "502") (name "unconnected-(U2D-IO_L18P_T2_AD13P_35-PadB21)") (class "Default")
      (node (ref "U2") (pin "B21") (pinfunction "IO_L18P_T2_AD13P_35_B21") (pintype "bidirectional+no_connect"))
    )
    (net (code "503") (name "unconnected-(U2D-IO_L19P_T3_35-PadH19)") (class "Default")
      (node (ref "U2") (pin "H19") (pinfunction "IO_L19P_T3_35_H19") (pintype "bidirectional+no_connect"))
    )
    (net (code "504") (name "unconnected-(U2D-IO_L20N_T3_AD6N_35-PadF19)") (class "Default")
      (node (ref "U2") (pin "F19") (pinfunction "IO_L20N_T3_AD6N_35_F19") (pintype "bidirectional+no_connect"))
    )
    (net (code "505") (name "unconnected-(U2D-IO_L20P_T3_AD6P_35-PadG19)") (class "Default")
      (node (ref "U2") (pin "G19") (pinfunction "IO_L20P_T3_AD6P_35_G19") (pintype "bidirectional+no_connect"))
    )
    (net (code "506") (name "unconnected-(U2D-IO_L21N_T3_DQS_AD14N_35-PadE20)") (class "Default")
      (node (ref "U2") (pin "E20") (pinfunction "IO_L21N_T3_DQS_AD14N_35_E20") (pintype "bidirectional+no_connect"))
    )
    (net (code "507") (name "unconnected-(U2D-IO_L21P_T3_DQS_AD14P_35-PadE19)") (class "Default")
      (node (ref "U2") (pin "E19") (pinfunction "IO_L21P_T3_DQS_AD14P_35_E19") (pintype "bidirectional+no_connect"))
    )
    (net (code "508") (name "unconnected-(U2D-IO_L22N_T3_AD7N_35-PadG21)") (class "Default")
      (node (ref "U2") (pin "G21") (pinfunction "IO_L22N_T3_AD7N_35_G21") (pintype "bidirectional+no_connect"))
    )
    (net (code "509") (name "unconnected-(U2D-IO_L22P_T3_AD7P_35-PadG20)") (class "Default")
      (node (ref "U2") (pin "G20") (pinfunction "IO_L22P_T3_AD7P_35_G20") (pintype "bidirectional+no_connect"))
    )
    (net (code "510") (name "unconnected-(U2D-IO_L23N_T3_35-PadF22)") (class "Default")
      (node (ref "U2") (pin "F22") (pinfunction "IO_L23N_T3_35_F22") (pintype "bidirectional+no_connect"))
    )
    (net (code "511") (name "unconnected-(U2D-IO_L23P_T3_35-PadF21)") (class "Default")
      (node (ref "U2") (pin "F21") (pinfunction "IO_L23P_T3_35_F21") (pintype "bidirectional+no_connect"))
    )
    (net (code "512") (name "unconnected-(U2D-IO_L24N_T3_AD15N_35-PadG22)") (class "Default")
      (node (ref "U2") (pin "G22") (pinfunction "IO_L24N_T3_AD15N_35_G22") (pintype "bidirectional+no_connect"))
    )
    (net (code "513") (name "unconnected-(U2D-IO_L24P_T3_AD15P_35-PadH22)") (class "Default")
      (node (ref "U2") (pin "H22") (pinfunction "IO_L24P_T3_AD15P_35_H22") (pintype "bidirectional+no_connect"))
    )
    (net (code "514") (name "unconnected-(U2J-RSVDGND-PadG10)") (class "Default")
      (node (ref "U2") (pin "G10") (pinfunction "RSVDGND_G10") (pintype "unspecified+no_connect"))
    )
    (net (code "515") (name "unconnected-(U3-NC-PadJ1)") (class "Default")
      (node (ref "U3") (pin "J1") (pinfunction "NC_J1") (pintype "input+no_connect"))
    )
    (net (code "516") (name "unconnected-(U3-NC-PadJ9)") (class "Default")
      (node (ref "U3") (pin "J9") (pinfunction "NC_J9") (pintype "input+no_connect"))
    )
    (net (code "517") (name "unconnected-(U3-NC-PadL1)") (class "Default")
      (node (ref "U3") (pin "L1") (pinfunction "NC_L1") (pintype "input+no_connect"))
    )
    (net (code "518") (name "unconnected-(U3-NC-PadL9)") (class "Default")
      (node (ref "U3") (pin "L9") (pinfunction "NC_L9") (pintype "input+no_connect"))
    )
    (net (code "519") (name "unconnected-(U3-NC-PadM7)") (class "Default")
      (node (ref "U3") (pin "M7") (pinfunction "NC_M7") (pintype "input+no_connect"))
    )
    (net (code "520") (name "unconnected-(U27-CC1-PadA5)") (class "Default")
      (node (ref "U27") (pin "A5") (pinfunction "CC1_A5") (pintype "unspecified+no_connect"))
    )
    (net (code "521") (name "unconnected-(U27-CC2-PadB5)") (class "Default")
      (node (ref "U27") (pin "B5") (pinfunction "CC2_B5") (pintype "unspecified+no_connect"))
    )
    (net (code "522") (name "unconnected-(U27-DN2-PadB7)") (class "Default")
      (node (ref "U27") (pin "B7") (pinfunction "DN2_B7") (pintype "unspecified+no_connect"))
    )
    (net (code "523") (name "unconnected-(U27-DP2-PadB6)") (class "Default")
      (node (ref "U27") (pin "B6") (pinfunction "DP2_B6") (pintype "unspecified+no_connect"))
    )
    (net (code "524") (name "unconnected-(U27-SBU1-PadA8)") (class "Default")
      (node (ref "U27") (pin "A8") (pinfunction "SBU1_A8") (pintype "unspecified+no_connect"))
    )
    (net (code "525") (name "unconnected-(U27-SBU2-PadB8)") (class "Default")
      (node (ref "U27") (pin "B8") (pinfunction "SBU2_B8") (pintype "unspecified+no_connect"))
    )
    (net (code "526") (name "unconnected-(U34-ACBUS0-Pad26)") (class "Default")
      (node (ref "U34") (pin "26") (pinfunction "ACBUS0_26") (pintype "bidirectional+no_connect"))
    )
    (net (code "527") (name "unconnected-(U34-ACBUS1-Pad27)") (class "Default")
      (node (ref "U34") (pin "27") (pinfunction "ACBUS1_27") (pintype "bidirectional+no_connect"))
    )
    (net (code "528") (name "unconnected-(U34-ACBUS2-Pad28)") (class "Default")
      (node (ref "U34") (pin "28") (pinfunction "ACBUS2_28") (pintype "bidirectional+no_connect"))
    )
    (net (code "529") (name "unconnected-(U34-ACBUS3-Pad29)") (class "Default")
      (node (ref "U34") (pin "29") (pinfunction "ACBUS3_29") (pintype "bidirectional+no_connect"))
    )
    (net (code "530") (name "unconnected-(U34-ACBUS4-Pad30)") (class "Default")
      (node (ref "U34") (pin "30") (pinfunction "ACBUS4_30") (pintype "bidirectional+no_connect"))
    )
    (net (code "531") (name "unconnected-(U34-ACBUS5-Pad32)") (class "Default")
      (node (ref "U34") (pin "32") (pinfunction "ACBUS5_32") (pintype "bidirectional+no_connect"))
    )
    (net (code "532") (name "unconnected-(U34-ACBUS6-Pad33)") (class "Default")
      (node (ref "U34") (pin "33") (pinfunction "ACBUS6_33") (pintype "bidirectional+no_connect"))
    )
    (net (code "533") (name "unconnected-(U34-ACBUS7-Pad34)") (class "Default")
      (node (ref "U34") (pin "34") (pinfunction "ACBUS7_34") (pintype "bidirectional+no_connect"))
    )
    (net (code "534") (name "unconnected-(U34-ADBUS6-Pad23)") (class "Default")
      (node (ref "U34") (pin "23") (pinfunction "ADBUS6_23") (pintype "bidirectional+no_connect"))
    )
    (net (code "535") (name "unconnected-(U34-ADBUS7-Pad24)") (class "Default")
      (node (ref "U34") (pin "24") (pinfunction "ADBUS7_24") (pintype "bidirectional+no_connect"))
    )
    (net (code "536") (name "unconnected-(U34-BCBUS0-Pad48)") (class "Default")
      (node (ref "U34") (pin "48") (pinfunction "BCBUS0_48") (pintype "bidirectional+no_connect"))
    )
    (net (code "537") (name "unconnected-(U34-BCBUS1-Pad52)") (class "Default")
      (node (ref "U34") (pin "52") (pinfunction "BCBUS1_52") (pintype "bidirectional+no_connect"))
    )
    (net (code "538") (name "unconnected-(U34-BCBUS2-Pad53)") (class "Default")
      (node (ref "U34") (pin "53") (pinfunction "BCBUS2_53") (pintype "bidirectional+no_connect"))
    )
    (net (code "539") (name "unconnected-(U34-BCBUS5-Pad57)") (class "Default")
      (node (ref "U34") (pin "57") (pinfunction "BCBUS5_57") (pintype "bidirectional+no_connect"))
    )
    (net (code "540") (name "unconnected-(U34-BCBUS6-Pad58)") (class "Default")
      (node (ref "U34") (pin "58") (pinfunction "BCBUS6_58") (pintype "bidirectional+no_connect"))
    )
    (net (code "541") (name "unconnected-(U34-BCBUS7-Pad59)") (class "Default")
      (node (ref "U34") (pin "59") (pinfunction "BCBUS7_59") (pintype "bidirectional+no_connect"))
    )
    (net (code "542") (name "unconnected-(U34-BDBUS2-Pad40)") (class "Default")
      (node (ref "U34") (pin "40") (pinfunction "BDBUS2_40") (pintype "bidirectional+no_connect"))
    )
    (net (code "543") (name "unconnected-(U34-BDBUS3-Pad41)") (class "Default")
      (node (ref "U34") (pin "41") (pinfunction "BDBUS3_41") (pintype "bidirectional+no_connect"))
    )
    (net (code "544") (name "unconnected-(U34-BDBUS4-Pad43)") (class "Default")
      (node (ref "U34") (pin "43") (pinfunction "BDBUS4_43") (pintype "bidirectional+no_connect"))
    )
    (net (code "545") (name "unconnected-(U34-BDBUS5-Pad44)") (class "Default")
      (node (ref "U34") (pin "44") (pinfunction "BDBUS5_44") (pintype "bidirectional+no_connect"))
    )
    (net (code "546") (name "unconnected-(U34-BDBUS6-Pad45)") (class "Default")
      (node (ref "U34") (pin "45") (pinfunction "BDBUS6_45") (pintype "bidirectional+no_connect"))
    )
    (net (code "547") (name "unconnected-(U34-BDBUS7-Pad46)") (class "Default")
      (node (ref "U34") (pin "46") (pinfunction "BDBUS7_46") (pintype "bidirectional+no_connect"))
    )
    (net (code "548") (name "unconnected-(U34-OSCO-Pad3)") (class "Default")
      (node (ref "U34") (pin "3") (pinfunction "OSCO_3") (pintype "output+no_connect"))
    )
    (net (code "549") (name "unconnected-(U34-PWREN#-Pad60)") (class "Default")
      (node (ref "U34") (pin "60") (pinfunction "PWREN#_60") (pintype "output+no_connect"))
    )
    (net (code "550") (name "unconnected-(U34-SUSPEND#-Pad36)") (class "Default")
      (node (ref "U34") (pin "36") (pinfunction "SUSPEND#_36") (pintype "output+no_connect"))
    )
    (net (code "551") (name "unconnected-(U36-N{slash}C-Pad12)") (class "Default")
      (node (ref "U36") (pin "12") (pinfunction "N/C_12") (pintype "input+no_connect"))
    )
    (net (code "552") (name "unconnected-(U36-SPK_L-Pad15)") (class "Default")
      (node (ref "U36") (pin "15") (pinfunction "SPK_L_15") (pintype "input+no_connect"))
    )
    (net (code "553") (name "unconnected-(U36-SPK_R-Pad16)") (class "Default")
      (node (ref "U36") (pin "16") (pinfunction "SPK_R_16") (pintype "input+no_connect"))
    )
    (net (code "554") (name "unconnected-(U36-XO-Pad25)") (class "Default")
      (node (ref "U36") (pin "25") (pinfunction "XO_25") (pintype "input+no_connect"))
    )
    (net (code "555") (name "unconnected-(U60-NC-Pad7)") (class "Default")
      (node (ref "U60") (pin "7") (pinfunction "NC_7") (pintype "input+no_connect"))
    )
    (net (code "556") (name "unconnected-(U60-ORG*-Pad6)") (class "Default")
      (node (ref "U60") (pin "6") (pinfunction "ORG*_6") (pintype "input+no_connect"))
    )
    (net (code "557") (name "unconnected-(U61-N.C.-Pad1)") (class "Default")
      (node (ref "U61") (pin "1") (pinfunction "N.C._1") (pintype "input+no_connect"))
    )
    (net (code "558") (name "unconnected-(U73-FAULTB-Pad3)") (class "Default")
      (node (ref "U73") (pin "3") (pinfunction "FAULTB_3") (pintype "input+no_connect"))
    )
    (net (code "559") (name "unconnected-(U74-CLKB1-Pad13)") (class "Default")
      (node (ref "U74") (pin "13") (pinfunction "CLKB1_13") (pintype "unspecified+no_connect"))
    )
    (net (code "560") (name "unconnected-(U74-CMDB1-Pad12)") (class "Default")
      (node (ref "U74") (pin "12") (pinfunction "CMDB1_12") (pintype "unspecified+no_connect"))
    )
    (net (code "561") (name "unconnected-(U74-DAT0B1-Pad14)") (class "Default")
      (node (ref "U74") (pin "14") (pinfunction "DAT0B1_14") (pintype "unspecified+no_connect"))
    )
    (net (code "562") (name "unconnected-(U74-DAT1B1-Pad15)") (class "Default")
      (node (ref "U74") (pin "15") (pinfunction "DAT1B1_15") (pintype "unspecified+no_connect"))
    )
    (net (code "563") (name "unconnected-(U74-DAT2B1-Pad8)") (class "Default")
      (node (ref "U74") (pin "8") (pinfunction "DAT2B1_8") (pintype "unspecified+no_connect"))
    )
    (net (code "564") (name "unconnected-(U74-DAT3B1-Pad10)") (class "Default")
      (node (ref "U74") (pin "10") (pinfunction "DAT3B1_10") (pintype "unspecified+no_connect"))
    )
    (net (code "565") (name "~PS_POR") (class "Default")
      (node (ref "C194") (pin "1") (pinfunction "1_1") (pintype "input"))
      (node (ref "R221") (pin "2") (pinfunction "2_2") (pintype "input"))
      (node (ref "R76") (pin "2") (pinfunction "2_2") (pintype "input"))
      (node (ref "U2") (pin "B5") (pinfunction "PS_POR_B_500_B5") (pintype "input"))
      (node (ref "U61") (pin "4") (pinfunction "Y_4") (pintype "input"))
    )
    (net (code "566") (name "~PS_RST") (class "Default")
      (node (ref "C195") (pin "1") (pinfunction "1_1") (pintype "input"))
      (node (ref "HDR1") (pin "14") (pinfunction "PS_SRSTB_14") (pintype "input"))
      (node (ref "R77") (pin "2") (pinfunction "2_2") (pintype "input"))
      (node (ref "SW2") (pin "1") (pinfunction "1_1") (pintype "input"))
      (node (ref "SW2") (pin "2") (pinfunction "2_2") (pintype "input"))
      (node (ref "U2") (pin "C9") (pinfunction "PS_SRST_B_501_C9") (pintype "input"))
    )
  )
)
